# SLB_EXT_EAGLE.net
KiCad netlist of a schematic drawn in EAGLE
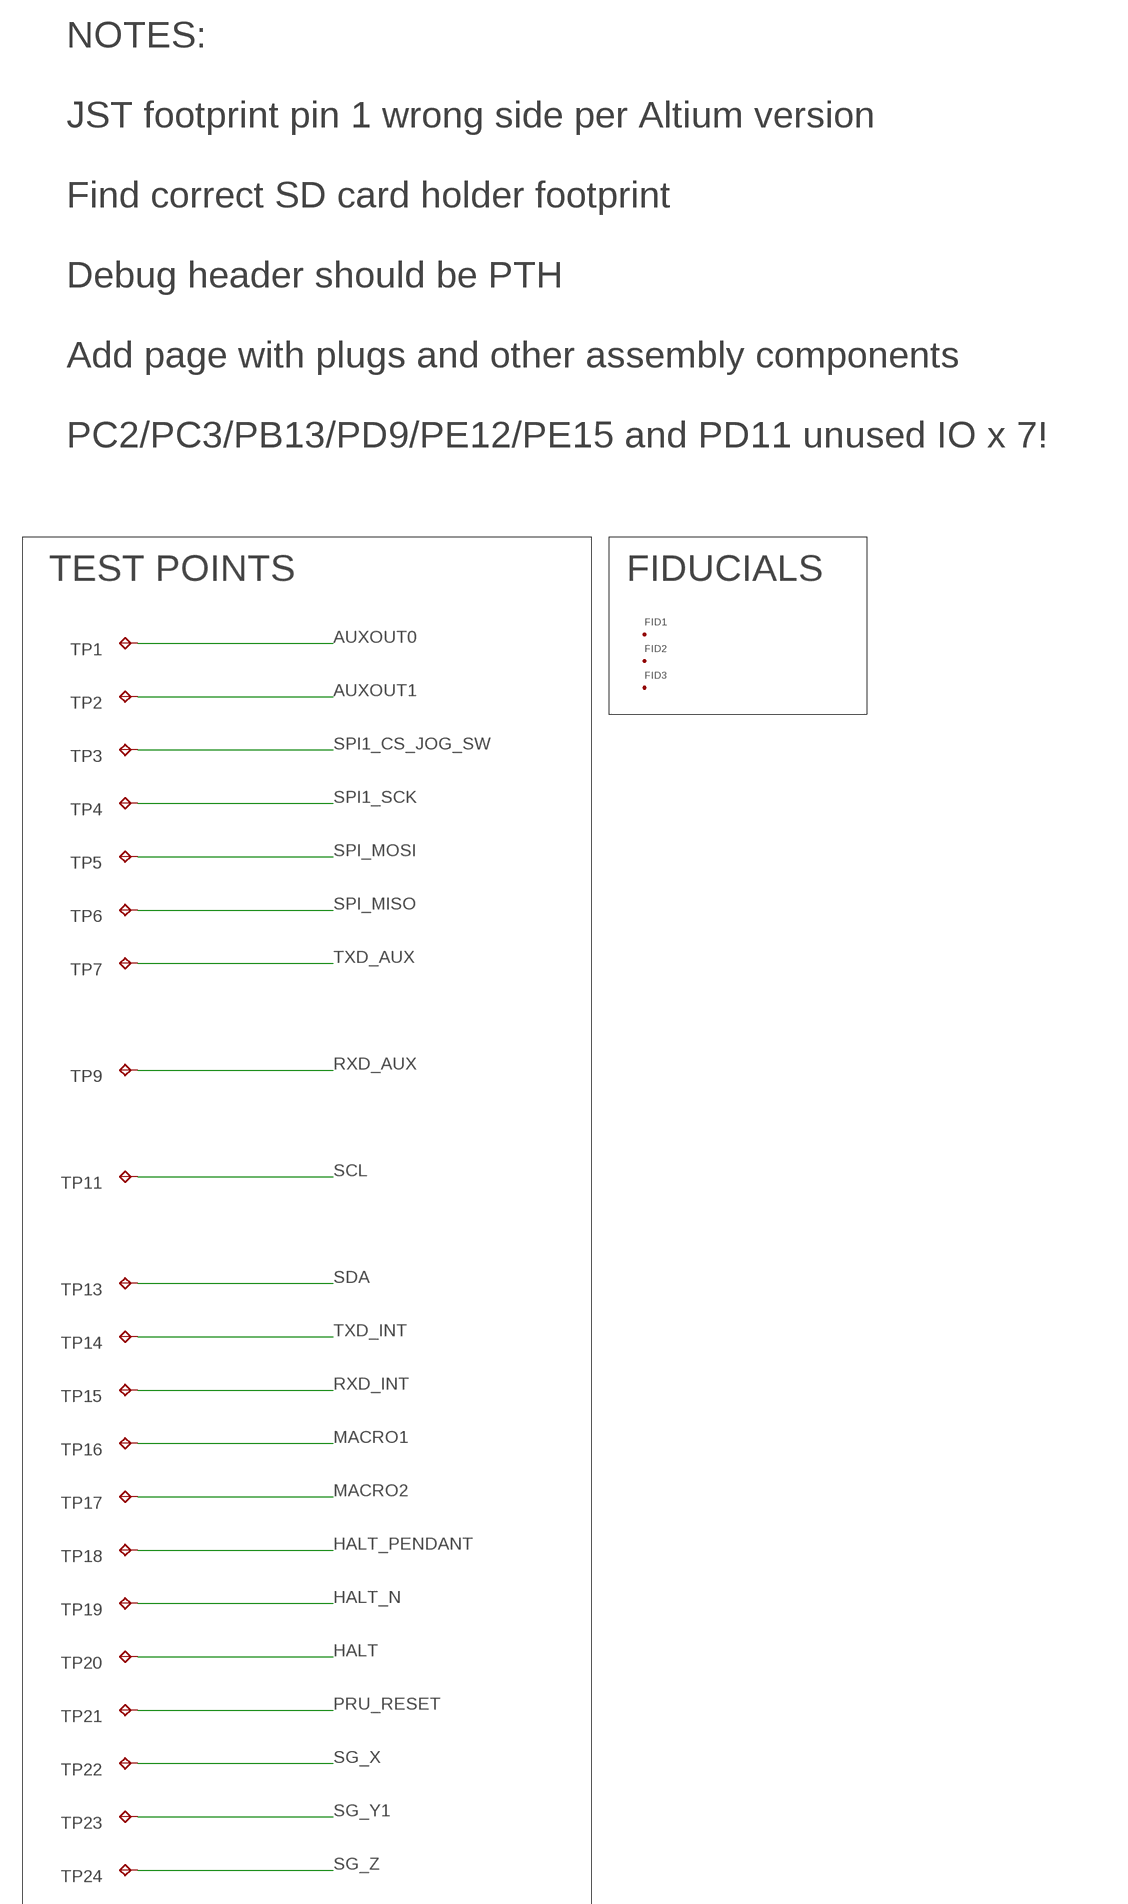
[diagram p0: schematic, sheet 1, part 1 of 2]
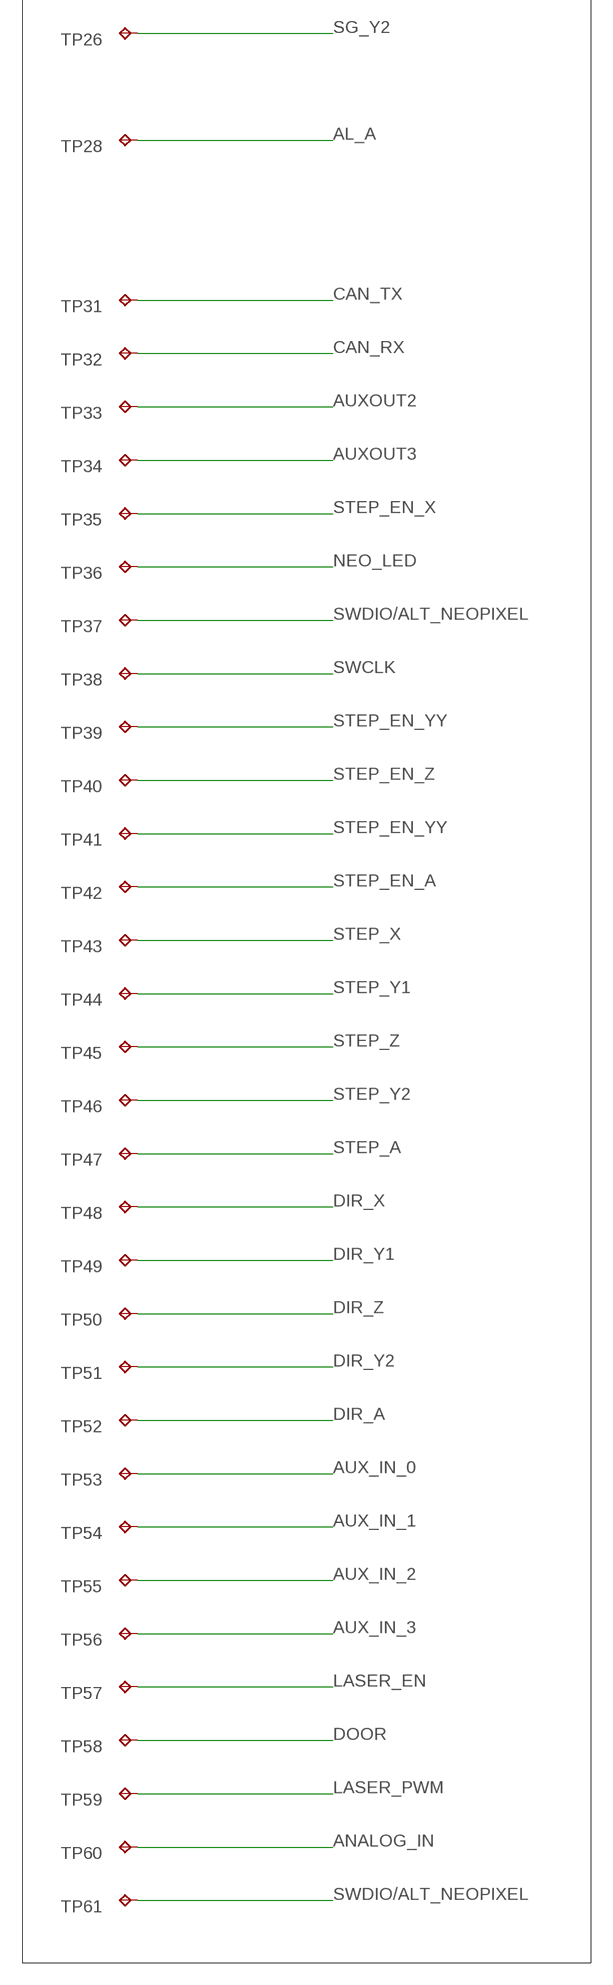
[diagram p1: schematic, sheet 1, part 2 of 2]
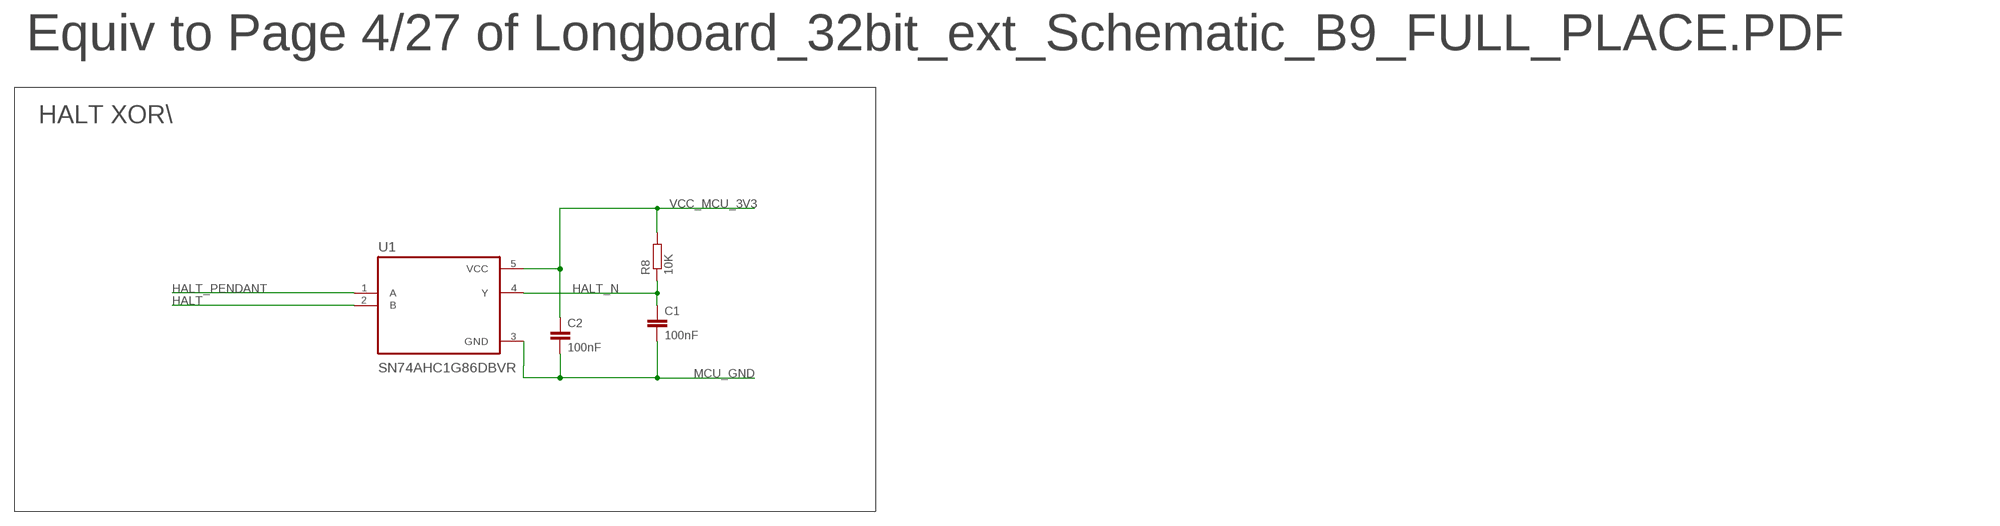
[diagram p2: schematic, sheet 2]
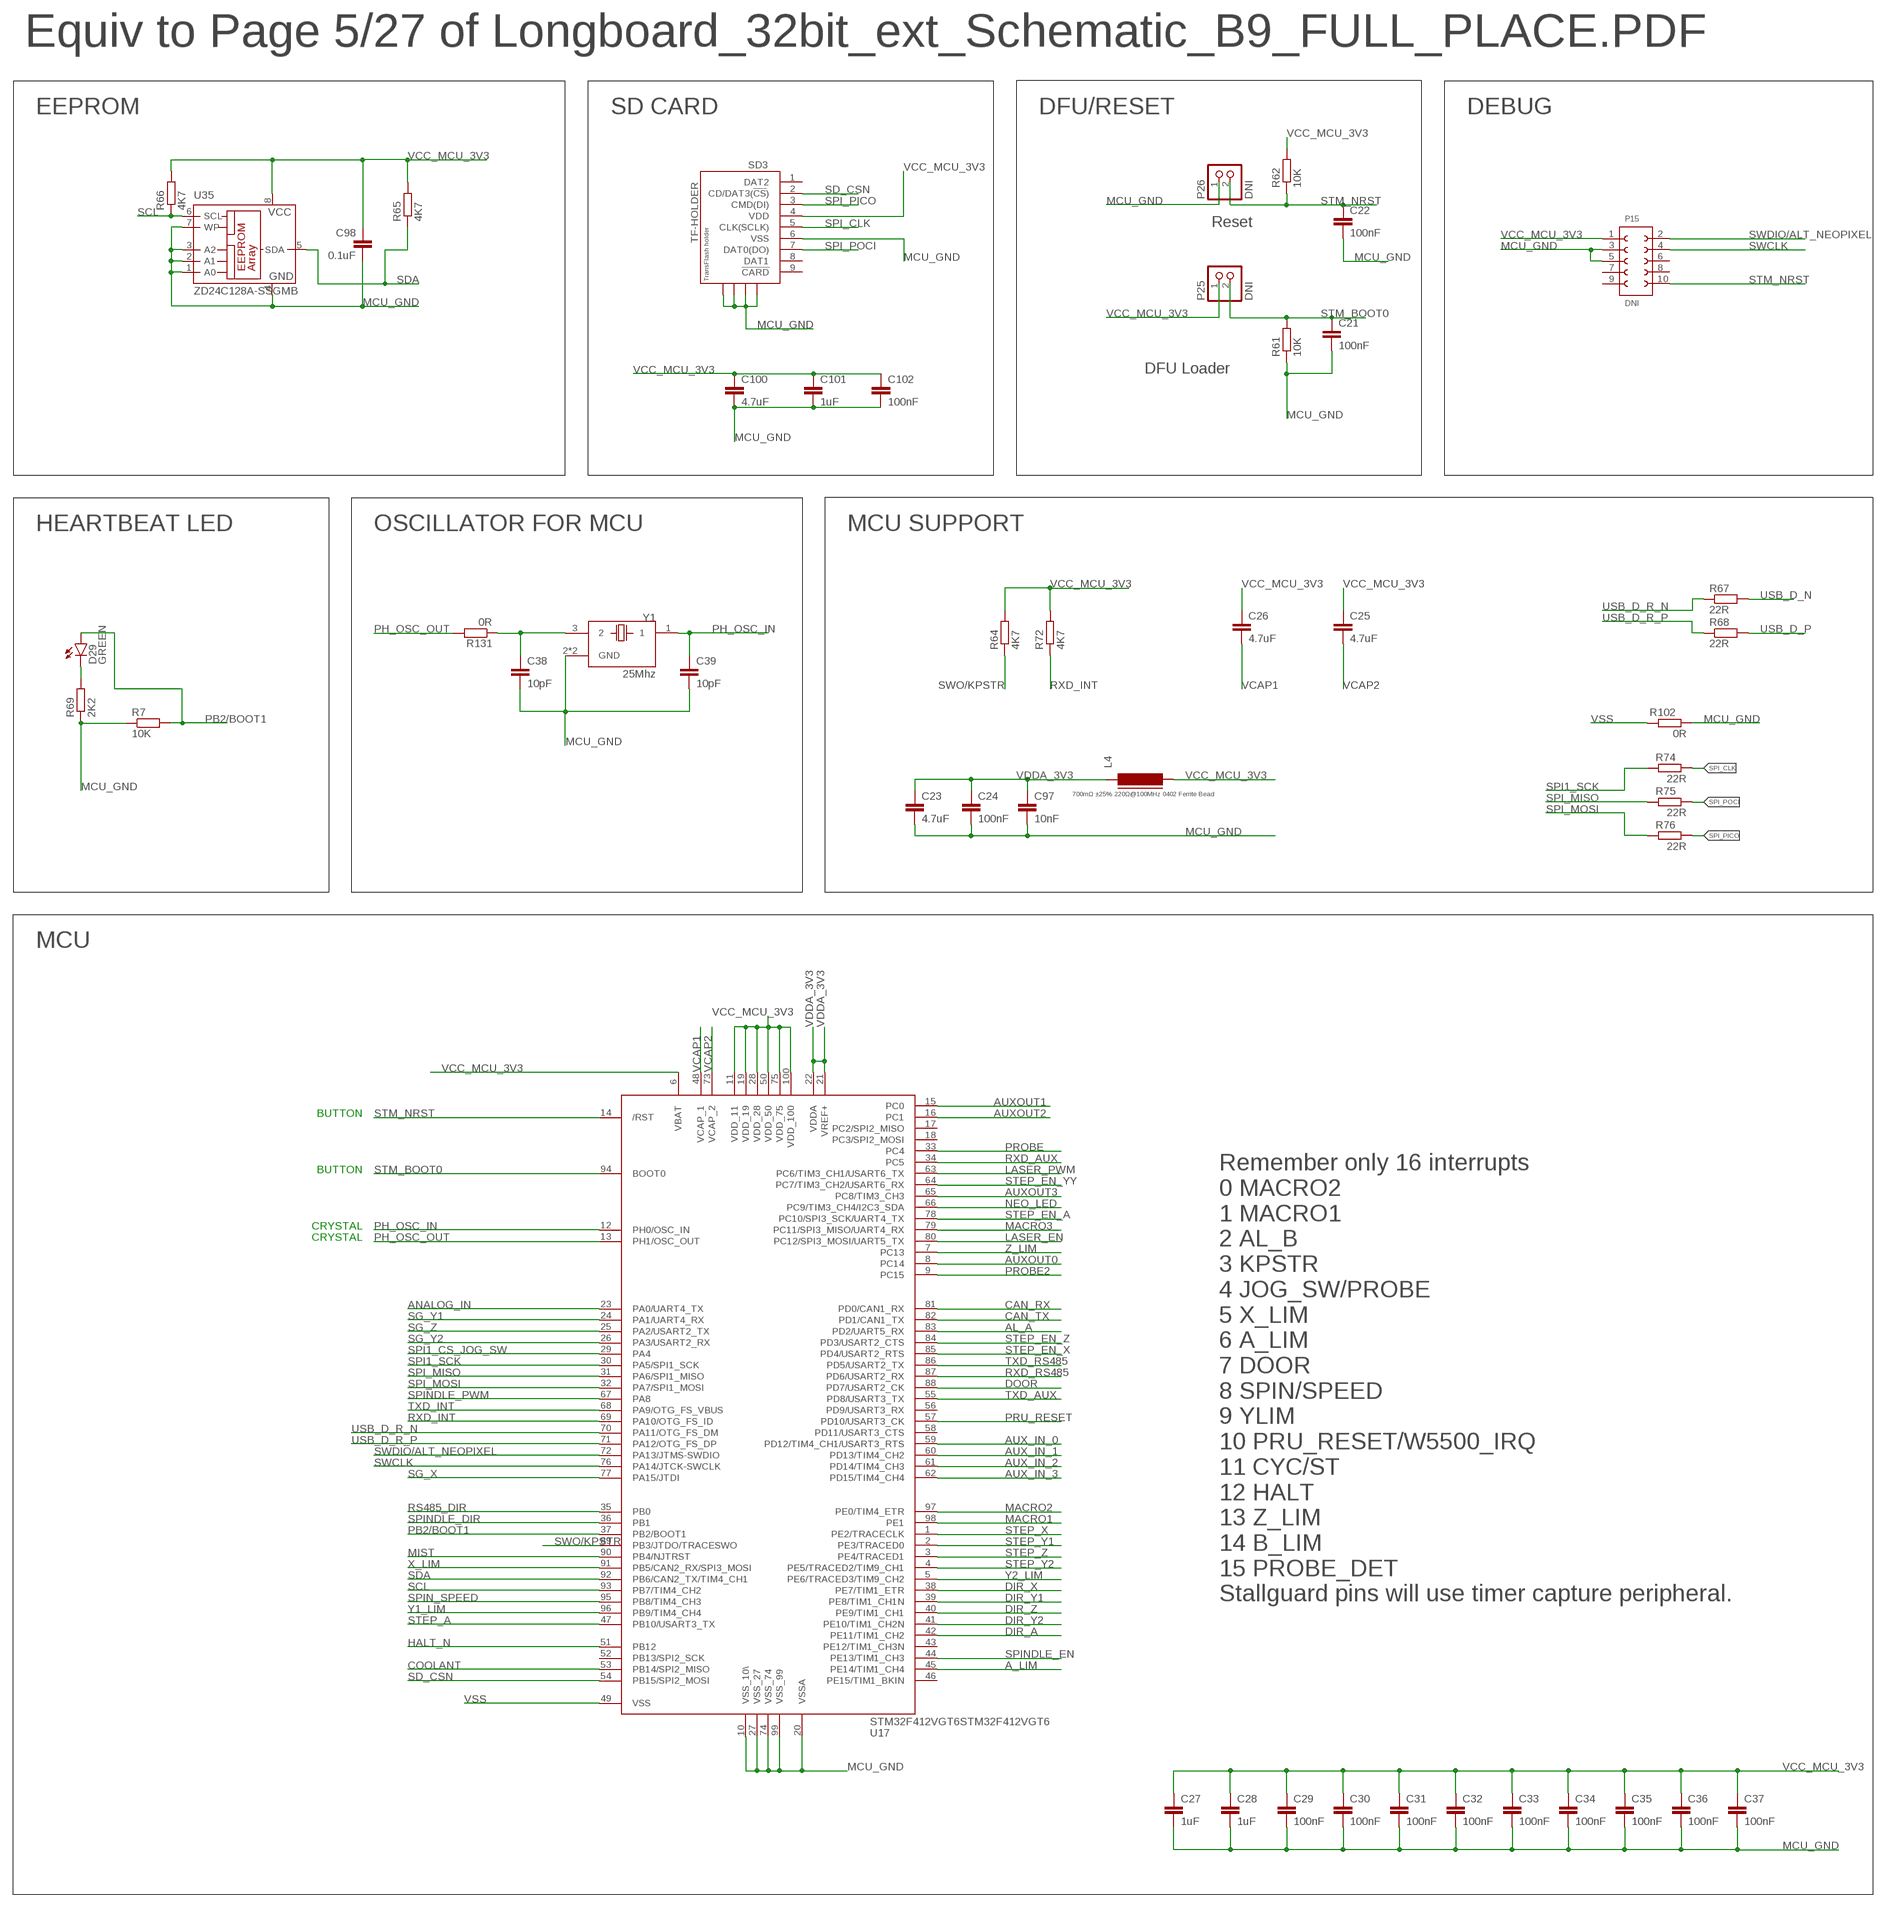
[diagram p3: schematic, sheet 3]
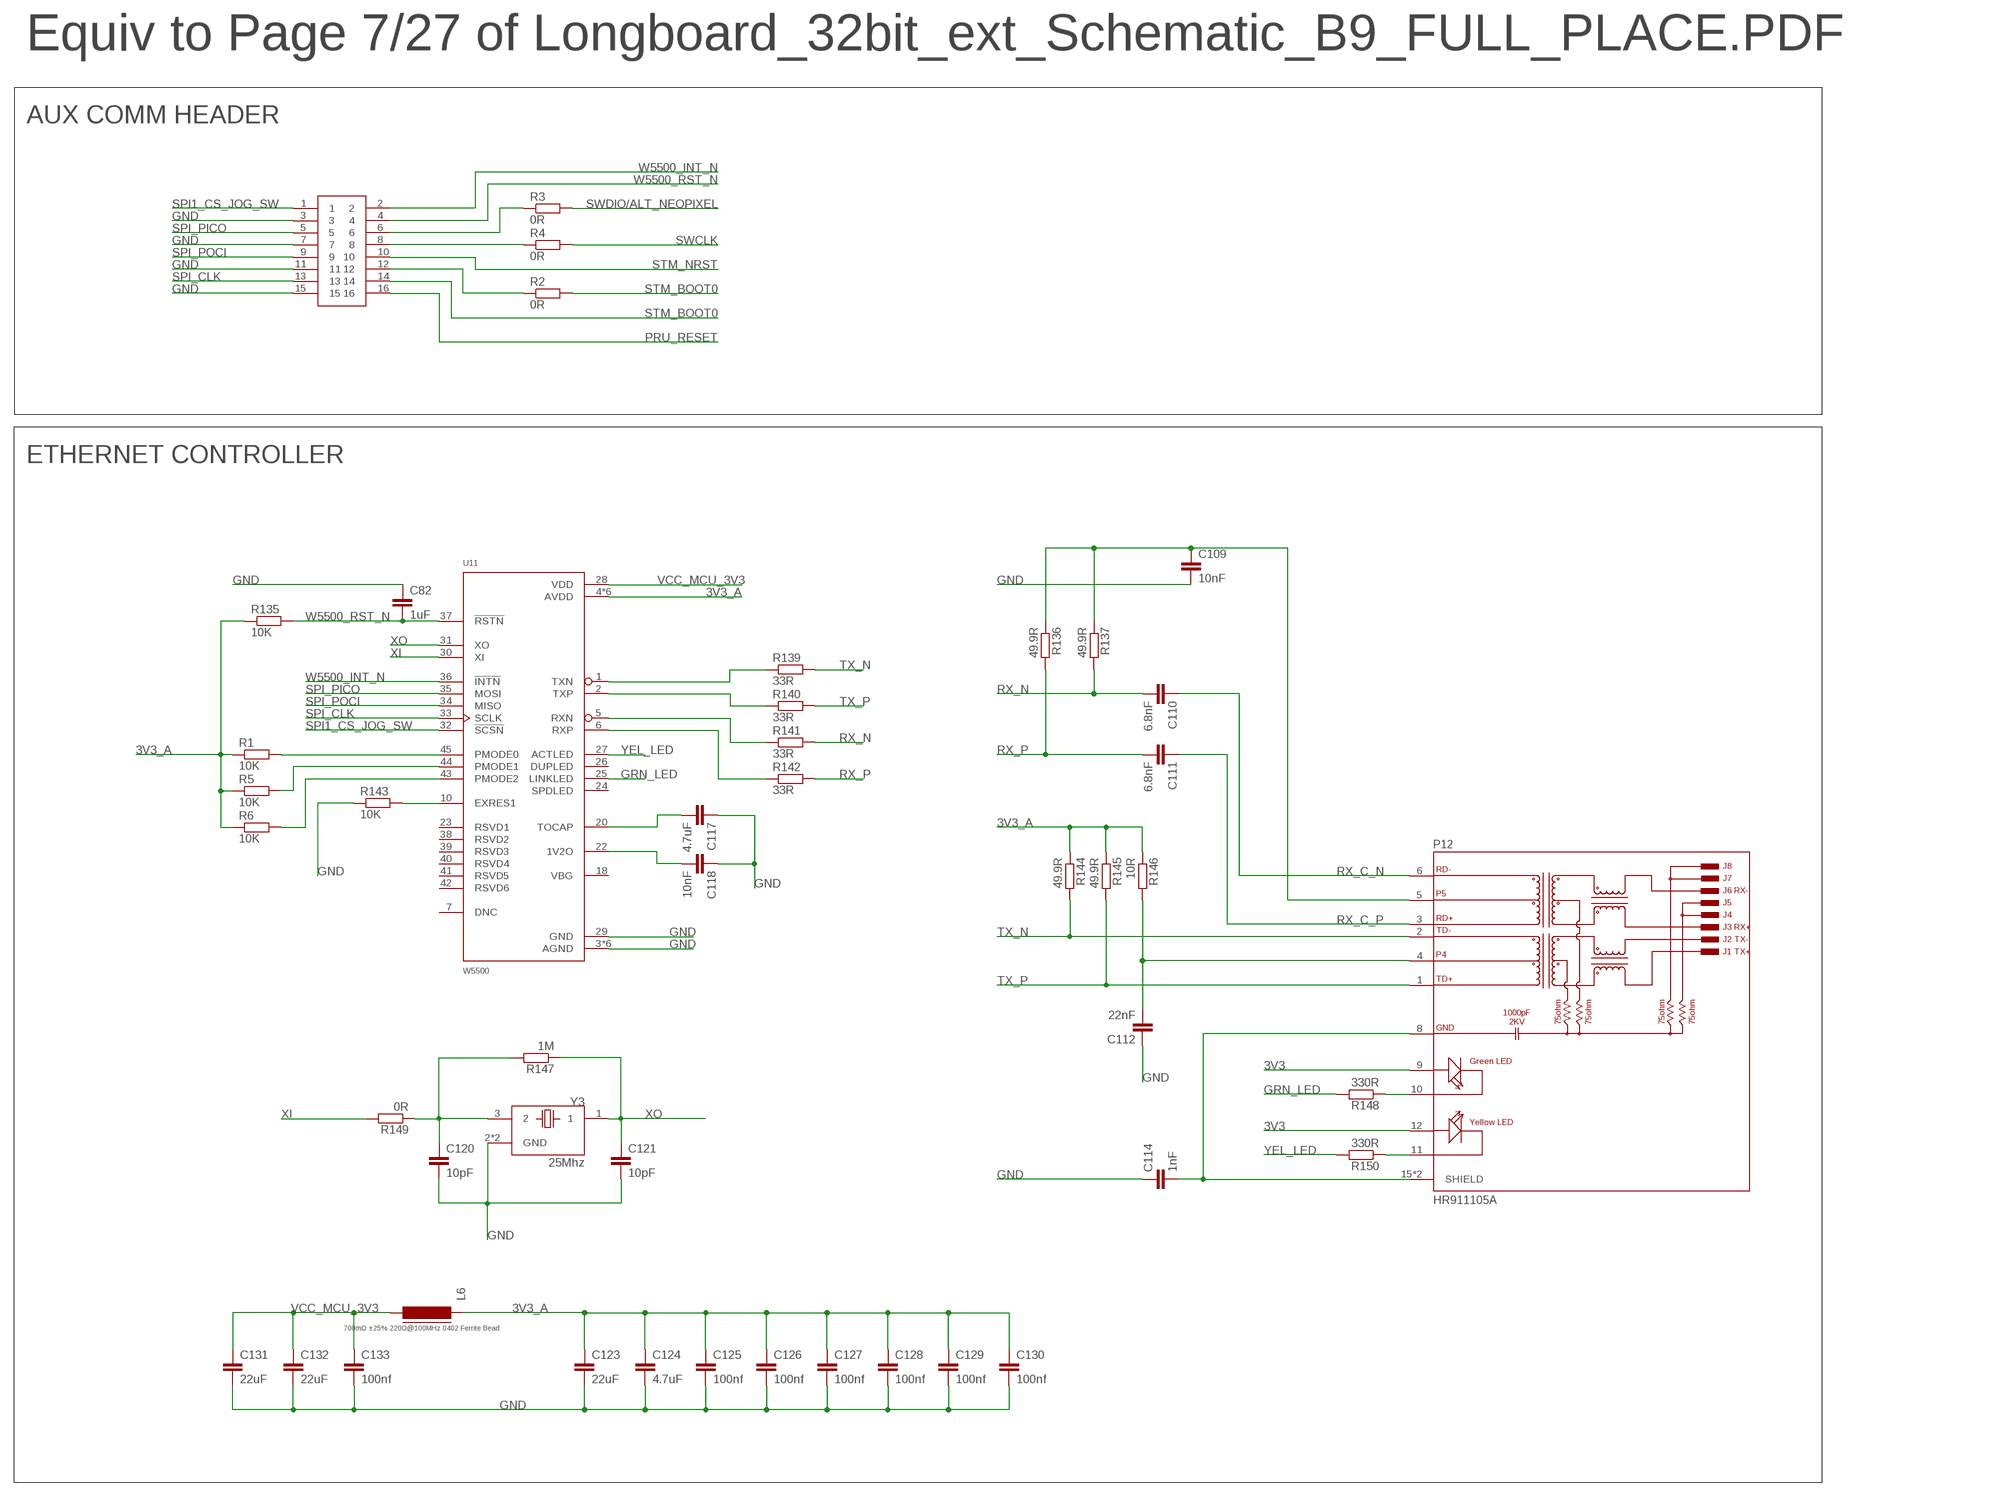
[diagram p4: schematic, sheet 4]
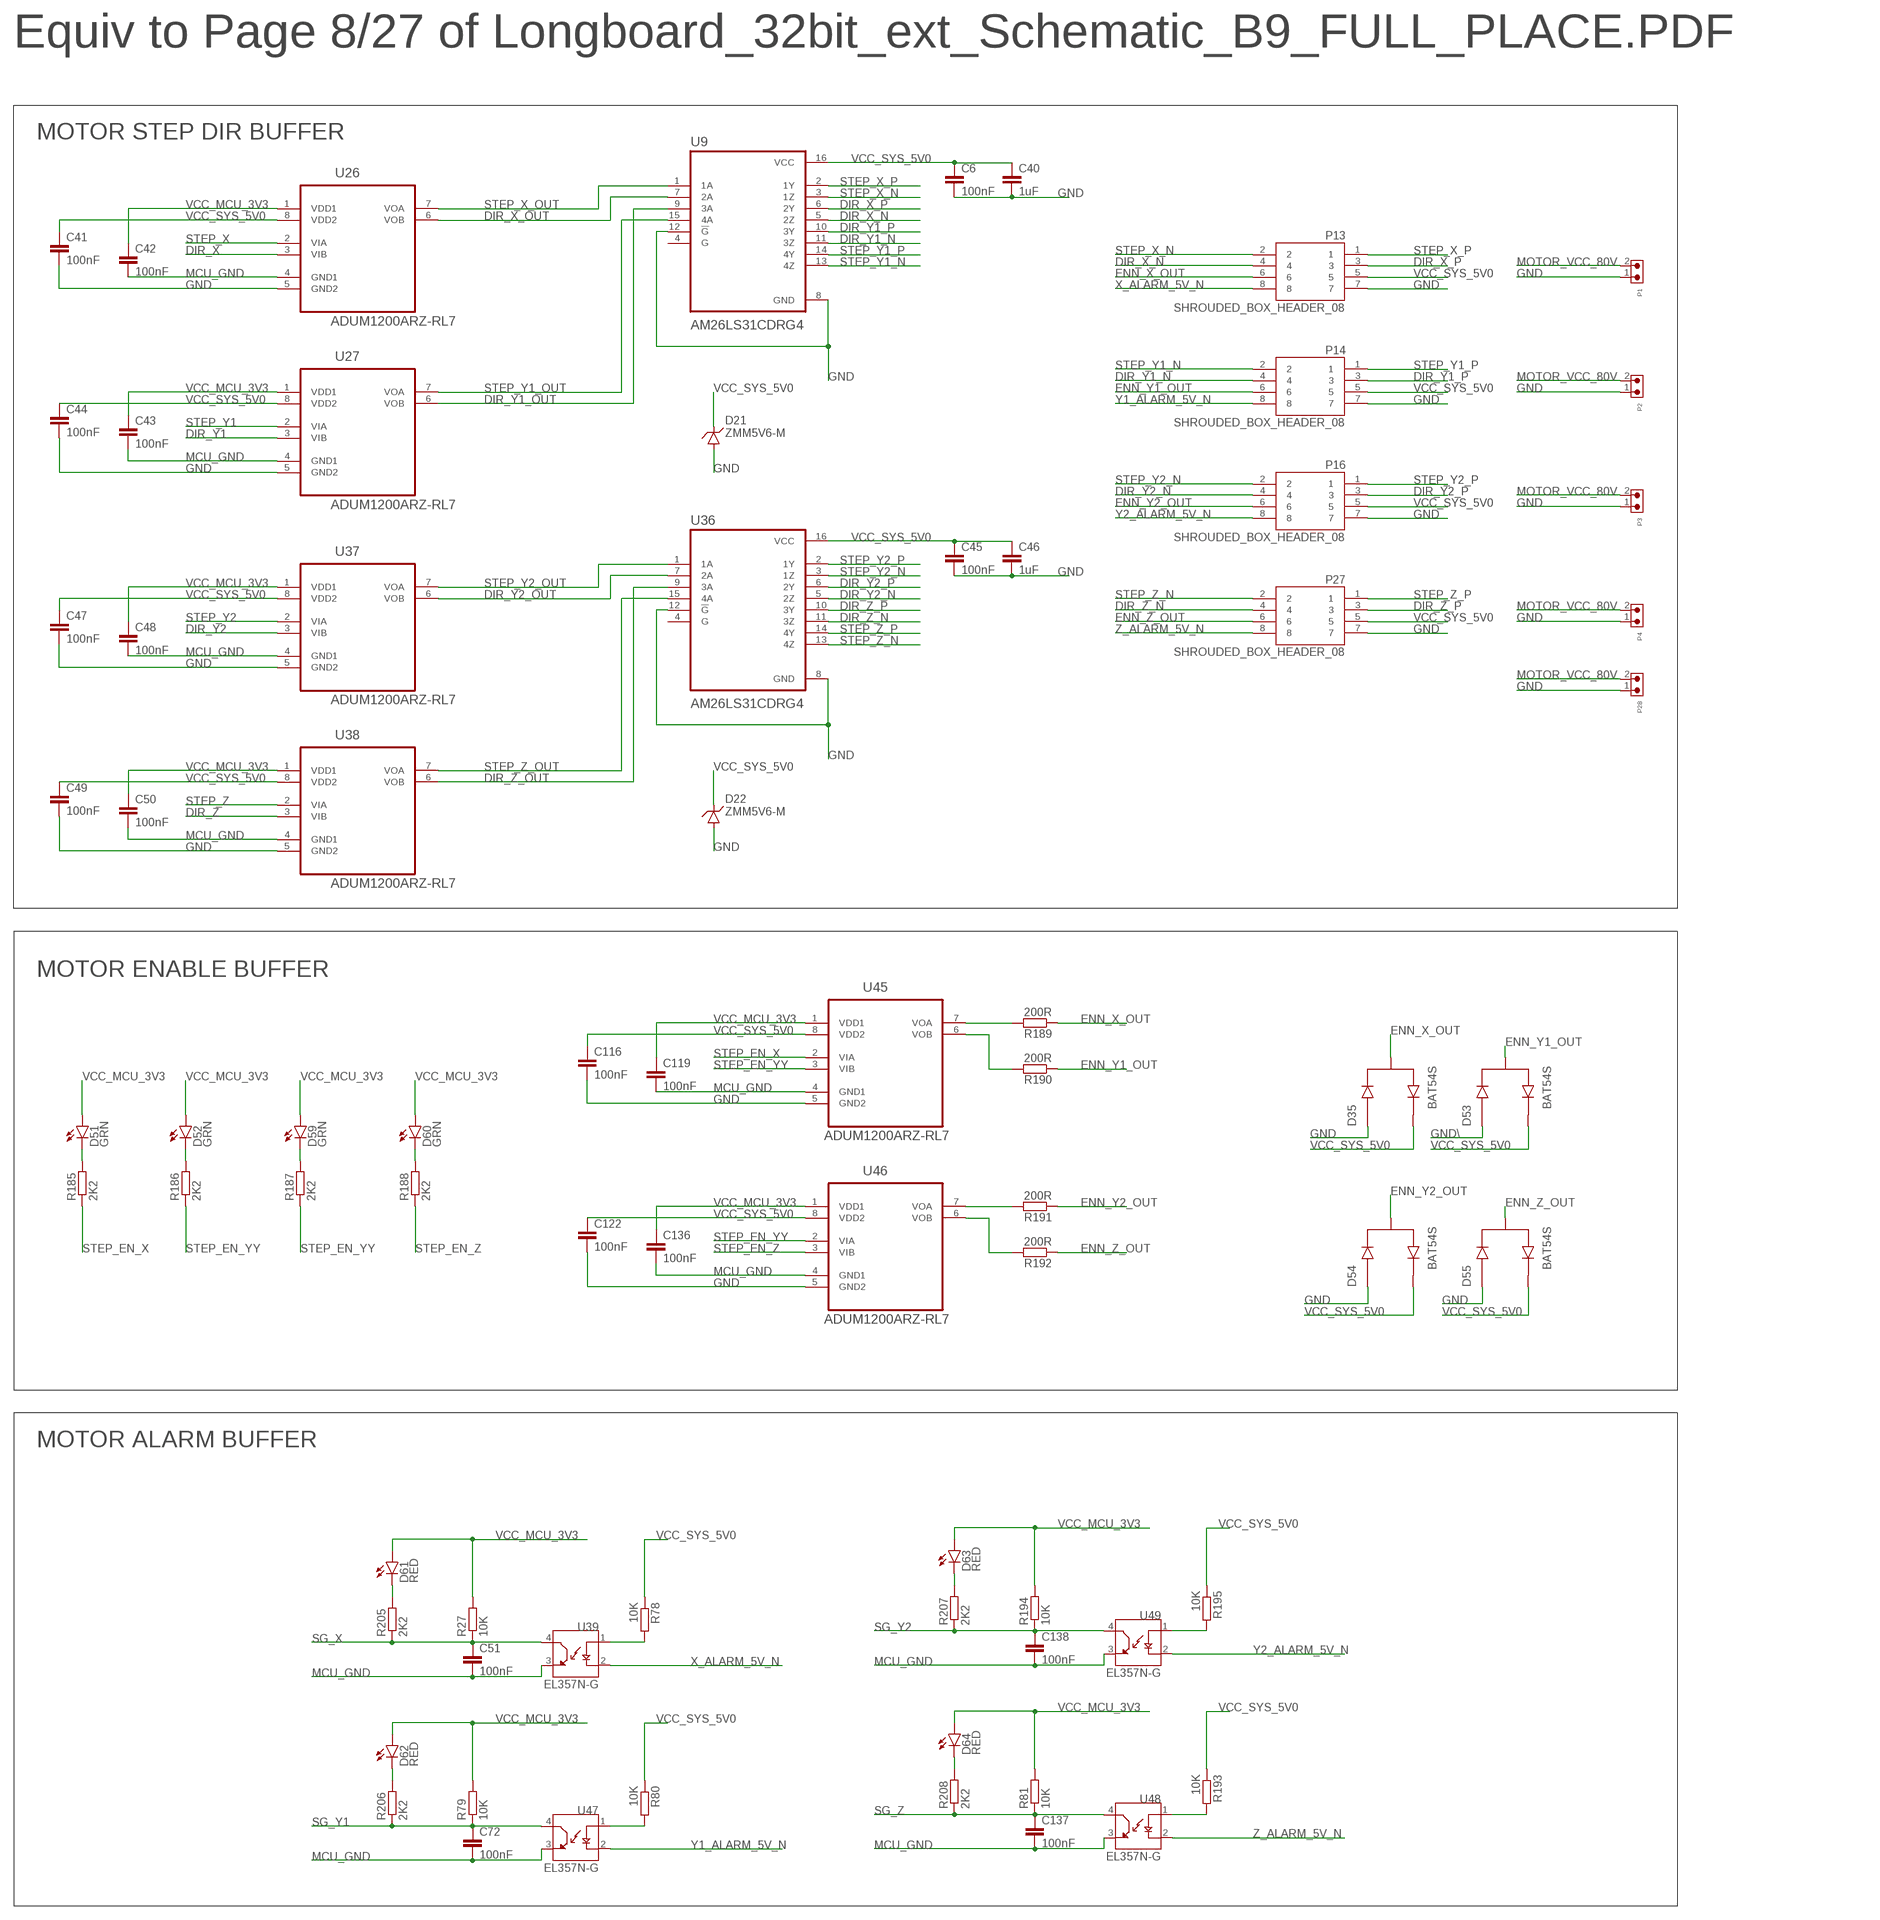
[diagram p5: schematic, sheet 5]
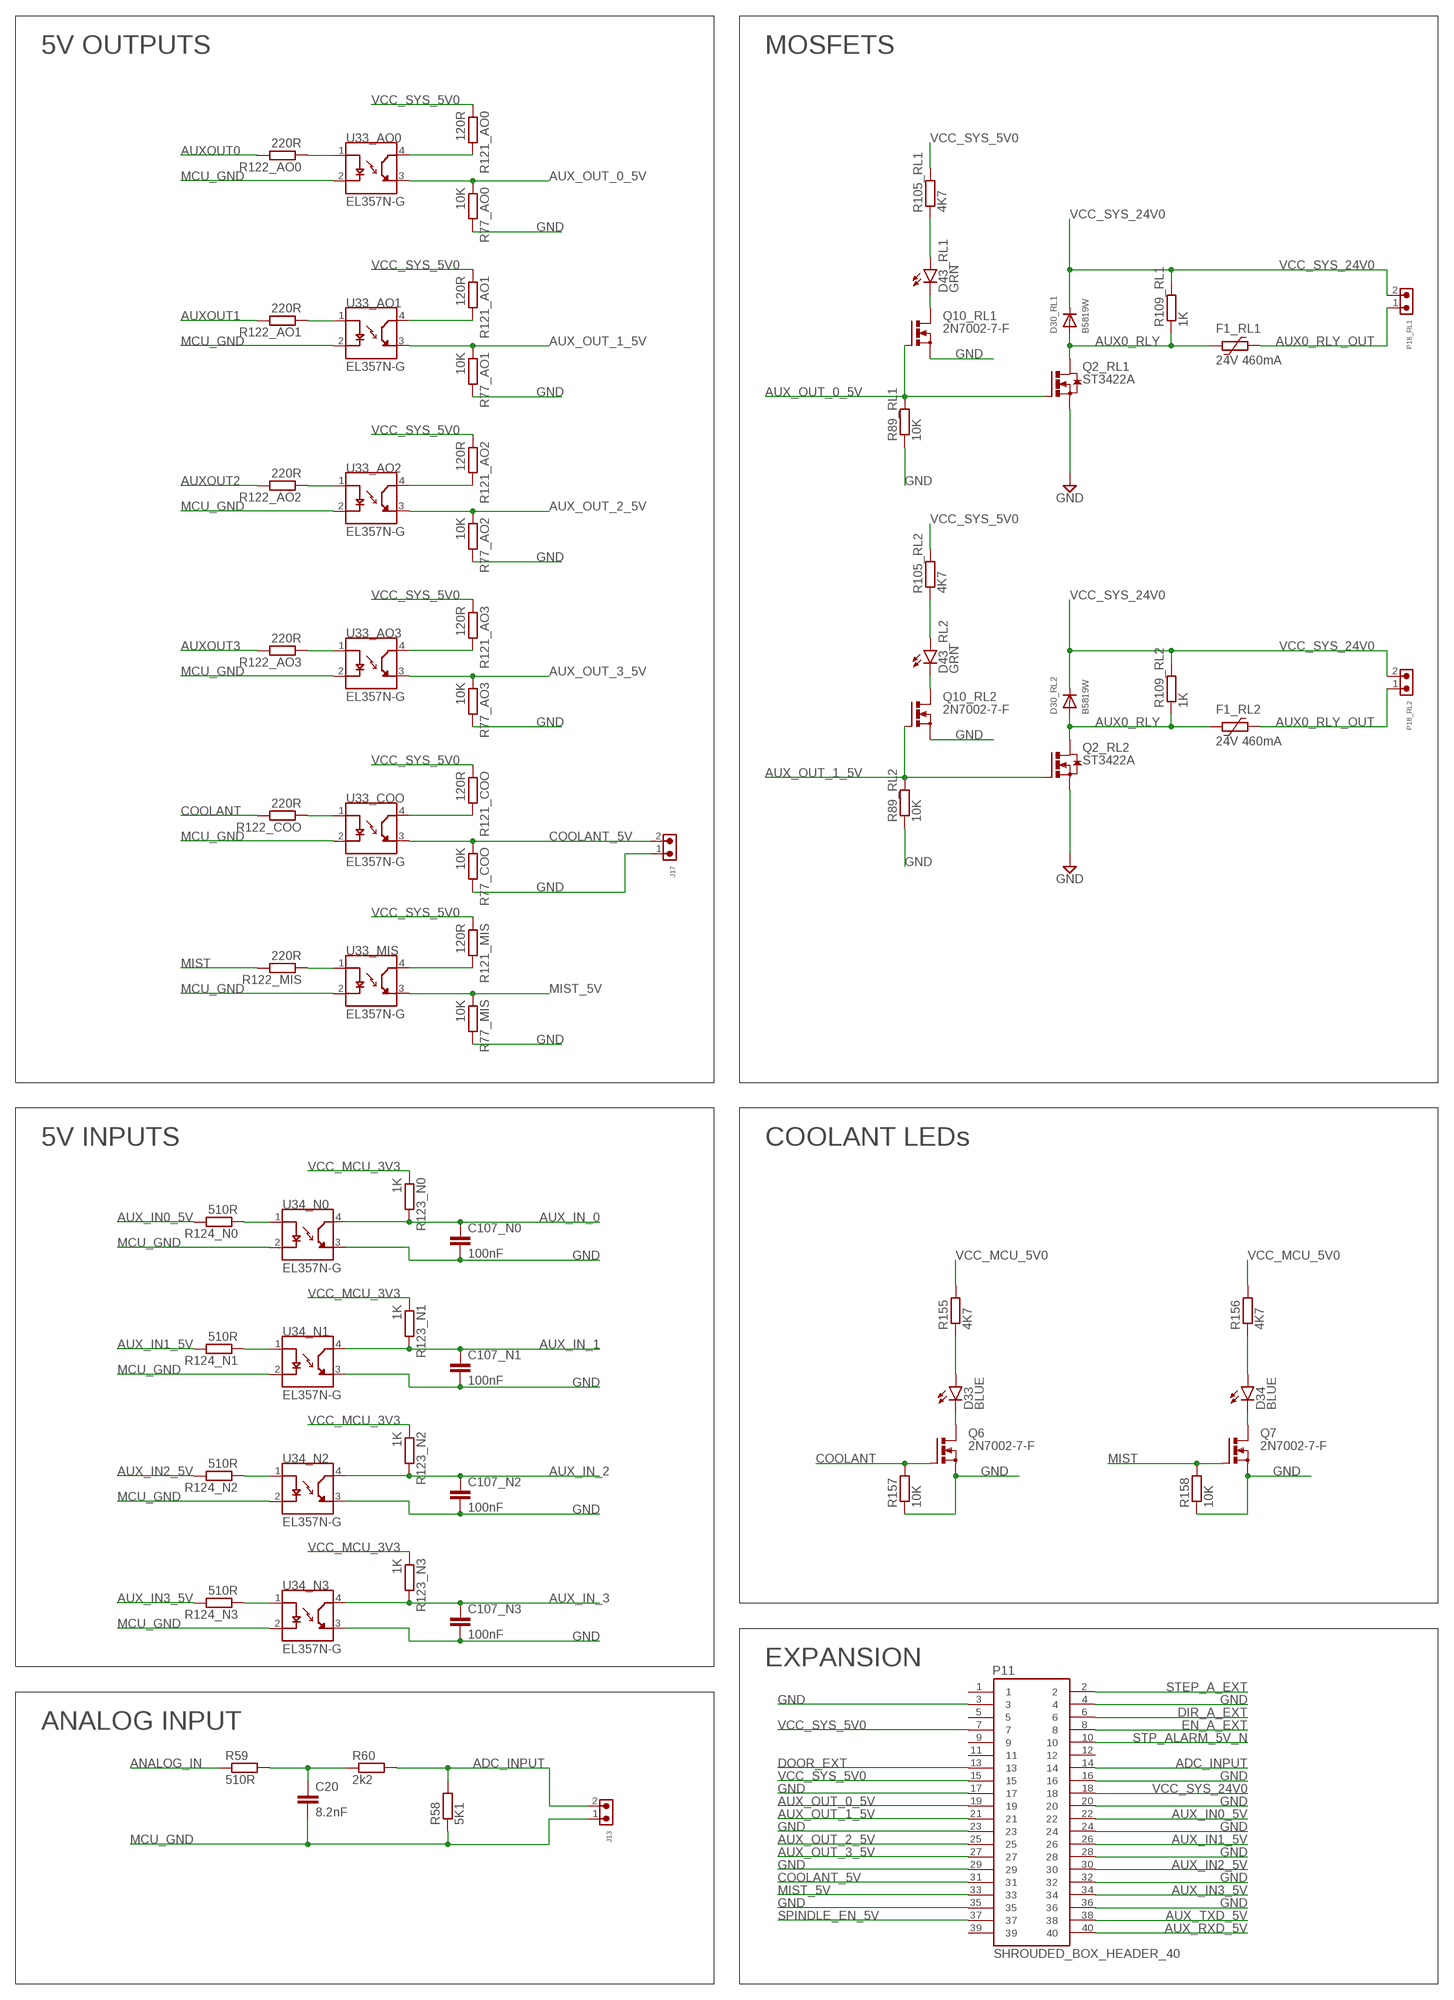
[diagram p6: schematic, sheet 6, part 1 of 2]
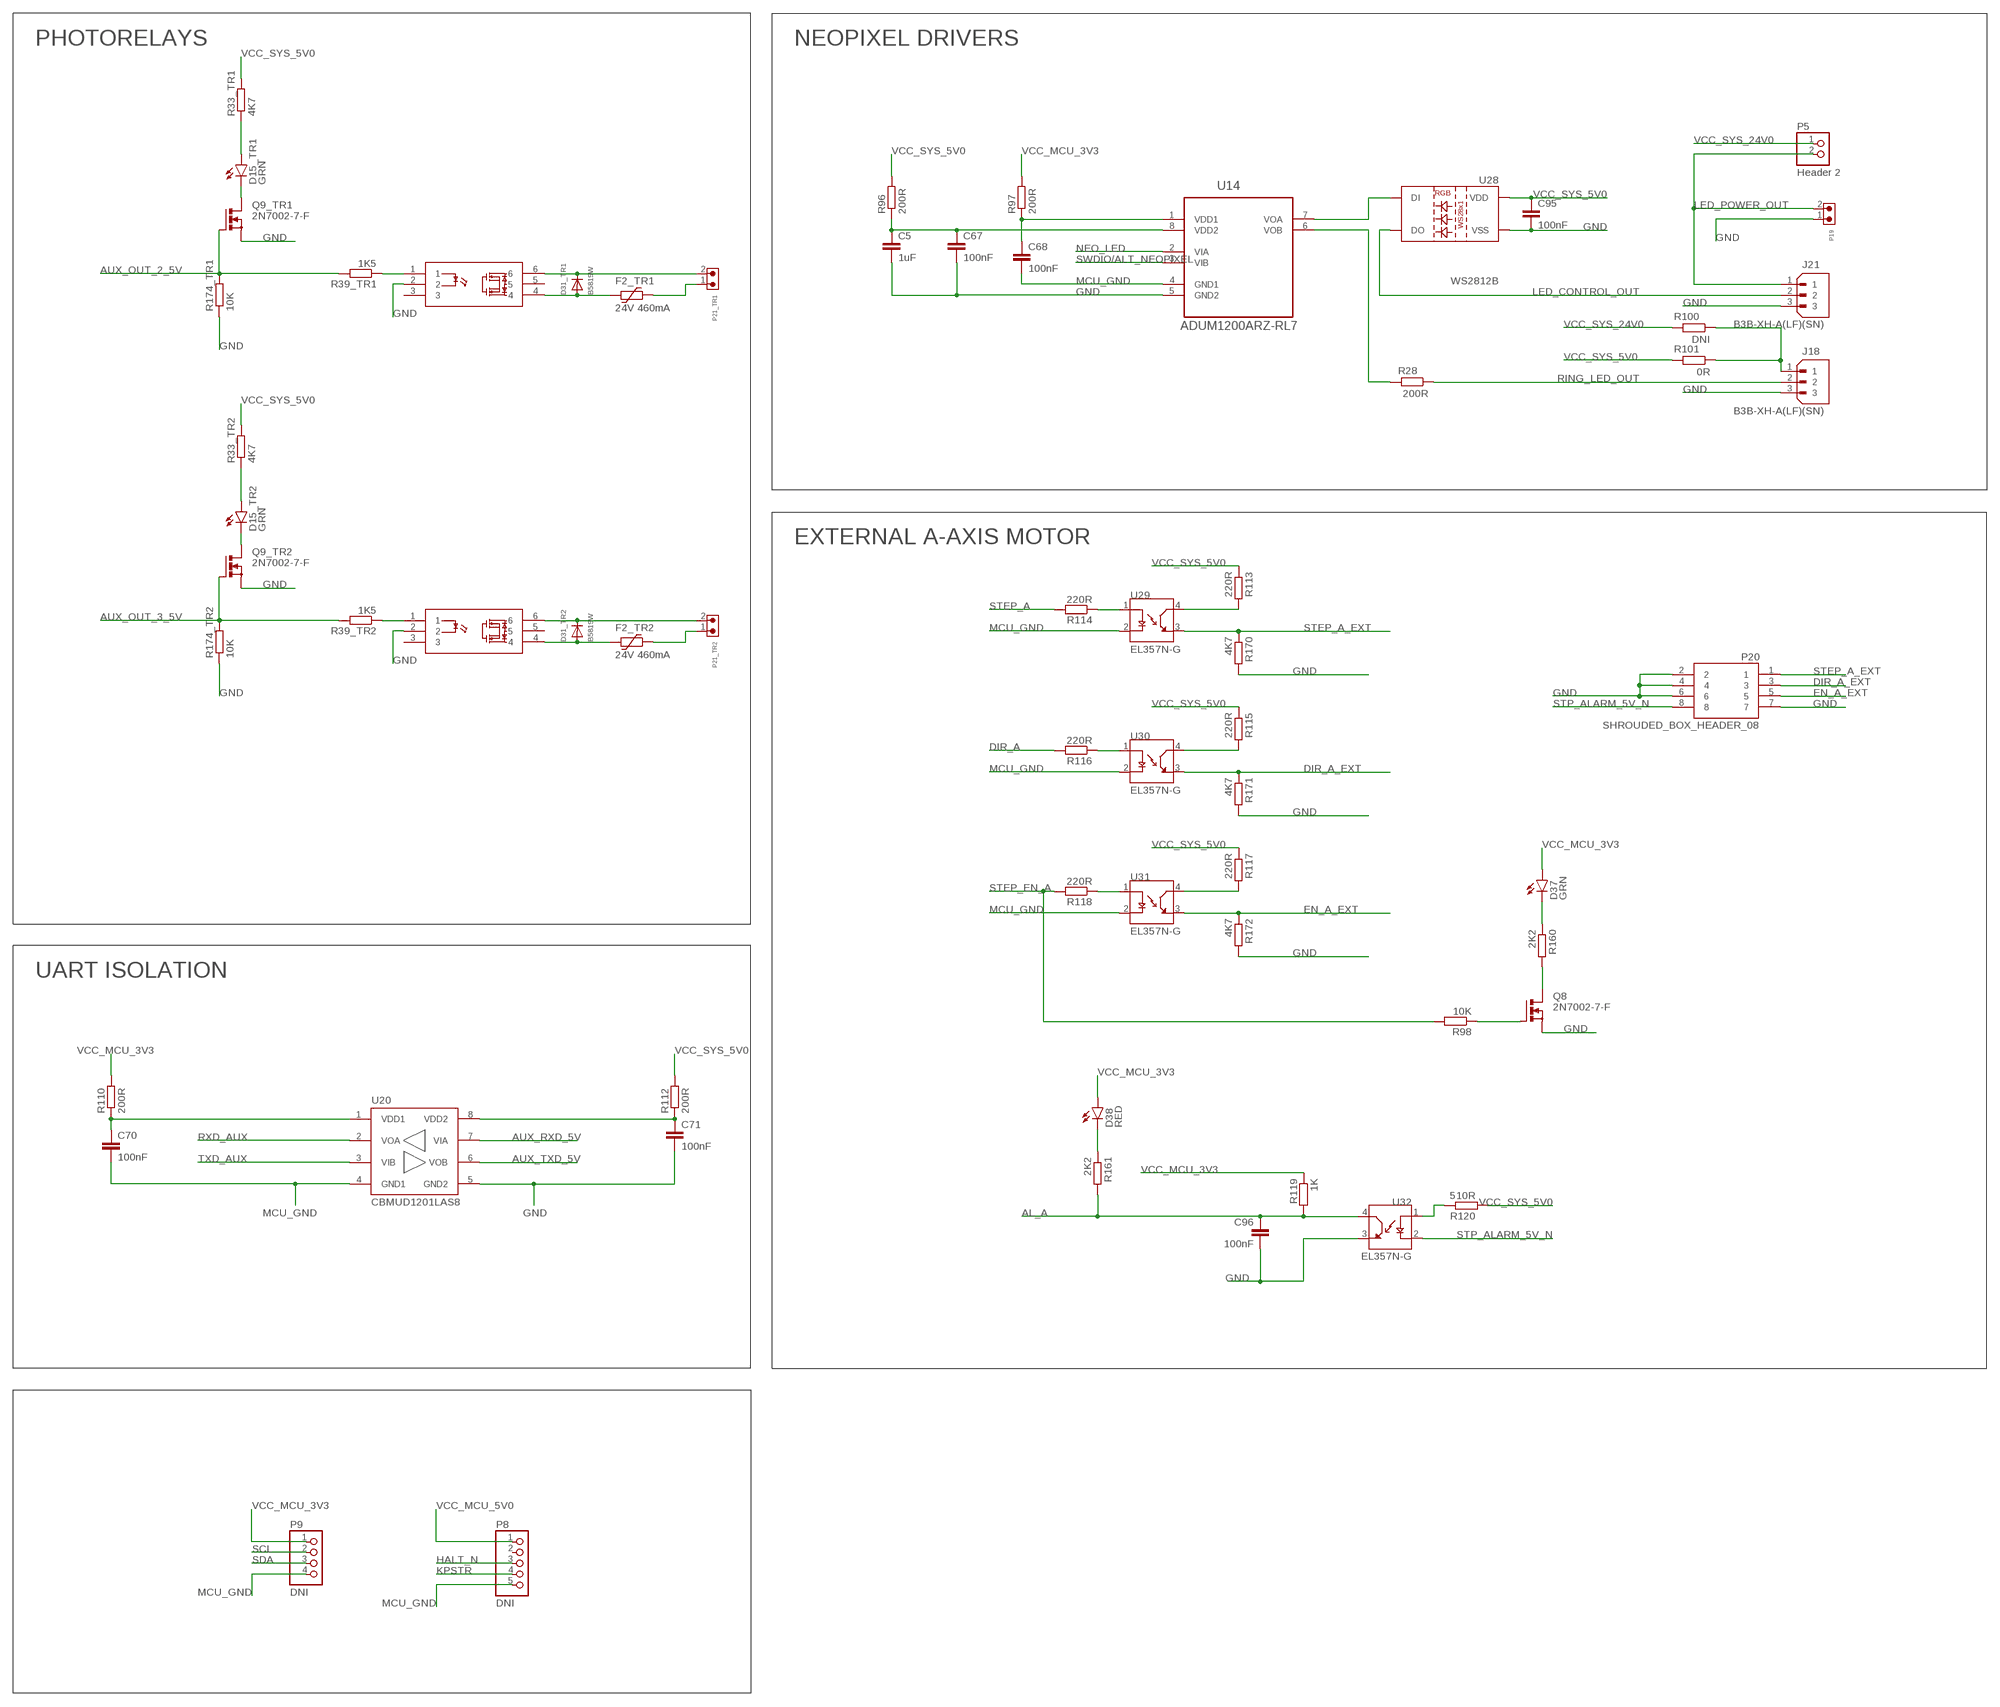
[diagram p7: schematic, sheet 6, part 2 of 2]
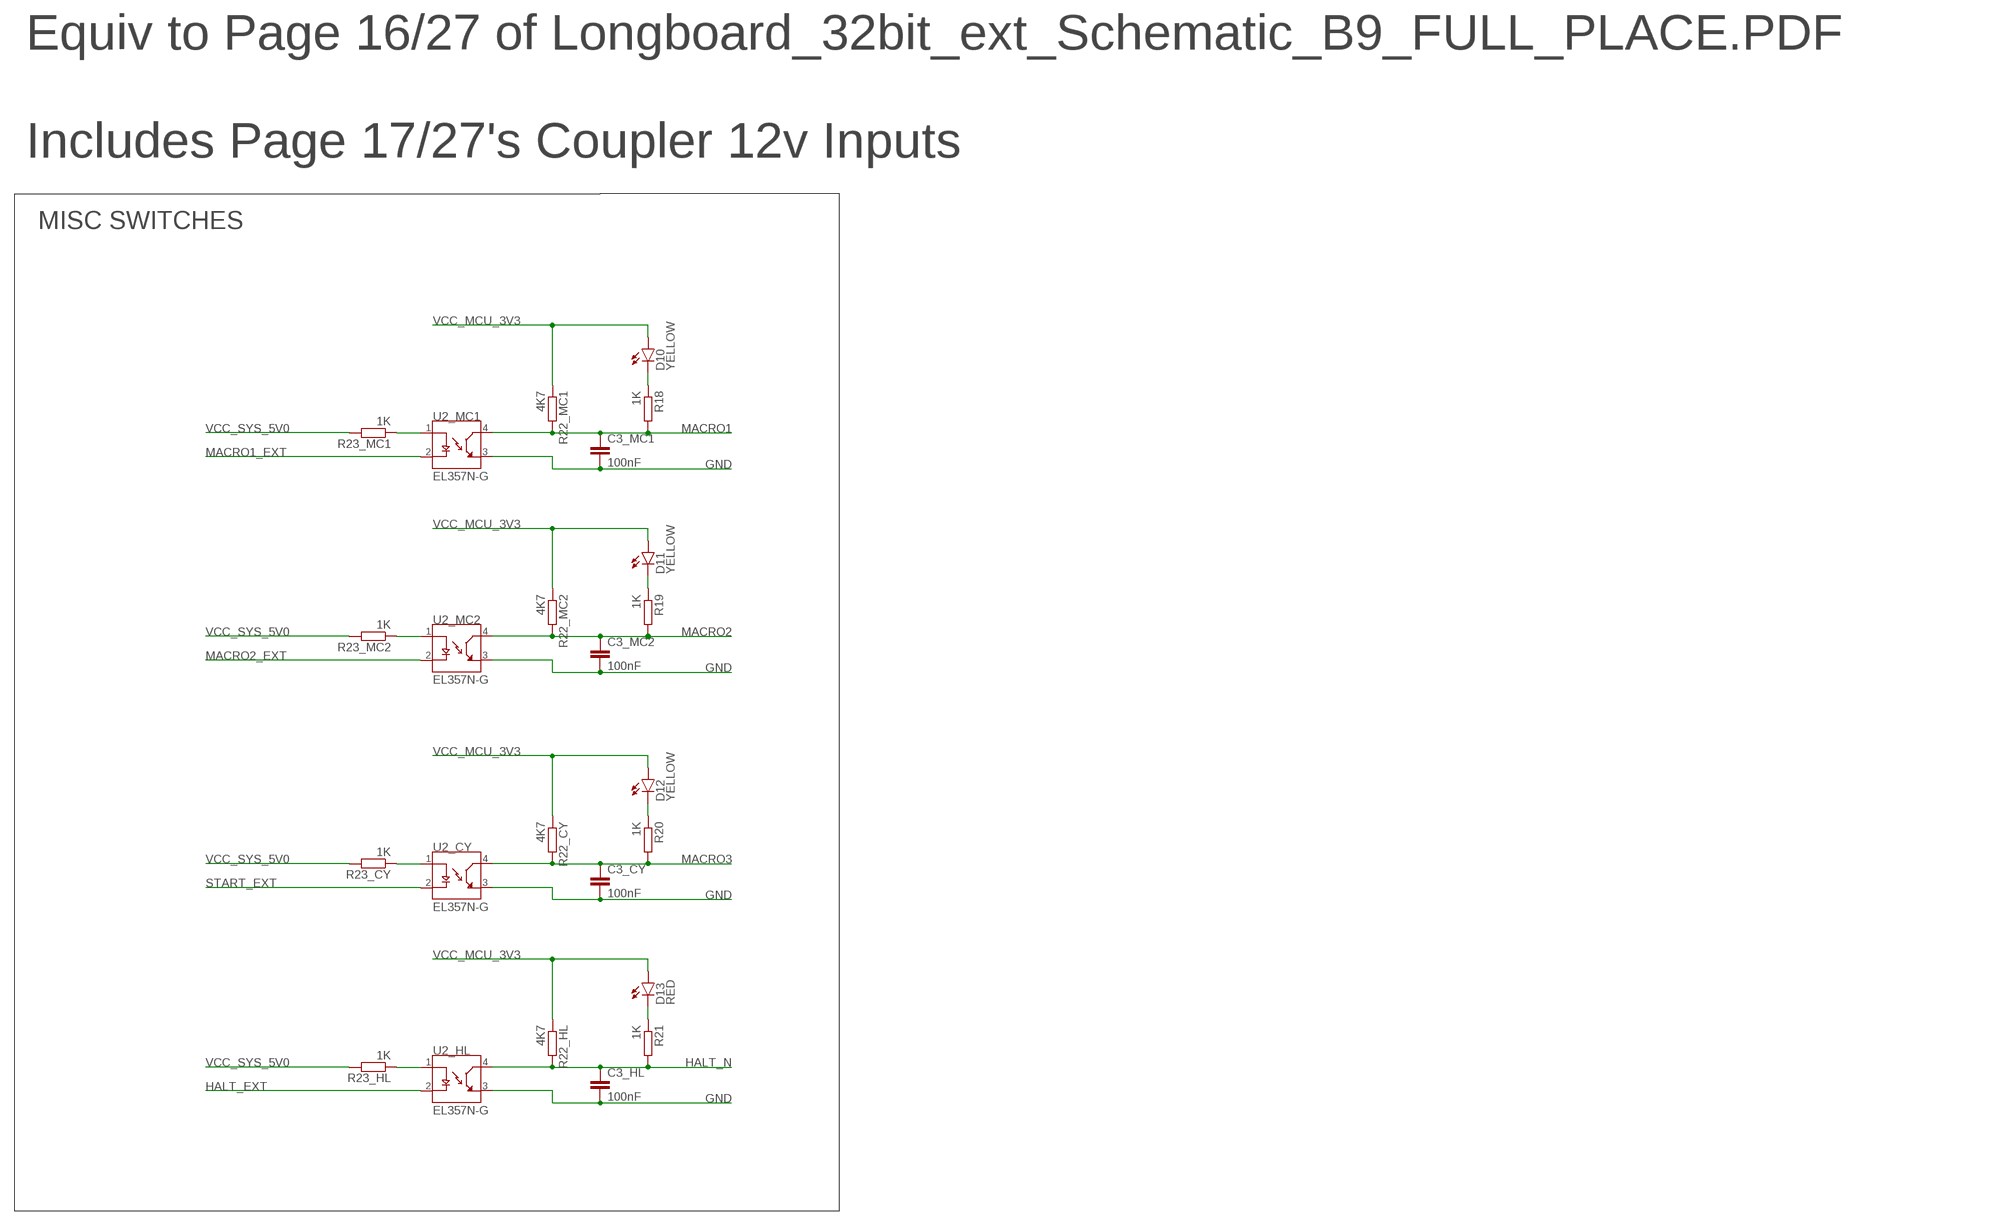
[diagram p8: schematic, sheet 7]
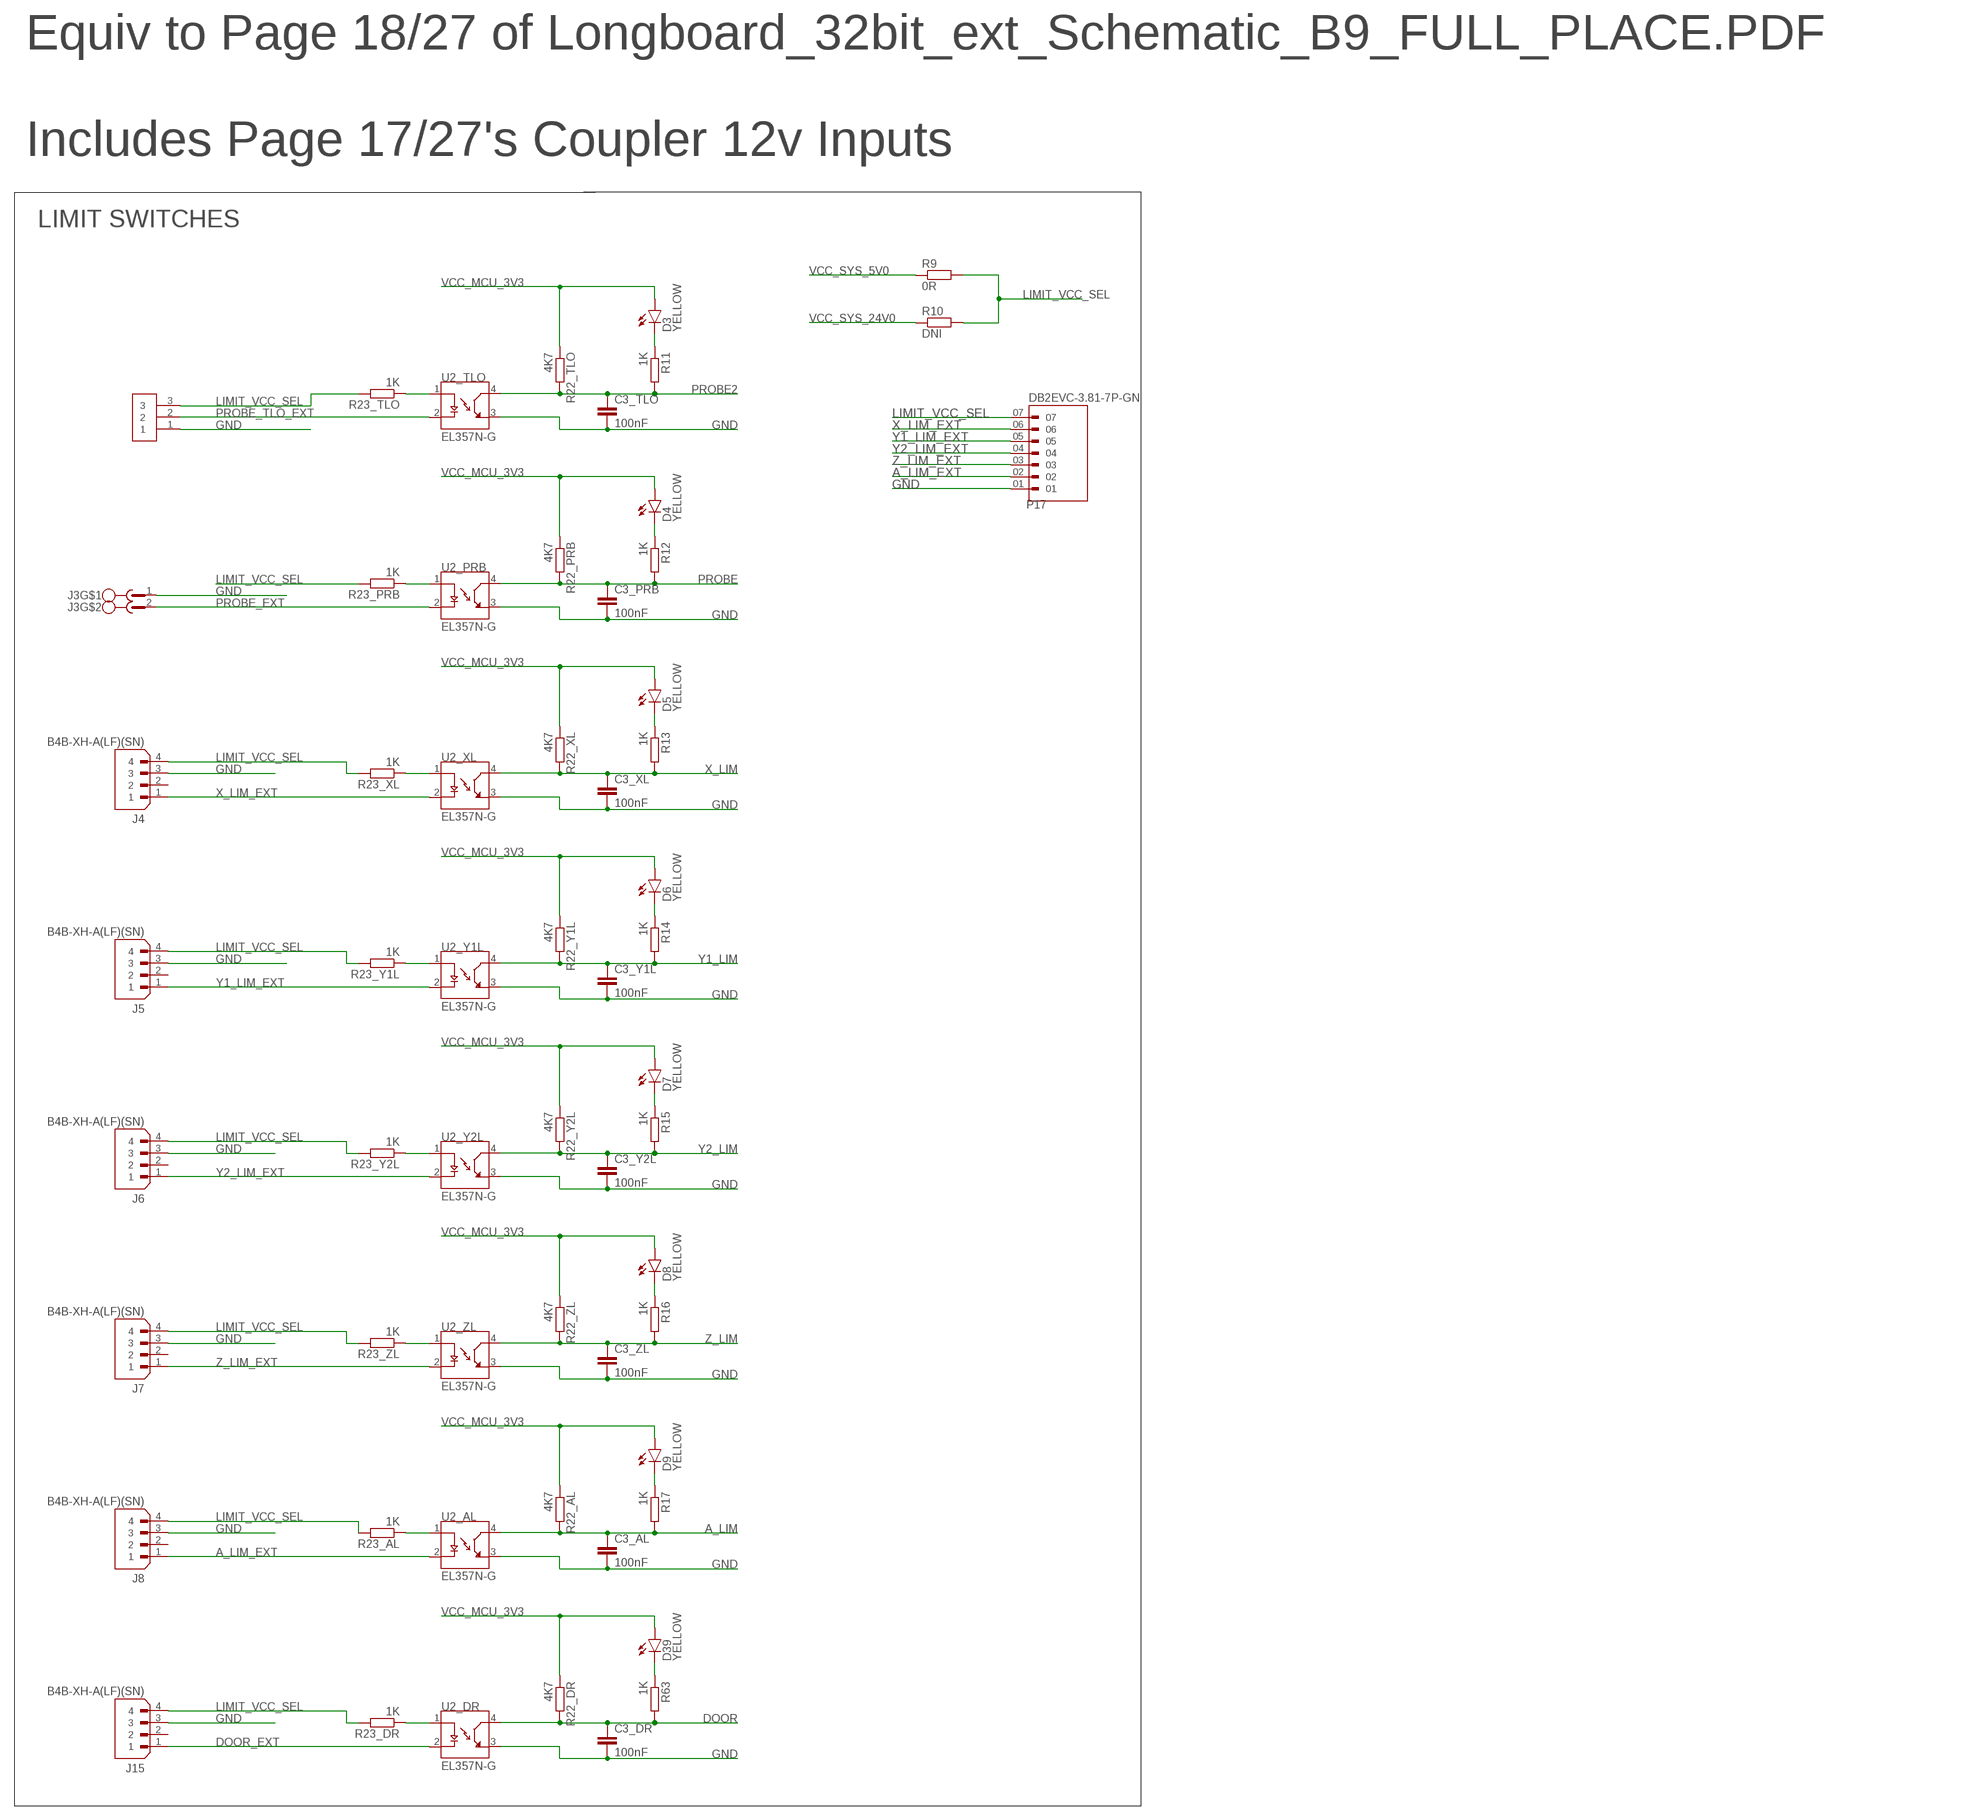
[diagram p9: schematic, sheet 8]
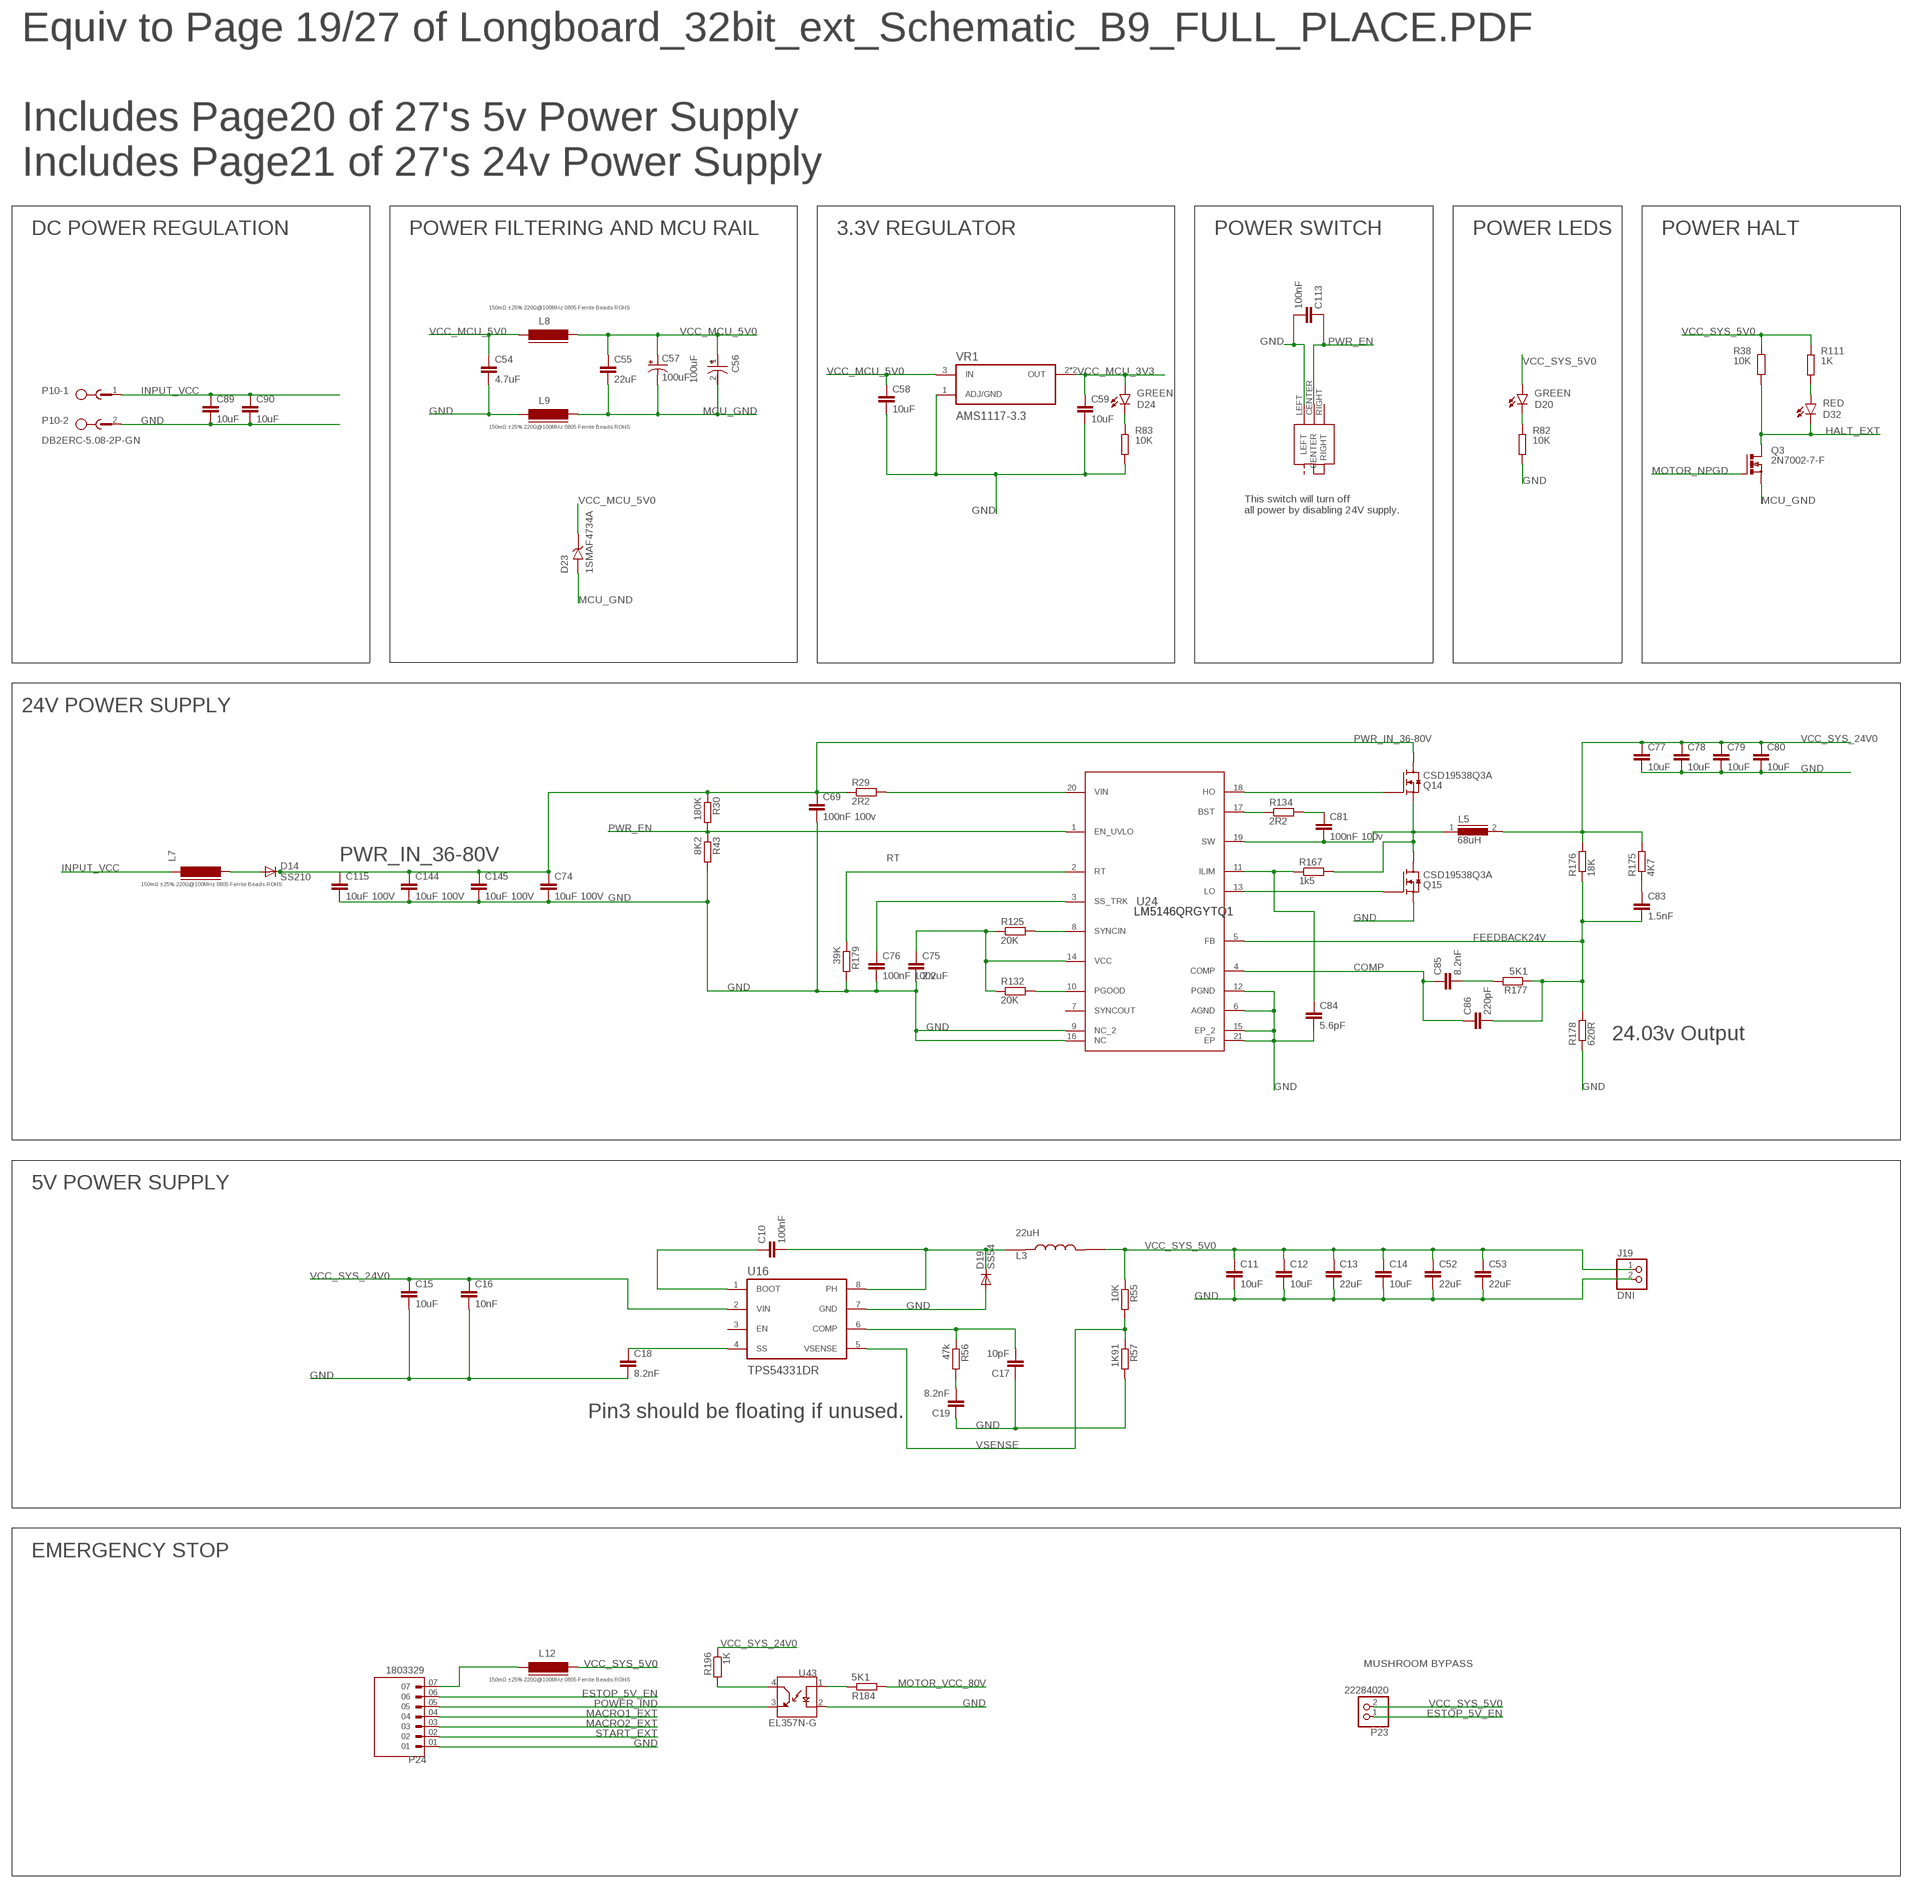
[diagram p10: schematic, sheet 9]
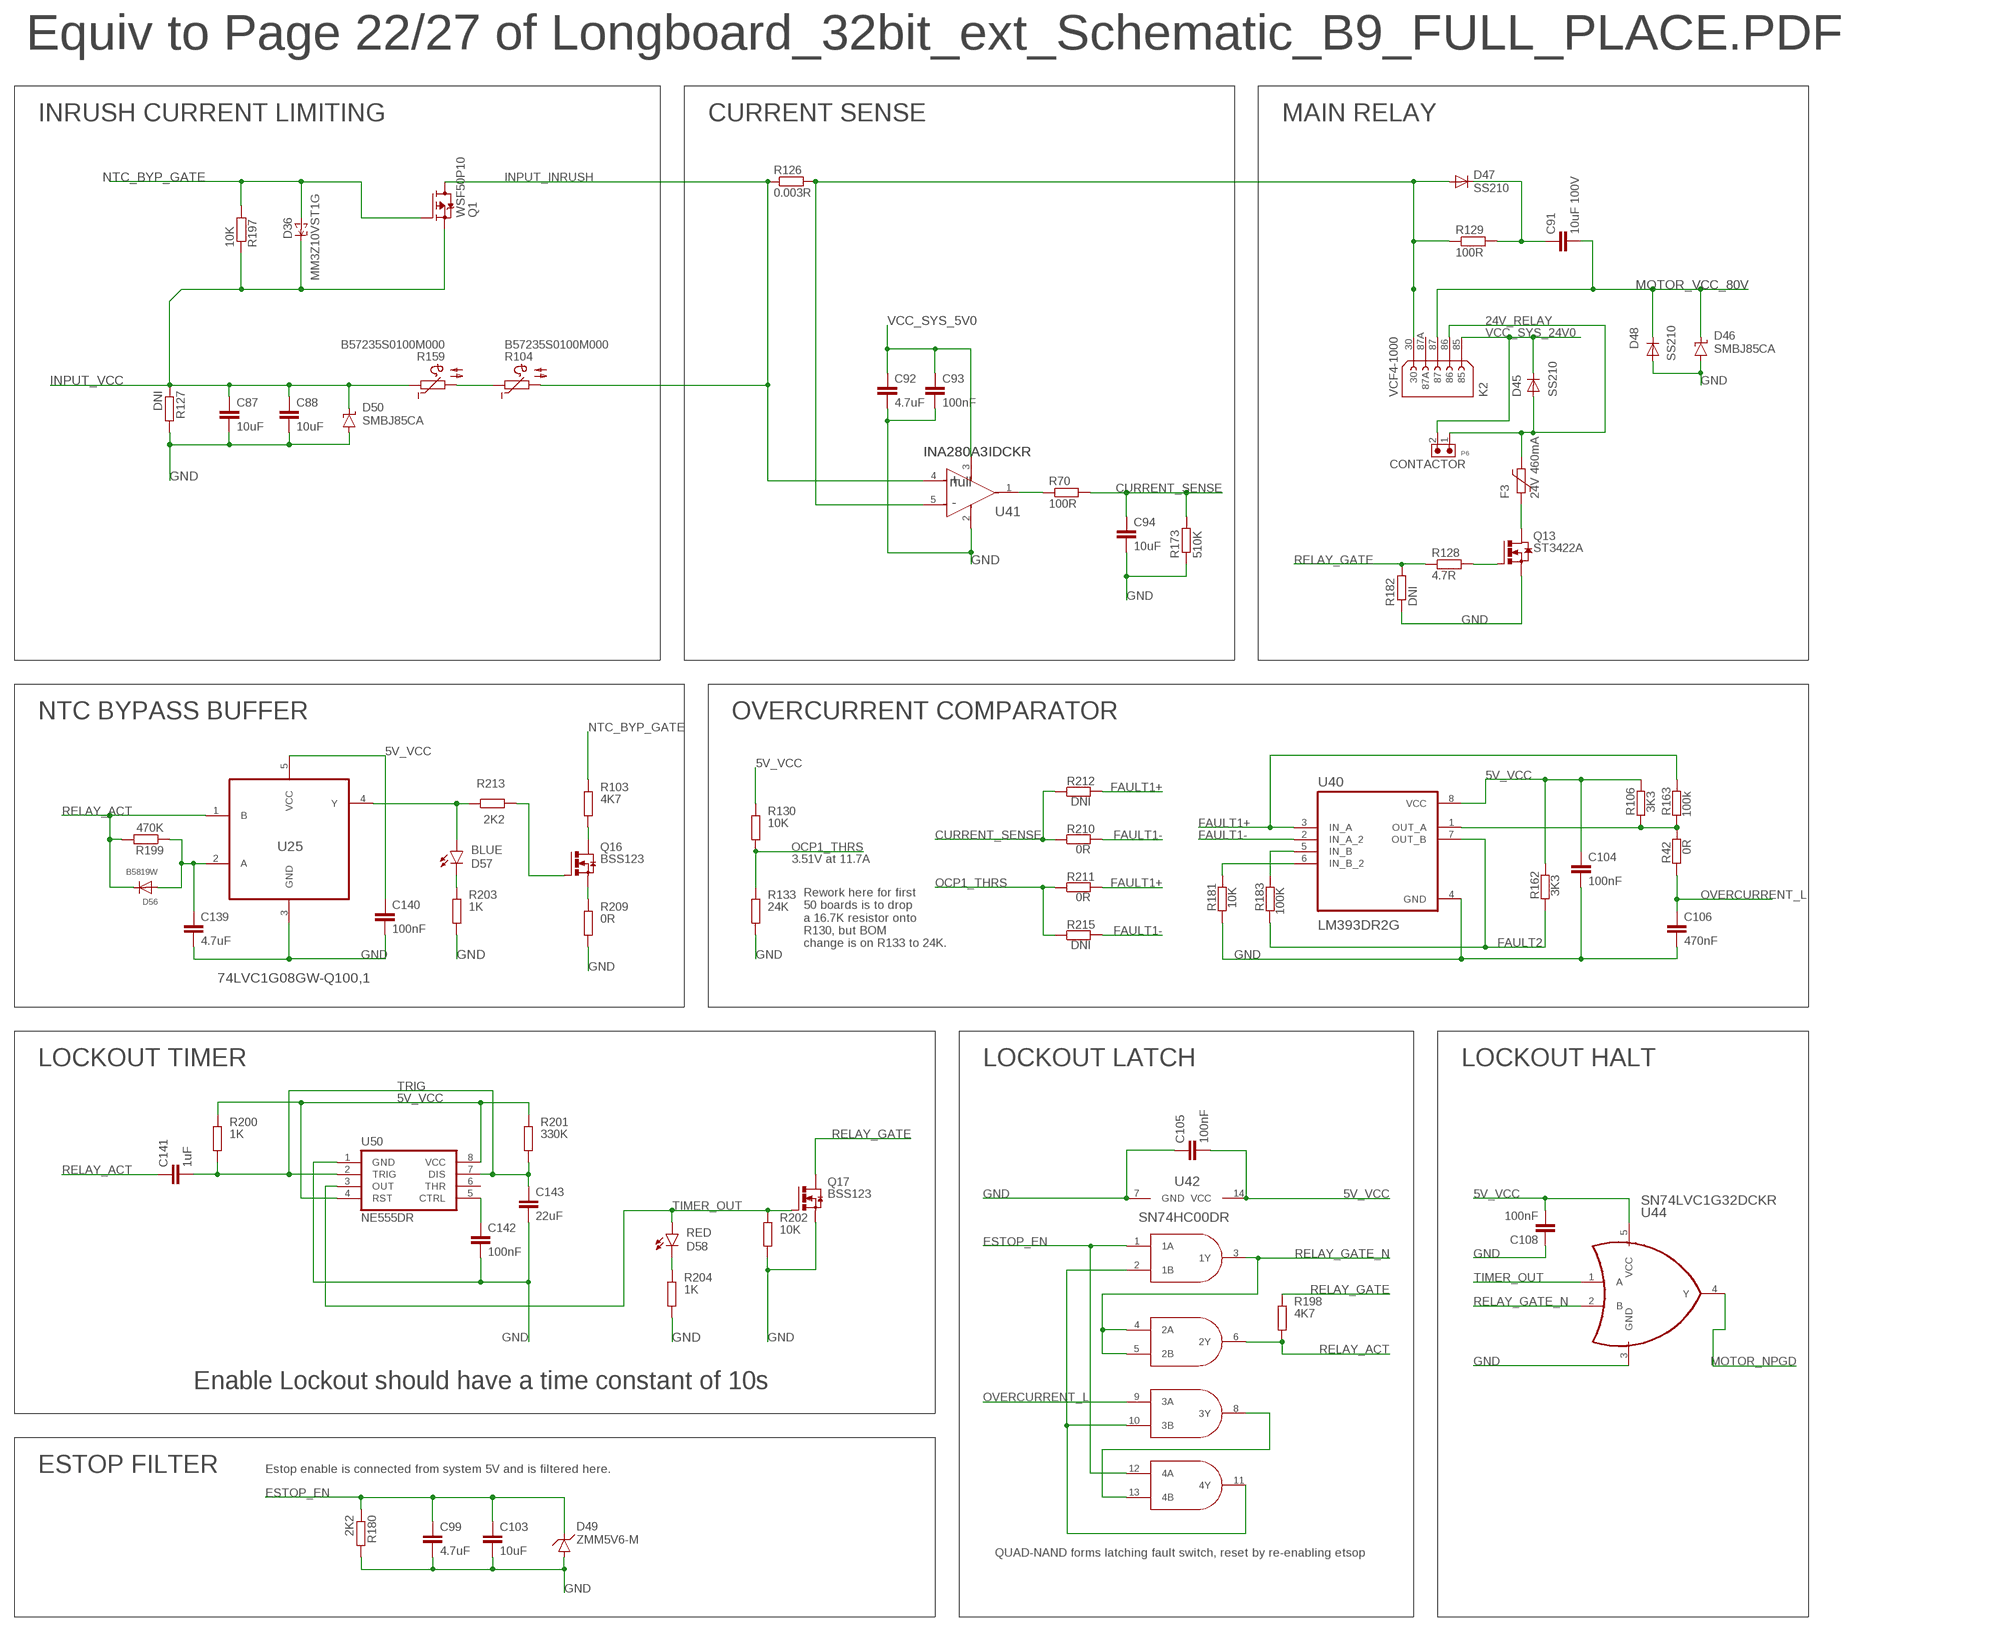
[diagram p11: schematic, sheet 10]
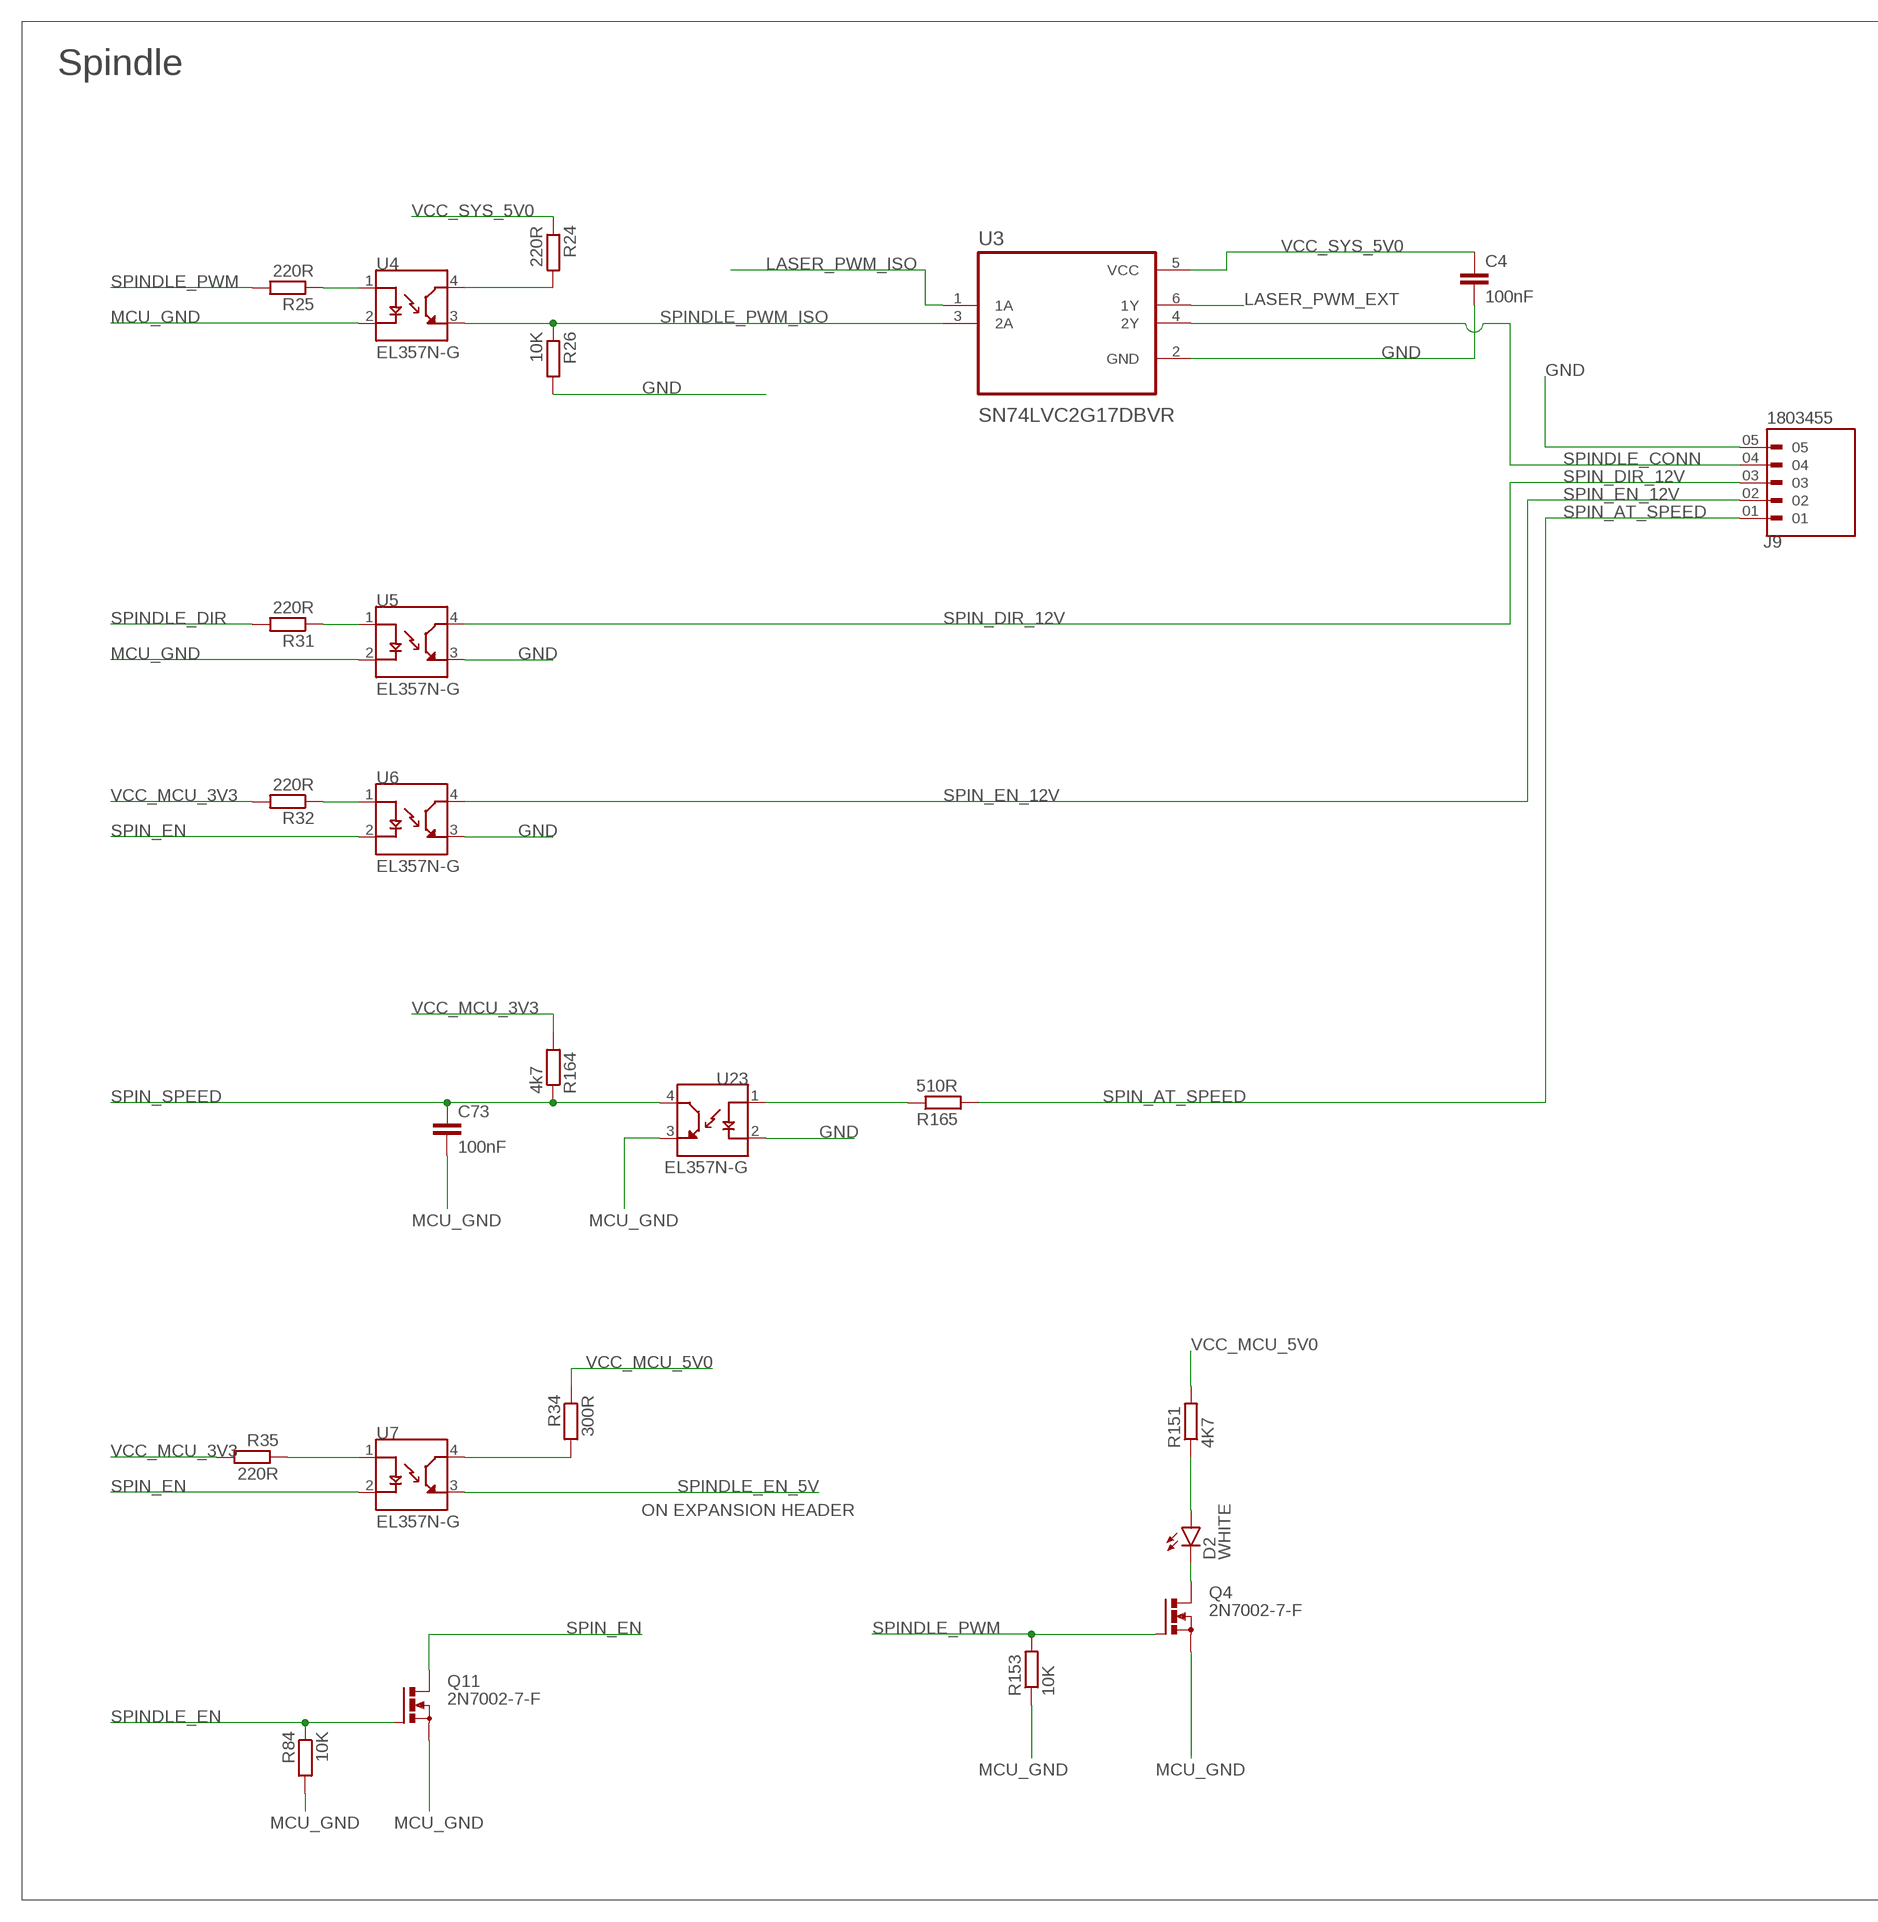
[diagram p12: schematic, sheet 11, part 1 of 2]
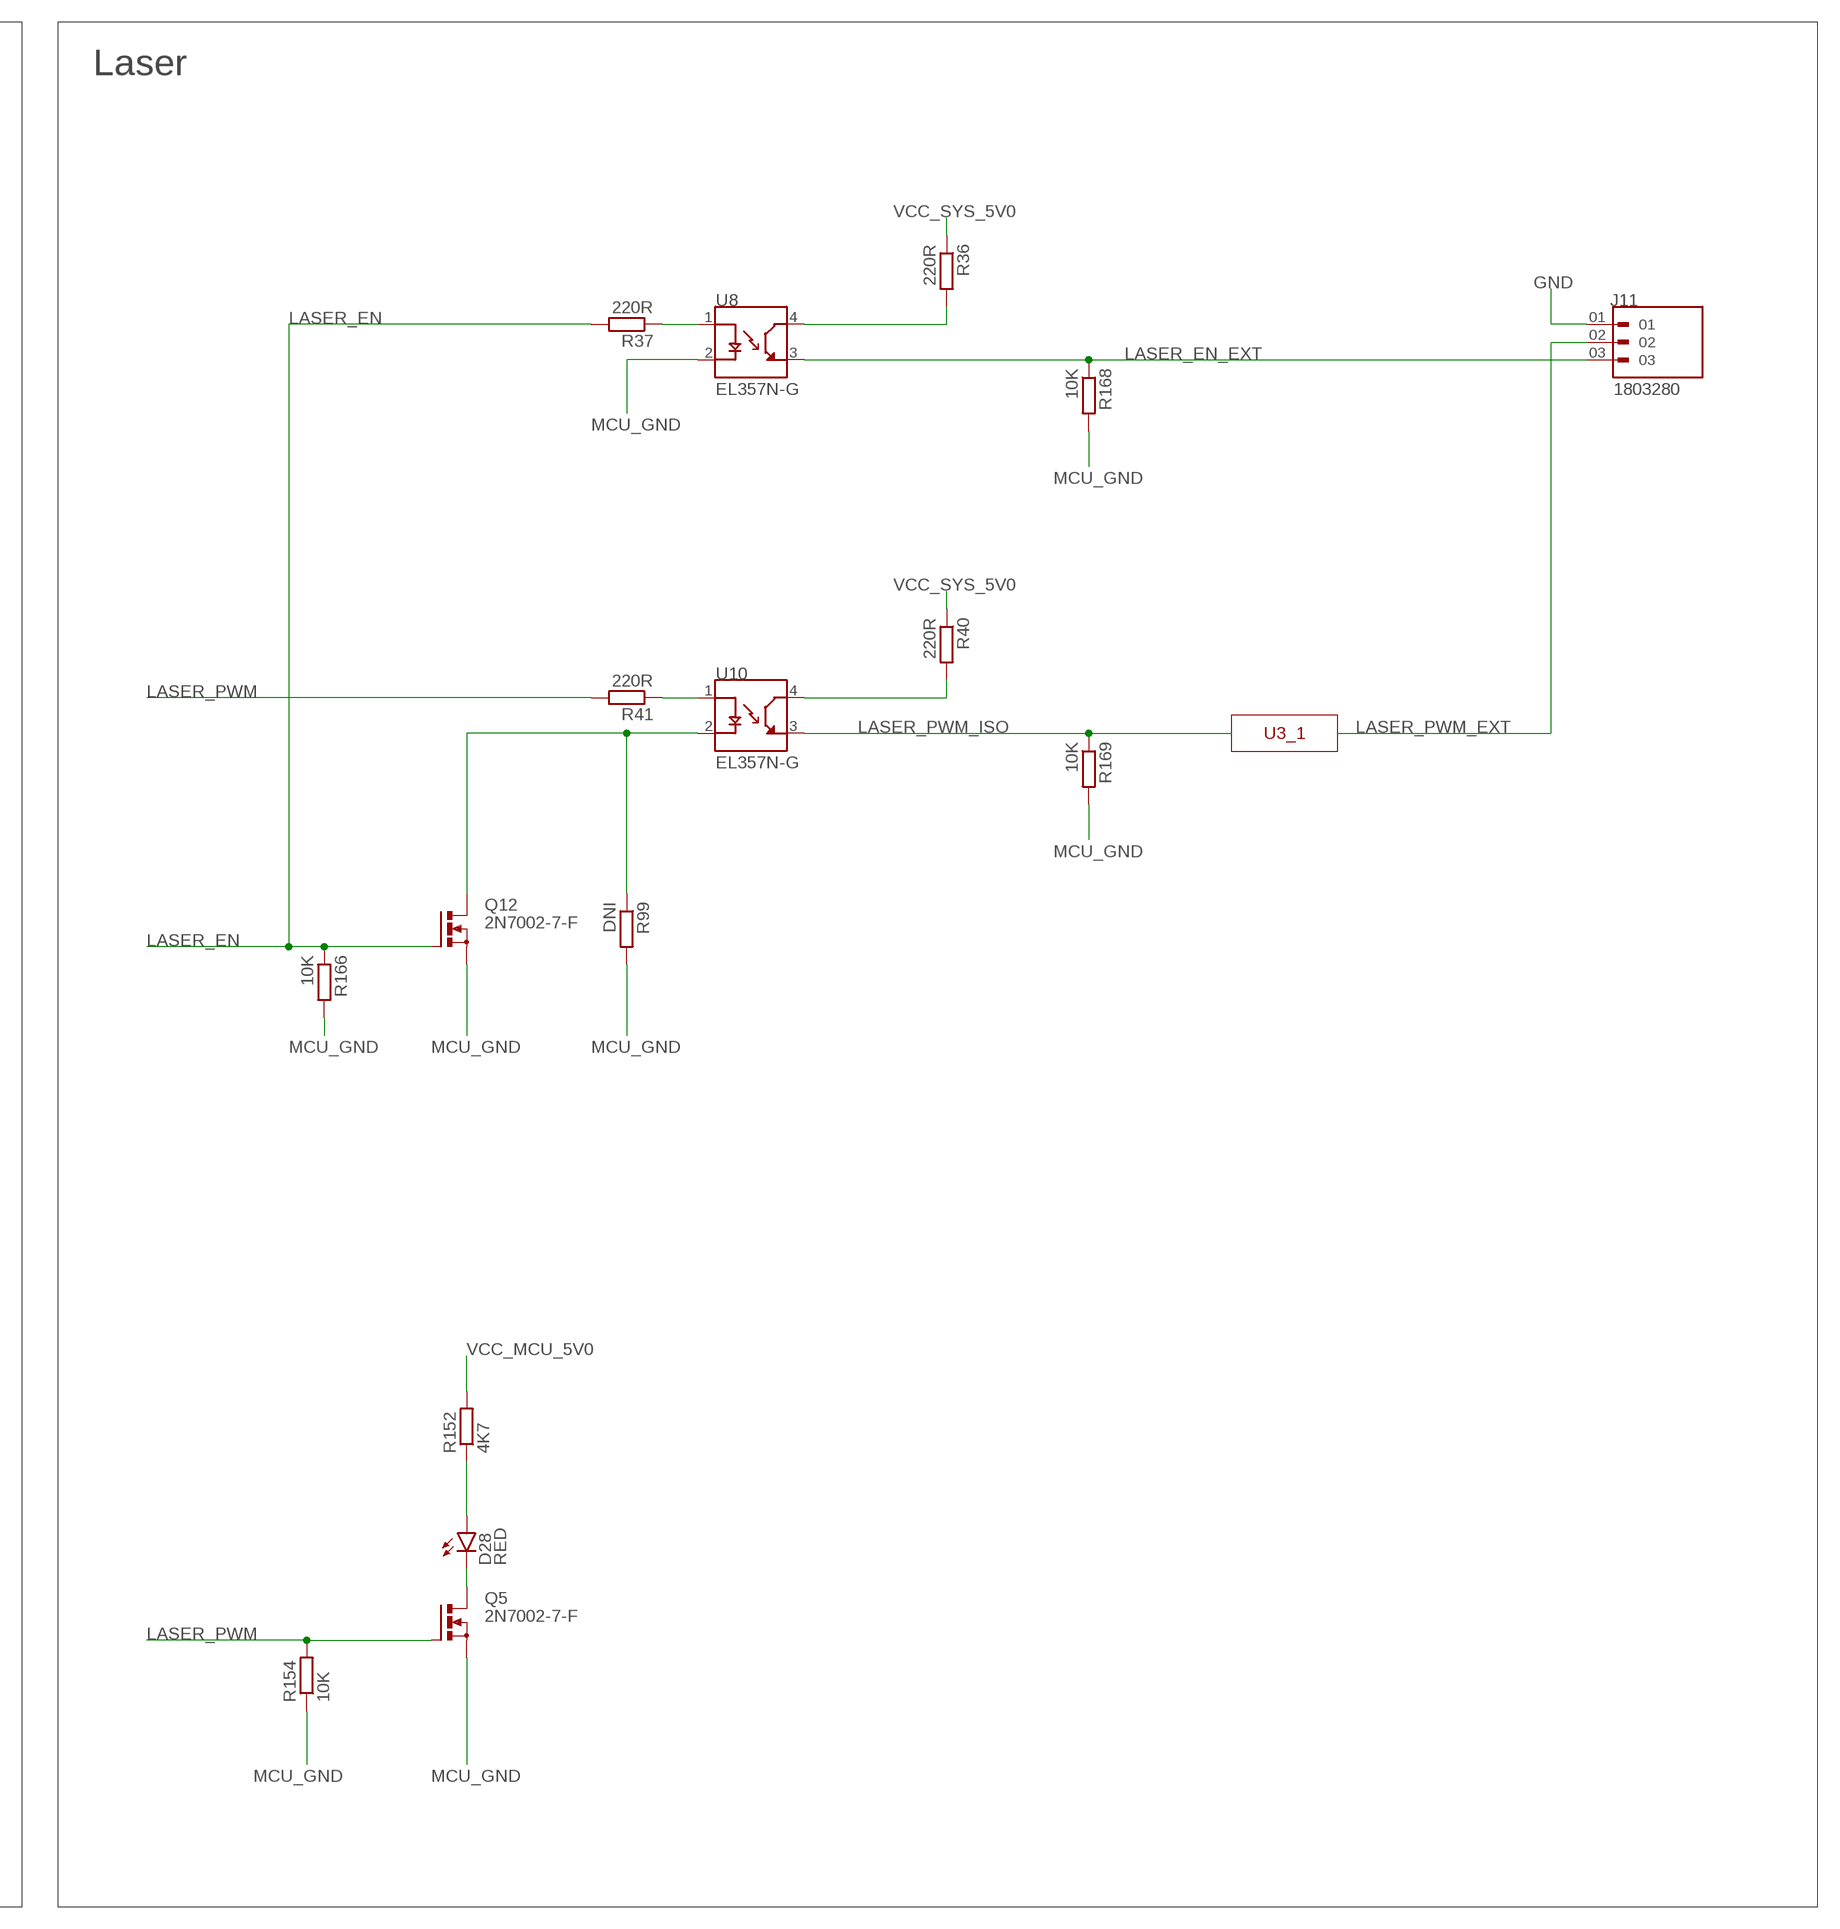
[diagram p13: schematic, sheet 11, part 2 of 2]
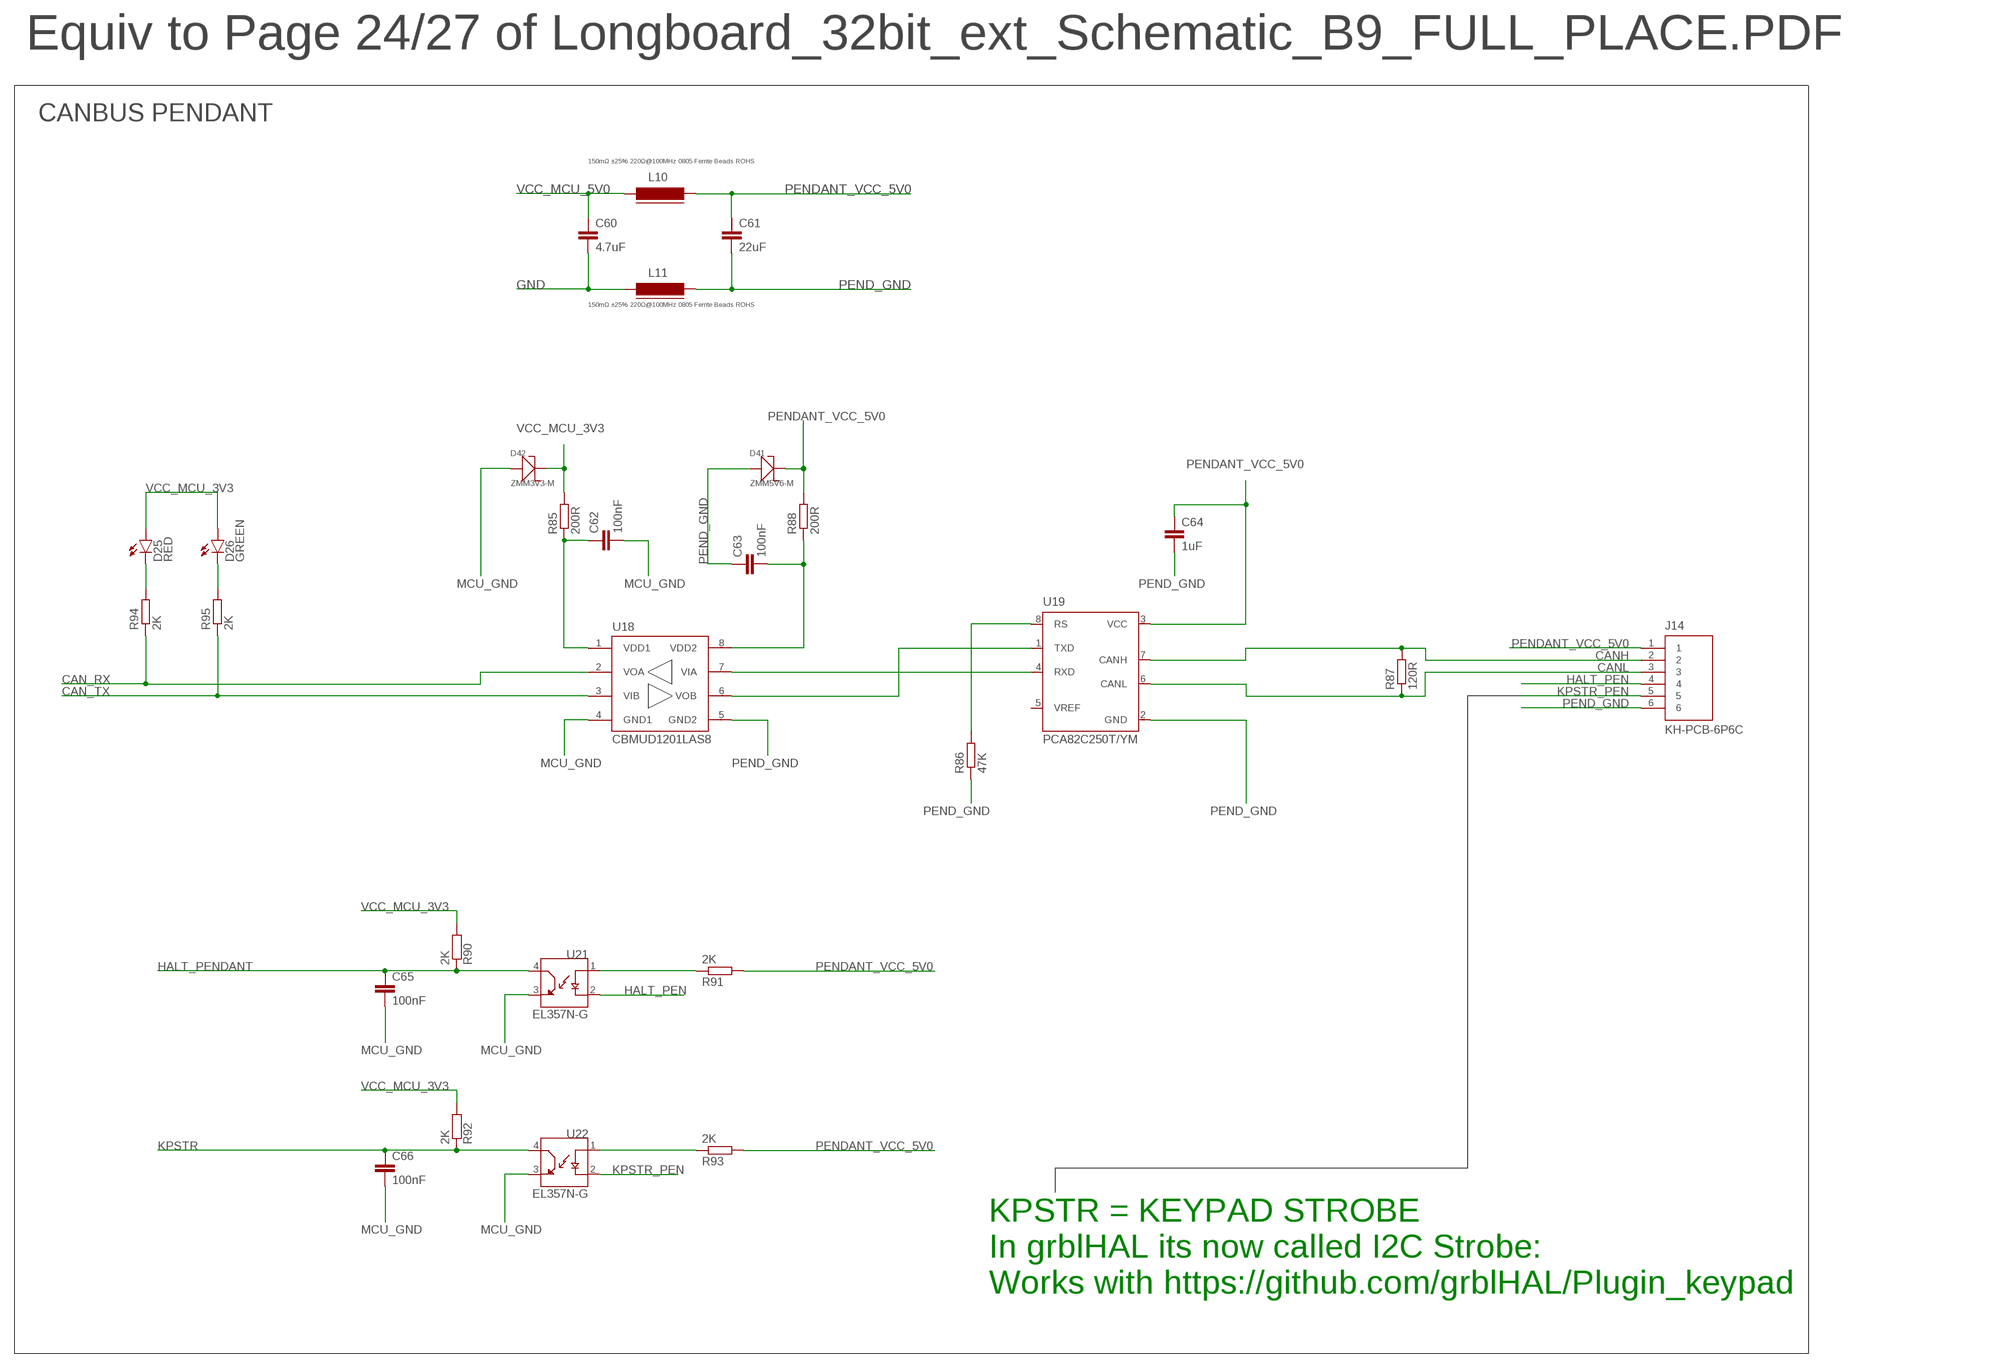
[diagram p14: schematic, sheet 12]
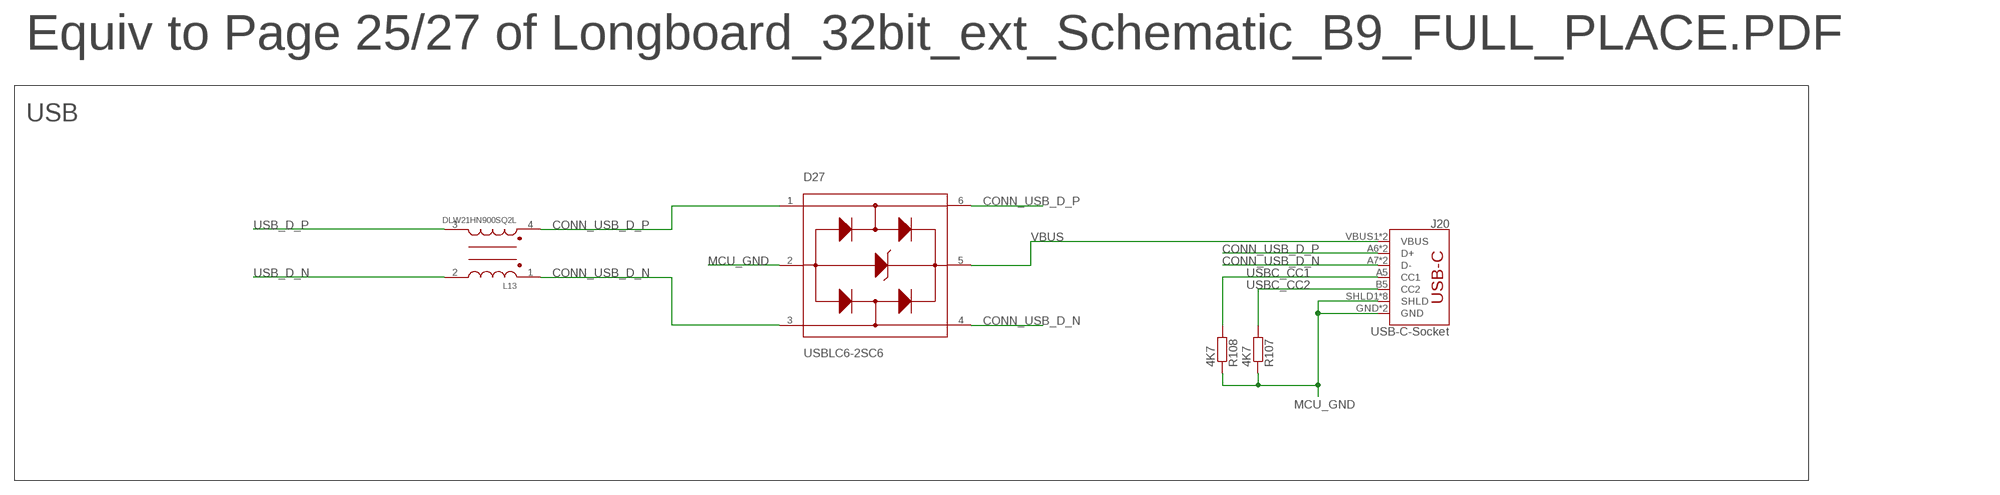
[diagram p15: schematic, sheet 13]
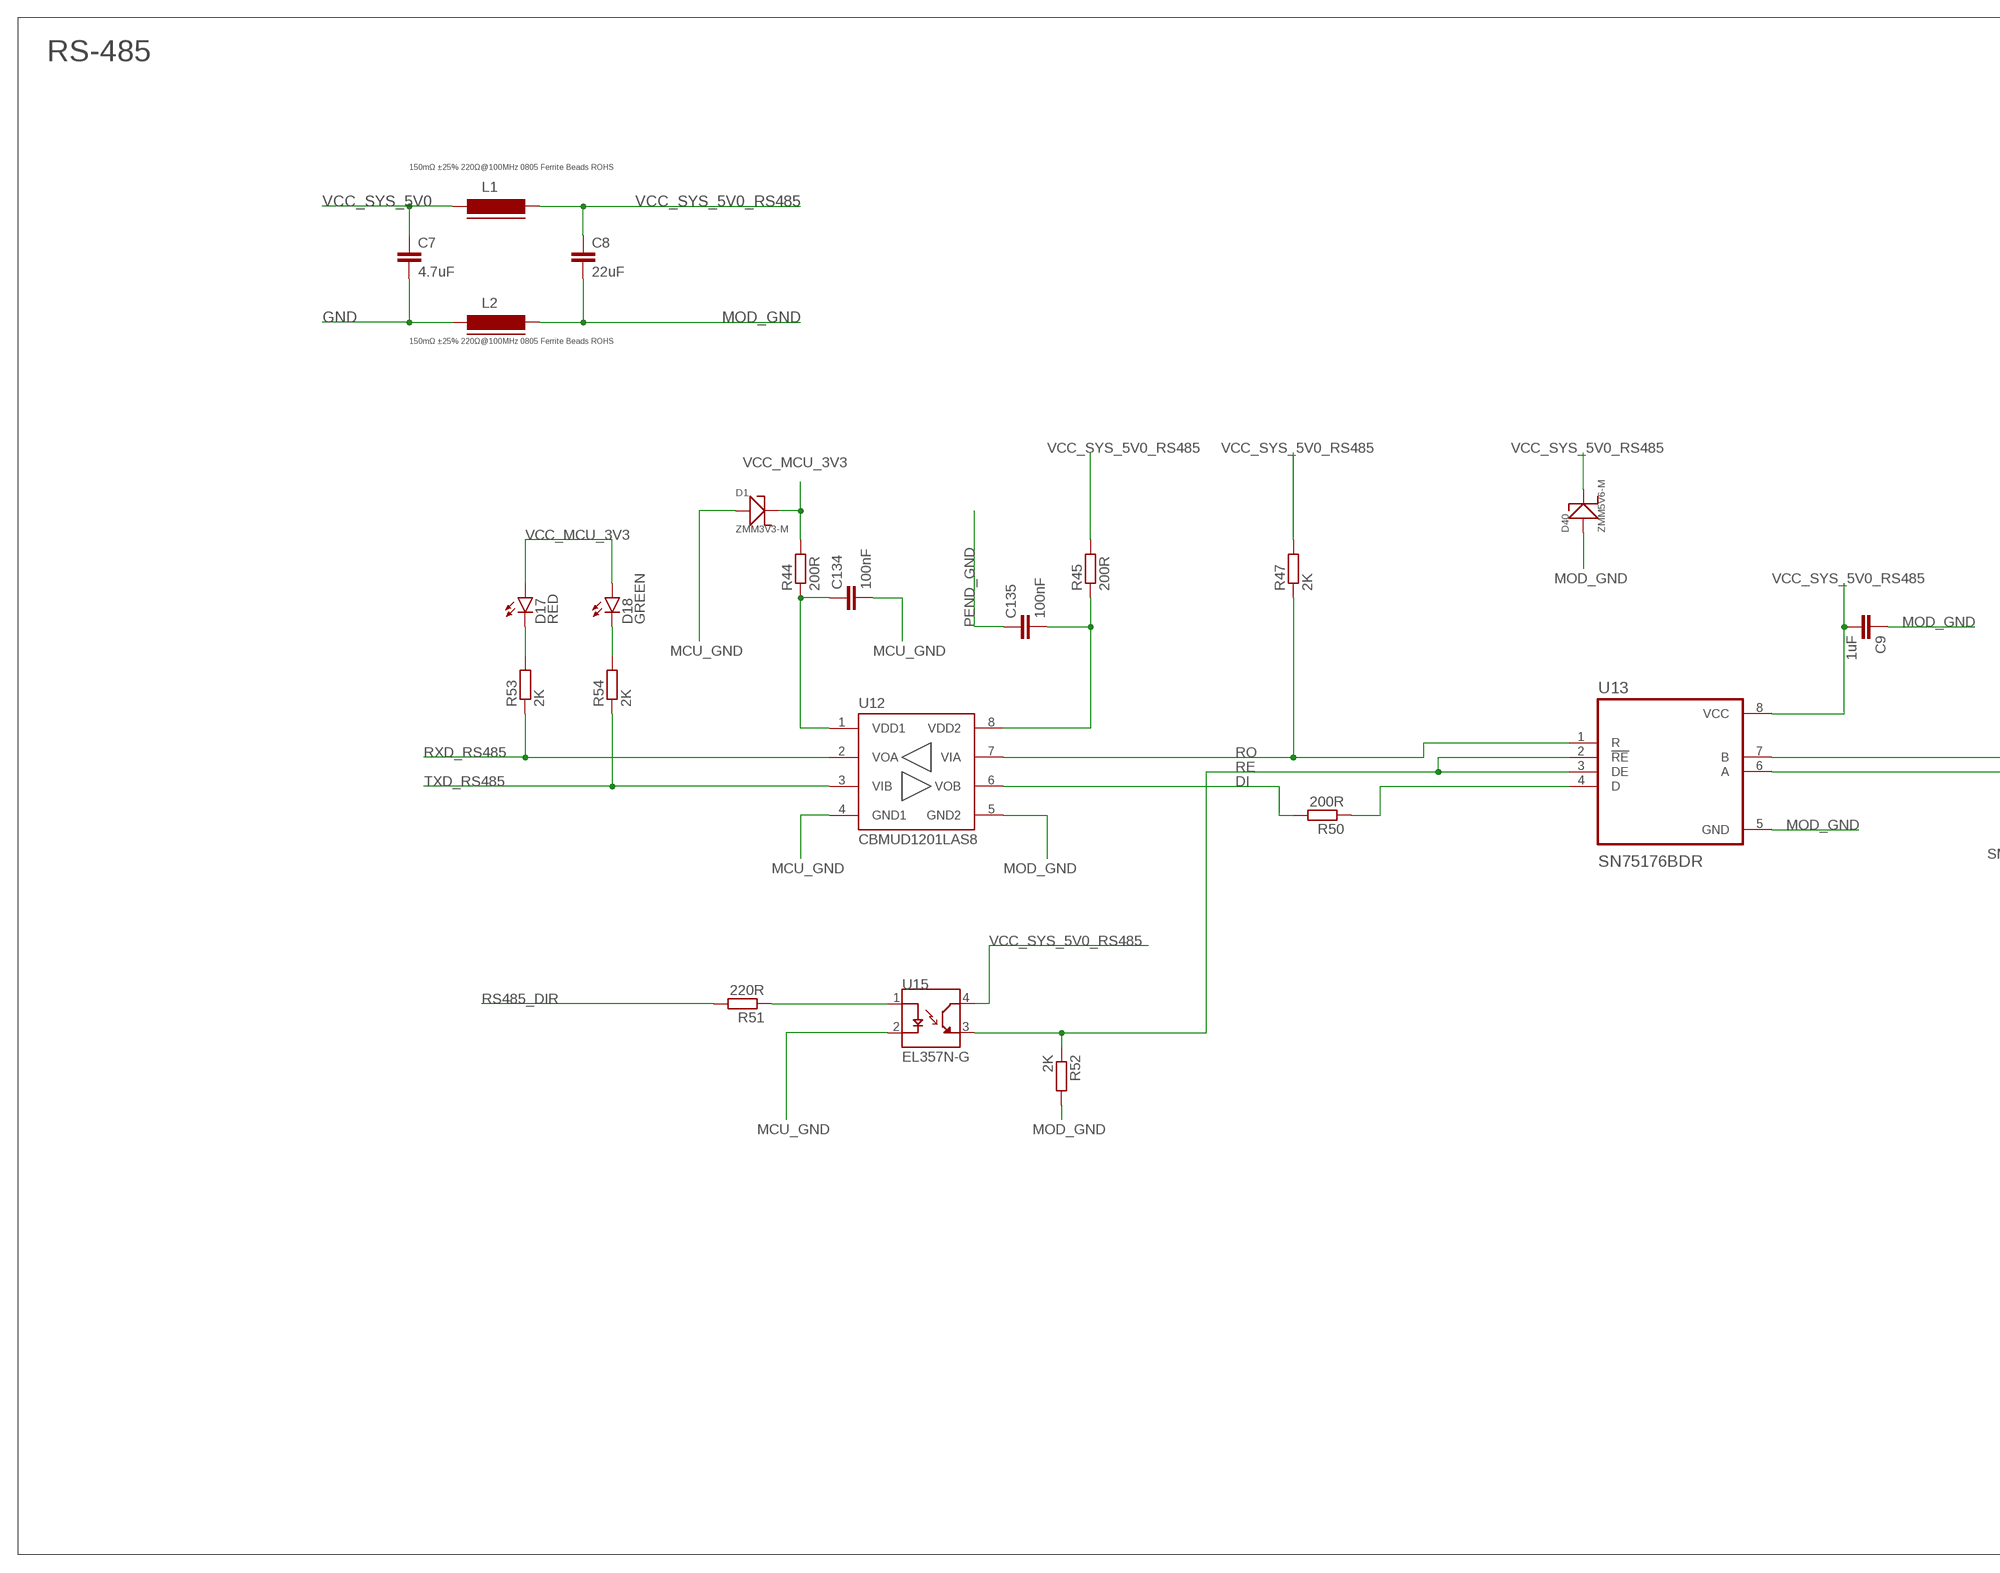
[diagram p16: schematic, sheet 14, part 1 of 2]
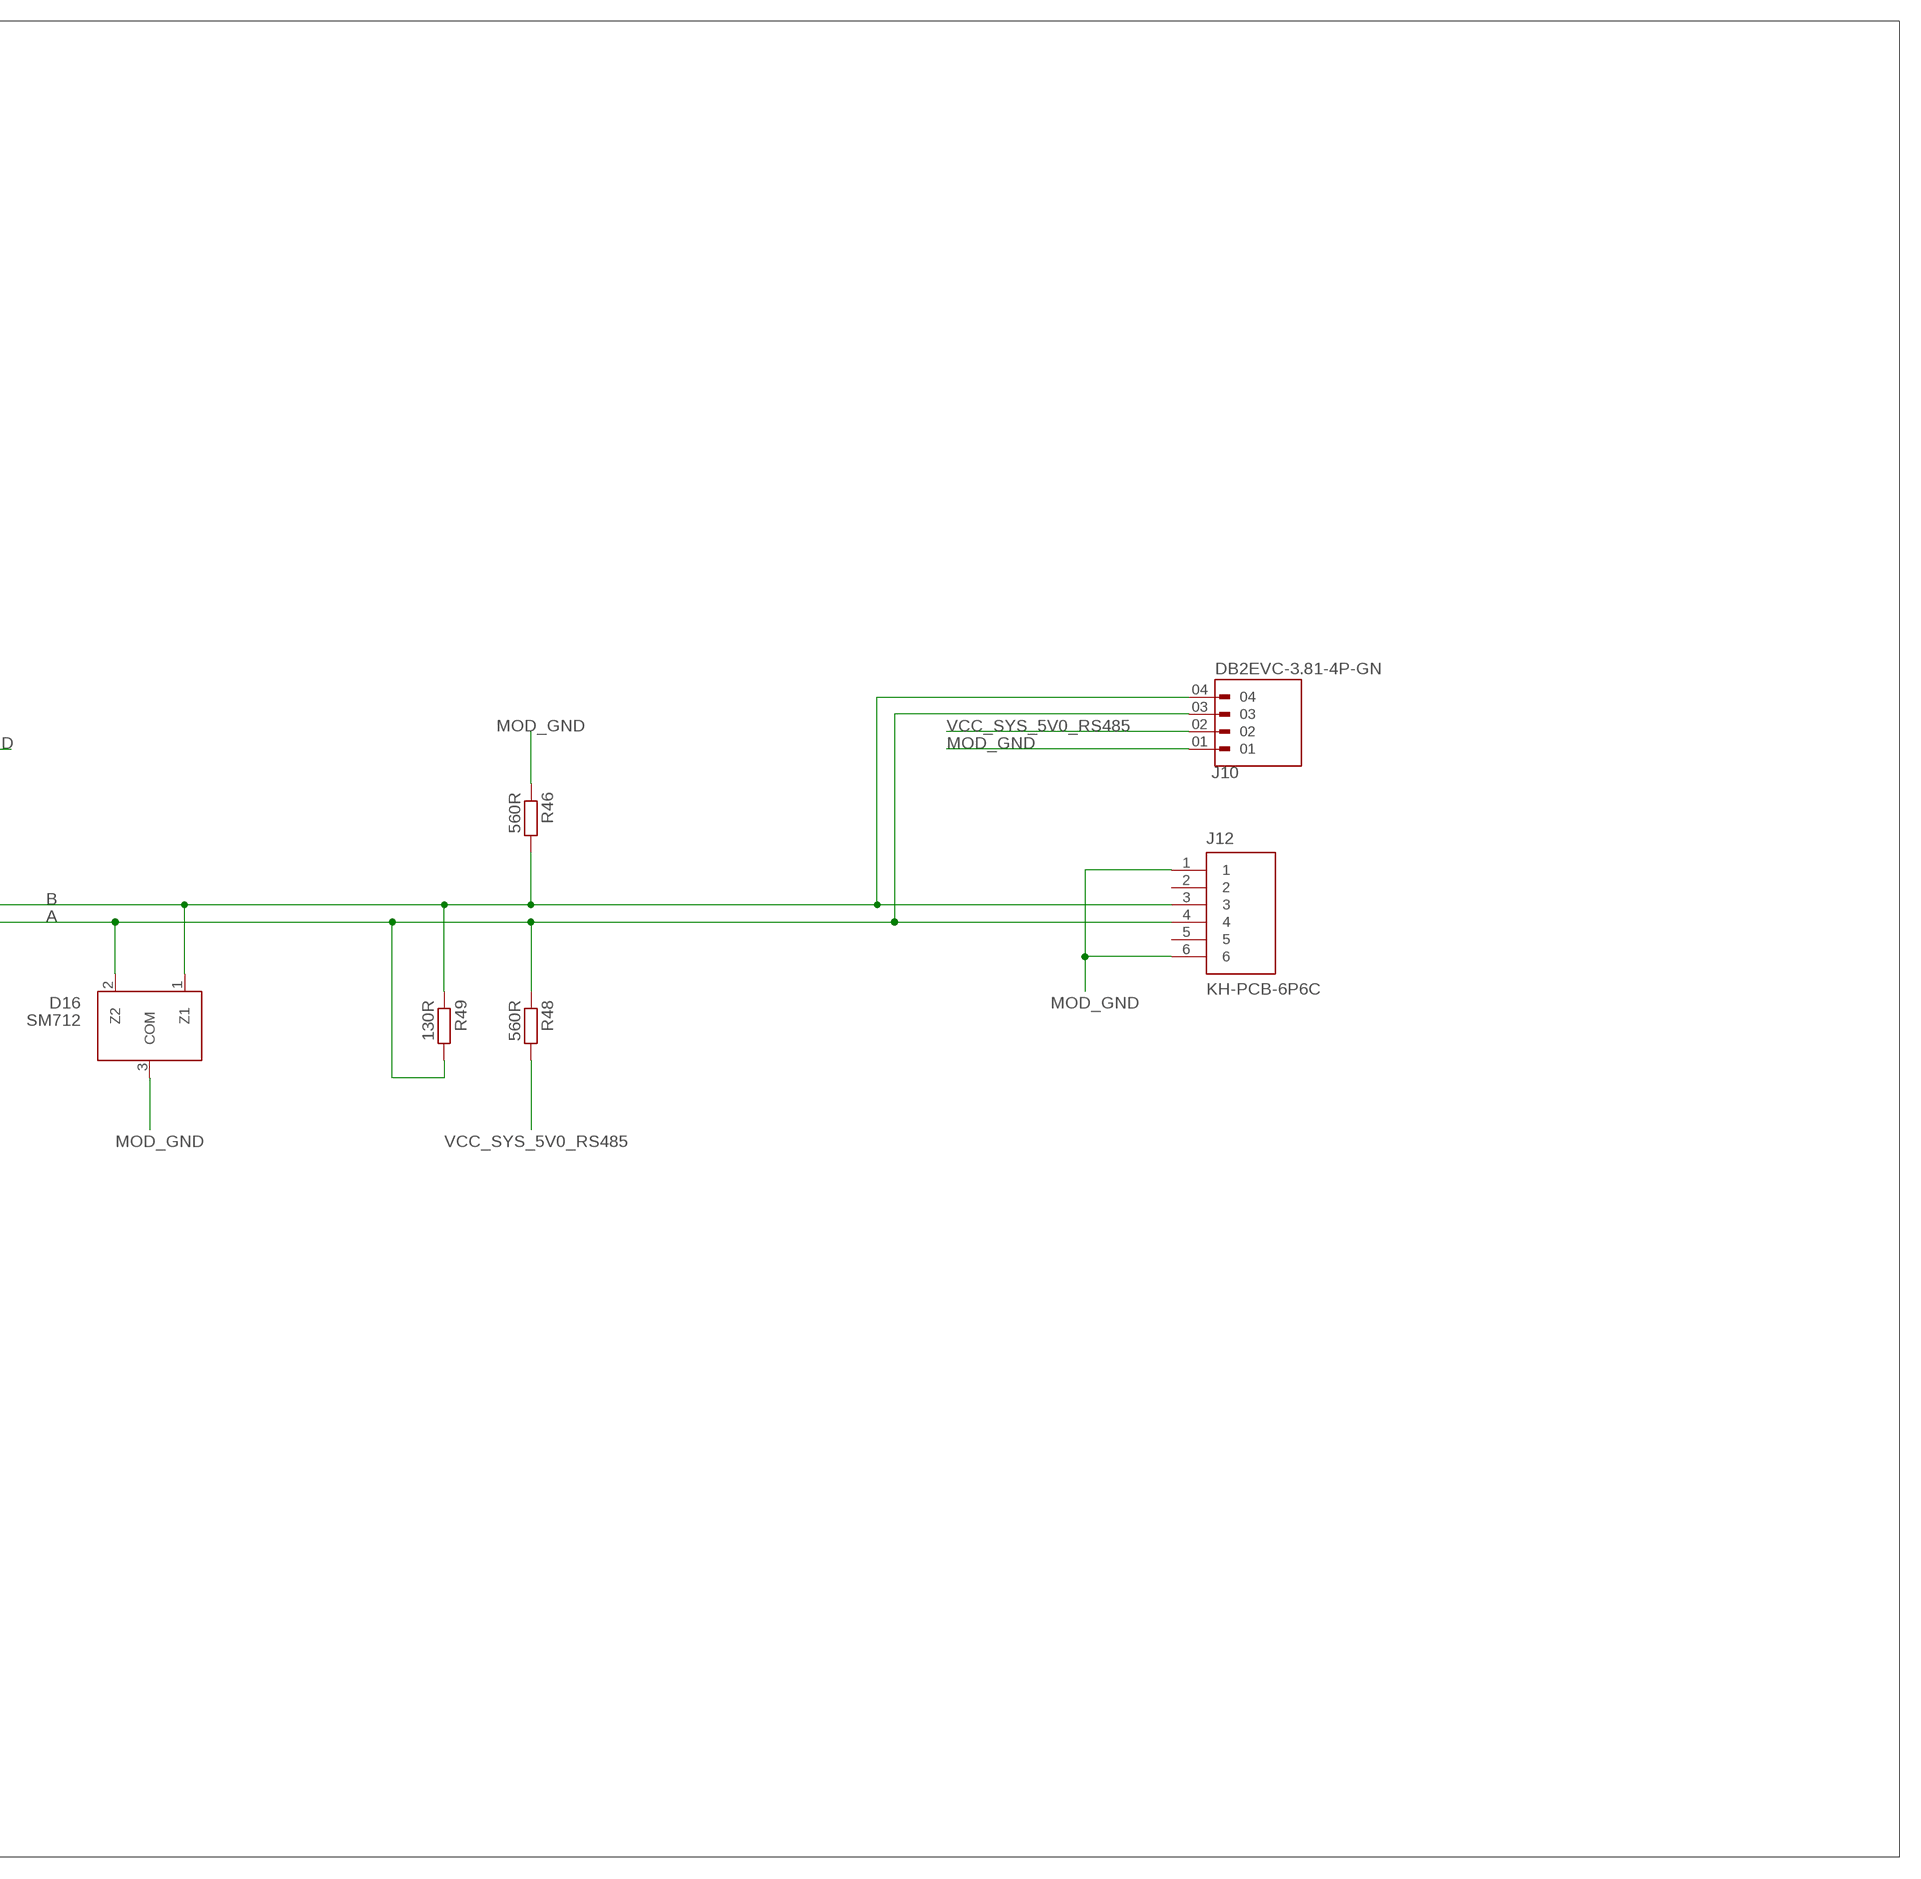
[diagram p17: schematic, sheet 14, part 2 of 2]

(export (version "E")
  (design (tool "Eeschema 10.0.6"))
  (components
    (comp (ref "C3_CY")
      (value "100nF")
      (footprint "eagle-import:C0603K")
      (libsource (lib "eagle-import") (part "C-EUC0603K"))
    )
    (comp (ref "C3_HL")
      (value "100nF")
      (footprint "eagle-import:C0402")
      (libsource (lib "eagle-import") (part "C-EUC0402"))
    )
    (comp (ref "C3_MC1")
      (value "100nF")
      (footprint "eagle-import:C0402")
      (libsource (lib "eagle-import") (part "C-EUC0402"))
    )
    (comp (ref "C3_MC2")
      (value "100nF")
      (footprint "eagle-import:C0402")
      (libsource (lib "eagle-import") (part "C-EUC0402"))
    )
    (comp (ref "D10")
      (value "YELLOW")
      (footprint "eagle-import:CHIP-LED0603")
      (libsource (lib "eagle-import") (part "LEDCHIP-LED0603"))
    )
    (comp (ref "D11")
      (value "YELLOW")
      (footprint "eagle-import:CHIP-LED0603")
      (libsource (lib "eagle-import") (part "LEDCHIP-LED0603"))
    )
    (comp (ref "D12")
      (value "YELLOW")
      (footprint "eagle-import:CHIP-LED0603")
      (libsource (lib "eagle-import") (part "LEDCHIP-LED0603"))
    )
    (comp (ref "D13")
      (value "RED")
      (footprint "eagle-import:CHIP-LED0603")
      (libsource (lib "eagle-import") (part "LEDCHIP-LED0603"))
    )
    (comp (ref "R18")
      (value "1K")
      (footprint "eagle-import:R0402")
      (libsource (lib "eagle-import") (part "R-EU_R0402"))
    )
    (comp (ref "R19")
      (value "1K")
      (footprint "eagle-import:R0402")
      (libsource (lib "eagle-import") (part "R-EU_R0402"))
    )
    (comp (ref "R20")
      (value "1K")
      (footprint "eagle-import:R0402")
      (libsource (lib "eagle-import") (part "R-EU_R0402"))
    )
    (comp (ref "R21")
      (value "1K")
      (footprint "eagle-import:R0402")
      (libsource (lib "eagle-import") (part "R-EU_R0402"))
    )
    (comp (ref "R22_CY")
      (value "4K7")
      (footprint "eagle-import:R0603")
      (libsource (lib "eagle-import") (part "R-EU_R0603"))
    )
    (comp (ref "R22_HL")
      (value "4K7")
      (footprint "eagle-import:R0402")
      (libsource (lib "eagle-import") (part "R-EU_R0402"))
    )
    (comp (ref "R22_MC1")
      (value "4K7")
      (footprint "eagle-import:R0402")
      (libsource (lib "eagle-import") (part "R-EU_R0402"))
    )
    (comp (ref "R22_MC2")
      (value "4K7")
      (footprint "eagle-import:R0402")
      (libsource (lib "eagle-import") (part "R-EU_R0402"))
    )
    (comp (ref "R23_CY")
      (value "1K")
      (footprint "eagle-import:R0603")
      (libsource (lib "eagle-import") (part "R-EU_R0603"))
    )
    (comp (ref "R23_HL")
      (value "1K")
      (footprint "eagle-import:R0603")
      (libsource (lib "eagle-import") (part "R-EU_R0603"))
    )
    (comp (ref "R23_MC1")
      (value "1K")
      (footprint "eagle-import:R0603")
      (libsource (lib "eagle-import") (part "R-EU_R0603"))
    )
    (comp (ref "R23_MC2")
      (value "1K")
      (footprint "eagle-import:R0603")
      (libsource (lib "eagle-import") (part "R-EU_R0603"))
    )
    (comp (ref "U2_CY")
      (value "EL357N-G")
      (footprint "eagle-import:OPTO_EL357N-G")
      (fields (field (name "MF") "Everlight Electronics"))
      (libsource (lib "eagle-import") (part "EL357N-G"))
    )
    (comp (ref "U2_HL")
      (value "EL357N-G")
      (footprint "eagle-import:OPTO_EL357N-G")
      (fields (field (name "MF") "Everlight Electronics"))
      (libsource (lib "eagle-import") (part "EL357N-G"))
    )
    (comp (ref "U2_MC1")
      (value "EL357N-G")
      (footprint "eagle-import:OPTO_EL357N-G")
      (fields (field (name "MF") "Everlight Electronics"))
      (libsource (lib "eagle-import") (part "EL357N-G"))
    )
    (comp (ref "U2_MC2")
      (value "EL357N-G")
      (footprint "eagle-import:OPTO_EL357N-G")
      (fields (field (name "MF") "Everlight Electronics"))
      (libsource (lib "eagle-import") (part "EL357N-G"))
    )
    (comp (ref "C87")
      (value "10uF")
      (footprint "eagle-import:C1206")
      (fields (field (name "LCSC_PART") "C576517"))
      (libsource (lib "eagle-import") (part "C-EUC1206"))
    )
    (comp (ref "C88")
      (value "10uF")
      (footprint "eagle-import:C1206")
      (fields (field (name "LCSC_PART") "C576517"))
      (libsource (lib "eagle-import") (part "C-EUC1206"))
    )
    (comp (ref "C91")
      (value "10uF 100V")
      (footprint "eagle-import:C1210")
      (fields (field (name "LCSC_PART") "C576517"))
      (libsource (lib "eagle-import") (part "C-EUC1210"))
    )
    (comp (ref "C92")
      (value "4.7uF")
      (footprint "eagle-import:C0603")
      (fields (field (name "LCSC_PART") "C576517"))
      (libsource (lib "eagle-import") (part "C-EUC0603"))
    )
    (comp (ref "C93")
      (value "100nF")
      (footprint "eagle-import:C0603")
      (fields (field (name "LCSC_PART") "C576517"))
      (libsource (lib "eagle-import") (part "C-EUC0603"))
    )
    (comp (ref "C94")
      (value "10uF")
      (footprint "eagle-import:C0603")
      (fields (field (name "LCSC_PART") "C576517"))
      (libsource (lib "eagle-import") (part "C-EUC0603"))
    )
    (comp (ref "C99")
      (value "4.7uF")
      (footprint "eagle-import:C0805")
      (fields (field (name "LCSC_PART") "C576517"))
      (libsource (lib "eagle-import") (part "C-EUC0805"))
    )
    (comp (ref "C103")
      (value "10uF")
      (footprint "eagle-import:C0805")
      (fields (field (name "LCSC_PART") "C576517"))
      (libsource (lib "eagle-import") (part "C-EUC0805"))
    )
    (comp (ref "C104")
      (value "100nF")
      (footprint "eagle-import:C0603")
      (fields (field (name "LCSC_PART") "C576517"))
      (libsource (lib "eagle-import") (part "C-EUC0603"))
    )
    (comp (ref "C105")
      (value "100nF")
      (footprint "eagle-import:C0603")
      (fields (field (name "LCSC_PART") "C576517"))
      (libsource (lib "eagle-import") (part "C-EUC0603"))
    )
    (comp (ref "C106")
      (value "470nF")
      (footprint "eagle-import:C0603")
      (fields (field (name "LCSC_PART") "C576517"))
      (libsource (lib "eagle-import") (part "C-EUC0603"))
    )
    (comp (ref "C108")
      (value "100nF")
      (footprint "eagle-import:C0603")
      (fields (field (name "LCSC_PART") "C576517"))
      (libsource (lib "eagle-import") (part "C-EUC0603"))
    )
    (comp (ref "C139")
      (value "4.7uF")
      (footprint "eagle-import:C1206")
      (fields (field (name "LCSC_PART") "C576517"))
      (libsource (lib "eagle-import") (part "C-EUC1206"))
    )
    (comp (ref "C140")
      (value "100nF")
      (footprint "eagle-import:C0603")
      (fields (field (name "LCSC_PART") "C576517"))
      (libsource (lib "eagle-import") (part "C-EUC0603"))
    )
    (comp (ref "C141")
      (value "1uF")
      (footprint "eagle-import:C0603")
      (fields (field (name "LCSC_PART") "C576517"))
      (libsource (lib "eagle-import") (part "C-EUC0603"))
    )
    (comp (ref "C142")
      (value "100nF")
      (footprint "eagle-import:C0603")
      (fields (field (name "LCSC_PART") "C576517"))
      (libsource (lib "eagle-import") (part "C-EUC0603"))
    )
    (comp (ref "C143")
      (value "22uF")
      (footprint "eagle-import:C1206")
      (fields (field (name "LCSC_PART") "C576517"))
      (libsource (lib "eagle-import") (part "C-EUC1206"))
    )
    (comp (ref "D36")
      (value "MM3Z10VST1G")
      (footprint "eagle-import:SOD-323F")
      (libsource (lib "eagle-import") (part "ZENERSOD-323F"))
    )
    (comp (ref "D45")
      (value "SS210")
      (footprint "eagle-import:DO-214AC")
      (fields (field (name "LCSC_PART") "C14996"))
      (libsource (lib "eagle-import") (part "dp_devices.v6_DIODE-DO-214AC"))
    )
    (comp (ref "D46")
      (value "SMBJ85CA")
      (footprint "eagle-import:SMBJ")
      (libsource (lib "eagle-import") (part "SUPPRESSOR-SMBJ"))
    )
    (comp (ref "D47")
      (value "SS210")
      (footprint "eagle-import:DO-214AC")
      (fields (field (name "LCSC_PART") "C14996"))
      (libsource (lib "eagle-import") (part "dp_devices.v6_DIODE-DO-214AC"))
    )
    (comp (ref "D48")
      (value "SS210")
      (footprint "eagle-import:DO-214AC")
      (fields (field (name "LCSC_PART") "C14996"))
      (libsource (lib "eagle-import") (part "dp_devices.v6_DIODE-DO-214AC"))
    )
    (comp (ref "D49")
      (value "ZMM5V6-M")
      (footprint "eagle-import:MINIMELF")
      (libsource (lib "eagle-import") (part "DIODE-MINIMELF"))
    )
    (comp (ref "D50")
      (value "SMBJ85CA")
      (footprint "eagle-import:SMBJ")
      (libsource (lib "eagle-import") (part "SUPPRESSOR-SMBJ"))
    )
    (comp (ref "D56")
      (value "B5819W")
      (footprint "eagle-import:SOD123FL")
      (fields (field (name "MF") "Microdiode Electronics"))
      (libsource (lib "eagle-import") (part "B5819W"))
    )
    (comp (ref "D57")
      (value "BLUE")
      (footprint "eagle-import:CHIP-LED0603")
      (libsource (lib "eagle-import") (part "LEDCHIP-LED0603"))
    )
    (comp (ref "D58")
      (value "RED")
      (footprint "eagle-import:CHIP-LED0603")
      (libsource (lib "eagle-import") (part "LEDCHIP-LED0603"))
    )
    (comp (ref "F3")
      (value "24V 460mA")
      (footprint "eagle-import:1206L")
      (fields (field (name "MF") "Littelfuse") (field (name "MPN") "1206L050"))
      (libsource (lib "eagle-import") (part "?1206L050"))
    )
    (comp (ref "K2")
      (value "VCF4-1000")
      (footprint "eagle-import:TE_VCF4-1000")
      (fields (field (name "COMMENT") "1393310-3") (field (name "MF") "TE Connectivity"))
      (libsource (lib "eagle-import") (part "VCF4-1000"))
    )
    (comp (ref "P6")
      (value "WJ15EDGK-3.81-2P")
      (footprint "eagle-import:DB2EVC-3.81-2P-GN")
      (fields (field (name "MF") "Würth Elektronik") (field (name "MP") "691321300002"))
      (libsource (lib "eagle-import") (part "DB2EVC-3.81-2P-GN"))
    )
    (comp (ref "Q1")
      (value "WSF50P10")
      (footprint "eagle-import:TO252")
      (libsource (lib "eagle-import") (part "FDD4141TO252"))
    )
    (comp (ref "Q13")
      (value "ST3422A")
      (footprint "eagle-import:SOT-23")
      (libsource (lib "eagle-import") (part "ST3422A"))
    )
    (comp (ref "Q16")
      (value "BSS123")
      (footprint "eagle-import:SOT95P240X110-3N")
      (fields (field (name "MF") "Diodes Inc.") (field (name "MP") "BSS123TA"))
      (libsource (lib "eagle-import") (part "BSS123TA"))
    )
    (comp (ref "Q17")
      (value "BSS123")
      (footprint "eagle-import:SOT95P240X110-3N")
      (fields (field (name "MF") "Diodes Inc.") (field (name "MP") "BSS123TA"))
      (libsource (lib "eagle-import") (part "BSS123TA"))
    )
    (comp (ref "R42")
      (value "0R")
      (footprint "eagle-import:R0603")
      (libsource (lib "eagle-import") (part "R-EU_R0603"))
    )
    (comp (ref "R70")
      (value "100R")
      (footprint "eagle-import:R0603")
      (libsource (lib "eagle-import") (part "R-EU_R0603"))
    )
    (comp (ref "R103")
      (value "4K7")
      (footprint "eagle-import:R0603")
      (libsource (lib "eagle-import") (part "R-EU_R0603"))
    )
    (comp (ref "R104")
      (value "B57235S0100M000")
      (footprint "eagle-import:B57164")
      (fields (field (name "MPN") "B57164K474K52"))
      (libsource (lib "eagle-import") (part "B57164"))
    )
    (comp (ref "R106")
      (value "3K3")
      (footprint "eagle-import:R0603")
      (libsource (lib "eagle-import") (part "R-EU_R0603"))
    )
    (comp (ref "R126")
      (value "0.003R")
      (footprint "eagle-import:R1206")
      (libsource (lib "eagle-import") (part "R-EU_R1206"))
    )
    (comp (ref "R127")
      (value "DNI")
      (footprint "eagle-import:R0603")
      (libsource (lib "eagle-import") (part "R-EU_R0603"))
    )
    (comp (ref "R128")
      (value "4.7R")
      (footprint "eagle-import:R0603")
      (libsource (lib "eagle-import") (part "R-EU_R0603"))
    )
    (comp (ref "R129")
      (value "100R")
      (footprint "eagle-import:R1206")
      (libsource (lib "eagle-import") (part "R-EU_R1206"))
    )
    (comp (ref "R130")
      (value "10K")
      (footprint "eagle-import:R0603")
      (libsource (lib "eagle-import") (part "R-EU_R0603"))
    )
    (comp (ref "R133")
      (value "24K")
      (footprint "eagle-import:R0603")
      (libsource (lib "eagle-import") (part "R-EU_R0603"))
    )
    (comp (ref "R159")
      (value "B57235S0100M000")
      (footprint "eagle-import:B57164")
      (fields (field (name "MPN") "B57164K474K52"))
      (libsource (lib "eagle-import") (part "B57164"))
    )
    (comp (ref "R162")
      (value "3K3")
      (footprint "eagle-import:R0603")
      (libsource (lib "eagle-import") (part "R-EU_R0603"))
    )
    (comp (ref "R163")
      (value "100k")
      (footprint "eagle-import:R0603")
      (libsource (lib "eagle-import") (part "R-EU_R0603"))
    )
    (comp (ref "R173")
      (value "510K")
      (footprint "eagle-import:R0603")
      (libsource (lib "eagle-import") (part "R-EU_R0603"))
    )
    (comp (ref "R180")
      (value "2K2")
      (footprint "eagle-import:R0603")
      (libsource (lib "eagle-import") (part "R-EU_R0603"))
    )
    (comp (ref "R181")
      (value "10K")
      (footprint "eagle-import:R0603")
      (libsource (lib "eagle-import") (part "R-EU_R0603"))
    )
    (comp (ref "R182")
      (value "DNI")
      (footprint "eagle-import:R1206")
      (libsource (lib "eagle-import") (part "R-EU_R1206"))
    )
    (comp (ref "R183")
      (value "100K")
      (footprint "eagle-import:R0603")
      (libsource (lib "eagle-import") (part "R-EU_R0603"))
    )
    (comp (ref "R197")
      (value "10K")
      (footprint "eagle-import:R0603")
      (libsource (lib "eagle-import") (part "R-EU_R0603"))
    )
    (comp (ref "R198")
      (value "4K7")
      (footprint "eagle-import:R0603")
      (libsource (lib "eagle-import") (part "R-EU_R0603"))
    )
    (comp (ref "R199")
      (value "470K")
      (footprint "eagle-import:R0603")
      (libsource (lib "eagle-import") (part "R-EU_R0603"))
    )
    (comp (ref "R200")
      (value "1K")
      (footprint "eagle-import:R0603")
      (libsource (lib "eagle-import") (part "R-EU_R0603"))
    )
    (comp (ref "R201")
      (value "330K")
      (footprint "eagle-import:R0603")
      (libsource (lib "eagle-import") (part "R-EU_R0603"))
    )
    (comp (ref "R202")
      (value "10K")
      (footprint "eagle-import:R0603")
      (libsource (lib "eagle-import") (part "R-EU_R0603"))
    )
    (comp (ref "R203")
      (value "1K")
      (footprint "eagle-import:R0603")
      (libsource (lib "eagle-import") (part "R-EU_R0603"))
    )
    (comp (ref "R204")
      (value "1K")
      (footprint "eagle-import:R0603")
      (libsource (lib "eagle-import") (part "R-EU_R0603"))
    )
    (comp (ref "R209")
      (value "0R")
      (footprint "eagle-import:R0603")
      (libsource (lib "eagle-import") (part "R-EU_R0603"))
    )
    (comp (ref "R210")
      (value "0R")
      (footprint "eagle-import:R0603")
      (libsource (lib "eagle-import") (part "R-EU_R0603"))
    )
    (comp (ref "R211")
      (value "0R")
      (footprint "eagle-import:R0603")
      (libsource (lib "eagle-import") (part "R-EU_R0603"))
    )
    (comp (ref "R212")
      (value "DNI")
      (footprint "eagle-import:R0603")
      (libsource (lib "eagle-import") (part "R-EU_R0603"))
    )
    (comp (ref "R213")
      (value "2K2")
      (footprint "eagle-import:R0603")
      (libsource (lib "eagle-import") (part "R-EU_R0603"))
    )
    (comp (ref "R215")
      (value "DNI")
      (footprint "eagle-import:R0603")
      (libsource (lib "eagle-import") (part "R-EU_R0603"))
    )
    (comp (ref "U25")
      (value "74LVC1G08GW-Q100,1")
      (footprint "eagle-import:SOT65P210X110-5N")
      (fields (field (name "MF") "Nexperia USA"))
      (libsource (lib "eagle-import") (part "74LVC1G08GW-Q100,1"))
    )
    (comp (ref "U40")
      (value "LM393DR2G")
      (footprint "eagle-import:SOIC127P600X265-8N")
      (fields (field (name "MF") "ON Semiconductor"))
      (libsource (lib "eagle-import") (part "LM393DR2G"))
    )
    (comp (ref "U41")
      (value "INA280A3IDCKR")
      (footprint "eagle-import:DCK0005A-IPC_A")
      (fields (field (name "COPYRIGHT") "Copyright (C) 2025 Ultra Librarian. All rights reserved."))
      (libsource (lib "eagle-import") (part "INA280A3IDCKR"))
    )
    (comp (ref "U42")
      (value "SN74HC00DR")
      (footprint "eagle-import:SOIC127P600X175-14N")
      (fields (field (name "MF") "Texas Instruments"))
      (libsource (lib "eagle-import") (part "SN74HC00DR"))
    )
    (comp (ref "U44")
      (value "SN74LVC1G32DCKR")
      (footprint "eagle-import:SOT65P210X110-5N")
      (fields (field (name "MF") "Texas Instruments") (field (name "MP") "SN74LVC1G32DCKRE4"))
      (libsource (lib "eagle-import") (part "SN74LVC1G32DCKRE4"))
    )
    (comp (ref "U50")
      (value "NE555DR")
      (footprint "eagle-import:SOIC-8")
      (libsource (lib "eagle-import") (part "IC_555-SOIC8"))
    )
    (comp (ref "C1")
      (value "100nF")
      (footprint "eagle-import:C0402")
      (libsource (lib "eagle-import") (part "C-EUC0402"))
    )
    (comp (ref "C2")
      (value "100nF")
      (footprint "eagle-import:C0402")
      (libsource (lib "eagle-import") (part "C-EUC0402"))
    )
    (comp (ref "R8")
      (value "10K")
      (footprint "eagle-import:R0402")
      (libsource (lib "eagle-import") (part "R-EU_R0402"))
    )
    (comp (ref "U1")
      (value "SN74AHC1G86DBVR")
      (footprint "eagle-import:SOT95P280X145-5N")
      (fields (field (name "MF") "Texas Instruments"))
      (libsource (lib "eagle-import") (part "SN74AHC1G86DBVR"))
    )
    (comp (ref "C60")
      (value "4.7uF")
      (footprint "eagle-import:C0603")
      (libsource (lib "eagle-import") (part "C-EUC0603"))
    )
    (comp (ref "C61")
      (value "22uF")
      (footprint "eagle-import:C0603")
      (fields (field (name "LCSC_PART") "C576517"))
      (libsource (lib "eagle-import") (part "C-EUC0603"))
    )
    (comp (ref "C62")
      (value "100nF")
      (footprint "eagle-import:C0603")
      (fields (field (name "LCSC_PART") "C576517"))
      (libsource (lib "eagle-import") (part "C-EUC0603"))
    )
    (comp (ref "C63")
      (value "100nF")
      (footprint "eagle-import:C0603")
      (fields (field (name "LCSC_PART") "C576517"))
      (libsource (lib "eagle-import") (part "C-EUC0603"))
    )
    (comp (ref "C64")
      (value "1uF")
      (footprint "eagle-import:C0603")
      (fields (field (name "LCSC_PART") "C576517"))
      (libsource (lib "eagle-import") (part "C-EUC0603"))
    )
    (comp (ref "C65")
      (value "100nF")
      (footprint "eagle-import:C0603")
      (fields (field (name "LCSC_PART") "C576517"))
      (libsource (lib "eagle-import") (part "C-EUC0603"))
    )
    (comp (ref "C66")
      (value "100nF")
      (footprint "eagle-import:C0603")
      (fields (field (name "LCSC_PART") "C576517"))
      (libsource (lib "eagle-import") (part "C-EUC0603"))
    )
    (comp (ref "D25")
      (value "RED")
      (footprint "eagle-import:CHIP-LED0603")
      (libsource (lib "eagle-import") (part "LEDCHIP-LED0603"))
    )
    (comp (ref "D26")
      (value "GREEN")
      (footprint "eagle-import:CHIP-LED0603")
      (libsource (lib "eagle-import") (part "LEDCHIP-LED0603"))
    )
    (comp (ref "D41")
      (value "ZMM5V6-M")
      (footprint "eagle-import:LL-34")
      (fields (field (name "MF") "STMicroelectronics") (field (name "MP") "LL4148ST"))
      (libsource (lib "eagle-import") (part "ZMM3V3-M"))
    )
    (comp (ref "D42")
      (value "ZMM3V3-M")
      (footprint "eagle-import:LL-34")
      (fields (field (name "MF") "STMicroelectronics") (field (name "MP") "LL4148ST"))
      (libsource (lib "eagle-import") (part "ZMM3V3-M"))
    )
    (comp (ref "J14")
      (value "KH-PCB-6P6C")
      (footprint "eagle-import:KH-PCB-6P6C")
      (fields (field (name "MF") "Same Sky") (field (name "MP") "CRJ030-G-TH"))
      (libsource (lib "eagle-import") (part "KH-PCB-6P6C"))
    )
    (comp (ref "L10")
      (value "150mΩ ±25% 220Ω@100MHz 0805 Ferrite Beads ROHS")
      (footprint "eagle-import:FB805")
      (fields (field (name "LCSC_PART") "C139188"))
      (libsource (lib "eagle-import") (part "FERRITE-0805"))
    )
    (comp (ref "L11")
      (value "150mΩ ±25% 220Ω@100MHz 0805 Ferrite Beads ROHS")
      (footprint "eagle-import:FB805")
      (fields (field (name "LCSC_PART") "C139188"))
      (libsource (lib "eagle-import") (part "FERRITE-0805"))
    )
    (comp (ref "R85")
      (value "200R")
      (footprint "eagle-import:R0402")
      (libsource (lib "eagle-import") (part "R-EU_R0402"))
    )
    (comp (ref "R86")
      (value "47K")
      (footprint "eagle-import:R0402")
      (libsource (lib "eagle-import") (part "R-EU_R0402"))
    )
    (comp (ref "R87")
      (value "120R")
      (footprint "eagle-import:R0402")
      (libsource (lib "eagle-import") (part "R-EU_R0402"))
    )
    (comp (ref "R88")
      (value "200R")
      (footprint "eagle-import:R0402")
      (libsource (lib "eagle-import") (part "R-EU_R0402"))
    )
    (comp (ref "R90")
      (value "2K")
      (footprint "eagle-import:R0402")
      (libsource (lib "eagle-import") (part "R-EU_R0402"))
    )
    (comp (ref "R91")
      (value "2K")
      (footprint "eagle-import:R0402")
      (libsource (lib "eagle-import") (part "R-EU_R0402"))
    )
    (comp (ref "R92")
      (value "2K")
      (footprint "eagle-import:R0402")
      (libsource (lib "eagle-import") (part "R-EU_R0402"))
    )
    (comp (ref "R93")
      (value "2K")
      (footprint "eagle-import:R0402")
      (libsource (lib "eagle-import") (part "R-EU_R0402"))
    )
    (comp (ref "R94")
      (value "2K")
      (footprint "eagle-import:R0402")
      (libsource (lib "eagle-import") (part "R-EU_R0402"))
    )
    (comp (ref "R95")
      (value "2K")
      (footprint "eagle-import:R0402")
      (libsource (lib "eagle-import") (part "R-EU_R0402"))
    )
    (comp (ref "U18")
      (value "CBMUD1201LAS8")
      (footprint "eagle-import:SOIC-8")
      (libsource (lib "eagle-import") (part "CBMUD1201LAS8"))
    )
    (comp (ref "U19")
      (value "PCA82C250T/YM")
      (footprint "eagle-import:SO8")
      (libsource (lib "eagle-import") (part "PCA82C250T"))
    )
    (comp (ref "U21")
      (value "EL357N-G")
      (footprint "eagle-import:OPTO_EL357N-G")
      (fields (field (name "MF") "Everlight Electronics"))
      (libsource (lib "eagle-import") (part "EL357N-G"))
    )
    (comp (ref "U22")
      (value "EL357N-G")
      (footprint "eagle-import:OPTO_EL357N-G")
      (fields (field (name "MF") "Everlight Electronics"))
      (libsource (lib "eagle-import") (part "EL357N-G"))
    )
    (comp (ref "C3_AL")
      (value "100nF")
      (footprint "eagle-import:C0402")
      (libsource (lib "eagle-import") (part "C-EUC0402"))
    )
    (comp (ref "C3_DR")
      (value "100nF")
      (footprint "eagle-import:C0402")
      (libsource (lib "eagle-import") (part "C-EUC0402"))
    )
    (comp (ref "C3_PRB")
      (value "100nF")
      (footprint "eagle-import:C0402")
      (libsource (lib "eagle-import") (part "C-EUC0402"))
    )
    (comp (ref "C3_TLO")
      (value "100nF")
      (footprint "eagle-import:C0402")
      (libsource (lib "eagle-import") (part "C-EUC0402"))
    )
    (comp (ref "C3_XL")
      (value "100nF")
      (footprint "eagle-import:C0402")
      (libsource (lib "eagle-import") (part "C-EUC0402"))
    )
    (comp (ref "C3_Y1L")
      (value "100nF")
      (footprint "eagle-import:C0402")
      (libsource (lib "eagle-import") (part "C-EUC0402"))
    )
    (comp (ref "C3_Y2L")
      (value "100nF")
      (footprint "eagle-import:C0402")
      (libsource (lib "eagle-import") (part "C-EUC0402"))
    )
    (comp (ref "C3_ZL")
      (value "100nF")
      (footprint "eagle-import:C0402")
      (libsource (lib "eagle-import") (part "C-EUC0402"))
    )
    (comp (ref "D3")
      (value "YELLOW")
      (footprint "eagle-import:CHIP-LED0603")
      (libsource (lib "eagle-import") (part "LEDCHIP-LED0603"))
    )
    (comp (ref "D4")
      (value "YELLOW")
      (footprint "eagle-import:CHIP-LED0603")
      (libsource (lib "eagle-import") (part "LEDCHIP-LED0603"))
    )
    (comp (ref "D5")
      (value "YELLOW")
      (footprint "eagle-import:CHIP-LED0603")
      (libsource (lib "eagle-import") (part "LEDCHIP-LED0603"))
    )
    (comp (ref "D6")
      (value "YELLOW")
      (footprint "eagle-import:CHIP-LED0603")
      (libsource (lib "eagle-import") (part "LEDCHIP-LED0603"))
    )
    (comp (ref "D7")
      (value "YELLOW")
      (footprint "eagle-import:CHIP-LED0603")
      (libsource (lib "eagle-import") (part "LEDCHIP-LED0603"))
    )
    (comp (ref "D8")
      (value "YELLOW")
      (footprint "eagle-import:CHIP-LED0603")
      (libsource (lib "eagle-import") (part "LEDCHIP-LED0603"))
    )
    (comp (ref "D9")
      (value "YELLOW")
      (footprint "eagle-import:CHIP-LED0603")
      (libsource (lib "eagle-import") (part "LEDCHIP-LED0603"))
    )
    (comp (ref "D39")
      (value "YELLOW")
      (footprint "eagle-import:CHIP-LED0603")
      (libsource (lib "eagle-import") (part "LEDCHIP-LED0603"))
    )
    (comp (ref "J2")
      (value "Phoenix Pluggable 3.81mm 3 way")
      (footprint "eagle-import:3.81MM-3WAY-PLUGGABLE-SCREW")
      (libsource (lib "eagle-import") (part "CONNECTOR-M3"))
    )
    (comp (ref "J3")
      (value "Phoenix Pluggable 3.81mm 2 way")
      (footprint "eagle-import:MC1.5_2-G-3.81")
      (libsource (lib "eagle-import") (part "MC1.5/2"))
    )
    (comp (ref "J4")
      (value "B4B-XH-A(LF)(SN)")
      (footprint "eagle-import:JST_B4B-XH-A(LF)(SN)")
      (fields (field (name "MF") "JST Sales") (field (name "MP") "B4B-XH-A (LF)(SN)"))
      (libsource (lib "eagle-import") (part "B4B-XH-A(LF)(SN)"))
    )
    (comp (ref "J5")
      (value "B4B-XH-A(LF)(SN)")
      (footprint "eagle-import:JST_B4B-XH-A(LF)(SN)")
      (fields (field (name "MF") "JST Sales") (field (name "MP") "B4B-XH-A (LF)(SN)"))
      (libsource (lib "eagle-import") (part "B4B-XH-A(LF)(SN)"))
    )
    (comp (ref "J6")
      (value "B4B-XH-A(LF)(SN)")
      (footprint "eagle-import:JST_B4B-XH-A(LF)(SN)")
      (fields (field (name "MF") "JST Sales") (field (name "MP") "B4B-XH-A (LF)(SN)"))
      (libsource (lib "eagle-import") (part "B4B-XH-A(LF)(SN)"))
    )
    (comp (ref "J7")
      (value "B4B-XH-A(LF)(SN)")
      (footprint "eagle-import:JST_B4B-XH-A(LF)(SN)")
      (fields (field (name "MF") "JST Sales") (field (name "MP") "B4B-XH-A (LF)(SN)"))
      (libsource (lib "eagle-import") (part "B4B-XH-A(LF)(SN)"))
    )
    (comp (ref "J8")
      (value "B4B-XH-A(LF)(SN)")
      (footprint "eagle-import:JST_B4B-XH-A(LF)(SN)")
      (fields (field (name "MF") "JST Sales") (field (name "MP") "B4B-XH-A (LF)(SN)"))
      (libsource (lib "eagle-import") (part "B4B-XH-A(LF)(SN)"))
    )
    (comp (ref "J15")
      (value "B4B-XH-A(LF)(SN)")
      (footprint "eagle-import:JST_B4B-XH-A(LF)(SN)")
      (fields (field (name "MF") "JST Sales") (field (name "MP") "B4B-XH-A (LF)(SN)"))
      (libsource (lib "eagle-import") (part "B4B-XH-A(LF)(SN)"))
    )
    (comp (ref "P17")
      (value "DB2EVC-3.81-7P-GN")
      (footprint "eagle-import:PHOENIX_1803471")
      (fields (field (name "MF") "Phoenix Contact") (field (name "MP") "1803471"))
      (libsource (lib "eagle-import") (part "1803471"))
    )
    (comp (ref "R9")
      (value "0R")
      (footprint "eagle-import:R0603")
      (libsource (lib "eagle-import") (part "R-EU_R0603"))
    )
    (comp (ref "R10")
      (value "DNI")
      (footprint "eagle-import:R0603")
      (libsource (lib "eagle-import") (part "R-EU_R0603"))
    )
    (comp (ref "R11")
      (value "1K")
      (footprint "eagle-import:R0402")
      (libsource (lib "eagle-import") (part "R-EU_R0402"))
    )
    (comp (ref "R12")
      (value "1K")
      (footprint "eagle-import:R0402")
      (libsource (lib "eagle-import") (part "R-EU_R0402"))
    )
    (comp (ref "R13")
      (value "1K")
      (footprint "eagle-import:R0402")
      (libsource (lib "eagle-import") (part "R-EU_R0402"))
    )
    (comp (ref "R14")
      (value "1K")
      (footprint "eagle-import:R0402")
      (libsource (lib "eagle-import") (part "R-EU_R0402"))
    )
    (comp (ref "R15")
      (value "1K")
      (footprint "eagle-import:R0402")
      (libsource (lib "eagle-import") (part "R-EU_R0402"))
    )
    (comp (ref "R16")
      (value "1K")
      (footprint "eagle-import:R0402")
      (libsource (lib "eagle-import") (part "R-EU_R0402"))
    )
    (comp (ref "R17")
      (value "1K")
      (footprint "eagle-import:R0402")
      (libsource (lib "eagle-import") (part "R-EU_R0402"))
    )
    (comp (ref "R22_AL")
      (value "4K7")
      (footprint "eagle-import:R0402")
      (libsource (lib "eagle-import") (part "R-EU_R0402"))
    )
    (comp (ref "R22_DR")
      (value "4K7")
      (footprint "eagle-import:R0402")
      (libsource (lib "eagle-import") (part "R-EU_R0402"))
    )
    (comp (ref "R22_PRB")
      (value "4K7")
      (footprint "eagle-import:R0402")
      (libsource (lib "eagle-import") (part "R-EU_R0402"))
    )
    (comp (ref "R22_TLO")
      (value "4K7")
      (footprint "eagle-import:R0402")
      (libsource (lib "eagle-import") (part "R-EU_R0402"))
    )
    (comp (ref "R22_XL")
      (value "4K7")
      (footprint "eagle-import:R0402")
      (libsource (lib "eagle-import") (part "R-EU_R0402"))
    )
    (comp (ref "R22_Y1L")
      (value "4K7")
      (footprint "eagle-import:R0402")
      (libsource (lib "eagle-import") (part "R-EU_R0402"))
    )
    (comp (ref "R22_Y2L")
      (value "4K7")
      (footprint "eagle-import:R0402")
      (libsource (lib "eagle-import") (part "R-EU_R0402"))
    )
    (comp (ref "R22_ZL")
      (value "4K7")
      (footprint "eagle-import:R0402")
      (libsource (lib "eagle-import") (part "R-EU_R0402"))
    )
    (comp (ref "R23_AL")
      (value "1K")
      (footprint "eagle-import:R0603")
      (libsource (lib "eagle-import") (part "R-EU_R0603"))
    )
    (comp (ref "R23_DR")
      (value "1K")
      (footprint "eagle-import:R0603")
      (libsource (lib "eagle-import") (part "R-EU_R0603"))
    )
    (comp (ref "R23_PRB")
      (value "1K")
      (footprint "eagle-import:R0603")
      (libsource (lib "eagle-import") (part "R-EU_R0603"))
    )
    (comp (ref "R23_TLO")
      (value "1K")
      (footprint "eagle-import:R0603")
      (libsource (lib "eagle-import") (part "R-EU_R0603"))
    )
    (comp (ref "R23_XL")
      (value "1K")
      (footprint "eagle-import:R0603")
      (libsource (lib "eagle-import") (part "R-EU_R0603"))
    )
    (comp (ref "R23_Y1L")
      (value "1K")
      (footprint "eagle-import:R0603")
      (libsource (lib "eagle-import") (part "R-EU_R0603"))
    )
    (comp (ref "R23_Y2L")
      (value "1K")
      (footprint "eagle-import:R0603")
      (libsource (lib "eagle-import") (part "R-EU_R0603"))
    )
    (comp (ref "R23_ZL")
      (value "1K")
      (footprint "eagle-import:R0603")
      (libsource (lib "eagle-import") (part "R-EU_R0603"))
    )
    (comp (ref "R63")
      (value "1K")
      (footprint "eagle-import:R0402")
      (libsource (lib "eagle-import") (part "R-EU_R0402"))
    )
    (comp (ref "U2_AL")
      (value "EL357N-G")
      (footprint "eagle-import:OPTO_EL357N-G")
      (fields (field (name "MF") "Everlight Electronics"))
      (libsource (lib "eagle-import") (part "EL357N-G"))
    )
    (comp (ref "U2_DR")
      (value "EL357N-G")
      (footprint "eagle-import:OPTO_EL357N-G")
      (fields (field (name "MF") "Everlight Electronics"))
      (libsource (lib "eagle-import") (part "EL357N-G"))
    )
    (comp (ref "U2_PRB")
      (value "EL357N-G")
      (footprint "eagle-import:OPTO_EL357N-G")
      (fields (field (name "MF") "Everlight Electronics"))
      (libsource (lib "eagle-import") (part "EL357N-G"))
    )
    (comp (ref "U2_TLO")
      (value "EL357N-G")
      (footprint "eagle-import:OPTO_EL357N-G")
      (fields (field (name "MF") "Everlight Electronics"))
      (libsource (lib "eagle-import") (part "EL357N-G"))
    )
    (comp (ref "U2_XL")
      (value "EL357N-G")
      (footprint "eagle-import:OPTO_EL357N-G")
      (fields (field (name "MF") "Everlight Electronics"))
      (libsource (lib "eagle-import") (part "EL357N-G"))
    )
    (comp (ref "U2_Y1L")
      (value "EL357N-G")
      (footprint "eagle-import:OPTO_EL357N-G")
      (fields (field (name "MF") "Everlight Electronics"))
      (libsource (lib "eagle-import") (part "EL357N-G"))
    )
    (comp (ref "U2_Y2L")
      (value "EL357N-G")
      (footprint "eagle-import:OPTO_EL357N-G")
      (fields (field (name "MF") "Everlight Electronics"))
      (libsource (lib "eagle-import") (part "EL357N-G"))
    )
    (comp (ref "U2_ZL")
      (value "EL357N-G")
      (footprint "eagle-import:OPTO_EL357N-G")
      (fields (field (name "MF") "Everlight Electronics"))
      (libsource (lib "eagle-import") (part "EL357N-G"))
    )
    (comp (ref "FID1")
      (value "FID_40MIL_P")
      (footprint "eagle-import:FID_040_P")
      (libsource (lib "eagle-import") (part "FID_40MIL_P"))
    )
    (comp (ref "FID2")
      (value "FID_40MIL_P")
      (footprint "eagle-import:FID_040_P")
      (libsource (lib "eagle-import") (part "FID_40MIL_P"))
    )
    (comp (ref "FID3")
      (value "FID_40MIL_P")
      (footprint "eagle-import:FID_040_P")
      (libsource (lib "eagle-import") (part "FID_40MIL_P"))
    )
    (comp (ref "TP1")
      (value "TPB2,54")
      (footprint "eagle-import:B2,54")
      (libsource (lib "eagle-import") (part "TPB2,54"))
    )
    (comp (ref "TP2")
      (value "TPB2,54")
      (footprint "eagle-import:B2,54")
      (libsource (lib "eagle-import") (part "TPB2,54"))
    )
    (comp (ref "TP3")
      (value "TPB2,54")
      (footprint "eagle-import:B2,54")
      (libsource (lib "eagle-import") (part "TPB2,54"))
    )
    (comp (ref "TP4")
      (value "TPB2,54")
      (footprint "eagle-import:B2,54")
      (libsource (lib "eagle-import") (part "TPB2,54"))
    )
    (comp (ref "TP5")
      (value "TPB2,54")
      (footprint "eagle-import:B2,54")
      (libsource (lib "eagle-import") (part "TPB2,54"))
    )
    (comp (ref "TP6")
      (value "TPB2,54")
      (footprint "eagle-import:B2,54")
      (libsource (lib "eagle-import") (part "TPB2,54"))
    )
    (comp (ref "TP7")
      (value "TPB2,54")
      (footprint "eagle-import:B2,54")
      (libsource (lib "eagle-import") (part "TPB2,54"))
    )
    (comp (ref "TP9")
      (value "TPB2,54")
      (footprint "eagle-import:B2,54")
      (libsource (lib "eagle-import") (part "TPB2,54"))
    )
    (comp (ref "TP11")
      (value "TPB2,54")
      (footprint "eagle-import:B2,54")
      (libsource (lib "eagle-import") (part "TPB2,54"))
    )
    (comp (ref "TP13")
      (value "TPB2,54")
      (footprint "eagle-import:B2,54")
      (libsource (lib "eagle-import") (part "TPB2,54"))
    )
    (comp (ref "TP14")
      (value "TPB2,54")
      (footprint "eagle-import:B2,54")
      (libsource (lib "eagle-import") (part "TPB2,54"))
    )
    (comp (ref "TP15")
      (value "TPB2,54")
      (footprint "eagle-import:B2,54")
      (libsource (lib "eagle-import") (part "TPB2,54"))
    )
    (comp (ref "TP16")
      (value "TPB2,54")
      (footprint "eagle-import:B2,54")
      (libsource (lib "eagle-import") (part "TPB2,54"))
    )
    (comp (ref "TP17")
      (value "TPB2,54")
      (footprint "eagle-import:B2,54")
      (libsource (lib "eagle-import") (part "TPB2,54"))
    )
    (comp (ref "TP18")
      (value "TPB2,54")
      (footprint "eagle-import:B2,54")
      (libsource (lib "eagle-import") (part "TPB2,54"))
    )
    (comp (ref "TP19")
      (value "TPB2,54")
      (footprint "eagle-import:B2,54")
      (libsource (lib "eagle-import") (part "TPB2,54"))
    )
    (comp (ref "TP20")
      (value "TPB2,54")
      (footprint "eagle-import:B2,54")
      (libsource (lib "eagle-import") (part "TPB2,54"))
    )
    (comp (ref "TP21")
      (value "TPB2,54")
      (footprint "eagle-import:B2,54")
      (libsource (lib "eagle-import") (part "TPB2,54"))
    )
    (comp (ref "TP22")
      (value "TPB2,54")
      (footprint "eagle-import:B2,54")
      (libsource (lib "eagle-import") (part "TPB2,54"))
    )
    (comp (ref "TP23")
      (value "TPB2,54")
      (footprint "eagle-import:B2,54")
      (libsource (lib "eagle-import") (part "TPB2,54"))
    )
    (comp (ref "TP24")
      (value "TPB2,54")
      (footprint "eagle-import:B2,54")
      (libsource (lib "eagle-import") (part "TPB2,54"))
    )
    (comp (ref "TP26")
      (value "TPB2,54")
      (footprint "eagle-import:B2,54")
      (libsource (lib "eagle-import") (part "TPB2,54"))
    )
    (comp (ref "TP28")
      (value "TPB2,54")
      (footprint "eagle-import:B2,54")
      (libsource (lib "eagle-import") (part "TPB2,54"))
    )
    (comp (ref "TP31")
      (value "TPB2,54")
      (footprint "eagle-import:B2,54")
      (libsource (lib "eagle-import") (part "TPB2,54"))
    )
    (comp (ref "TP32")
      (value "TPB2,54")
      (footprint "eagle-import:B2,54")
      (libsource (lib "eagle-import") (part "TPB2,54"))
    )
    (comp (ref "TP33")
      (value "TPB2,54")
      (footprint "eagle-import:B2,54")
      (libsource (lib "eagle-import") (part "TPB2,54"))
    )
    (comp (ref "TP34")
      (value "TPB2,54")
      (footprint "eagle-import:B2,54")
      (libsource (lib "eagle-import") (part "TPB2,54"))
    )
    (comp (ref "TP35")
      (value "TPB2,54")
      (footprint "eagle-import:B2,54")
      (libsource (lib "eagle-import") (part "TPB2,54"))
    )
    (comp (ref "TP36")
      (value "TPB2,54")
      (footprint "eagle-import:B2,54")
      (libsource (lib "eagle-import") (part "TPB2,54"))
    )
    (comp (ref "TP37")
      (value "TPB2,54")
      (footprint "eagle-import:B2,54")
      (libsource (lib "eagle-import") (part "TPB2,54"))
    )
    (comp (ref "TP38")
      (value "TPB2,54")
      (footprint "eagle-import:B2,54")
      (libsource (lib "eagle-import") (part "TPB2,54"))
    )
    (comp (ref "TP39")
      (value "TPB2,54")
      (footprint "eagle-import:B2,54")
      (libsource (lib "eagle-import") (part "TPB2,54"))
    )
    (comp (ref "TP40")
      (value "TPB2,54")
      (footprint "eagle-import:B2,54")
      (libsource (lib "eagle-import") (part "TPB2,54"))
    )
    (comp (ref "TP41")
      (value "TPB2,54")
      (footprint "eagle-import:B2,54")
      (libsource (lib "eagle-import") (part "TPB2,54"))
    )
    (comp (ref "TP42")
      (value "TPB2,54")
      (footprint "eagle-import:B2,54")
      (libsource (lib "eagle-import") (part "TPB2,54"))
    )
    (comp (ref "TP43")
      (value "TPB2,54")
      (footprint "eagle-import:B2,54")
      (libsource (lib "eagle-import") (part "TPB2,54"))
    )
    (comp (ref "TP44")
      (value "TPB2,54")
      (footprint "eagle-import:B2,54")
      (libsource (lib "eagle-import") (part "TPB2,54"))
    )
    (comp (ref "TP45")
      (value "TPB2,54")
      (footprint "eagle-import:B2,54")
      (libsource (lib "eagle-import") (part "TPB2,54"))
    )
    (comp (ref "TP46")
      (value "TPB2,54")
      (footprint "eagle-import:B2,54")
      (libsource (lib "eagle-import") (part "TPB2,54"))
    )
    (comp (ref "TP47")
      (value "TPB2,54")
      (footprint "eagle-import:B2,54")
      (libsource (lib "eagle-import") (part "TPB2,54"))
    )
    (comp (ref "TP48")
      (value "TPB2,54")
      (footprint "eagle-import:B2,54")
      (libsource (lib "eagle-import") (part "TPB2,54"))
    )
    (comp (ref "TP49")
      (value "TPB2,54")
      (footprint "eagle-import:B2,54")
      (libsource (lib "eagle-import") (part "TPB2,54"))
    )
    (comp (ref "TP50")
      (value "TPB2,54")
      (footprint "eagle-import:B2,54")
      (libsource (lib "eagle-import") (part "TPB2,54"))
    )
    (comp (ref "TP51")
      (value "TPB2,54")
      (footprint "eagle-import:B2,54")
      (libsource (lib "eagle-import") (part "TPB2,54"))
    )
    (comp (ref "TP52")
      (value "TPB2,54")
      (footprint "eagle-import:B2,54")
      (libsource (lib "eagle-import") (part "TPB2,54"))
    )
    (comp (ref "TP53")
      (value "TPB2,54")
      (footprint "eagle-import:B2,54")
      (libsource (lib "eagle-import") (part "TPB2,54"))
    )
    (comp (ref "TP54")
      (value "TPB2,54")
      (footprint "eagle-import:B2,54")
      (libsource (lib "eagle-import") (part "TPB2,54"))
    )
    (comp (ref "TP55")
      (value "TPB2,54")
      (footprint "eagle-import:B2,54")
      (libsource (lib "eagle-import") (part "TPB2,54"))
    )
    (comp (ref "TP56")
      (value "TPB2,54")
      (footprint "eagle-import:B2,54")
      (libsource (lib "eagle-import") (part "TPB2,54"))
    )
    (comp (ref "TP57")
      (value "TPB2,54")
      (footprint "eagle-import:B2,54")
      (libsource (lib "eagle-import") (part "TPB2,54"))
    )
    (comp (ref "TP58")
      (value "TPB2,54")
      (footprint "eagle-import:B2,54")
      (libsource (lib "eagle-import") (part "TPB2,54"))
    )
    (comp (ref "TP59")
      (value "TPB2,54")
      (footprint "eagle-import:B2,54")
      (libsource (lib "eagle-import") (part "TPB2,54"))
    )
    (comp (ref "TP60")
      (value "TPB2,54")
      (footprint "eagle-import:B2,54")
      (libsource (lib "eagle-import") (part "TPB2,54"))
    )
    (comp (ref "TP61")
      (value "TPB2,54")
      (footprint "eagle-import:B2,54")
      (libsource (lib "eagle-import") (part "TPB2,54"))
    )
    (comp (ref "C21")
      (value "100nF")
      (footprint "eagle-import:C0402")
      (libsource (lib "eagle-import") (part "C-EUC0402"))
    )
    (comp (ref "C22")
      (value "100nF")
      (footprint "eagle-import:C0402")
      (libsource (lib "eagle-import") (part "C-EUC0402"))
    )
    (comp (ref "C23")
      (value "4.7uF")
      (footprint "eagle-import:C0603K")
      (libsource (lib "eagle-import") (part "C-EUC0603K"))
    )
    (comp (ref "C24")
      (value "100nF")
      (footprint "eagle-import:C0402")
      (libsource (lib "eagle-import") (part "C-EUC0402"))
    )
    (comp (ref "C25")
      (value "4.7uF")
      (footprint "eagle-import:C0603K")
      (libsource (lib "eagle-import") (part "C-EUC0603K"))
    )
    (comp (ref "C26")
      (value "4.7uF")
      (footprint "eagle-import:C0603K")
      (libsource (lib "eagle-import") (part "C-EUC0603K"))
    )
    (comp (ref "C27")
      (value "1uF")
      (footprint "eagle-import:C0603")
      (libsource (lib "eagle-import") (part "C-EUC0603"))
    )
    (comp (ref "C28")
      (value "1uF")
      (footprint "eagle-import:C0603K")
      (libsource (lib "eagle-import") (part "C-EUC0603K"))
    )
    (comp (ref "C29")
      (value "100nF")
      (footprint "eagle-import:C0402")
      (libsource (lib "eagle-import") (part "C-EUC0402"))
    )
    (comp (ref "C30")
      (value "100nF")
      (footprint "eagle-import:C0402")
      (libsource (lib "eagle-import") (part "C-EUC0402"))
    )
    (comp (ref "C31")
      (value "100nF")
      (footprint "eagle-import:C0402")
      (libsource (lib "eagle-import") (part "C-EUC0402"))
    )
    (comp (ref "C32")
      (value "100nF")
      (footprint "eagle-import:C0402")
      (libsource (lib "eagle-import") (part "C-EUC0402"))
    )
    (comp (ref "C33")
      (value "100nF")
      (footprint "eagle-import:C0402")
      (libsource (lib "eagle-import") (part "C-EUC0402"))
    )
    (comp (ref "C34")
      (value "100nF")
      (footprint "eagle-import:C0402")
      (libsource (lib "eagle-import") (part "C-EUC0402"))
    )
    (comp (ref "C35")
      (value "100nF")
      (footprint "eagle-import:C0402")
      (libsource (lib "eagle-import") (part "C-EUC0402"))
    )
    (comp (ref "C36")
      (value "100nF")
      (footprint "eagle-import:C0402")
      (libsource (lib "eagle-import") (part "C-EUC0402"))
    )
    (comp (ref "C37")
      (value "100nF")
      (footprint "eagle-import:C0402")
      (libsource (lib "eagle-import") (part "C-EUC0402"))
    )
    (comp (ref "C38")
      (value "10pF")
      (footprint "eagle-import:C0603K")
      (libsource (lib "eagle-import") (part "C-EUC0603K"))
    )
    (comp (ref "C39")
      (value "10pF")
      (footprint "eagle-import:C0603K")
      (libsource (lib "eagle-import") (part "C-EUC0603K"))
    )
    (comp (ref "C97")
      (value "10nF")
      (footprint "eagle-import:C0402")
      (libsource (lib "eagle-import") (part "C-EUC0402"))
    )
    (comp (ref "C98")
      (value "0.1uF")
      (footprint "eagle-import:0805")
      (libsource (lib "eagle-import") (part "CAP0805"))
    )
    (comp (ref "C100")
      (value "4.7uF")
      (footprint "eagle-import:C0603K")
      (libsource (lib "eagle-import") (part "C-EUC0603K"))
    )
    (comp (ref "C101")
      (value "1uF")
      (footprint "eagle-import:C0402")
      (libsource (lib "eagle-import") (part "C-EUC0402"))
    )
    (comp (ref "C102")
      (value "100nF")
      (footprint "eagle-import:C0402")
      (libsource (lib "eagle-import") (part "C-EUC0402"))
    )
    (comp (ref "D29")
      (value "GREEN")
      (footprint "eagle-import:CHIP-LED0603")
      (libsource (lib "eagle-import") (part "LEDCHIP-LED0603"))
    )
    (comp (ref "L4")
      (value "700mΩ ±25% 220Ω@100MHz 0402 Ferrite Bead")
      (footprint "eagle-import:FB402")
      (libsource (lib "eagle-import") (part "FERRITE-0402"))
    )
    (comp (ref "P15")
      (value "DNI")
      (footprint "eagle-import:621X1021021")
      (libsource (lib "eagle-import") (part "621X1021021"))
    )
    (comp (ref "P25")
      (value "DNI")
      (footprint "eagle-import:1X02")
      (libsource (lib "eagle-import") (part "PINHD-1X2"))
    )
    (comp (ref "P26")
      (value "DNI")
      (footprint "eagle-import:1X02")
      (libsource (lib "eagle-import") (part "PINHD-1X2"))
    )
    (comp (ref "R7")
      (value "10K")
      (footprint "eagle-import:R0402")
      (libsource (lib "eagle-import") (part "R-EU_R0402"))
    )
    (comp (ref "R61")
      (value "10K")
      (footprint "eagle-import:R0402")
      (libsource (lib "eagle-import") (part "R-EU_R0402"))
    )
    (comp (ref "R62")
      (value "10K")
      (footprint "eagle-import:R0402")
      (libsource (lib "eagle-import") (part "R-EU_R0402"))
    )
    (comp (ref "R64")
      (value "4K7")
      (footprint "eagle-import:R0402")
      (libsource (lib "eagle-import") (part "R-EU_R0402"))
    )
    (comp (ref "R65")
      (value "4K7")
      (footprint "eagle-import:R0402")
      (libsource (lib "eagle-import") (part "R-EU_R0402"))
    )
    (comp (ref "R66")
      (value "4K7")
      (footprint "eagle-import:R0402")
      (libsource (lib "eagle-import") (part "R-EU_R0402"))
    )
    (comp (ref "R67")
      (value "22R")
      (footprint "eagle-import:R0603")
      (libsource (lib "eagle-import") (part "R-EU_R0603"))
    )
    (comp (ref "R68")
      (value "22R")
      (footprint "eagle-import:R0603")
      (libsource (lib "eagle-import") (part "R-EU_R0603"))
    )
    (comp (ref "R69")
      (value "2K2")
      (footprint "eagle-import:R0402")
      (libsource (lib "eagle-import") (part "R-EU_R0402"))
    )
    (comp (ref "R72")
      (value "4K7")
      (footprint "eagle-import:R0402")
      (libsource (lib "eagle-import") (part "R-EU_R0402"))
    )
    (comp (ref "R74")
      (value "22R")
      (footprint "eagle-import:R0603")
      (libsource (lib "eagle-import") (part "R-EU_R0603"))
    )
    (comp (ref "R75")
      (value "22R")
      (footprint "eagle-import:R0603")
      (libsource (lib "eagle-import") (part "R-EU_R0603"))
    )
    (comp (ref "R76")
      (value "22R")
      (footprint "eagle-import:R0603")
      (libsource (lib "eagle-import") (part "R-EU_R0603"))
    )
    (comp (ref "R102")
      (value "0R")
      (footprint "eagle-import:R0603")
      (libsource (lib "eagle-import") (part "R-EU_R0603"))
    )
    (comp (ref "R131")
      (value "0R")
      (footprint "eagle-import:R0603")
      (libsource (lib "eagle-import") (part "R-EU_R0603"))
    )
    (comp (ref "SD3")
      (value "TF-HOLDER")
      (footprint "eagle-import:TF-PULL")
      (libsource (lib "eagle-import") (part "TF-HOLDER"))
    )
    (comp (ref "U17")
      (value "STM32F412VGT6STM32F412VGT6")
      (footprint "eagle-import:LQFP100")
      (fields (field (name "LCSC_PART") "C727951"))
      (libsource (lib "eagle-import") (part "STM32F412VGT6STM32F412VGT6"))
    )
    (comp (ref "U35")
      (value "ZD24C128A-SSGMB")
      (footprint "eagle-import:SO-08M")
      (fields (field (name "MF") "RAMTRON INTERNATIONAL CORP") (field (name "MPN") "FM24C64-S"))
      (libsource (lib "eagle-import") (part "24SMC64"))
    )
    (comp (ref "Y1")
      (value "25Mhz")
      (footprint "eagle-import:XTAL_TSX-3225_16.0000MF18X-AC3")
      (fields
        (field (name "LCSC_PART") "C2682775")
        (field (name "MF") "EPSON")
        (field (name "MP") "TSX-3225 16.0000MF18X-AC3")
      )
      (libsource (lib "eagle-import") (part "TSX-3225_16.0000MF18X-AC3"))
    )
    (comp (ref "C6")
      (value "100nF")
      (footprint "eagle-import:C0603K")
      (libsource (lib "eagle-import") (part "C-EUC0603K"))
    )
    (comp (ref "C40")
      (value "1uF")
      (footprint "eagle-import:C0603K")
      (libsource (lib "eagle-import") (part "C-EUC0603K"))
    )
    (comp (ref "C41")
      (value "100nF")
      (footprint "eagle-import:C0603K")
      (libsource (lib "eagle-import") (part "C-EUC0603K"))
    )
    (comp (ref "C42")
      (value "100nF")
      (footprint "eagle-import:C0603K")
      (libsource (lib "eagle-import") (part "C-EUC0603K"))
    )
    (comp (ref "C43")
      (value "100nF")
      (footprint "eagle-import:C0603K")
      (libsource (lib "eagle-import") (part "C-EUC0603K"))
    )
    (comp (ref "C44")
      (value "100nF")
      (footprint "eagle-import:C0603K")
      (libsource (lib "eagle-import") (part "C-EUC0603K"))
    )
    (comp (ref "C45")
      (value "100nF")
      (footprint "eagle-import:C0603K")
      (libsource (lib "eagle-import") (part "C-EUC0603K"))
    )
    (comp (ref "C46")
      (value "1uF")
      (footprint "eagle-import:C0603K")
      (libsource (lib "eagle-import") (part "C-EUC0603K"))
    )
    (comp (ref "C47")
      (value "100nF")
      (footprint "eagle-import:C0603K")
      (libsource (lib "eagle-import") (part "C-EUC0603K"))
    )
    (comp (ref "C48")
      (value "100nF")
      (footprint "eagle-import:C0603K")
      (libsource (lib "eagle-import") (part "C-EUC0603K"))
    )
    (comp (ref "C49")
      (value "100nF")
      (footprint "eagle-import:C0603K")
      (libsource (lib "eagle-import") (part "C-EUC0603K"))
    )
    (comp (ref "C50")
      (value "100nF")
      (footprint "eagle-import:C0603K")
      (libsource (lib "eagle-import") (part "C-EUC0603K"))
    )
    (comp (ref "C51")
      (value "100nF")
      (footprint "eagle-import:C0603K")
      (libsource (lib "eagle-import") (part "C-EUC0603K"))
    )
    (comp (ref "C72")
      (value "100nF")
      (footprint "eagle-import:C0402")
      (libsource (lib "eagle-import") (part "C-EUC0402"))
    )
    (comp (ref "C116")
      (value "100nF")
      (footprint "eagle-import:C0603K")
      (libsource (lib "eagle-import") (part "C-EUC0603K"))
    )
    (comp (ref "C119")
      (value "100nF")
      (footprint "eagle-import:C0603K")
      (libsource (lib "eagle-import") (part "C-EUC0603K"))
    )
    (comp (ref "C122")
      (value "100nF")
      (footprint "eagle-import:C0603K")
      (libsource (lib "eagle-import") (part "C-EUC0603K"))
    )
    (comp (ref "C136")
      (value "100nF")
      (footprint "eagle-import:C0603K")
      (libsource (lib "eagle-import") (part "C-EUC0603K"))
    )
    (comp (ref "C137")
      (value "100nF")
      (footprint "eagle-import:C0603K")
      (libsource (lib "eagle-import") (part "C-EUC0603K"))
    )
    (comp (ref "C138")
      (value "100nF")
      (footprint "eagle-import:C0603K")
      (libsource (lib "eagle-import") (part "C-EUC0603K"))
    )
    (comp (ref "D21")
      (value "ZMM5V6-M")
      (footprint "eagle-import:MINIMELF")
      (libsource (lib "eagle-import") (part "DIODE-MINIMELF"))
    )
    (comp (ref "D22")
      (value "ZMM5V6-M")
      (footprint "eagle-import:MINIMELF")
      (libsource (lib "eagle-import") (part "DIODE-MINIMELF"))
    )
    (comp (ref "D35")
      (value "BAT54S")
      (footprint "eagle-import:SOT95P240X120-3N")
      (fields (field (name "MF") "ON Semiconductor"))
      (libsource (lib "eagle-import") (part "BAT54S"))
    )
    (comp (ref "D51")
      (value "GRN")
      (footprint "eagle-import:CHIP-LED0603")
      (libsource (lib "eagle-import") (part "LEDCHIP-LED0603"))
    )
    (comp (ref "D52")
      (value "GRN")
      (footprint "eagle-import:CHIP-LED0603")
      (libsource (lib "eagle-import") (part "LEDCHIP-LED0603"))
    )
    (comp (ref "D53")
      (value "BAT54S")
      (footprint "eagle-import:SOT95P240X120-3N")
      (fields (field (name "MF") "ON Semiconductor"))
      (libsource (lib "eagle-import") (part "BAT54S"))
    )
    (comp (ref "D54")
      (value "BAT54S")
      (footprint "eagle-import:SOT95P240X120-3N")
      (fields (field (name "MF") "ON Semiconductor"))
      (libsource (lib "eagle-import") (part "BAT54S"))
    )
    (comp (ref "D55")
      (value "BAT54S")
      (footprint "eagle-import:SOT95P240X120-3N")
      (fields (field (name "MF") "ON Semiconductor"))
      (libsource (lib "eagle-import") (part "BAT54S"))
    )
    (comp (ref "D59")
      (value "GRN")
      (footprint "eagle-import:CHIP-LED0603")
      (libsource (lib "eagle-import") (part "LEDCHIP-LED0603"))
    )
    (comp (ref "D60")
      (value "GRN")
      (footprint "eagle-import:CHIP-LED0603")
      (libsource (lib "eagle-import") (part "LEDCHIP-LED0603"))
    )
    (comp (ref "D61")
      (value "RED")
      (footprint "eagle-import:CHIP-LED0603")
      (libsource (lib "eagle-import") (part "LEDCHIP-LED0603"))
    )
    (comp (ref "D62")
      (value "RED")
      (footprint "eagle-import:CHIP-LED0603")
      (libsource (lib "eagle-import") (part "LEDCHIP-LED0603"))
    )
    (comp (ref "D63")
      (value "RED")
      (footprint "eagle-import:CHIP-LED0603")
      (libsource (lib "eagle-import") (part "LEDCHIP-LED0603"))
    )
    (comp (ref "D64")
      (value "RED")
      (footprint "eagle-import:CHIP-LED0603")
      (libsource (lib "eagle-import") (part "LEDCHIP-LED0603"))
    )
    (comp (ref "P1")
      (value "DB2EVC-3.81-2P-GN")
      (footprint "eagle-import:DB2EVC-3.81-2P-GN")
      (fields (field (name "MF") "Würth Elektronik") (field (name "MP") "691321300002"))
      (libsource (lib "eagle-import") (part "DB2EVC-3.81-2P-GN"))
    )
    (comp (ref "P2")
      (value "DB2EVC-3.81-2P-GN")
      (footprint "eagle-import:DB2EVC-3.81-2P-GN")
      (fields (field (name "MF") "Würth Elektronik") (field (name "MP") "691321300002"))
      (libsource (lib "eagle-import") (part "DB2EVC-3.81-2P-GN"))
    )
    (comp (ref "P3")
      (value "DB2EVC-3.81-2P-GN")
      (footprint "eagle-import:DB2EVC-3.81-2P-GN")
      (fields (field (name "MF") "Würth Elektronik") (field (name "MP") "691321300002"))
      (libsource (lib "eagle-import") (part "DB2EVC-3.81-2P-GN"))
    )
    (comp (ref "P4")
      (value "DB2EVC-3.81-2P-GN")
      (footprint "eagle-import:DB2EVC-3.81-2P-GN")
      (fields (field (name "MF") "Würth Elektronik") (field (name "MP") "691321300002"))
      (libsource (lib "eagle-import") (part "DB2EVC-3.81-2P-GN"))
    )
    (comp (ref "P13")
      (value "SHROUDED_BOX_HEADER_08")
      (footprint "eagle-import:SHROUDED_BOX_HEADER_08")
      (libsource (lib "eagle-import") (part "SHROUDED_BOX_HEADER_08"))
    )
    (comp (ref "P14")
      (value "SHROUDED_BOX_HEADER_08")
      (footprint "eagle-import:SHROUDED_BOX_HEADER_08")
      (libsource (lib "eagle-import") (part "SHROUDED_BOX_HEADER_08"))
    )
    (comp (ref "P16")
      (value "SHROUDED_BOX_HEADER_08")
      (footprint "eagle-import:SHROUDED_BOX_HEADER_08")
      (libsource (lib "eagle-import") (part "SHROUDED_BOX_HEADER_08"))
    )
    (comp (ref "P27")
      (value "SHROUDED_BOX_HEADER_08")
      (footprint "eagle-import:SHROUDED_BOX_HEADER_08")
      (libsource (lib "eagle-import") (part "SHROUDED_BOX_HEADER_08"))
    )
    (comp (ref "P28")
      (value "DB2EVC-3.81-2P-GN")
      (footprint "eagle-import:DB2EVC-3.81-2P-GN")
      (fields (field (name "MF") "Würth Elektronik") (field (name "MP") "691321300002"))
      (libsource (lib "eagle-import") (part "DB2EVC-3.81-2P-GN"))
    )
    (comp (ref "R27")
      (value "10K")
      (footprint "eagle-import:R0402")
      (libsource (lib "eagle-import") (part "R-EU_R0402"))
    )
    (comp (ref "R78")
      (value "10K")
      (footprint "eagle-import:R0603")
      (libsource (lib "eagle-import") (part "R-EU_R0603"))
    )
    (comp (ref "R79")
      (value "10K")
      (footprint "eagle-import:R0402")
      (libsource (lib "eagle-import") (part "R-EU_R0402"))
    )
    (comp (ref "R80")
      (value "10K")
      (footprint "eagle-import:R0603")
      (libsource (lib "eagle-import") (part "R-EU_R0603"))
    )
    (comp (ref "R81")
      (value "10K")
      (footprint "eagle-import:R0402")
      (libsource (lib "eagle-import") (part "R-EU_R0402"))
    )
    (comp (ref "R185")
      (value "2K2")
      (footprint "eagle-import:R0402")
      (libsource (lib "eagle-import") (part "R-EU_R0402"))
    )
    (comp (ref "R186")
      (value "2K2")
      (footprint "eagle-import:R0402")
      (libsource (lib "eagle-import") (part "R-EU_R0402"))
    )
    (comp (ref "R187")
      (value "2K2")
      (footprint "eagle-import:R0402")
      (libsource (lib "eagle-import") (part "R-EU_R0402"))
    )
    (comp (ref "R188")
      (value "2K2")
      (footprint "eagle-import:R0402")
      (libsource (lib "eagle-import") (part "R-EU_R0402"))
    )
    (comp (ref "R189")
      (value "200R")
      (footprint "eagle-import:R0603")
      (libsource (lib "eagle-import") (part "R-EU_R0603"))
    )
    (comp (ref "R190")
      (value "200R")
      (footprint "eagle-import:R0603")
      (libsource (lib "eagle-import") (part "R-EU_R0603"))
    )
    (comp (ref "R191")
      (value "200R")
      (footprint "eagle-import:R0603")
      (libsource (lib "eagle-import") (part "R-EU_R0603"))
    )
    (comp (ref "R192")
      (value "200R")
      (footprint "eagle-import:R0603")
      (libsource (lib "eagle-import") (part "R-EU_R0603"))
    )
    (comp (ref "R193")
      (value "10K")
      (footprint "eagle-import:R0603")
      (libsource (lib "eagle-import") (part "R-EU_R0603"))
    )
    (comp (ref "R194")
      (value "10K")
      (footprint "eagle-import:R0402")
      (libsource (lib "eagle-import") (part "R-EU_R0402"))
    )
    (comp (ref "R195")
      (value "10K")
      (footprint "eagle-import:R0603")
      (libsource (lib "eagle-import") (part "R-EU_R0603"))
    )
    (comp (ref "R205")
      (value "2K2")
      (footprint "eagle-import:R0402")
      (libsource (lib "eagle-import") (part "R-EU_R0402"))
    )
    (comp (ref "R206")
      (value "2K2")
      (footprint "eagle-import:R0402")
      (libsource (lib "eagle-import") (part "R-EU_R0402"))
    )
    (comp (ref "R207")
      (value "2K2")
      (footprint "eagle-import:R0402")
      (libsource (lib "eagle-import") (part "R-EU_R0402"))
    )
    (comp (ref "R208")
      (value "2K2")
      (footprint "eagle-import:R0402")
      (libsource (lib "eagle-import") (part "R-EU_R0402"))
    )
    (comp (ref "U9")
      (value "AM26LS31CDRG4")
      (footprint "eagle-import:SOIC127P600X175-16N")
      (fields (field (name "MF") "Texas Instruments") (field (name "MP") "AM26LS31CDR"))
      (libsource (lib "eagle-import") (part "AM26LS31CDR"))
    )
    (comp (ref "U26")
      (value "ADUM1200ARZ-RL7")
      (footprint "eagle-import:SOIC127P600X175-8N")
      (fields (field (name "MF") "Analog Devices") (field (name "MP") "ADUM1200ARZRL7"))
      (libsource (lib "eagle-import") (part "ADUM1200ARZ-RL7"))
    )
    (comp (ref "U27")
      (value "ADUM1200ARZ-RL7")
      (footprint "eagle-import:SOIC127P600X175-8N")
      (fields (field (name "MF") "Analog Devices") (field (name "MP") "ADUM1200ARZRL7"))
      (libsource (lib "eagle-import") (part "ADUM1200ARZ-RL7"))
    )
    (comp (ref "U36")
      (value "AM26LS31CDRG4")
      (footprint "eagle-import:SOIC127P600X175-16N")
      (fields (field (name "MF") "Texas Instruments") (field (name "MP") "AM26LS31CDR"))
      (libsource (lib "eagle-import") (part "AM26LS31CDR"))
    )
    (comp (ref "U37")
      (value "ADUM1200ARZ-RL7")
      (footprint "eagle-import:SOIC127P600X175-8N")
      (fields (field (name "MF") "Analog Devices") (field (name "MP") "ADUM1200ARZRL7"))
      (libsource (lib "eagle-import") (part "ADUM1200ARZ-RL7"))
    )
    (comp (ref "U38")
      (value "ADUM1200ARZ-RL7")
      (footprint "eagle-import:SOIC127P600X175-8N")
      (fields (field (name "MF") "Analog Devices") (field (name "MP") "ADUM1200ARZRL7"))
      (libsource (lib "eagle-import") (part "ADUM1200ARZ-RL7"))
    )
    (comp (ref "U39")
      (value "EL357N-G")
      (footprint "eagle-import:OPTO_EL357N-G")
      (fields (field (name "MF") "Everlight Electronics"))
      (libsource (lib "eagle-import") (part "EL357N-G"))
    )
    (comp (ref "U45")
      (value "ADUM1200ARZ-RL7")
      (footprint "eagle-import:SOIC127P600X175-8N")
      (fields (field (name "MF") "Analog Devices") (field (name "MP") "ADUM1200ARZRL7"))
      (libsource (lib "eagle-import") (part "ADUM1200ARZ-RL7"))
    )
    (comp (ref "U46")
      (value "ADUM1200ARZ-RL7")
      (footprint "eagle-import:SOIC127P600X175-8N")
      (fields (field (name "MF") "Analog Devices") (field (name "MP") "ADUM1200ARZRL7"))
      (libsource (lib "eagle-import") (part "ADUM1200ARZ-RL7"))
    )
    (comp (ref "U47")
      (value "EL357N-G")
      (footprint "eagle-import:OPTO_EL357N-G")
      (fields (field (name "MF") "Everlight Electronics"))
      (libsource (lib "eagle-import") (part "EL357N-G"))
    )
    (comp (ref "U48")
      (value "EL357N-G")
      (footprint "eagle-import:OPTO_EL357N-G")
      (fields (field (name "MF") "Everlight Electronics"))
      (libsource (lib "eagle-import") (part "EL357N-G"))
    )
    (comp (ref "U49")
      (value "EL357N-G")
      (footprint "eagle-import:OPTO_EL357N-G")
      (fields (field (name "MF") "Everlight Electronics"))
      (libsource (lib "eagle-import") (part "EL357N-G"))
    )
    (comp (ref "C82")
      (value "1uF")
      (footprint "eagle-import:C0402")
      (libsource (lib "eagle-import") (part "C-EUC0402"))
    )
    (comp (ref "C109")
      (value "10nF")
      (footprint "eagle-import:C0402")
      (libsource (lib "eagle-import") (part "C-EUC0402"))
    )
    (comp (ref "C110")
      (value "6.8nF")
      (footprint "eagle-import:C0402")
      (libsource (lib "eagle-import") (part "C-EUC0402"))
    )
    (comp (ref "C111")
      (value "6.8nF")
      (footprint "eagle-import:C0402")
      (libsource (lib "eagle-import") (part "C-EUC0402"))
    )
    (comp (ref "C112")
      (value "22nF")
      (footprint "eagle-import:C0402")
      (libsource (lib "eagle-import") (part "C-EUC0402"))
    )
    (comp (ref "C114")
      (value "1nF")
      (footprint "eagle-import:C1206")
      (libsource (lib "eagle-import") (part "C-EUC1206"))
    )
    (comp (ref "C117")
      (value "4.7uF")
      (footprint "eagle-import:C0402")
      (libsource (lib "eagle-import") (part "C-EUC0402"))
    )
    (comp (ref "C118")
      (value "10nF")
      (footprint "eagle-import:C0402")
      (libsource (lib "eagle-import") (part "C-EUC0402"))
    )
    (comp (ref "C120")
      (value "10pF")
      (footprint "eagle-import:C0402")
      (libsource (lib "eagle-import") (part "C-EUC0402"))
    )
    (comp (ref "C121")
      (value "10pF")
      (footprint "eagle-import:C0402")
      (libsource (lib "eagle-import") (part "C-EUC0402"))
    )
    (comp (ref "C123")
      (value "22uF")
      (footprint "eagle-import:C0603K")
      (libsource (lib "eagle-import") (part "C-EUC0603K"))
    )
    (comp (ref "C124")
      (value "4.7uF")
      (footprint "eagle-import:C0603K")
      (libsource (lib "eagle-import") (part "C-EUC0603K"))
    )
    (comp (ref "C125")
      (value "100nf")
      (footprint "eagle-import:C0402")
      (libsource (lib "eagle-import") (part "C-EUC0402"))
    )
    (comp (ref "C126")
      (value "100nf")
      (footprint "eagle-import:C0402")
      (libsource (lib "eagle-import") (part "C-EUC0402"))
    )
    (comp (ref "C127")
      (value "100nf")
      (footprint "eagle-import:C0402")
      (libsource (lib "eagle-import") (part "C-EUC0402"))
    )
    (comp (ref "C128")
      (value "100nf")
      (footprint "eagle-import:C0603K")
      (libsource (lib "eagle-import") (part "C-EUC0603K"))
    )
    (comp (ref "C129")
      (value "100nf")
      (footprint "eagle-import:C0402")
      (libsource (lib "eagle-import") (part "C-EUC0402"))
    )
    (comp (ref "C130")
      (value "100nf")
      (footprint "eagle-import:C0402")
      (libsource (lib "eagle-import") (part "C-EUC0402"))
    )
    (comp (ref "C131")
      (value "22uF")
      (footprint "eagle-import:C0603K")
      (libsource (lib "eagle-import") (part "C-EUC0603K"))
    )
    (comp (ref "C132")
      (value "22uF")
      (footprint "eagle-import:C0603K")
      (libsource (lib "eagle-import") (part "C-EUC0603K"))
    )
    (comp (ref "C133")
      (value "100nf")
      (footprint "eagle-import:C0402")
      (libsource (lib "eagle-import") (part "C-EUC0402"))
    )
    (comp (ref "J1")
      (value "16P_HEADER_SMD")
      (footprint "eagle-import:16_PIN_SMD_PIN_HEADER")
      (libsource (lib "eagle-import") (part "16P_HEADER_SMD"))
    )
    (comp (ref "L6")
      (value "700mΩ ±25% 220Ω@100MHz 0402 Ferrite Bead")
      (footprint "eagle-import:FB402")
      (libsource (lib "eagle-import") (part "FERRITE-0402"))
    )
    (comp (ref "P12")
      (value "HR911105A")
      (footprint "eagle-import:HANRUN_HR911105A")
      (fields (field (name "MF") "hanrun"))
      (libsource (lib "eagle-import") (part "HR911105A"))
    )
    (comp (ref "R1")
      (value "10K")
      (footprint "eagle-import:R0402")
      (libsource (lib "eagle-import") (part "R-EU_R0402"))
    )
    (comp (ref "R2")
      (value "0R")
      (footprint "eagle-import:R0603")
      (libsource (lib "eagle-import") (part "R-EU_R0603"))
    )
    (comp (ref "R3")
      (value "0R")
      (footprint "eagle-import:R0603")
      (libsource (lib "eagle-import") (part "R-EU_R0603"))
    )
    (comp (ref "R4")
      (value "0R")
      (footprint "eagle-import:R0603")
      (libsource (lib "eagle-import") (part "R-EU_R0603"))
    )
    (comp (ref "R5")
      (value "10K")
      (footprint "eagle-import:R0402")
      (libsource (lib "eagle-import") (part "R-EU_R0402"))
    )
    (comp (ref "R6")
      (value "10K")
      (footprint "eagle-import:R0402")
      (libsource (lib "eagle-import") (part "R-EU_R0402"))
    )
    (comp (ref "R135")
      (value "10K")
      (footprint "eagle-import:R0402")
      (libsource (lib "eagle-import") (part "R-EU_R0402"))
    )
    (comp (ref "R136")
      (value "49.9R")
      (footprint "eagle-import:R0402")
      (libsource (lib "eagle-import") (part "R-EU_R0402"))
    )
    (comp (ref "R137")
      (value "49.9R")
      (footprint "eagle-import:R0402")
      (libsource (lib "eagle-import") (part "R-EU_R0402"))
    )
    (comp (ref "R139")
      (value "33R")
      (footprint "eagle-import:R0402")
      (libsource (lib "eagle-import") (part "R-EU_R0402"))
    )
    (comp (ref "R140")
      (value "33R")
      (footprint "eagle-import:R0402")
      (libsource (lib "eagle-import") (part "R-EU_R0402"))
    )
    (comp (ref "R141")
      (value "33R")
      (footprint "eagle-import:R0402")
      (libsource (lib "eagle-import") (part "R-EU_R0402"))
    )
    (comp (ref "R142")
      (value "33R")
      (footprint "eagle-import:R0402")
      (libsource (lib "eagle-import") (part "R-EU_R0402"))
    )
    (comp (ref "R143")
      (value "10K")
      (footprint "eagle-import:R0603")
      (libsource (lib "eagle-import") (part "R-EU_R0603"))
    )
    (comp (ref "R144")
      (value "49.9R")
      (footprint "eagle-import:R0402")
      (libsource (lib "eagle-import") (part "R-EU_R0402"))
    )
    (comp (ref "R145")
      (value "49.9R")
      (footprint "eagle-import:R0402")
      (libsource (lib "eagle-import") (part "R-EU_R0402"))
    )
    (comp (ref "R146")
      (value "10R")
      (footprint "eagle-import:R0402")
      (libsource (lib "eagle-import") (part "R-EU_R0402"))
    )
    (comp (ref "R147")
      (value "1M")
      (footprint "eagle-import:R0402")
      (libsource (lib "eagle-import") (part "R-EU_R0402"))
    )
    (comp (ref "R148")
      (value "330R")
      (footprint "eagle-import:R0402")
      (libsource (lib "eagle-import") (part "R-EU_R0402"))
    )
    (comp (ref "R149")
      (value "0R")
      (footprint "eagle-import:R0402")
      (libsource (lib "eagle-import") (part "R-EU_R0402"))
    )
    (comp (ref "R150")
      (value "330R")
      (footprint "eagle-import:R0402")
      (libsource (lib "eagle-import") (part "R-EU_R0402"))
    )
    (comp (ref "U11")
      (value "W5500")
      (footprint "eagle-import:QFP50P900X900X160-48N")
      (fields (field (name "MF") "WIZnet"))
      (libsource (lib "eagle-import") (part "W5500"))
    )
    (comp (ref "Y3")
      (value "25Mhz")
      (footprint "eagle-import:XTAL_TSX-3225_16.0000MF18X-AC3")
      (fields
        (field (name "LCSC_PART") "C2682775")
        (field (name "MF") "EPSON")
        (field (name "MP") "TSX-3225 16.0000MF18X-AC3")
      )
      (libsource (lib "eagle-import") (part "TSX-3225_16.0000MF18X-AC3"))
    )
    (comp (ref "C5")
      (value "1uF")
      (footprint "eagle-import:C0603K")
      (libsource (lib "eagle-import") (part "C-EUC0603K"))
    )
    (comp (ref "C20")
      (value "8.2nF")
      (footprint "eagle-import:C0603K")
      (libsource (lib "eagle-import") (part "C-EUC0603K"))
    )
    (comp (ref "C67")
      (value "100nF")
      (footprint "eagle-import:C0603K")
      (libsource (lib "eagle-import") (part "C-EUC0603K"))
    )
    (comp (ref "C68")
      (value "100nF")
      (footprint "eagle-import:C0603K")
      (libsource (lib "eagle-import") (part "C-EUC0603K"))
    )
    (comp (ref "C70")
      (value "100nF")
      (footprint "eagle-import:C0402")
      (libsource (lib "eagle-import") (part "C-EUC0402"))
    )
    (comp (ref "C71")
      (value "100nF")
      (footprint "eagle-import:C0402")
      (libsource (lib "eagle-import") (part "C-EUC0402"))
    )
    (comp (ref "C95")
      (value "100nF")
      (footprint "eagle-import:C0603K")
      (libsource (lib "eagle-import") (part "C-EUC0603K"))
    )
    (comp (ref "C96")
      (value "100nF")
      (footprint "eagle-import:C0402")
      (libsource (lib "eagle-import") (part "C-EUC0402"))
    )
    (comp (ref "C107_N0")
      (value "100nF")
      (footprint "eagle-import:C0402")
      (libsource (lib "eagle-import") (part "C-EUC0402"))
    )
    (comp (ref "C107_N1")
      (value "100nF")
      (footprint "eagle-import:C0402")
      (libsource (lib "eagle-import") (part "C-EUC0402"))
    )
    (comp (ref "C107_N2")
      (value "100nF")
      (footprint "eagle-import:C0402")
      (libsource (lib "eagle-import") (part "C-EUC0402"))
    )
    (comp (ref "C107_N3")
      (value "100nF")
      (footprint "eagle-import:C0402")
      (libsource (lib "eagle-import") (part "C-EUC0402"))
    )
    (comp (ref "D15_TR1")
      (value "GRN")
      (footprint "eagle-import:CHIP-LED0603")
      (libsource (lib "eagle-import") (part "LEDCHIP-LED0603"))
    )
    (comp (ref "D15_TR2")
      (value "GRN")
      (footprint "eagle-import:CHIP-LED0603")
      (libsource (lib "eagle-import") (part "LEDCHIP-LED0603"))
    )
    (comp (ref "D30_RL1")
      (value "B5819W")
      (footprint "eagle-import:SOD123FL")
      (fields (field (name "MF") "Microdiode Electronics"))
      (libsource (lib "eagle-import") (part "B5819W"))
    )
    (comp (ref "D30_RL2")
      (value "B5819W")
      (footprint "eagle-import:SOD123FL")
      (fields (field (name "MF") "Microdiode Electronics"))
      (libsource (lib "eagle-import") (part "B5819W"))
    )
    (comp (ref "D31_TR1")
      (value "B5819W")
      (footprint "eagle-import:SOD123FL")
      (fields (field (name "MF") "Microdiode Electronics"))
      (libsource (lib "eagle-import") (part "B5819W"))
    )
    (comp (ref "D31_TR2")
      (value "B5819W")
      (footprint "eagle-import:SOD123FL")
      (fields (field (name "MF") "Microdiode Electronics"))
      (libsource (lib "eagle-import") (part "B5819W"))
    )
    (comp (ref "D33")
      (value "BLUE")
      (footprint "eagle-import:CHIP-LED0603")
      (libsource (lib "eagle-import") (part "LEDCHIP-LED0603"))
    )
    (comp (ref "D34")
      (value "BLUE")
      (footprint "eagle-import:CHIP-LED0603")
      (libsource (lib "eagle-import") (part "LEDCHIP-LED0603"))
    )
    (comp (ref "D37")
      (value "GRN")
      (footprint "eagle-import:CHIP-LED0603")
      (libsource (lib "eagle-import") (part "LEDCHIP-LED0603"))
    )
    (comp (ref "D38")
      (value "RED")
      (footprint "eagle-import:CHIP-LED0603")
      (libsource (lib "eagle-import") (part "LEDCHIP-LED0603"))
    )
    (comp (ref "D43_RL1")
      (value "GRN")
      (footprint "eagle-import:CHIP-LED0603")
      (libsource (lib "eagle-import") (part "LEDCHIP-LED0603"))
    )
    (comp (ref "D43_RL2")
      (value "GRN")
      (footprint "eagle-import:CHIP-LED0603")
      (libsource (lib "eagle-import") (part "LEDCHIP-LED0603"))
    )
    (comp (ref "F1_RL1")
      (value "24V 460mA")
      (footprint "eagle-import:1206L")
      (fields (field (name "MF") "Littelfuse") (field (name "MPN") "1206L050"))
      (libsource (lib "eagle-import") (part "?1206L050"))
    )
    (comp (ref "F1_RL2")
      (value "24V 460mA")
      (footprint "eagle-import:1206L")
      (fields (field (name "MF") "Littelfuse") (field (name "MPN") "1206L050"))
      (libsource (lib "eagle-import") (part "?1206L050"))
    )
    (comp (ref "F2_TR1")
      (value "24V 460mA")
      (footprint "eagle-import:1206L")
      (fields (field (name "MF") "Littelfuse") (field (name "MPN") "1206L050"))
      (libsource (lib "eagle-import") (part "?1206L050"))
    )
    (comp (ref "F2_TR2")
      (value "24V 460mA")
      (footprint "eagle-import:1206L")
      (fields (field (name "MF") "Littelfuse") (field (name "MPN") "1206L050"))
      (libsource (lib "eagle-import") (part "?1206L050"))
    )
    (comp (ref "J13")
      (value "WJ15EDGK-3.81-2P")
      (footprint "eagle-import:DB2EVC-3.81-2P-GN")
      (fields (field (name "MF") "Würth Elektronik") (field (name "MP") "691321300002"))
      (libsource (lib "eagle-import") (part "DB2EVC-3.81-2P-GN"))
    )
    (comp (ref "J17")
      (value "WJ15EDGK-3.81-2P")
      (footprint "eagle-import:DB2EVC-3.81-2P-GN")
      (fields (field (name "MF") "Würth Elektronik") (field (name "MP") "691321300002"))
      (libsource (lib "eagle-import") (part "DB2EVC-3.81-2P-GN"))
    )
    (comp (ref "J18")
      (value "B3B-XH-A(LF)(SN)")
      (footprint "eagle-import:JST_B3B-XH-A(LF)(SN)")
      (fields (field (name "MF") "JST Sales"))
      (libsource (lib "eagle-import") (part "B3B-XH-A(LF)(SN)"))
    )
    (comp (ref "J21")
      (value "B3B-XH-A(LF)(SN)")
      (footprint "eagle-import:JST_B3B-XH-A(LF)(SN)")
      (fields (field (name "MF") "JST Sales"))
      (libsource (lib "eagle-import") (part "B3B-XH-A(LF)(SN)"))
    )
    (comp (ref "K1_TR1")
      (value "TLP3109A")
      (footprint "eagle-import:TLP3109A")
      (fields (field (name "MANUFACTURER") "Toshiba Semiconductor"))
      (libsource (lib "eagle-import") (part "TLP3109A"))
    )
    (comp (ref "K1_TR2")
      (value "TLP3109A")
      (footprint "eagle-import:TLP3109A")
      (fields (field (name "MANUFACTURER") "Toshiba Semiconductor"))
      (libsource (lib "eagle-import") (part "TLP3109A"))
    )
    (comp (ref "P5")
      (value "Header 2")
      (footprint "eagle-import:1X02")
      (libsource (lib "eagle-import") (part "PINHD-1X2"))
    )
    (comp (ref "P8")
      (value "DNI")
      (footprint "eagle-import:1X05")
      (libsource (lib "eagle-import") (part "PINHD-1X5"))
    )
    (comp (ref "P9")
      (value "DNI")
      (footprint "eagle-import:1X04")
      (libsource (lib "eagle-import") (part "PINHD-1X4"))
    )
    (comp (ref "P11")
      (value "SHROUDED_BOX_HEADER_40")
      (footprint "eagle-import:SHROUDED_BOX_HEADER_40")
      (libsource (lib "eagle-import") (part "SHROUDED_BOX_HEADER_40"))
    )
    (comp (ref "P18_RL1")
      (value "WJ15EDGK-3.81-2P")
      (footprint "eagle-import:DB2EVC-3.81-2P-GN")
      (fields (field (name "MF") "Würth Elektronik") (field (name "MP") "691321300002"))
      (libsource (lib "eagle-import") (part "DB2EVC-3.81-2P-GN"))
    )
    (comp (ref "P18_RL2")
      (value "WJ15EDGK-3.81-2P")
      (footprint "eagle-import:DB2EVC-3.81-2P-GN")
      (fields (field (name "MF") "Würth Elektronik") (field (name "MP") "691321300002"))
      (libsource (lib "eagle-import") (part "DB2EVC-3.81-2P-GN"))
    )
    (comp (ref "P19")
      (value "WJ15EDGK-3.81-2P")
      (footprint "eagle-import:DB2EVC-3.81-2P-GN")
      (fields (field (name "MF") "Würth Elektronik") (field (name "MP") "691321300002"))
      (libsource (lib "eagle-import") (part "DB2EVC-3.81-2P-GN"))
    )
    (comp (ref "P20")
      (value "SHROUDED_BOX_HEADER_08")
      (footprint "eagle-import:SHROUDED_BOX_HEADER_08")
      (libsource (lib "eagle-import") (part "SHROUDED_BOX_HEADER_08"))
    )
    (comp (ref "P21_TR1")
      (value "WJ15EDGK-3.81-2P")
      (footprint "eagle-import:DB2EVC-3.81-2P-GN")
      (fields (field (name "MF") "Würth Elektronik") (field (name "MP") "691321300002"))
      (libsource (lib "eagle-import") (part "DB2EVC-3.81-2P-GN"))
    )
    (comp (ref "P21_TR2")
      (value "WJ15EDGK-3.81-2P")
      (footprint "eagle-import:DB2EVC-3.81-2P-GN")
      (fields (field (name "MF") "Würth Elektronik") (field (name "MP") "691321300002"))
      (libsource (lib "eagle-import") (part "DB2EVC-3.81-2P-GN"))
    )
    (comp (ref "Q2_RL1")
      (value "ST3422A")
      (footprint "eagle-import:SOT-23")
      (libsource (lib "eagle-import") (part "ST3422A"))
    )
    (comp (ref "Q2_RL2")
      (value "ST3422A")
      (footprint "eagle-import:SOT-23")
      (libsource (lib "eagle-import") (part "ST3422A"))
    )
    (comp (ref "Q6")
      (value "2N7002-7-F")
      (footprint "eagle-import:SOT-23")
      (libsource (lib "eagle-import") (part "2N7002-7-F"))
    )
    (comp (ref "Q7")
      (value "2N7002-7-F")
      (footprint "eagle-import:SOT-23")
      (libsource (lib "eagle-import") (part "2N7002-7-F"))
    )
    (comp (ref "Q8")
      (value "2N7002-7-F")
      (footprint "eagle-import:SOT-23")
      (libsource (lib "eagle-import") (part "2N7002-7-F"))
    )
    (comp (ref "Q9_TR1")
      (value "2N7002-7-F")
      (footprint "eagle-import:SOT-23")
      (libsource (lib "eagle-import") (part "2N7002-7-F"))
    )
    (comp (ref "Q9_TR2")
      (value "2N7002-7-F")
      (footprint "eagle-import:SOT-23")
      (libsource (lib "eagle-import") (part "2N7002-7-F"))
    )
    (comp (ref "Q10_RL1")
      (value "2N7002-7-F")
      (footprint "eagle-import:SOT-23")
      (libsource (lib "eagle-import") (part "2N7002-7-F"))
    )
    (comp (ref "Q10_RL2")
      (value "2N7002-7-F")
      (footprint "eagle-import:SOT-23")
      (libsource (lib "eagle-import") (part "2N7002-7-F"))
    )
    (comp (ref "R28")
      (value "200R")
      (footprint "eagle-import:R0402")
      (libsource (lib "eagle-import") (part "R-EU_R0402"))
    )
    (comp (ref "R33_TR1")
      (value "4K7")
      (footprint "eagle-import:R0402")
      (libsource (lib "eagle-import") (part "R-EU_R0402"))
    )
    (comp (ref "R33_TR2")
      (value "4K7")
      (footprint "eagle-import:R0402")
      (libsource (lib "eagle-import") (part "R-EU_R0402"))
    )
    (comp (ref "R39_TR1")
      (value "1K5")
      (footprint "eagle-import:R0402")
      (libsource (lib "eagle-import") (part "R-EU_R0402"))
    )
    (comp (ref "R39_TR2")
      (value "1K5")
      (footprint "eagle-import:R0402")
      (libsource (lib "eagle-import") (part "R-EU_R0402"))
    )
    (comp (ref "R58")
      (value "5K1")
      (footprint "eagle-import:R0402")
      (libsource (lib "eagle-import") (part "R-EU_R0402"))
    )
    (comp (ref "R59")
      (value "510R")
      (footprint "eagle-import:R0402")
      (libsource (lib "eagle-import") (part "R-EU_R0402"))
    )
    (comp (ref "R60")
      (value "2k2")
      (footprint "eagle-import:R0402")
      (libsource (lib "eagle-import") (part "R-EU_R0402"))
    )
    (comp (ref "R77_AO0")
      (value "10K")
      (footprint "eagle-import:R0402")
      (libsource (lib "eagle-import") (part "R-EU_R0402"))
    )
    (comp (ref "R77_AO1")
      (value "10K")
      (footprint "eagle-import:R0402")
      (libsource (lib "eagle-import") (part "R-EU_R0402"))
    )
    (comp (ref "R77_AO2")
      (value "10K")
      (footprint "eagle-import:R0402")
      (libsource (lib "eagle-import") (part "R-EU_R0402"))
    )
    (comp (ref "R77_AO3")
      (value "10K")
      (footprint "eagle-import:R0402")
      (libsource (lib "eagle-import") (part "R-EU_R0402"))
    )
    (comp (ref "R77_COO")
      (value "10K")
      (footprint "eagle-import:R0402")
      (libsource (lib "eagle-import") (part "R-EU_R0402"))
    )
    (comp (ref "R77_MIS")
      (value "10K")
      (footprint "eagle-import:R0402")
      (libsource (lib "eagle-import") (part "R-EU_R0402"))
    )
    (comp (ref "R89_RL1")
      (value "10K")
      (footprint "eagle-import:R0402")
      (libsource (lib "eagle-import") (part "R-EU_R0402"))
    )
    (comp (ref "R89_RL2")
      (value "10K")
      (footprint "eagle-import:R0402")
      (libsource (lib "eagle-import") (part "R-EU_R0402"))
    )
    (comp (ref "R96")
      (value "200R")
      (footprint "eagle-import:R0402")
      (libsource (lib "eagle-import") (part "R-EU_R0402"))
    )
    (comp (ref "R97")
      (value "200R")
      (footprint "eagle-import:R0603")
      (libsource (lib "eagle-import") (part "R-EU_R0603"))
    )
    (comp (ref "R98")
      (value "10K")
      (footprint "eagle-import:R0603")
      (libsource (lib "eagle-import") (part "R-EU_R0603"))
    )
    (comp (ref "R100")
      (value "DNI")
      (footprint "eagle-import:R0402")
      (libsource (lib "eagle-import") (part "R-EU_R0402"))
    )
    (comp (ref "R101")
      (value "0R")
      (footprint "eagle-import:R0402")
      (libsource (lib "eagle-import") (part "R-EU_R0402"))
    )
    (comp (ref "R105_RL1")
      (value "4K7")
      (footprint "eagle-import:R0402")
      (libsource (lib "eagle-import") (part "R-EU_R0402"))
    )
    (comp (ref "R105_RL2")
      (value "4K7")
      (footprint "eagle-import:R0402")
      (libsource (lib "eagle-import") (part "R-EU_R0402"))
    )
    (comp (ref "R109_RL1")
      (value "1K")
      (footprint "eagle-import:R0603")
      (libsource (lib "eagle-import") (part "R-EU_R0603"))
    )
    (comp (ref "R109_RL2")
      (value "1K")
      (footprint "eagle-import:R0603")
      (libsource (lib "eagle-import") (part "R-EU_R0603"))
    )
    (comp (ref "R110")
      (value "200R")
      (footprint "eagle-import:R0402")
      (libsource (lib "eagle-import") (part "R-EU_R0402"))
    )
    (comp (ref "R112")
      (value "200R")
      (footprint "eagle-import:R0402")
      (libsource (lib "eagle-import") (part "R-EU_R0402"))
    )
    (comp (ref "R113")
      (value "220R")
      (footprint "eagle-import:R0402")
      (libsource (lib "eagle-import") (part "R-EU_R0402"))
    )
    (comp (ref "R114")
      (value "220R")
      (footprint "eagle-import:R0402")
      (libsource (lib "eagle-import") (part "R-EU_R0402"))
    )
    (comp (ref "R115")
      (value "220R")
      (footprint "eagle-import:R0402")
      (libsource (lib "eagle-import") (part "R-EU_R0402"))
    )
    (comp (ref "R116")
      (value "220R")
      (footprint "eagle-import:R0603")
      (libsource (lib "eagle-import") (part "R-EU_R0603"))
    )
    (comp (ref "R117")
      (value "220R")
      (footprint "eagle-import:R0402")
      (libsource (lib "eagle-import") (part "R-EU_R0402"))
    )
    (comp (ref "R118")
      (value "220R")
      (footprint "eagle-import:R0402")
      (libsource (lib "eagle-import") (part "R-EU_R0402"))
    )
    (comp (ref "R119")
      (value "1K")
      (footprint "eagle-import:R0402")
      (libsource (lib "eagle-import") (part "R-EU_R0402"))
    )
    (comp (ref "R120")
      (value "510R")
      (footprint "eagle-import:R0402")
      (libsource (lib "eagle-import") (part "R-EU_R0402"))
    )
    (comp (ref "R121_AO0")
      (value "120R")
      (footprint "eagle-import:R0402")
      (libsource (lib "eagle-import") (part "R-EU_R0402"))
    )
    (comp (ref "R121_AO1")
      (value "120R")
      (footprint "eagle-import:R0402")
      (libsource (lib "eagle-import") (part "R-EU_R0402"))
    )
    (comp (ref "R121_AO2")
      (value "120R")
      (footprint "eagle-import:R0402")
      (libsource (lib "eagle-import") (part "R-EU_R0402"))
    )
    (comp (ref "R121_AO3")
      (value "120R")
      (footprint "eagle-import:R0402")
      (libsource (lib "eagle-import") (part "R-EU_R0402"))
    )
    (comp (ref "R121_COO")
      (value "120R")
      (footprint "eagle-import:R0402")
      (libsource (lib "eagle-import") (part "R-EU_R0402"))
    )
    (comp (ref "R121_MIS")
      (value "120R")
      (footprint "eagle-import:R0402")
      (libsource (lib "eagle-import") (part "R-EU_R0402"))
    )
    (comp (ref "R122_AO0")
      (value "220R")
      (footprint "eagle-import:R0402")
      (libsource (lib "eagle-import") (part "R-EU_R0402"))
    )
    (comp (ref "R122_AO1")
      (value "220R")
      (footprint "eagle-import:R0402")
      (libsource (lib "eagle-import") (part "R-EU_R0402"))
    )
    (comp (ref "R122_AO2")
      (value "220R")
      (footprint "eagle-import:R0402")
      (libsource (lib "eagle-import") (part "R-EU_R0402"))
    )
    (comp (ref "R122_AO3")
      (value "220R")
      (footprint "eagle-import:R0402")
      (libsource (lib "eagle-import") (part "R-EU_R0402"))
    )
    (comp (ref "R122_COO")
      (value "220R")
      (footprint "eagle-import:R0402")
      (libsource (lib "eagle-import") (part "R-EU_R0402"))
    )
    (comp (ref "R122_MIS")
      (value "220R")
      (footprint "eagle-import:R0402")
      (libsource (lib "eagle-import") (part "R-EU_R0402"))
    )
    (comp (ref "R123_N0")
      (value "1K")
      (footprint "eagle-import:R0402")
      (libsource (lib "eagle-import") (part "R-EU_R0402"))
    )
    (comp (ref "R123_N1")
      (value "1K")
      (footprint "eagle-import:R0402")
      (libsource (lib "eagle-import") (part "R-EU_R0402"))
    )
    (comp (ref "R123_N2")
      (value "1K")
      (footprint "eagle-import:R0402")
      (libsource (lib "eagle-import") (part "R-EU_R0402"))
    )
    (comp (ref "R123_N3")
      (value "1K")
      (footprint "eagle-import:R0402")
      (libsource (lib "eagle-import") (part "R-EU_R0402"))
    )
    (comp (ref "R124_N0")
      (value "510R")
      (footprint "eagle-import:R0402")
      (libsource (lib "eagle-import") (part "R-EU_R0402"))
    )
    (comp (ref "R124_N1")
      (value "510R")
      (footprint "eagle-import:R0402")
      (libsource (lib "eagle-import") (part "R-EU_R0402"))
    )
    (comp (ref "R124_N2")
      (value "510R")
      (footprint "eagle-import:R0402")
      (libsource (lib "eagle-import") (part "R-EU_R0402"))
    )
    (comp (ref "R124_N3")
      (value "510R")
      (footprint "eagle-import:R0402")
      (libsource (lib "eagle-import") (part "R-EU_R0402"))
    )
    (comp (ref "R155")
      (value "4K7")
      (footprint "eagle-import:R0402")
      (libsource (lib "eagle-import") (part "R-EU_R0402"))
    )
    (comp (ref "R156")
      (value "4K7")
      (footprint "eagle-import:R0402")
      (libsource (lib "eagle-import") (part "R-EU_R0402"))
    )
    (comp (ref "R157")
      (value "10K")
      (footprint "eagle-import:R0603")
      (libsource (lib "eagle-import") (part "R-EU_R0603"))
    )
    (comp (ref "R158")
      (value "10K")
      (footprint "eagle-import:R0603")
      (libsource (lib "eagle-import") (part "R-EU_R0603"))
    )
    (comp (ref "R160")
      (value "2K2")
      (footprint "eagle-import:R0402")
      (libsource (lib "eagle-import") (part "R-EU_R0402"))
    )
    (comp (ref "R161")
      (value "2K2")
      (footprint "eagle-import:R0402")
      (libsource (lib "eagle-import") (part "R-EU_R0402"))
    )
    (comp (ref "R170")
      (value "4K7")
      (footprint "eagle-import:R0402")
      (libsource (lib "eagle-import") (part "R-EU_R0402"))
    )
    (comp (ref "R171")
      (value "4K7")
      (footprint "eagle-import:R0402")
      (libsource (lib "eagle-import") (part "R-EU_R0402"))
    )
    (comp (ref "R172")
      (value "4K7")
      (footprint "eagle-import:R0402")
      (libsource (lib "eagle-import") (part "R-EU_R0402"))
    )
    (comp (ref "R174_TR1")
      (value "10K")
      (footprint "eagle-import:R0402")
      (libsource (lib "eagle-import") (part "R-EU_R0402"))
    )
    (comp (ref "R174_TR2")
      (value "10K")
      (footprint "eagle-import:R0402")
      (libsource (lib "eagle-import") (part "R-EU_R0402"))
    )
    (comp (ref "U14")
      (value "ADUM1200ARZ-RL7")
      (footprint "eagle-import:SOIC127P600X175-8N")
      (fields (field (name "MF") "Analog Devices") (field (name "MP") "ADUM1200ARZRL7"))
      (libsource (lib "eagle-import") (part "ADUM1200ARZ-RL7"))
    )
    (comp (ref "U20")
      (value "CBMUD1201LAS8")
      (footprint "eagle-import:SOIC-8")
      (libsource (lib "eagle-import") (part "CBMUD1201LAS8"))
    )
    (comp (ref "U28")
      (value "WS2812B")
      (footprint "eagle-import:WS2812B")
      (libsource (lib "eagle-import") (part "WS2812B"))
    )
    (comp (ref "U29")
      (value "EL357N-G")
      (footprint "eagle-import:OPTO_EL357N-G")
      (fields (field (name "MF") "Everlight Electronics"))
      (libsource (lib "eagle-import") (part "EL357N-G"))
    )
    (comp (ref "U30")
      (value "EL357N-G")
      (footprint "eagle-import:OPTO_EL357N-G")
      (fields (field (name "MF") "Everlight Electronics"))
      (libsource (lib "eagle-import") (part "EL357N-G"))
    )
    (comp (ref "U31")
      (value "EL357N-G")
      (footprint "eagle-import:OPTO_EL357N-G")
      (fields (field (name "MF") "Everlight Electronics"))
      (libsource (lib "eagle-import") (part "EL357N-G"))
    )
    (comp (ref "U32")
      (value "EL357N-G")
      (footprint "eagle-import:OPTO_EL357N-G")
      (fields (field (name "MF") "Everlight Electronics"))
      (libsource (lib "eagle-import") (part "EL357N-G"))
    )
    (comp (ref "U33_AO0")
      (value "EL357N-G")
      (footprint "eagle-import:OPTO_EL357N-G")
      (fields (field (name "MF") "Everlight Electronics"))
      (libsource (lib "eagle-import") (part "EL357N-G"))
    )
    (comp (ref "U33_AO1")
      (value "EL357N-G")
      (footprint "eagle-import:OPTO_EL357N-G")
      (fields (field (name "MF") "Everlight Electronics"))
      (libsource (lib "eagle-import") (part "EL357N-G"))
    )
    (comp (ref "U33_AO2")
      (value "EL357N-G")
      (footprint "eagle-import:OPTO_EL357N-G")
      (fields (field (name "MF") "Everlight Electronics"))
      (libsource (lib "eagle-import") (part "EL357N-G"))
    )
    (comp (ref "U33_AO3")
      (value "EL357N-G")
      (footprint "eagle-import:OPTO_EL357N-G")
      (fields (field (name "MF") "Everlight Electronics"))
      (libsource (lib "eagle-import") (part "EL357N-G"))
    )
    (comp (ref "U33_COO")
      (value "EL357N-G")
      (footprint "eagle-import:OPTO_EL357N-G")
      (fields (field (name "MF") "Everlight Electronics"))
      (libsource (lib "eagle-import") (part "EL357N-G"))
    )
    (comp (ref "U33_MIS")
      (value "EL357N-G")
      (footprint "eagle-import:OPTO_EL357N-G")
      (fields (field (name "MF") "Everlight Electronics"))
      (libsource (lib "eagle-import") (part "EL357N-G"))
    )
    (comp (ref "U34_N0")
      (value "EL357N-G")
      (footprint "eagle-import:OPTO_EL357N-G")
      (fields (field (name "MF") "Everlight Electronics"))
      (libsource (lib "eagle-import") (part "EL357N-G"))
    )
    (comp (ref "U34_N1")
      (value "EL357N-G")
      (footprint "eagle-import:OPTO_EL357N-G")
      (fields (field (name "MF") "Everlight Electronics"))
      (libsource (lib "eagle-import") (part "EL357N-G"))
    )
    (comp (ref "U34_N2")
      (value "EL357N-G")
      (footprint "eagle-import:OPTO_EL357N-G")
      (fields (field (name "MF") "Everlight Electronics"))
      (libsource (lib "eagle-import") (part "EL357N-G"))
    )
    (comp (ref "U34_N3")
      (value "EL357N-G")
      (footprint "eagle-import:OPTO_EL357N-G")
      (fields (field (name "MF") "Everlight Electronics"))
      (libsource (lib "eagle-import") (part "EL357N-G"))
    )
    (comp (ref "D27")
      (value "USBLC6-2SC6")
      (footprint "eagle-import:SOT95P280X145-6N")
      (fields (field (name "MF") "STMicroelectronics"))
      (libsource (lib "eagle-import") (part "USBLC6-2SC6"))
    )
    (comp (ref "J20")
      (value "USB-C-Socket")
      (footprint "eagle-import:USB-C-16P")
      (libsource (lib "eagle-import") (part "USB_C16PIN"))
    )
    (comp (ref "L13")
      (value "DLW21HN900SQ2L")
      (footprint "eagle-import:FIL_DLW21HN900SQ2L")
      (fields (field (name "MF") "Murata"))
      (libsource (lib "eagle-import") (part "DLW21HN900SQ2L"))
    )
    (comp (ref "R107")
      (value "4K7")
      (footprint "eagle-import:R0402")
      (libsource (lib "eagle-import") (part "R-EU_R0402"))
    )
    (comp (ref "R108")
      (value "4K7")
      (footprint "eagle-import:R0402")
      (libsource (lib "eagle-import") (part "R-EU_R0402"))
    )
    (comp (ref "C7")
      (value "4.7uF")
      (footprint "eagle-import:C0603")
      (libsource (lib "eagle-import") (part "C-EUC0603"))
    )
    (comp (ref "C8")
      (value "22uF")
      (footprint "eagle-import:C0603")
      (fields (field (name "LCSC_PART") "C576517"))
      (libsource (lib "eagle-import") (part "C-EUC0603"))
    )
    (comp (ref "C9")
      (value "1uF")
      (footprint "eagle-import:C0603")
      (fields (field (name "LCSC_PART") "C576517"))
      (libsource (lib "eagle-import") (part "C-EUC0603"))
    )
    (comp (ref "C134")
      (value "100nF")
      (footprint "eagle-import:C0603")
      (fields (field (name "LCSC_PART") "C576517"))
      (libsource (lib "eagle-import") (part "C-EUC0603"))
    )
    (comp (ref "C135")
      (value "100nF")
      (footprint "eagle-import:C0603")
      (fields (field (name "LCSC_PART") "C576517"))
      (libsource (lib "eagle-import") (part "C-EUC0603"))
    )
    (comp (ref "D1")
      (value "ZMM3V3-M")
      (footprint "eagle-import:LL-34")
      (fields (field (name "MF") "STMicroelectronics") (field (name "MP") "LL4148ST"))
      (libsource (lib "eagle-import") (part "ZMM3V3-M"))
    )
    (comp (ref "D16")
      (value "SM712")
      (footprint "eagle-import:SOT23")
      (fields (field (name "MF") "Semtech"))
      (libsource (lib "eagle-import") (part "SM712"))
    )
    (comp (ref "D17")
      (value "RED")
      (footprint "eagle-import:CHIP-LED0603")
      (libsource (lib "eagle-import") (part "LEDCHIP-LED0603"))
    )
    (comp (ref "D18")
      (value "GREEN")
      (footprint "eagle-import:CHIP-LED0603")
      (libsource (lib "eagle-import") (part "LEDCHIP-LED0603"))
    )
    (comp (ref "D40")
      (value "ZMM5V6-M")
      (footprint "eagle-import:LL-34")
      (fields (field (name "MF") "STMicroelectronics") (field (name "MP") "LL4148ST"))
      (libsource (lib "eagle-import") (part "ZMM3V3-M"))
    )
    (comp (ref "J10")
      (value "DB2EVC-3.81-4P-GN")
      (footprint "eagle-import:DB2EVC-3.81-4P-GN")
      (fields (field (name "MF") "Phoenix Contact") (field (name "MP") "1803439"))
      (libsource (lib "eagle-import") (part "DB2EVC-3.81-4P-GN"))
    )
    (comp (ref "J12")
      (value "KH-PCB-6P6C")
      (footprint "eagle-import:KH-PCB-6P6C")
      (fields (field (name "MF") "Same Sky") (field (name "MP") "CRJ030-G-TH"))
      (libsource (lib "eagle-import") (part "KH-PCB-6P6C"))
    )
    (comp (ref "L1")
      (value "150mΩ ±25% 220Ω@100MHz 0805 Ferrite Beads ROHS")
      (footprint "eagle-import:FB805")
      (fields (field (name "LCSC_PART") "C139188"))
      (libsource (lib "eagle-import") (part "FERRITE-0805"))
    )
    (comp (ref "L2")
      (value "150mΩ ±25% 220Ω@100MHz 0805 Ferrite Beads ROHS")
      (footprint "eagle-import:FB805")
      (fields (field (name "LCSC_PART") "C139188"))
      (libsource (lib "eagle-import") (part "FERRITE-0805"))
    )
    (comp (ref "R44")
      (value "200R")
      (footprint "eagle-import:R0402")
      (libsource (lib "eagle-import") (part "R-EU_R0402"))
    )
    (comp (ref "R45")
      (value "200R")
      (footprint "eagle-import:R0402")
      (libsource (lib "eagle-import") (part "R-EU_R0402"))
    )
    (comp (ref "R46")
      (value "560R")
      (footprint "eagle-import:R0402")
      (libsource (lib "eagle-import") (part "R-EU_R0402"))
    )
    (comp (ref "R47")
      (value "2K")
      (footprint "eagle-import:R0402")
      (libsource (lib "eagle-import") (part "R-EU_R0402"))
    )
    (comp (ref "R48")
      (value "560R")
      (footprint "eagle-import:R0402")
      (libsource (lib "eagle-import") (part "R-EU_R0402"))
    )
    (comp (ref "R49")
      (value "130R")
      (footprint "eagle-import:R0402")
      (libsource (lib "eagle-import") (part "R-EU_R0402"))
    )
    (comp (ref "R50")
      (value "200R")
      (footprint "eagle-import:R0402")
      (libsource (lib "eagle-import") (part "R-EU_R0402"))
    )
    (comp (ref "R51")
      (value "220R")
      (footprint "eagle-import:R0402")
      (libsource (lib "eagle-import") (part "R-EU_R0402"))
    )
    (comp (ref "R52")
      (value "2K")
      (footprint "eagle-import:R0402")
      (libsource (lib "eagle-import") (part "R-EU_R0402"))
    )
    (comp (ref "R53")
      (value "2K")
      (footprint "eagle-import:R0402")
      (libsource (lib "eagle-import") (part "R-EU_R0402"))
    )
    (comp (ref "R54")
      (value "2K")
      (footprint "eagle-import:R0402")
      (libsource (lib "eagle-import") (part "R-EU_R0402"))
    )
    (comp (ref "U12")
      (value "CBMUD1201LAS8")
      (footprint "eagle-import:SOIC-8")
      (libsource (lib "eagle-import") (part "CBMUD1201LAS8"))
    )
    (comp (ref "U13")
      (value "SN75176BDR")
      (footprint "eagle-import:SOIC127P599X175-8N")
      (fields (field (name "MF") "Texas Instruments"))
      (libsource (lib "eagle-import") (part "SN75176BDR"))
    )
    (comp (ref "U15")
      (value "EL357N-G")
      (footprint "eagle-import:OPTO_EL357N-G")
      (fields (field (name "MF") "Everlight Electronics"))
      (libsource (lib "eagle-import") (part "EL357N-G"))
    )
    (comp (ref "C10")
      (value "100nF")
      (footprint "eagle-import:C0402")
      (fields (field (name "LCSC_PART") "C576517"))
      (libsource (lib "eagle-import") (part "C-EUC0402"))
    )
    (comp (ref "C11")
      (value "10uF")
      (footprint "eagle-import:C1206")
      (fields (field (name "LCSC_PART") "C576517"))
      (libsource (lib "eagle-import") (part "C-EUC1206"))
    )
    (comp (ref "C12")
      (value "10uF")
      (footprint "eagle-import:C1206")
      (fields (field (name "LCSC_PART") "C576517"))
      (libsource (lib "eagle-import") (part "C-EUC1206"))
    )
    (comp (ref "C13")
      (value "22uF")
      (footprint "eagle-import:C0805")
      (fields (field (name "LCSC_PART") "C576517"))
      (libsource (lib "eagle-import") (part "C-EUC0805"))
    )
    (comp (ref "C14")
      (value "10uF")
      (footprint "eagle-import:C1206")
      (fields (field (name "LCSC_PART") "C576517"))
      (libsource (lib "eagle-import") (part "C-EUC1206"))
    )
    (comp (ref "C15")
      (value "10uF")
      (footprint "eagle-import:C1206")
      (fields (field (name "LCSC_PART") "C576517"))
      (libsource (lib "eagle-import") (part "C-EUC1206"))
    )
    (comp (ref "C16")
      (value "10nF")
      (footprint "eagle-import:C0402")
      (fields (field (name "LCSC_PART") "C576517"))
      (libsource (lib "eagle-import") (part "C-EUC0402"))
    )
    (comp (ref "C17")
      (value "10pF")
      (footprint "eagle-import:C0603")
      (fields (field (name "LCSC_PART") "C576517"))
      (libsource (lib "eagle-import") (part "C-EUC0603"))
    )
    (comp (ref "C18")
      (value "8.2nF")
      (footprint "eagle-import:C0603")
      (fields (field (name "LCSC_PART") "C576517"))
      (libsource (lib "eagle-import") (part "C-EUC0603"))
    )
    (comp (ref "C19")
      (value "8.2nF")
      (footprint "eagle-import:C0603")
      (fields (field (name "LCSC_PART") "C576517"))
      (libsource (lib "eagle-import") (part "C-EUC0603"))
    )
    (comp (ref "C52")
      (value "22uF")
      (footprint "eagle-import:C0805")
      (fields (field (name "LCSC_PART") "C576517"))
      (libsource (lib "eagle-import") (part "C-EUC0805"))
    )
    (comp (ref "C53")
      (value "22uF")
      (footprint "eagle-import:C0805")
      (fields (field (name "LCSC_PART") "C576517"))
      (libsource (lib "eagle-import") (part "C-EUC0805"))
    )
    (comp (ref "C54")
      (value "4.7uF")
      (footprint "eagle-import:C0603")
      (libsource (lib "eagle-import") (part "C-EUC0603"))
    )
    (comp (ref "C55")
      (value "22uF")
      (footprint "eagle-import:C0603")
      (fields (field (name "LCSC_PART") "C576517"))
      (libsource (lib "eagle-import") (part "C-EUC0603"))
    )
    (comp (ref "C56")
      (value "100uF")
      (footprint "eagle-import:CAPMP3528X210N")
      (fields (field (name "MF") "KEMET") (field (name "MP") "T543B337K2R5AHW035"))
      (libsource (lib "eagle-import") (part "C-3528"))
    )
    (comp (ref "C57")
      (value "100uF")
      (footprint "eagle-import:SANYO-OSCON_SMD_C6")
      (libsource (lib "eagle-import") (part "CPOL-USSANYO_SMD_C6"))
    )
    (comp (ref "C58")
      (value "10uF")
      (footprint "eagle-import:C1206")
      (fields (field (name "LCSC_PART") "C576517"))
      (libsource (lib "eagle-import") (part "C-EUC1206"))
    )
    (comp (ref "C59")
      (value "10uF")
      (footprint "eagle-import:C1206")
      (fields (field (name "LCSC_PART") "C576517"))
      (libsource (lib "eagle-import") (part "C-EUC1206"))
    )
    (comp (ref "C69")
      (value "100nF 100v")
      (footprint "eagle-import:C0805")
      (fields (field (name "LCSC_PART") "C576517"))
      (libsource (lib "eagle-import") (part "C-EUC0805"))
    )
    (comp (ref "C74")
      (value "10uF 100V")
      (footprint "eagle-import:C0603")
      (fields (field (name "LCSC_PART") "C576517"))
      (libsource (lib "eagle-import") (part "C-EUC0603"))
    )
    (comp (ref "C75")
      (value "2.2uF")
      (footprint "eagle-import:C1206")
      (fields (field (name "LCSC_PART") "C576517"))
      (libsource (lib "eagle-import") (part "C-EUC1206"))
    )
    (comp (ref "C76")
      (value "100nF 100v")
      (footprint "eagle-import:C0805")
      (fields (field (name "LCSC_PART") "C576517"))
      (libsource (lib "eagle-import") (part "C-EUC0805"))
    )
    (comp (ref "C77")
      (value "10uF")
      (footprint "eagle-import:C1206")
      (libsource (lib "eagle-import") (part "C-EUC1206"))
    )
    (comp (ref "C78")
      (value "10uF")
      (footprint "eagle-import:C1206")
      (libsource (lib "eagle-import") (part "C-EUC1206"))
    )
    (comp (ref "C79")
      (value "10uF")
      (footprint "eagle-import:C1206")
      (libsource (lib "eagle-import") (part "C-EUC1206"))
    )
    (comp (ref "C80")
      (value "10uF")
      (footprint "eagle-import:C1206")
      (libsource (lib "eagle-import") (part "C-EUC1206"))
    )
    (comp (ref "C81")
      (value "100nF 100v")
      (footprint "eagle-import:C0603")
      (fields (field (name "LCSC_PART") "C576517"))
      (libsource (lib "eagle-import") (part "C-EUC0603"))
    )
    (comp (ref "C83")
      (value "1.5nF")
      (footprint "eagle-import:C0603")
      (fields (field (name "LCSC_PART") "C576517"))
      (libsource (lib "eagle-import") (part "C-EUC0603"))
    )
    (comp (ref "C84")
      (value "5.6pF")
      (footprint "eagle-import:C0402")
      (fields (field (name "LCSC_PART") "C576517"))
      (libsource (lib "eagle-import") (part "C-EUC0402"))
    )
    (comp (ref "C85")
      (value "8.2nF")
      (footprint "eagle-import:C0603")
      (fields (field (name "LCSC_PART") "C576517"))
      (libsource (lib "eagle-import") (part "C-EUC0603"))
    )
    (comp (ref "C86")
      (value "220pF")
      (footprint "eagle-import:C0603")
      (fields (field (name "LCSC_PART") "C576517"))
      (libsource (lib "eagle-import") (part "C-EUC0603"))
    )
    (comp (ref "C89")
      (value "10uF")
      (footprint "eagle-import:C1206")
      (libsource (lib "eagle-import") (part "C-EUC1206"))
    )
    (comp (ref "C90")
      (value "10uF")
      (footprint "eagle-import:C1206")
      (libsource (lib "eagle-import") (part "C-EUC1206"))
    )
    (comp (ref "C113")
      (value "100nF")
      (footprint "eagle-import:C0603")
      (fields (field (name "LCSC_PART") "C576517"))
      (libsource (lib "eagle-import") (part "C-EUC0603"))
    )
    (comp (ref "C115")
      (value "10uF 100V")
      (footprint "eagle-import:C1210")
      (fields (field (name "LCSC_PART") "C576517"))
      (libsource (lib "eagle-import") (part "C-EUC1210"))
    )
    (comp (ref "C144")
      (value "10uF 100V")
      (footprint "eagle-import:C0805")
      (fields (field (name "LCSC_PART") "C576517"))
      (libsource (lib "eagle-import") (part "C-EUC0805"))
    )
    (comp (ref "C145")
      (value "10uF 100V")
      (footprint "eagle-import:C0805")
      (fields (field (name "LCSC_PART") "C576517"))
      (libsource (lib "eagle-import") (part "C-EUC0805"))
    )
    (comp (ref "D14")
      (value "SS210")
      (footprint "eagle-import:DO-214AC")
      (fields (field (name "LCSC_PART") "C14996"))
      (libsource (lib "eagle-import") (part "dp_devices.v6_DIODE-DO-214AC"))
    )
    (comp (ref "D19")
      (value "SS54")
      (footprint "eagle-import:DO-214AC")
      (fields (field (name "LCSC_PART") "C14996"))
      (libsource (lib "eagle-import") (part "dp_devices.v6_DIODE-DO-214AC"))
    )
    (comp (ref "D20")
      (value "GREEN")
      (footprint "eagle-import:CHIP-LED0603")
      (libsource (lib "eagle-import") (part "LEDCHIP-LED0603"))
    )
    (comp (ref "D23")
      (value "1SMAF4734A")
      (footprint "eagle-import:SMAF-ZDIODE")
      (fields (field (name "MF") "ON Semiconductor") (field (name "MP") "1SMA5927BT3G"))
      (libsource (lib "eagle-import") (part "SMAF-ZDIODE"))
    )
    (comp (ref "D24")
      (value "GREEN")
      (footprint "eagle-import:CHIP-LED0603")
      (libsource (lib "eagle-import") (part "LEDCHIP-LED0603"))
    )
    (comp (ref "D32")
      (value "RED")
      (footprint "eagle-import:CHIP-LED0805")
      (libsource (lib "eagle-import") (part "LEDCHIP-LED0805"))
    )
    (comp (ref "J19")
      (value "DNI")
      (footprint "eagle-import:1X02")
      (libsource (lib "eagle-import") (part "PINHD-1X2"))
    )
    (comp (ref "L3")
      (value "22uH")
      (footprint "eagle-import:YSPI0630A-220M")
      (fields (field (name "MF") "Abracon") (field (name "MP") "AMPLA7030S220MT"))
      (libsource (lib "eagle-import") (part "YSPI0630A-220M"))
    )
    (comp (ref "L5")
      (value "68uH")
      (footprint "eagle-import:DR125")
      (libsource (lib "eagle-import") (part "DR125"))
    )
    (comp (ref "L7")
      (value "150mΩ ±25% 220Ω@100MHz 0805 Ferrite Beads ROHS")
      (footprint "eagle-import:FB402")
      (fields (field (name "LCSC_PART") "C139188"))
      (libsource (lib "eagle-import") (part "FERRITE-0402"))
    )
    (comp (ref "L8")
      (value "150mΩ ±25% 220Ω@100MHz 0805 Ferrite Beads ROHS")
      (footprint "eagle-import:FB805")
      (fields (field (name "LCSC_PART") "C139188"))
      (libsource (lib "eagle-import") (part "FERRITE-0805"))
    )
    (comp (ref "L9")
      (value "150mΩ ±25% 220Ω@100MHz 0805 Ferrite Beads ROHS")
      (footprint "eagle-import:FB805")
      (fields (field (name "LCSC_PART") "C139188"))
      (libsource (lib "eagle-import") (part "FERRITE-0805"))
    )
    (comp (ref "L12")
      (value "150mΩ ±25% 220Ω@100MHz 0805 Ferrite Beads ROHS")
      (footprint "eagle-import:FB805")
      (fields (field (name "LCSC_PART") "C139188"))
      (libsource (lib "eagle-import") (part "FERRITE-0805"))
    )
    (comp (ref "P10")
      (value "DB2ERC-5.08-2P-GN")
      (footprint "eagle-import:MSTBA2")
      (fields (field (name "MF") "FARNELL") (field (name "MPN") "1757242"))
      (libsource (lib "eagle-import") (part "MSTBA2"))
    )
    (comp (ref "P23")
      (value "22284020")
      (footprint "eagle-import:1X02")
      (libsource (lib "eagle-import") (part "PINHD-1X2"))
    )
    (comp (ref "P24")
      (value "1803329")
      (footprint "eagle-import:PHOENIX_1803329")
      (fields (field (name "MF") "Phoenix Contact"))
      (libsource (lib "eagle-import") (part "1803329"))
    )
    (comp (ref "Q3")
      (value "2N7002-7-F")
      (footprint "eagle-import:SOT-23")
      (libsource (lib "eagle-import") (part "2N7002-7-F"))
    )
    (comp (ref "Q14")
      (value "CSD19538Q3A")
      (footprint "eagle-import:CSD19538Q3A")
      (libsource (lib "eagle-import") (part "CSD19538Q3A"))
    )
    (comp (ref "Q15")
      (value "CSD19538Q3A")
      (footprint "eagle-import:CSD19538Q3A")
      (libsource (lib "eagle-import") (part "CSD19538Q3A"))
    )
    (comp (ref "R29")
      (value "2R2")
      (footprint "eagle-import:R0603")
      (libsource (lib "eagle-import") (part "R-EU_R0603"))
    )
    (comp (ref "R30")
      (value "180K")
      (footprint "eagle-import:R0603")
      (libsource (lib "eagle-import") (part "R-EU_R0603"))
    )
    (comp (ref "R38")
      (value "10K")
      (footprint "eagle-import:R0603")
      (libsource (lib "eagle-import") (part "R-EU_R0603"))
    )
    (comp (ref "R43")
      (value "8K2")
      (footprint "eagle-import:R0603")
      (libsource (lib "eagle-import") (part "R-EU_R0603"))
    )
    (comp (ref "R55")
      (value "10K")
      (footprint "eagle-import:R0603")
      (libsource (lib "eagle-import") (part "R-EU_R0603"))
    )
    (comp (ref "R56")
      (value "47k")
      (footprint "eagle-import:R0603")
      (libsource (lib "eagle-import") (part "R-EU_R0603"))
    )
    (comp (ref "R57")
      (value "1K91")
      (footprint "eagle-import:R0603")
      (libsource (lib "eagle-import") (part "R-EU_R0603"))
    )
    (comp (ref "R82")
      (value "10K")
      (footprint "eagle-import:R0603")
      (libsource (lib "eagle-import") (part "R-EU_R0603"))
    )
    (comp (ref "R83")
      (value "10K")
      (footprint "eagle-import:R0603")
      (libsource (lib "eagle-import") (part "R-EU_R0603"))
    )
    (comp (ref "R111")
      (value "1K")
      (footprint "eagle-import:R0603")
      (libsource (lib "eagle-import") (part "R-EU_R0603"))
    )
    (comp (ref "R125")
      (value "20K")
      (footprint "eagle-import:R0603")
      (libsource (lib "eagle-import") (part "R-EU_R0603"))
    )
    (comp (ref "R132")
      (value "20K")
      (footprint "eagle-import:R0603")
      (libsource (lib "eagle-import") (part "R-EU_R0603"))
    )
    (comp (ref "R134")
      (value "2R2")
      (footprint "eagle-import:R0603")
      (libsource (lib "eagle-import") (part "R-EU_R0603"))
    )
    (comp (ref "R167")
      (value "1k5")
      (footprint "eagle-import:R0603")
      (libsource (lib "eagle-import") (part "R-EU_R0603"))
    )
    (comp (ref "R175")
      (value "4K7")
      (footprint "eagle-import:R0603")
      (libsource (lib "eagle-import") (part "R-EU_R0603"))
    )
    (comp (ref "R176")
      (value "18K")
      (footprint "eagle-import:R0603")
      (libsource (lib "eagle-import") (part "R-EU_R0603"))
    )
    (comp (ref "R177")
      (value "5K1")
      (footprint "eagle-import:R0603")
      (libsource (lib "eagle-import") (part "R-EU_R0603"))
    )
    (comp (ref "R178")
      (value "620R")
      (footprint "eagle-import:R0603")
      (libsource (lib "eagle-import") (part "R-EU_R0603"))
    )
    (comp (ref "R179")
      (value "39K")
      (footprint "eagle-import:R0603")
      (libsource (lib "eagle-import") (part "R-EU_R0603"))
    )
    (comp (ref "R184")
      (value "5K1")
      (footprint "eagle-import:R0603")
      (libsource (lib "eagle-import") (part "R-EU_R0603"))
    )
    (comp (ref "R196")
      (value "1K")
      (footprint "eagle-import:R0603")
      (libsource (lib "eagle-import") (part "R-EU_R0603"))
    )
    (comp (ref "S1")
      (value "SS-12D11G5R")
      (footprint "eagle-import:XKBENTERPRISESS-12D11G5R")
      (libsource (lib "eagle-import") (part "XKBENTERPRISESS-12D11G5R"))
    )
    (comp (ref "U16")
      (value "TPS54331DR")
      (footprint "eagle-import:SOIC127P599X175-8N")
      (fields (field (name "MF") "Texas Instruments"))
      (libsource (lib "eagle-import") (part "TPS54331DR"))
    )
    (comp (ref "U24")
      (value "LM5146QRGYTQ1")
      (footprint "eagle-import:RGY0020B")
      (fields (field (name "COPYRIGHT") "Copyright (C) 2025 Ultra Librarian. All rights reserved."))
      (libsource (lib "eagle-import") (part "LM5146QRGYTQ1"))
    )
    (comp (ref "U43")
      (value "EL357N-G")
      (footprint "eagle-import:OPTO_EL357N-G")
      (fields (field (name "MF") "Everlight Electronics"))
      (libsource (lib "eagle-import") (part "EL357N-G"))
    )
    (comp (ref "VR1")
      (value "AMS1117-3.3")
      (footprint "eagle-import:AMS1117-3.3")
      (fields (field (name "MF") "Texas Instruments") (field (name "MP") "TLV111733CDCY"))
      (libsource (lib "eagle-import") (part "AMS1117-3.3"))
    )
    (comp (ref "C4")
      (value "100nF")
      (footprint "eagle-import:C0603")
      (fields (field (name "LCSC_PART") "C576517"))
      (libsource (lib "eagle-import") (part "C-EUC0603"))
    )
    (comp (ref "C73")
      (value "100nF")
      (footprint "eagle-import:C0603")
      (fields (field (name "LCSC_PART") "C576517"))
      (libsource (lib "eagle-import") (part "C-EUC0603"))
    )
    (comp (ref "D2")
      (value "WHITE")
      (footprint "eagle-import:CHIP-LED0603")
      (libsource (lib "eagle-import") (part "LEDCHIP-LED0603"))
    )
    (comp (ref "D28")
      (value "RED")
      (footprint "eagle-import:CHIP-LED0603")
      (libsource (lib "eagle-import") (part "LEDCHIP-LED0603"))
    )
    (comp (ref "J9")
      (value "1803455")
      (footprint "eagle-import:PHOENIX_1803455")
      (fields (field (name "MF") "Phoenix Contact"))
      (libsource (lib "eagle-import") (part "1803455"))
    )
    (comp (ref "J11")
      (value "1803280")
      (footprint "eagle-import:PHOENIX_1803280")
      (fields (field (name "MF") "Phoenix Contact"))
      (libsource (lib "eagle-import") (part "1803280"))
    )
    (comp (ref "Q4")
      (value "2N7002-7-F")
      (footprint "eagle-import:SOT-23")
      (libsource (lib "eagle-import") (part "2N7002-7-F"))
    )
    (comp (ref "Q5")
      (value "2N7002-7-F")
      (footprint "eagle-import:SOT-23")
      (libsource (lib "eagle-import") (part "2N7002-7-F"))
    )
    (comp (ref "Q11")
      (value "2N7002-7-F")
      (footprint "eagle-import:SOT-23")
      (libsource (lib "eagle-import") (part "2N7002-7-F"))
    )
    (comp (ref "Q12")
      (value "2N7002-7-F")
      (footprint "eagle-import:SOT-23")
      (libsource (lib "eagle-import") (part "2N7002-7-F"))
    )
    (comp (ref "R24")
      (value "220R")
      (footprint "eagle-import:R0402")
      (libsource (lib "eagle-import") (part "R-EU_R0402"))
    )
    (comp (ref "R25")
      (value "220R")
      (footprint "eagle-import:R0402")
      (libsource (lib "eagle-import") (part "R-EU_R0402"))
    )
    (comp (ref "R26")
      (value "10K")
      (footprint "eagle-import:R0402")
      (libsource (lib "eagle-import") (part "R-EU_R0402"))
    )
    (comp (ref "R31")
      (value "220R")
      (footprint "eagle-import:R0402")
      (libsource (lib "eagle-import") (part "R-EU_R0402"))
    )
    (comp (ref "R32")
      (value "220R")
      (footprint "eagle-import:R0402")
      (libsource (lib "eagle-import") (part "R-EU_R0402"))
    )
    (comp (ref "R34")
      (value "300R")
      (footprint "eagle-import:R0402")
      (libsource (lib "eagle-import") (part "R-EU_R0402"))
    )
    (comp (ref "R35")
      (value "220R")
      (footprint "eagle-import:R0402")
      (libsource (lib "eagle-import") (part "R-EU_R0402"))
    )
    (comp (ref "R36")
      (value "220R")
      (footprint "eagle-import:R0402")
      (libsource (lib "eagle-import") (part "R-EU_R0402"))
    )
    (comp (ref "R37")
      (value "220R")
      (footprint "eagle-import:R0402")
      (libsource (lib "eagle-import") (part "R-EU_R0402"))
    )
    (comp (ref "R40")
      (value "220R")
      (footprint "eagle-import:R0402")
      (libsource (lib "eagle-import") (part "R-EU_R0402"))
    )
    (comp (ref "R41")
      (value "220R")
      (footprint "eagle-import:R0402")
      (libsource (lib "eagle-import") (part "R-EU_R0402"))
    )
    (comp (ref "R84")
      (value "10K")
      (footprint "eagle-import:R0402")
      (libsource (lib "eagle-import") (part "R-EU_R0402"))
    )
    (comp (ref "R99")
      (value "DNI")
      (footprint "eagle-import:R0402")
      (libsource (lib "eagle-import") (part "R-EU_R0402"))
    )
    (comp (ref "R151")
      (value "4K7")
      (footprint "eagle-import:R0402")
      (libsource (lib "eagle-import") (part "R-EU_R0402"))
    )
    (comp (ref "R152")
      (value "4K7")
      (footprint "eagle-import:R0402")
      (libsource (lib "eagle-import") (part "R-EU_R0402"))
    )
    (comp (ref "R153")
      (value "10K")
      (footprint "eagle-import:R0402")
      (libsource (lib "eagle-import") (part "R-EU_R0402"))
    )
    (comp (ref "R154")
      (value "10K")
      (footprint "eagle-import:R0402")
      (libsource (lib "eagle-import") (part "R-EU_R0402"))
    )
    (comp (ref "R164")
      (value "4k7")
      (footprint "eagle-import:R0402")
      (libsource (lib "eagle-import") (part "R-EU_R0402"))
    )
    (comp (ref "R165")
      (value "510R")
      (footprint "eagle-import:R0402")
      (libsource (lib "eagle-import") (part "R-EU_R0402"))
    )
    (comp (ref "R166")
      (value "10K")
      (footprint "eagle-import:R0402")
      (libsource (lib "eagle-import") (part "R-EU_R0402"))
    )
    (comp (ref "R168")
      (value "10K")
      (footprint "eagle-import:R0402")
      (libsource (lib "eagle-import") (part "R-EU_R0402"))
    )
    (comp (ref "R169")
      (value "10K")
      (footprint "eagle-import:R0402")
      (libsource (lib "eagle-import") (part "R-EU_R0402"))
    )
    (comp (ref "U3")
      (value "SN74LVC2G17DBVR")
      (footprint "eagle-import:SOT95P280X145-6N")
      (fields (field (name "MF") "Texas Instruments"))
      (libsource (lib "eagle-import") (part "SN74LVC2G17DBVR"))
    )
    (comp (ref "U4")
      (value "EL357N-G")
      (footprint "eagle-import:OPTO_EL357N-G")
      (fields (field (name "MF") "Everlight Electronics"))
      (libsource (lib "eagle-import") (part "EL357N-G"))
    )
    (comp (ref "U5")
      (value "EL357N-G")
      (footprint "eagle-import:OPTO_EL357N-G")
      (fields (field (name "MF") "Everlight Electronics"))
      (libsource (lib "eagle-import") (part "EL357N-G"))
    )
    (comp (ref "U6")
      (value "EL357N-G")
      (footprint "eagle-import:OPTO_EL357N-G")
      (fields (field (name "MF") "Everlight Electronics"))
      (libsource (lib "eagle-import") (part "EL357N-G"))
    )
    (comp (ref "U7")
      (value "EL357N-G")
      (footprint "eagle-import:OPTO_EL357N-G")
      (fields (field (name "MF") "Everlight Electronics"))
      (libsource (lib "eagle-import") (part "EL357N-G"))
    )
    (comp (ref "U8")
      (value "EL357N-G")
      (footprint "eagle-import:OPTO_EL357N-G")
      (fields (field (name "MF") "Everlight Electronics"))
      (libsource (lib "eagle-import") (part "EL357N-G"))
    )
    (comp (ref "U10")
      (value "EL357N-G")
      (footprint "eagle-import:OPTO_EL357N-G")
      (fields (field (name "MF") "Everlight Electronics"))
      (libsource (lib "eagle-import") (part "EL357N-G"))
    )
    (comp (ref "U23")
      (value "EL357N-G")
      (footprint "eagle-import:OPTO_EL357N-G")
      (fields (field (name "MF") "Everlight Electronics"))
      (libsource (lib "eagle-import") (part "EL357N-G"))
    )
  )
  (nets
    (net (code "1") (name "3V3") (class "Default")
      (node (ref "P12") (pin "12") (pinfunction "YA_12") (pintype "passive"))
      (node (ref "P12") (pin "9") (pinfunction "GA_9") (pintype "passive"))
    )
    (net (code "2") (name "3V3_A") (class "Default")
      (node (ref "C123") (pin "1") (pinfunction "1_1") (pintype "passive"))
      (node (ref "C124") (pin "1") (pinfunction "1_1") (pintype "passive"))
      (node (ref "C125") (pin "1") (pinfunction "1_1") (pintype "passive"))
      (node (ref "C126") (pin "1") (pinfunction "1_1") (pintype "passive"))
      (node (ref "C127") (pin "1") (pinfunction "1_1") (pintype "passive"))
      (node (ref "C128") (pin "1") (pinfunction "1_1") (pintype "passive"))
      (node (ref "C129") (pin "1") (pinfunction "1_1") (pintype "passive"))
      (node (ref "C130") (pin "1") (pinfunction "1_1") (pintype "passive"))
      (node (ref "L6") (pin "1") (pinfunction "1_1") (pintype "passive"))
      (node (ref "R1") (pin "1") (pinfunction "1_1") (pintype "passive"))
      (node (ref "R135") (pin "1") (pinfunction "1_1") (pintype "passive"))
      (node (ref "R144") (pin "1") (pinfunction "1_1") (pintype "passive"))
      (node (ref "R145") (pin "1") (pinfunction "1_1") (pintype "passive"))
      (node (ref "R146") (pin "1") (pinfunction "1_1") (pintype "passive"))
      (node (ref "R5") (pin "1") (pinfunction "1_1") (pintype "passive"))
      (node (ref "R6") (pin "1") (pinfunction "1_1") (pintype "passive"))
      (node (ref "U11") (pin "11") (pinfunction "AVDD_11") (pintype "power_in"))
      (node (ref "U11") (pin "15") (pinfunction "AVDD_15") (pintype "power_in"))
      (node (ref "U11") (pin "17") (pinfunction "AVDD_17") (pintype "power_in"))
      (node (ref "U11") (pin "21") (pinfunction "AVDD_21") (pintype "power_in"))
      (node (ref "U11") (pin "4") (pinfunction "AVDD_4") (pintype "power_in"))
      (node (ref "U11") (pin "8") (pinfunction "AVDD_8") (pintype "power_in"))
    )
    (net (code "3") (name "5V_VCC") (class "Default")
      (node (ref "C104") (pin "1") (pinfunction "1_1") (pintype "passive"))
      (node (ref "C105") (pin "2") (pinfunction "2_2") (pintype "passive"))
      (node (ref "C108") (pin "2") (pinfunction "2_2") (pintype "passive"))
      (node (ref "C140") (pin "1") (pinfunction "1_1") (pintype "passive"))
      (node (ref "R106") (pin "2") (pinfunction "2_2") (pintype "passive"))
      (node (ref "R130") (pin "1") (pinfunction "1_1") (pintype "passive"))
      (node (ref "R162") (pin "2") (pinfunction "2_2") (pintype "passive"))
      (node (ref "R200") (pin "1") (pinfunction "1_1") (pintype "passive"))
      (node (ref "R201") (pin "1") (pinfunction "1_1") (pintype "passive"))
      (node (ref "U25") (pin "5") (pinfunction "VCC_5") (pintype "power_in"))
      (node (ref "U40") (pin "8") (pinfunction "VCC_8") (pintype "power_in"))
      (node (ref "U42") (pin "14") (pinfunction "VCC_14") (pintype "power_in"))
      (node (ref "U44") (pin "5") (pinfunction "VCC_5") (pintype "power_in"))
      (node (ref "U50") (pin "4") (pinfunction "RST_4") (pintype "input"))
      (node (ref "U50") (pin "8") (pinfunction "VCC_8") (pintype "power_in"))
    )
    (net (code "4") (name "24V_RELAY") (class "Default")
      (node (ref "D45") (pin "2") (pinfunction "A_2") (pintype "passive"))
      (node (ref "F3") (pin "1") (pinfunction "1_1") (pintype "passive"))
      (node (ref "K2") (pin "86") (pinfunction "86_86") (pintype "passive"))
      (node (ref "P6") (pin "1") (pinfunction "1_1") (pintype "passive"))
    )
    (net (code "5") (name "A") (class "Default")
      (node (ref "D16") (pin "2") (pinfunction "Z2_2") (pintype "bidirectional"))
      (node (ref "J10") (pin "03") (pinfunction "03_03") (pintype "passive"))
      (node (ref "J12") (pin "4") (pinfunction "4_4") (pintype "passive"))
      (node (ref "R48") (pin "1") (pinfunction "1_1") (pintype "passive"))
      (node (ref "R49") (pin "2") (pinfunction "2_2") (pintype "passive"))
      (node (ref "U13") (pin "6") (pinfunction "A_6") (pintype "output"))
    )
    (net (code "6") (name "ADC_INPUT") (class "Default")
      (node (ref "J13") (pin "2") (pinfunction "2_2") (pintype "passive"))
      (node (ref "P11") (pin "14") (pinfunction "14_14") (pintype "passive"))
      (node (ref "R58") (pin "2") (pinfunction "2_2") (pintype "passive"))
      (node (ref "R60") (pin "2") (pinfunction "2_2") (pintype "passive"))
    )
    (net (code "7") (name "AL_A") (class "Default")
      (node (ref "C96") (pin "1") (pinfunction "1_1") (pintype "passive"))
      (node (ref "R119") (pin "2") (pinfunction "2_2") (pintype "passive"))
      (node (ref "R161") (pin "2") (pinfunction "2_2") (pintype "passive"))
      (node (ref "TP28") (pin "TP") (pinfunction "TP_TP") (pintype "input"))
      (node (ref "U17") (pin "83") (pinfunction "PD2/UART5_RX_83") (pintype "bidirectional"))
      (node (ref "U32") (pin "4") (pinfunction "CT_4") (pintype "passive"))
    )
    (net (code "8") (name "ANALOG_IN") (class "Default")
      (node (ref "R59") (pin "1") (pinfunction "1_1") (pintype "passive"))
      (node (ref "TP60") (pin "TP") (pinfunction "TP_TP") (pintype "input"))
      (node (ref "U17") (pin "23") (pinfunction "PA0/UART4_TX_23") (pintype "bidirectional"))
    )
    (net (code "9") (name "AUX0_RLY") (class "Default")
      (node (ref "D30_RL1") (pin "A") (pinfunction "A_A") (pintype "passive"))
      (node (ref "D30_RL2") (pin "A") (pinfunction "A_A") (pintype "passive"))
      (node (ref "F1_RL1") (pin "2") (pinfunction "2_2") (pintype "passive"))
      (node (ref "F1_RL2") (pin "2") (pinfunction "2_2") (pintype "passive"))
      (node (ref "Q2_RL1") (pin "P3") (pinfunction "D_P3") (pintype "passive"))
      (node (ref "Q2_RL2") (pin "P3") (pinfunction "D_P3") (pintype "passive"))
      (node (ref "R109_RL1") (pin "1") (pinfunction "1_1") (pintype "passive"))
      (node (ref "R109_RL2") (pin "1") (pinfunction "1_1") (pintype "passive"))
    )
    (net (code "10") (name "AUX0_RLY_OUT") (class "Default")
      (node (ref "F1_RL1") (pin "1") (pinfunction "1_1") (pintype "passive"))
      (node (ref "F1_RL2") (pin "1") (pinfunction "1_1") (pintype "passive"))
      (node (ref "P18_RL1") (pin "1") (pinfunction "1_1") (pintype "passive"))
      (node (ref "P18_RL2") (pin "1") (pinfunction "1_1") (pintype "passive"))
    )
    (net (code "11") (name "AUXOUT0") (class "Default")
      (node (ref "R122_AO0") (pin "2") (pinfunction "2_2") (pintype "passive"))
      (node (ref "TP1") (pin "TP") (pinfunction "TP_TP") (pintype "input"))
      (node (ref "U17") (pin "8") (pinfunction "PC14_8") (pintype "bidirectional"))
    )
    (net (code "12") (name "AUXOUT1") (class "Default")
      (node (ref "R122_AO1") (pin "2") (pinfunction "2_2") (pintype "passive"))
      (node (ref "TP2") (pin "TP") (pinfunction "TP_TP") (pintype "input"))
      (node (ref "U17") (pin "15") (pinfunction "PC0_15") (pintype "bidirectional"))
    )
    (net (code "13") (name "AUXOUT2") (class "Default")
      (node (ref "R122_AO2") (pin "2") (pinfunction "2_2") (pintype "passive"))
      (node (ref "TP33") (pin "TP") (pinfunction "TP_TP") (pintype "input"))
      (node (ref "U17") (pin "16") (pinfunction "PC1_16") (pintype "bidirectional"))
    )
    (net (code "14") (name "AUXOUT3") (class "Default")
      (node (ref "R122_AO3") (pin "2") (pinfunction "2_2") (pintype "passive"))
      (node (ref "TP34") (pin "TP") (pinfunction "TP_TP") (pintype "input"))
      (node (ref "U17") (pin "65") (pinfunction "PC8/TIM3_CH3_65") (pintype "bidirectional"))
    )
    (net (code "15") (name "AUX_IN0_5V") (class "Default")
      (node (ref "P11") (pin "22") (pinfunction "22_22") (pintype "passive"))
      (node (ref "R124_N0") (pin "2") (pinfunction "2_2") (pintype "passive"))
    )
    (net (code "16") (name "AUX_IN1_5V") (class "Default")
      (node (ref "P11") (pin "26") (pinfunction "26_26") (pintype "passive"))
      (node (ref "R124_N1") (pin "2") (pinfunction "2_2") (pintype "passive"))
    )
    (net (code "17") (name "AUX_IN2_5V") (class "Default")
      (node (ref "P11") (pin "30") (pinfunction "30_30") (pintype "passive"))
      (node (ref "R124_N2") (pin "2") (pinfunction "2_2") (pintype "passive"))
    )
    (net (code "18") (name "AUX_IN3_5V") (class "Default")
      (node (ref "P11") (pin "34") (pinfunction "34_34") (pintype "passive"))
      (node (ref "R124_N3") (pin "2") (pinfunction "2_2") (pintype "passive"))
    )
    (net (code "19") (name "AUX_IN_0") (class "Default")
      (node (ref "C107_N0") (pin "1") (pinfunction "1_1") (pintype "passive"))
      (node (ref "R123_N0") (pin "2") (pinfunction "2_2") (pintype "passive"))
      (node (ref "TP53") (pin "TP") (pinfunction "TP_TP") (pintype "input"))
      (node (ref "U17") (pin "59") (pinfunction "PD12/TIM4_CH1/USART3_RTS_59") (pintype "bidirectional"))
      (node (ref "U34_N0") (pin "4") (pinfunction "CT_4") (pintype "passive"))
    )
    (net (code "20") (name "AUX_IN_1") (class "Default")
      (node (ref "C107_N1") (pin "1") (pinfunction "1_1") (pintype "passive"))
      (node (ref "R123_N1") (pin "2") (pinfunction "2_2") (pintype "passive"))
      (node (ref "TP54") (pin "TP") (pinfunction "TP_TP") (pintype "input"))
      (node (ref "U17") (pin "60") (pinfunction "PD13/TIM4_CH2_60") (pintype "bidirectional"))
      (node (ref "U34_N1") (pin "4") (pinfunction "CT_4") (pintype "passive"))
    )
    (net (code "21") (name "AUX_IN_2") (class "Default")
      (node (ref "C107_N2") (pin "1") (pinfunction "1_1") (pintype "passive"))
      (node (ref "R123_N2") (pin "2") (pinfunction "2_2") (pintype "passive"))
      (node (ref "TP55") (pin "TP") (pinfunction "TP_TP") (pintype "input"))
      (node (ref "U17") (pin "61") (pinfunction "PD14/TIM4_CH3_61") (pintype "bidirectional"))
      (node (ref "U34_N2") (pin "4") (pinfunction "CT_4") (pintype "passive"))
    )
    (net (code "22") (name "AUX_IN_3") (class "Default")
      (node (ref "C107_N3") (pin "1") (pinfunction "1_1") (pintype "passive"))
      (node (ref "R123_N3") (pin "2") (pinfunction "2_2") (pintype "passive"))
      (node (ref "TP56") (pin "TP") (pinfunction "TP_TP") (pintype "input"))
      (node (ref "U17") (pin "62") (pinfunction "PD15/TIM4_CH4_62") (pintype "bidirectional"))
      (node (ref "U34_N3") (pin "4") (pinfunction "CT_4") (pintype "passive"))
    )
    (net (code "23") (name "AUX_OUT_0_5V") (class "Default")
      (node (ref "P11") (pin "19") (pinfunction "19_19") (pintype "passive"))
      (node (ref "Q10_RL1") (pin "P1") (pinfunction "G_P1") (pintype "passive"))
      (node (ref "Q2_RL1") (pin "P1") (pinfunction "G_P1") (pintype "passive"))
      (node (ref "R77_AO0") (pin "1") (pinfunction "1_1") (pintype "passive"))
      (node (ref "R89_RL1") (pin "2") (pinfunction "2_2") (pintype "passive"))
      (node (ref "U33_AO0") (pin "3") (pinfunction "ET_3") (pintype "passive"))
    )
    (net (code "24") (name "AUX_OUT_1_5V") (class "Default")
      (node (ref "P11") (pin "21") (pinfunction "21_21") (pintype "passive"))
      (node (ref "Q10_RL2") (pin "P1") (pinfunction "G_P1") (pintype "passive"))
      (node (ref "Q2_RL2") (pin "P1") (pinfunction "G_P1") (pintype "passive"))
      (node (ref "R77_AO1") (pin "1") (pinfunction "1_1") (pintype "passive"))
      (node (ref "R89_RL2") (pin "2") (pinfunction "2_2") (pintype "passive"))
      (node (ref "U33_AO1") (pin "3") (pinfunction "ET_3") (pintype "passive"))
    )
    (net (code "25") (name "AUX_OUT_2_5V") (class "Default")
      (node (ref "P11") (pin "25") (pinfunction "25_25") (pintype "passive"))
      (node (ref "Q9_TR1") (pin "P1") (pinfunction "G_P1") (pintype "passive"))
      (node (ref "R174_TR1") (pin "2") (pinfunction "2_2") (pintype "passive"))
      (node (ref "R39_TR1") (pin "2") (pinfunction "2_2") (pintype "passive"))
      (node (ref "R77_AO2") (pin "1") (pinfunction "1_1") (pintype "passive"))
      (node (ref "U33_AO2") (pin "3") (pinfunction "ET_3") (pintype "passive"))
    )
    (net (code "26") (name "AUX_OUT_3_5V") (class "Default")
      (node (ref "P11") (pin "27") (pinfunction "27_27") (pintype "passive"))
      (node (ref "Q9_TR2") (pin "P1") (pinfunction "G_P1") (pintype "passive"))
      (node (ref "R174_TR2") (pin "2") (pinfunction "2_2") (pintype "passive"))
      (node (ref "R39_TR2") (pin "2") (pinfunction "2_2") (pintype "passive"))
      (node (ref "R77_AO3") (pin "1") (pinfunction "1_1") (pintype "passive"))
      (node (ref "U33_AO3") (pin "3") (pinfunction "ET_3") (pintype "passive"))
    )
    (net (code "27") (name "AUX_RXD_5V") (class "Default")
      (node (ref "P11") (pin "40") (pinfunction "40_40") (pintype "passive"))
      (node (ref "U20") (pin "7") (pinfunction "VIA_7") (pintype "bidirectional"))
    )
    (net (code "28") (name "AUX_TXD_5V") (class "Default")
      (node (ref "P11") (pin "38") (pinfunction "38_38") (pintype "passive"))
      (node (ref "U20") (pin "6") (pinfunction "VOB_6") (pintype "bidirectional"))
    )
    (net (code "29") (name "A_LIM") (class "Default")
      (node (ref "C3_AL") (pin "1") (pinfunction "1_1") (pintype "passive"))
      (node (ref "R17") (pin "2") (pinfunction "2_2") (pintype "passive"))
      (node (ref "R22_AL") (pin "2") (pinfunction "2_2") (pintype "passive"))
      (node (ref "U17") (pin "45") (pinfunction "PE14/TIM1_CH4_45") (pintype "bidirectional"))
      (node (ref "U2_AL") (pin "4") (pinfunction "CT_4") (pintype "passive"))
    )
    (net (code "30") (name "A_LIM_EXT") (class "Default")
      (node (ref "J8") (pin "1") (pinfunction "1_1") (pintype "passive"))
      (node (ref "P17") (pin "02") (pinfunction "02_02") (pintype "passive"))
      (node (ref "U2_AL") (pin "2") (pinfunction "C_2") (pintype "passive"))
    )
    (net (code "31") (name "B") (class "Default")
      (node (ref "D16") (pin "1") (pinfunction "Z1_1") (pintype "bidirectional"))
      (node (ref "J10") (pin "04") (pinfunction "04_04") (pintype "passive"))
      (node (ref "J12") (pin "3") (pinfunction "3_3") (pintype "passive"))
      (node (ref "R46") (pin "2") (pinfunction "2_2") (pintype "passive"))
      (node (ref "R49") (pin "1") (pinfunction "1_1") (pintype "passive"))
      (node (ref "U13") (pin "7") (pinfunction "B_7") (pintype "output"))
    )
    (net (code "32") (name "CANH") (class "Default")
      (node (ref "J14") (pin "2") (pinfunction "2_2") (pintype "passive"))
      (node (ref "R87") (pin "2") (pinfunction "2_2") (pintype "passive"))
      (node (ref "U19") (pin "7") (pinfunction "CANH_7") (pintype "bidirectional"))
    )
    (net (code "33") (name "CANL") (class "Default")
      (node (ref "J14") (pin "3") (pinfunction "3_3") (pintype "passive"))
      (node (ref "R87") (pin "1") (pinfunction "1_1") (pintype "passive"))
      (node (ref "U19") (pin "6") (pinfunction "CANL_6") (pintype "bidirectional"))
    )
    (net (code "34") (name "CAN_RX") (class "Default")
      (node (ref "R94") (pin "1") (pinfunction "1_1") (pintype "passive"))
      (node (ref "TP32") (pin "TP") (pinfunction "TP_TP") (pintype "input"))
      (node (ref "U17") (pin "81") (pinfunction "PD0/CAN1_RX_81") (pintype "bidirectional"))
      (node (ref "U18") (pin "2") (pinfunction "VOA_2") (pintype "bidirectional"))
    )
    (net (code "35") (name "CAN_TX") (class "Default")
      (node (ref "R95") (pin "1") (pinfunction "1_1") (pintype "passive"))
      (node (ref "TP31") (pin "TP") (pinfunction "TP_TP") (pintype "input"))
      (node (ref "U17") (pin "82") (pinfunction "PD1/CAN1_TX_82") (pintype "bidirectional"))
      (node (ref "U18") (pin "3") (pinfunction "VIB_3") (pintype "bidirectional"))
    )
    (net (code "36") (name "COMP") (class "Default")
      (node (ref "C85") (pin "1") (pinfunction "1_1") (pintype "passive"))
      (node (ref "C86") (pin "1") (pinfunction "1_1") (pintype "passive"))
      (node (ref "U24") (pin "4") (pinfunction "COMP_4") (pintype "passive"))
    )
    (net (code "37") (name "CONN_USB_D_N") (class "Default")
      (node (ref "D27") (pin "3") (pinfunction "I/O2_IN_3") (pintype "bidirectional"))
      (node (ref "D27") (pin "4") (pinfunction "I/O2_OUT_4") (pintype "bidirectional"))
      (node (ref "J20") (pin "A7") (pinfunction "D-_A7") (pintype "bidirectional"))
      (node (ref "J20") (pin "B7") (pinfunction "D-_B7") (pintype "bidirectional"))
      (node (ref "L13") (pin "1") (pinfunction "1_1") (pintype "passive"))
    )
    (net (code "38") (name "CONN_USB_D_P") (class "Default")
      (node (ref "D27") (pin "1") (pinfunction "I/O1_IN_1") (pintype "bidirectional"))
      (node (ref "D27") (pin "6") (pinfunction "I/O1_OUT_6") (pintype "bidirectional"))
      (node (ref "J20") (pin "A6") (pinfunction "D+_A6") (pintype "bidirectional"))
      (node (ref "J20") (pin "B6") (pinfunction "D+_B6") (pintype "bidirectional"))
      (node (ref "L13") (pin "4") (pinfunction "4_4") (pintype "passive"))
    )
    (net (code "39") (name "COOLANT") (class "Default")
      (node (ref "Q6") (pin "P1") (pinfunction "G_P1") (pintype "passive"))
      (node (ref "R122_COO") (pin "2") (pinfunction "2_2") (pintype "passive"))
      (node (ref "R157") (pin "2") (pinfunction "2_2") (pintype "passive"))
      (node (ref "U17") (pin "53") (pinfunction "PB14/SPI2_MISO_53") (pintype "bidirectional"))
    )
    (net (code "40") (name "COOLANT_5V") (class "Default")
      (node (ref "J17") (pin "2") (pinfunction "2_2") (pintype "passive"))
      (node (ref "P11") (pin "31") (pinfunction "31_31") (pintype "passive"))
      (node (ref "R77_COO") (pin "1") (pinfunction "1_1") (pintype "passive"))
      (node (ref "U33_COO") (pin "3") (pinfunction "ET_3") (pintype "passive"))
    )
    (net (code "41") (name "CURRENT_SENSE") (class "Default")
      (node (ref "C94") (pin "1") (pinfunction "1_1") (pintype "passive"))
      (node (ref "R173") (pin "2") (pinfunction "2_2") (pintype "passive"))
      (node (ref "R210") (pin "1") (pinfunction "1_1") (pintype "passive"))
      (node (ref "R212") (pin "1") (pinfunction "1_1") (pintype "passive"))
      (node (ref "R70") (pin "2") (pinfunction "2_2") (pintype "passive"))
    )
    (net (code "42") (name "DI") (class "Default")
      (node (ref "R50") (pin "2") (pinfunction "2_2") (pintype "passive"))
      (node (ref "U12") (pin "6") (pinfunction "VOB_6") (pintype "bidirectional"))
    )
    (net (code "43") (name "DIR_A") (class "Default")
      (node (ref "R116") (pin "2") (pinfunction "2_2") (pintype "passive"))
      (node (ref "TP52") (pin "TP") (pinfunction "TP_TP") (pintype "input"))
      (node (ref "U17") (pin "42") (pinfunction "PE11/TIM1_CH2_42") (pintype "bidirectional"))
    )
    (net (code "44") (name "DIR_A_EXT") (class "Default")
      (node (ref "P11") (pin "6") (pinfunction "6_6") (pintype "passive"))
      (node (ref "P20") (pin "3") (pinfunction "3_3") (pintype "passive"))
      (node (ref "R171") (pin "1") (pinfunction "1_1") (pintype "passive"))
      (node (ref "U30") (pin "3") (pinfunction "ET_3") (pintype "passive"))
    )
    (net (code "45") (name "DIR_X") (class "Default")
      (node (ref "TP48") (pin "TP") (pinfunction "TP_TP") (pintype "input"))
      (node (ref "U17") (pin "38") (pinfunction "PE7/TIM1_ETR_38") (pintype "bidirectional"))
      (node (ref "U26") (pin "3") (pinfunction "VIB_3") (pintype "input"))
    )
    (net (code "46") (name "DIR_X_N") (class "Default")
      (node (ref "P13") (pin "4") (pinfunction "4_4") (pintype "passive"))
      (node (ref "U9") (pin "5") (pinfunction "2Z_5") (pintype "output"))
    )
    (net (code "47") (name "DIR_X_OUT") (class "Default")
      (node (ref "U26") (pin "6") (pinfunction "VOB_6") (pintype "output"))
      (node (ref "U9") (pin "7") (pinfunction "2A_7") (pintype "input"))
    )
    (net (code "48") (name "DIR_X_P") (class "Default")
      (node (ref "P13") (pin "3") (pinfunction "3_3") (pintype "passive"))
      (node (ref "U9") (pin "6") (pinfunction "2Y_6") (pintype "output"))
    )
    (net (code "49") (name "DIR_Y1") (class "Default")
      (node (ref "TP49") (pin "TP") (pinfunction "TP_TP") (pintype "input"))
      (node (ref "U17") (pin "39") (pinfunction "PE8/TIM1_CH1N_39") (pintype "bidirectional"))
      (node (ref "U27") (pin "3") (pinfunction "VIB_3") (pintype "input"))
    )
    (net (code "50") (name "DIR_Y1_N") (class "Default")
      (node (ref "P14") (pin "4") (pinfunction "4_4") (pintype "passive"))
      (node (ref "U9") (pin "11") (pinfunction "3Z_11") (pintype "output"))
    )
    (net (code "51") (name "DIR_Y1_OUT") (class "Default")
      (node (ref "U27") (pin "6") (pinfunction "VOB_6") (pintype "output"))
      (node (ref "U9") (pin "9") (pinfunction "3A_9") (pintype "input"))
    )
    (net (code "52") (name "DIR_Y1_P") (class "Default")
      (node (ref "P14") (pin "3") (pinfunction "3_3") (pintype "passive"))
      (node (ref "U9") (pin "10") (pinfunction "3Y_10") (pintype "output"))
    )
    (net (code "53") (name "DIR_Y2") (class "Default")
      (node (ref "TP51") (pin "TP") (pinfunction "TP_TP") (pintype "input"))
      (node (ref "U17") (pin "41") (pinfunction "PE10/TIM1_CH2N_41") (pintype "bidirectional"))
      (node (ref "U37") (pin "3") (pinfunction "VIB_3") (pintype "input"))
    )
    (net (code "54") (name "DIR_Y2_N") (class "Default")
      (node (ref "P16") (pin "4") (pinfunction "4_4") (pintype "passive"))
      (node (ref "U36") (pin "5") (pinfunction "2Z_5") (pintype "output"))
    )
    (net (code "55") (name "DIR_Y2_OUT") (class "Default")
      (node (ref "U36") (pin "7") (pinfunction "2A_7") (pintype "input"))
      (node (ref "U37") (pin "6") (pinfunction "VOB_6") (pintype "output"))
    )
    (net (code "56") (name "DIR_Y2_P") (class "Default")
      (node (ref "P16") (pin "3") (pinfunction "3_3") (pintype "passive"))
      (node (ref "U36") (pin "6") (pinfunction "2Y_6") (pintype "output"))
    )
    (net (code "57") (name "DIR_Z") (class "Default")
      (node (ref "TP50") (pin "TP") (pinfunction "TP_TP") (pintype "input"))
      (node (ref "U17") (pin "40") (pinfunction "PE9/TIM1_CH1_40") (pintype "bidirectional"))
      (node (ref "U38") (pin "3") (pinfunction "VIB_3") (pintype "input"))
    )
    (net (code "58") (name "DIR_Z_N") (class "Default")
      (node (ref "P27") (pin "4") (pinfunction "4_4") (pintype "passive"))
      (node (ref "U36") (pin "11") (pinfunction "3Z_11") (pintype "output"))
    )
    (net (code "59") (name "DIR_Z_OUT") (class "Default")
      (node (ref "U36") (pin "9") (pinfunction "3A_9") (pintype "input"))
      (node (ref "U38") (pin "6") (pinfunction "VOB_6") (pintype "output"))
    )
    (net (code "60") (name "DIR_Z_P") (class "Default")
      (node (ref "P27") (pin "3") (pinfunction "3_3") (pintype "passive"))
      (node (ref "U36") (pin "10") (pinfunction "3Y_10") (pintype "output"))
    )
    (net (code "61") (name "DOOR") (class "Default")
      (node (ref "C3_DR") (pin "1") (pinfunction "1_1") (pintype "passive"))
      (node (ref "R22_DR") (pin "2") (pinfunction "2_2") (pintype "passive"))
      (node (ref "R63") (pin "2") (pinfunction "2_2") (pintype "passive"))
      (node (ref "TP58") (pin "TP") (pinfunction "TP_TP") (pintype "input"))
      (node (ref "U17") (pin "88") (pinfunction "PD7/USART2_CK_88") (pintype "bidirectional"))
      (node (ref "U2_DR") (pin "4") (pinfunction "CT_4") (pintype "passive"))
    )
    (net (code "62") (name "DOOR_EXT") (class "Default")
      (node (ref "J15") (pin "1") (pinfunction "1_1") (pintype "passive"))
      (node (ref "P11") (pin "13") (pinfunction "13_13") (pintype "passive"))
      (node (ref "U2_DR") (pin "2") (pinfunction "C_2") (pintype "passive"))
    )
    (net (code "63") (name "ENN_X_OUT") (class "Default")
      (node (ref "D35") (pin "3") (pinfunction "3_3") (pintype "passive"))
      (node (ref "P13") (pin "6") (pinfunction "6_6") (pintype "passive"))
      (node (ref "R189") (pin "1") (pinfunction "1_1") (pintype "passive"))
    )
    (net (code "64") (name "ENN_Y1_OUT") (class "Default")
      (node (ref "D53") (pin "3") (pinfunction "3_3") (pintype "passive"))
      (node (ref "P14") (pin "6") (pinfunction "6_6") (pintype "passive"))
      (node (ref "R190") (pin "1") (pinfunction "1_1") (pintype "passive"))
    )
    (net (code "65") (name "ENN_Y2_OUT") (class "Default")
      (node (ref "D54") (pin "3") (pinfunction "3_3") (pintype "passive"))
      (node (ref "P16") (pin "6") (pinfunction "6_6") (pintype "passive"))
      (node (ref "R191") (pin "1") (pinfunction "1_1") (pintype "passive"))
    )
    (net (code "66") (name "ENN_Z_OUT") (class "Default")
      (node (ref "D55") (pin "3") (pinfunction "3_3") (pintype "passive"))
      (node (ref "P27") (pin "6") (pinfunction "6_6") (pintype "passive"))
      (node (ref "R192") (pin "1") (pinfunction "1_1") (pintype "passive"))
    )
    (net (code "67") (name "EN_A_EXT") (class "Default")
      (node (ref "P11") (pin "8") (pinfunction "8_8") (pintype "passive"))
      (node (ref "P20") (pin "5") (pinfunction "5_5") (pintype "passive"))
      (node (ref "R172") (pin "1") (pinfunction "1_1") (pintype "passive"))
      (node (ref "U31") (pin "3") (pinfunction "ET_3") (pintype "passive"))
    )
    (net (code "68") (name "ESTOP_5V_EN") (class "Default")
      (node (ref "P23") (pin "1") (pinfunction "1_1") (pintype "passive"))
      (node (ref "P24") (pin "06") (pinfunction "06_06") (pintype "passive"))
    )
    (net (code "69") (name "ESTOP_EN") (class "Default")
      (node (ref "C103") (pin "1") (pinfunction "1_1") (pintype "passive"))
      (node (ref "C99") (pin "1") (pinfunction "1_1") (pintype "passive"))
      (node (ref "D49") (pin "C") (pinfunction "C_C") (pintype "passive"))
      (node (ref "R180") (pin "1") (pinfunction "1_1") (pintype "passive"))
      (node (ref "U42") (pin "1") (pinfunction "1A_1") (pintype "input"))
      (node (ref "U42") (pin "12") (pinfunction "4A_12") (pintype "input"))
    )
    (net (code "70") (name "FAULT1+") (class "Default")
      (node (ref "R163") (pin "2") (pinfunction "2_2") (pintype "passive"))
      (node (ref "R211") (pin "2") (pinfunction "2_2") (pintype "passive"))
      (node (ref "R212") (pin "2") (pinfunction "2_2") (pintype "passive"))
      (node (ref "U40") (pin "3") (pinfunction "IN_A_3") (pintype "input"))
    )
    (net (code "71") (name "FAULT1-") (class "Default")
      (node (ref "R210") (pin "2") (pinfunction "2_2") (pintype "passive"))
      (node (ref "R215") (pin "2") (pinfunction "2_2") (pintype "passive"))
      (node (ref "U40") (pin "2") (pinfunction "IN_A_2_2") (pintype "input"))
    )
    (net (code "72") (name "FAULT2") (class "Default")
      (node (ref "R162") (pin "1") (pinfunction "1_1") (pintype "passive"))
      (node (ref "R183") (pin "1") (pinfunction "1_1") (pintype "passive"))
      (node (ref "U40") (pin "7") (pinfunction "OUT_B_7") (pintype "output"))
    )
    (net (code "73") (name "FEEDBACK24V") (class "Default")
      (node (ref "C83") (pin "2") (pinfunction "2_2") (pintype "passive"))
      (node (ref "C86") (pin "2") (pinfunction "2_2") (pintype "passive"))
      (node (ref "R176") (pin "1") (pinfunction "1_1") (pintype "passive"))
      (node (ref "R177") (pin "1") (pinfunction "1_1") (pintype "passive"))
      (node (ref "R178") (pin "2") (pinfunction "2_2") (pintype "passive"))
      (node (ref "U24") (pin "5") (pinfunction "FB_5") (pintype "input"))
    )
    (net (code "74") (name "GND") (class "Default")
      (node (ref "C103") (pin "2") (pinfunction "2_2") (pintype "passive"))
      (node (ref "C104") (pin "2") (pinfunction "2_2") (pintype "passive"))
      (node (ref "C105") (pin "1") (pinfunction "1_1") (pintype "passive"))
      (node (ref "C106") (pin "2") (pinfunction "2_2") (pintype "passive"))
      (node (ref "C107_N0") (pin "2") (pinfunction "2_2") (pintype "passive"))
      (node (ref "C107_N1") (pin "2") (pinfunction "2_2") (pintype "passive"))
      (node (ref "C107_N2") (pin "2") (pinfunction "2_2") (pintype "passive"))
      (node (ref "C107_N3") (pin "2") (pinfunction "2_2") (pintype "passive"))
      (node (ref "C108") (pin "1") (pinfunction "1_1") (pintype "passive"))
      (node (ref "C109") (pin "2") (pinfunction "2_2") (pintype "passive"))
      (node (ref "C11") (pin "2") (pinfunction "2_2") (pintype "passive"))
      (node (ref "C112") (pin "1") (pinfunction "1_1") (pintype "passive"))
      (node (ref "C113") (pin "2") (pinfunction "2_2") (pintype "passive"))
      (node (ref "C114") (pin "1") (pinfunction "1_1") (pintype "passive"))
      (node (ref "C115") (pin "2") (pinfunction "2_2") (pintype "passive"))
      (node (ref "C116") (pin "2") (pinfunction "2_2") (pintype "passive"))
      (node (ref "C117") (pin "1") (pinfunction "1_1") (pintype "passive"))
      (node (ref "C118") (pin "1") (pinfunction "1_1") (pintype "passive"))
      (node (ref "C12") (pin "2") (pinfunction "2_2") (pintype "passive"))
      (node (ref "C120") (pin "2") (pinfunction "2_2") (pintype "passive"))
      (node (ref "C121") (pin "2") (pinfunction "2_2") (pintype "passive"))
      (node (ref "C122") (pin "2") (pinfunction "2_2") (pintype "passive"))
      (node (ref "C123") (pin "2") (pinfunction "2_2") (pintype "passive"))
      (node (ref "C124") (pin "2") (pinfunction "2_2") (pintype "passive"))
      (node (ref "C125") (pin "2") (pinfunction "2_2") (pintype "passive"))
      (node (ref "C126") (pin "2") (pinfunction "2_2") (pintype "passive"))
      (node (ref "C127") (pin "2") (pinfunction "2_2") (pintype "passive"))
      (node (ref "C128") (pin "2") (pinfunction "2_2") (pintype "passive"))
      (node (ref "C129") (pin "2") (pinfunction "2_2") (pintype "passive"))
      (node (ref "C13") (pin "2") (pinfunction "2_2") (pintype "passive"))
      (node (ref "C130") (pin "2") (pinfunction "2_2") (pintype "passive"))
      (node (ref "C131") (pin "2") (pinfunction "2_2") (pintype "passive"))
      (node (ref "C132") (pin "2") (pinfunction "2_2") (pintype "passive"))
      (node (ref "C133") (pin "2") (pinfunction "2_2") (pintype "passive"))
      (node (ref "C139") (pin "2") (pinfunction "2_2") (pintype "passive"))
      (node (ref "C14") (pin "2") (pinfunction "2_2") (pintype "passive"))
      (node (ref "C140") (pin "2") (pinfunction "2_2") (pintype "passive"))
      (node (ref "C142") (pin "2") (pinfunction "2_2") (pintype "passive"))
      (node (ref "C143") (pin "2") (pinfunction "2_2") (pintype "passive"))
      (node (ref "C144") (pin "2") (pinfunction "2_2") (pintype "passive"))
      (node (ref "C145") (pin "2") (pinfunction "2_2") (pintype "passive"))
      (node (ref "C15") (pin "2") (pinfunction "2_2") (pintype "passive"))
      (node (ref "C16") (pin "2") (pinfunction "2_2") (pintype "passive"))
      (node (ref "C17") (pin "1") (pinfunction "1_1") (pintype "passive"))
      (node (ref "C18") (pin "2") (pinfunction "2_2") (pintype "passive"))
      (node (ref "C19") (pin "1") (pinfunction "1_1") (pintype "passive"))
      (node (ref "C3_AL") (pin "2") (pinfunction "2_2") (pintype "passive"))
      (node (ref "C3_CY") (pin "2") (pinfunction "2_2") (pintype "passive"))
      (node (ref "C3_DR") (pin "2") (pinfunction "2_2") (pintype "passive"))
      (node (ref "C3_HL") (pin "2") (pinfunction "2_2") (pintype "passive"))
      (node (ref "C3_MC1") (pin "2") (pinfunction "2_2") (pintype "passive"))
      (node (ref "C3_MC2") (pin "2") (pinfunction "2_2") (pintype "passive"))
      (node (ref "C3_PRB") (pin "2") (pinfunction "2_2") (pintype "passive"))
      (node (ref "C3_TLO") (pin "2") (pinfunction "2_2") (pintype "passive"))
      (node (ref "C3_XL") (pin "2") (pinfunction "2_2") (pintype "passive"))
      (node (ref "C3_Y1L") (pin "2") (pinfunction "2_2") (pintype "passive"))
      (node (ref "C3_Y2L") (pin "2") (pinfunction "2_2") (pintype "passive"))
      (node (ref "C3_ZL") (pin "2") (pinfunction "2_2") (pintype "passive"))
      (node (ref "C4") (pin "2") (pinfunction "2_2") (pintype "passive"))
      (node (ref "C40") (pin "2") (pinfunction "2_2") (pintype "passive"))
      (node (ref "C41") (pin "2") (pinfunction "2_2") (pintype "passive"))
      (node (ref "C44") (pin "2") (pinfunction "2_2") (pintype "passive"))
      (node (ref "C45") (pin "2") (pinfunction "2_2") (pintype "passive"))
      (node (ref "C46") (pin "2") (pinfunction "2_2") (pintype "passive"))
      (node (ref "C47") (pin "2") (pinfunction "2_2") (pintype "passive"))
      (node (ref "C49") (pin "2") (pinfunction "2_2") (pintype "passive"))
      (node (ref "C5") (pin "2") (pinfunction "2_2") (pintype "passive"))
      (node (ref "C52") (pin "2") (pinfunction "2_2") (pintype "passive"))
      (node (ref "C53") (pin "2") (pinfunction "2_2") (pintype "passive"))
      (node (ref "C54") (pin "2") (pinfunction "2_2") (pintype "passive"))
      (node (ref "C58") (pin "2") (pinfunction "2_2") (pintype "passive"))
      (node (ref "C59") (pin "2") (pinfunction "2_2") (pintype "passive"))
      (node (ref "C6") (pin "2") (pinfunction "2_2") (pintype "passive"))
      (node (ref "C60") (pin "2") (pinfunction "2_2") (pintype "passive"))
      (node (ref "C67") (pin "2") (pinfunction "2_2") (pintype "passive"))
      (node (ref "C69") (pin "2") (pinfunction "2_2") (pintype "passive"))
      (node (ref "C7") (pin "2") (pinfunction "2_2") (pintype "passive"))
      (node (ref "C71") (pin "2") (pinfunction "2_2") (pintype "passive"))
      (node (ref "C74") (pin "2") (pinfunction "2_2") (pintype "passive"))
      (node (ref "C75") (pin "2") (pinfunction "2_2") (pintype "passive"))
      (node (ref "C76") (pin "2") (pinfunction "2_2") (pintype "passive"))
      (node (ref "C77") (pin "2") (pinfunction "2_2") (pintype "passive"))
      (node (ref "C78") (pin "2") (pinfunction "2_2") (pintype "passive"))
      (node (ref "C79") (pin "2") (pinfunction "2_2") (pintype "passive"))
      (node (ref "C80") (pin "2") (pinfunction "2_2") (pintype "passive"))
      (node (ref "C82") (pin "1") (pinfunction "1_1") (pintype "passive"))
      (node (ref "C84") (pin "2") (pinfunction "2_2") (pintype "passive"))
      (node (ref "C87") (pin "2") (pinfunction "2_2") (pintype "passive"))
      (node (ref "C88") (pin "2") (pinfunction "2_2") (pintype "passive"))
      (node (ref "C89") (pin "2") (pinfunction "2_2") (pintype "passive"))
      (node (ref "C90") (pin "2") (pinfunction "2_2") (pintype "passive"))
      (node (ref "C92") (pin "2") (pinfunction "2_2") (pintype "passive"))
      (node (ref "C93") (pin "2") (pinfunction "2_2") (pintype "passive"))
      (node (ref "C94") (pin "2") (pinfunction "2_2") (pintype "passive"))
      (node (ref "C95") (pin "2") (pinfunction "2_2") (pintype "passive"))
      (node (ref "C96") (pin "2") (pinfunction "2_2") (pintype "passive"))
      (node (ref "C99") (pin "2") (pinfunction "2_2") (pintype "passive"))
      (node (ref "D19") (pin "2") (pinfunction "A_2") (pintype "passive"))
      (node (ref "D21") (pin "A") (pinfunction "A_A") (pintype "passive"))
      (node (ref "D22") (pin "A") (pinfunction "A_A") (pintype "passive"))
      (node (ref "D35") (pin "1") (pinfunction "1_1") (pintype "passive"))
      (node (ref "D46") (pin "A") (pinfunction "A_A") (pintype "passive"))
      (node (ref "D48") (pin "2") (pinfunction "A_2") (pintype "passive"))
      (node (ref "D49") (pin "A") (pinfunction "A_A") (pintype "passive"))
      (node (ref "D50") (pin "A") (pinfunction "A_A") (pintype "passive"))
      (node (ref "D54") (pin "1") (pinfunction "1_1") (pintype "passive"))
      (node (ref "D55") (pin "1") (pinfunction "1_1") (pintype "passive"))
      (node (ref "J1") (pin "11") (pinfunction "11_11") (pintype "bidirectional"))
      (node (ref "J1") (pin "15") (pinfunction "15_15") (pintype "bidirectional"))
      (node (ref "J1") (pin "3") (pinfunction "3_3") (pintype "bidirectional"))
      (node (ref "J1") (pin "7") (pinfunction "7_7") (pintype "bidirectional"))
      (node (ref "J11") (pin "01") (pinfunction "01_01") (pintype "passive"))
      (node (ref "J15") (pin "3") (pinfunction "3_3") (pintype "passive"))
      (node (ref "J17") (pin "1") (pinfunction "1_1") (pintype "passive"))
      (node (ref "J18") (pin "3") (pinfunction "3_3") (pintype "passive"))
      (node (ref "J19") (pin "2") (pinfunction "2_2") (pintype "passive"))
      (node (ref "J2") (pin "1") (pinfunction "1_1") (pintype "bidirectional"))
      (node (ref "J21") (pin "3") (pinfunction "3_3") (pintype "passive"))
      (node (ref "J3") (pin "1") (pinfunction "1_1") (pintype "passive"))
      (node (ref "J4") (pin "3") (pinfunction "3_3") (pintype "passive"))
      (node (ref "J5") (pin "3") (pinfunction "3_3") (pintype "passive"))
      (node (ref "J6") (pin "3") (pinfunction "3_3") (pintype "passive"))
      (node (ref "J7") (pin "3") (pinfunction "3_3") (pintype "passive"))
      (node (ref "J8") (pin "3") (pinfunction "3_3") (pintype "passive"))
      (node (ref "J9") (pin "05") (pinfunction "05_05") (pintype "passive"))
      (node (ref "K1_TR1") (pin "2") (pinfunction "2_2") (pintype "bidirectional"))
      (node (ref "K1_TR2") (pin "2") (pinfunction "2_2") (pintype "bidirectional"))
      (node (ref "L11") (pin "1") (pinfunction "1_1") (pintype "passive"))
      (node (ref "L2") (pin "1") (pinfunction "1_1") (pintype "passive"))
      (node (ref "L9") (pin "1") (pinfunction "1_1") (pintype "passive"))
      (node (ref "P1") (pin "1") (pinfunction "1_1") (pintype "passive"))
      (node (ref "P10") (pin "2") (pinfunction "1_2") (pintype "passive"))
      (node (ref "P11") (pin "16") (pinfunction "16_16") (pintype "passive"))
      (node (ref "P11") (pin "17") (pinfunction "17_17") (pintype "passive"))
      (node (ref "P11") (pin "20") (pinfunction "20_20") (pintype "passive"))
      (node (ref "P11") (pin "23") (pinfunction "23_23") (pintype "passive"))
      (node (ref "P11") (pin "24") (pinfunction "24_24") (pintype "passive"))
      (node (ref "P11") (pin "28") (pinfunction "28_28") (pintype "passive"))
      (node (ref "P11") (pin "29") (pinfunction "29_29") (pintype "passive"))
      (node (ref "P11") (pin "3") (pinfunction "3_3") (pintype "passive"))
      (node (ref "P11") (pin "32") (pinfunction "32_32") (pintype "passive"))
      (node (ref "P11") (pin "35") (pinfunction "35_35") (pintype "passive"))
      (node (ref "P11") (pin "36") (pinfunction "36_36") (pintype "passive"))
      (node (ref "P11") (pin "4") (pinfunction "4_4") (pintype "passive"))
      (node (ref "P13") (pin "7") (pinfunction "7_7") (pintype "passive"))
      (node (ref "P14") (pin "7") (pinfunction "7_7") (pintype "passive"))
      (node (ref "P16") (pin "7") (pinfunction "7_7") (pintype "passive"))
      (node (ref "P17") (pin "01") (pinfunction "01_01") (pintype "passive"))
      (node (ref "P19") (pin "1") (pinfunction "1_1") (pintype "passive"))
      (node (ref "P2") (pin "1") (pinfunction "1_1") (pintype "passive"))
      (node (ref "P20") (pin "2") (pinfunction "2_2") (pintype "passive"))
      (node (ref "P20") (pin "4") (pinfunction "4_4") (pintype "passive"))
      (node (ref "P20") (pin "6") (pinfunction "6_6") (pintype "passive"))
      (node (ref "P20") (pin "7") (pinfunction "7_7") (pintype "passive"))
      (node (ref "P24") (pin "01") (pinfunction "01_01") (pintype "passive"))
      (node (ref "P27") (pin "7") (pinfunction "7_7") (pintype "passive"))
      (node (ref "P28") (pin "1") (pinfunction "1_1") (pintype "passive"))
      (node (ref "P3") (pin "1") (pinfunction "1_1") (pintype "passive"))
      (node (ref "P4") (pin "1") (pinfunction "1_1") (pintype "passive"))
      (node (ref "Q10_RL1") (pin "P2") (pinfunction "S_P2") (pintype "passive"))
      (node (ref "Q10_RL2") (pin "P2") (pinfunction "S_P2") (pintype "passive"))
      (node (ref "Q13") (pin "P2") (pinfunction "S_P2") (pintype "passive"))
      (node (ref "Q15") (pin "1") (pinfunction "SOURCE_1") (pintype "passive"))
      (node (ref "Q15") (pin "2") (pinfunction "SOURCE_2") (pintype "passive"))
      (node (ref "Q15") (pin "3") (pinfunction "SOURCE_3") (pintype "passive"))
      (node (ref "Q17") (pin "S") (pinfunction "S_S") (pintype "passive"))
      (node (ref "Q2_RL1") (pin "P2") (pinfunction "S_P2") (pintype "passive"))
      (node (ref "Q2_RL2") (pin "P2") (pinfunction "S_P2") (pintype "passive"))
      (node (ref "Q6") (pin "P2") (pinfunction "S_P2") (pintype "passive"))
      (node (ref "Q7") (pin "P2") (pinfunction "S_P2") (pintype "passive"))
      (node (ref "Q8") (pin "P2") (pinfunction "S_P2") (pintype "passive"))
      (node (ref "Q9_TR1") (pin "P2") (pinfunction "S_P2") (pintype "passive"))
      (node (ref "Q9_TR2") (pin "P2") (pinfunction "S_P2") (pintype "passive"))
      (node (ref "R127") (pin "2") (pinfunction "2_2") (pintype "passive"))
      (node (ref "R133") (pin "2") (pinfunction "2_2") (pintype "passive"))
      (node (ref "R143") (pin "1") (pinfunction "1_1") (pintype "passive"))
      (node (ref "R157") (pin "1") (pinfunction "1_1") (pintype "passive"))
      (node (ref "R158") (pin "1") (pinfunction "1_1") (pintype "passive"))
      (node (ref "R170") (pin "2") (pinfunction "2_2") (pintype "passive"))
      (node (ref "R171") (pin "2") (pinfunction "2_2") (pintype "passive"))
      (node (ref "R172") (pin "2") (pinfunction "2_2") (pintype "passive"))
      (node (ref "R173") (pin "1") (pinfunction "1_1") (pintype "passive"))
      (node (ref "R174_TR1") (pin "1") (pinfunction "1_1") (pintype "passive"))
      (node (ref "R174_TR2") (pin "1") (pinfunction "1_1") (pintype "passive"))
      (node (ref "R178") (pin "1") (pinfunction "1_1") (pintype "passive"))
      (node (ref "R179") (pin "2") (pinfunction "2_2") (pintype "passive"))
      (node (ref "R180") (pin "2") (pinfunction "2_2") (pintype "passive"))
      (node (ref "R181") (pin "1") (pinfunction "1_1") (pintype "passive"))
      (node (ref "R182") (pin "1") (pinfunction "1_1") (pintype "passive"))
      (node (ref "R202") (pin "2") (pinfunction "2_2") (pintype "passive"))
      (node (ref "R203") (pin "2") (pinfunction "2_2") (pintype "passive"))
      (node (ref "R204") (pin "2") (pinfunction "2_2") (pintype "passive"))
      (node (ref "R209") (pin "2") (pinfunction "2_2") (pintype "passive"))
      (node (ref "R26") (pin "2") (pinfunction "2_2") (pintype "passive"))
      (node (ref "R43") (pin "2") (pinfunction "2_2") (pintype "passive"))
      (node (ref "R57") (pin "2") (pinfunction "2_2") (pintype "passive"))
      (node (ref "R77_AO0") (pin "2") (pinfunction "2_2") (pintype "passive"))
      (node (ref "R77_AO1") (pin "2") (pinfunction "2_2") (pintype "passive"))
      (node (ref "R77_AO2") (pin "2") (pinfunction "2_2") (pintype "passive"))
      (node (ref "R77_AO3") (pin "2") (pinfunction "2_2") (pintype "passive"))
      (node (ref "R77_COO") (pin "2") (pinfunction "2_2") (pintype "passive"))
      (node (ref "R77_MIS") (pin "2") (pinfunction "2_2") (pintype "passive"))
      (node (ref "R82") (pin "2") (pinfunction "2_2") (pintype "passive"))
      (node (ref "R83") (pin "2") (pinfunction "2_2") (pintype "passive"))
      (node (ref "R89_RL1") (pin "1") (pinfunction "1_1") (pintype "passive"))
      (node (ref "R89_RL2") (pin "1") (pinfunction "1_1") (pintype "passive"))
      (node (ref "S1") (pin "LEFT") (pinfunction "LEFT_LEFT") (pintype "bidirectional"))
      (node (ref "U11") (pin "14") (pinfunction "AGND_14") (pintype "power_in"))
      (node (ref "U11") (pin "16") (pinfunction "AGND_16") (pintype "power_in"))
      (node (ref "U11") (pin "19") (pinfunction "AGND_19") (pintype "power_in"))
      (node (ref "U11") (pin "29") (pinfunction "GND_29") (pintype "passive"))
      (node (ref "U11") (pin "3") (pinfunction "AGND_3") (pintype "power_in"))
      (node (ref "U11") (pin "48") (pinfunction "AGND_48") (pintype "power_in"))
      (node (ref "U11") (pin "9") (pinfunction "AGND_9") (pintype "power_in"))
      (node (ref "U14") (pin "5") (pinfunction "GND2_5") (pintype "passive"))
      (node (ref "U16") (pin "7") (pinfunction "GND_7") (pintype "power_in"))
      (node (ref "U20") (pin "5") (pinfunction "GND2_5") (pintype "bidirectional"))
      (node (ref "U23") (pin "2") (pinfunction "C_2") (pintype "passive"))
      (node (ref "U24") (pin "12") (pinfunction "PGND_12") (pintype "power_in"))
      (node (ref "U24") (pin "15") (pinfunction "EP_2_15") (pintype "power_in"))
      (node (ref "U24") (pin "16") (pinfunction "NC_16") (pintype "passive"))
      (node (ref "U24") (pin "21") (pinfunction "EP_21") (pintype "power_in"))
      (node (ref "U24") (pin "6") (pinfunction "AGND_6") (pintype "power_in"))
      (node (ref "U24") (pin "9") (pinfunction "NC_2_9") (pintype "passive"))
      (node (ref "U25") (pin "3") (pinfunction "GND_3") (pintype "passive"))
      (node (ref "U26") (pin "5") (pinfunction "GND2_5") (pintype "passive"))
      (node (ref "U27") (pin "5") (pinfunction "GND2_5") (pintype "passive"))
      (node (ref "U28") (pin "3") (pinfunction "VSS_3") (pintype "bidirectional"))
      (node (ref "U2_AL") (pin "3") (pinfunction "ET_3") (pintype "passive"))
      (node (ref "U2_CY") (pin "3") (pinfunction "ET_3") (pintype "passive"))
      (node (ref "U2_DR") (pin "3") (pinfunction "ET_3") (pintype "passive"))
      (node (ref "U2_HL") (pin "3") (pinfunction "ET_3") (pintype "passive"))
      (node (ref "U2_MC1") (pin "3") (pinfunction "ET_3") (pintype "passive"))
      (node (ref "U2_MC2") (pin "3") (pinfunction "ET_3") (pintype "passive"))
      (node (ref "U2_PRB") (pin "3") (pinfunction "ET_3") (pintype "passive"))
      (node (ref "U2_TLO") (pin "3") (pinfunction "ET_3") (pintype "passive"))
      (node (ref "U2_XL") (pin "3") (pinfunction "ET_3") (pintype "passive"))
      (node (ref "U2_Y1L") (pin "3") (pinfunction "ET_3") (pintype "passive"))
      (node (ref "U2_Y2L") (pin "3") (pinfunction "ET_3") (pintype "passive"))
      (node (ref "U2_ZL") (pin "3") (pinfunction "ET_3") (pintype "passive"))
      (node (ref "U3") (pin "2") (pinfunction "GND_2") (pintype "power_in"))
      (node (ref "U32") (pin "3") (pinfunction "ET_3") (pintype "passive"))
      (node (ref "U34_N0") (pin "3") (pinfunction "ET_3") (pintype "passive"))
      (node (ref "U34_N1") (pin "3") (pinfunction "ET_3") (pintype "passive"))
      (node (ref "U34_N2") (pin "3") (pinfunction "ET_3") (pintype "passive"))
      (node (ref "U34_N3") (pin "3") (pinfunction "ET_3") (pintype "passive"))
      (node (ref "U36") (pin "12") (pinfunction "~{G}_12") (pintype "input"))
      (node (ref "U36") (pin "8") (pinfunction "GND_8") (pintype "power_in"))
      (node (ref "U37") (pin "5") (pinfunction "GND2_5") (pintype "passive"))
      (node (ref "U38") (pin "5") (pinfunction "GND2_5") (pintype "passive"))
      (node (ref "U40") (pin "4") (pinfunction "GND_4") (pintype "power_in"))
      (node (ref "U41") (pin "2") (pinfunction "GND_2") (pintype "power_in"))
      (node (ref "U42") (pin "7") (pinfunction "GND_7") (pintype "power_in"))
      (node (ref "U43") (pin "2") (pinfunction "C_2") (pintype "passive"))
      (node (ref "U44") (pin "3") (pinfunction "GND_3") (pintype "power_in"))
      (node (ref "U45") (pin "5") (pinfunction "GND2_5") (pintype "passive"))
      (node (ref "U46") (pin "5") (pinfunction "GND2_5") (pintype "passive"))
      (node (ref "U5") (pin "3") (pinfunction "ET_3") (pintype "passive"))
      (node (ref "U50") (pin "1") (pinfunction "GND_1") (pintype "power_in"))
      (node (ref "U6") (pin "3") (pinfunction "ET_3") (pintype "passive"))
      (node (ref "U9") (pin "12") (pinfunction "~{G}_12") (pintype "input"))
      (node (ref "U9") (pin "8") (pinfunction "GND_8") (pintype "power_in"))
      (node (ref "VR1") (pin "1") (pinfunction "ADJ/GND_1") (pintype "bidirectional"))
      (node (ref "Y3") (pin "2") (pinfunction "GND_2") (pintype "power_in"))
      (node (ref "Y3") (pin "4") (pinfunction "GND_4") (pintype "power_in"))
    )
    (net (code "75") (name "GND\\") (class "Default")
      (node (ref "D53") (pin "1") (pinfunction "1_1") (pintype "passive"))
    )
    (net (code "76") (name "GRN_LED") (class "Default")
      (node (ref "R148") (pin "2") (pinfunction "2_2") (pintype "passive"))
      (node (ref "U11") (pin "25") (pinfunction "LINKLED_25") (pintype "output"))
    )
    (net (code "77") (name "HALT") (class "Default")
      (node (ref "TP20") (pin "TP") (pinfunction "TP_TP") (pintype "input"))
      (node (ref "U1") (pin "2") (pinfunction "B_2") (pintype "input"))
    )
    (net (code "78") (name "HALT_EXT") (class "Default")
      (node (ref "D32") (pin "C") (pinfunction "C_C") (pintype "passive"))
      (node (ref "Q3") (pin "P3") (pinfunction "D_P3") (pintype "passive"))
      (node (ref "R38") (pin "2") (pinfunction "2_2") (pintype "passive"))
      (node (ref "U2_HL") (pin "2") (pinfunction "C_2") (pintype "passive"))
    )
    (net (code "79") (name "HALT_N") (class "Default")
      (node (ref "C1") (pin "1") (pinfunction "1_1") (pintype "passive"))
      (node (ref "C3_HL") (pin "1") (pinfunction "1_1") (pintype "passive"))
      (node (ref "P8") (pin "3") (pinfunction "3_3") (pintype "passive"))
      (node (ref "R21") (pin "2") (pinfunction "2_2") (pintype "passive"))
      (node (ref "R22_HL") (pin "2") (pinfunction "2_2") (pintype "passive"))
      (node (ref "R8") (pin "1") (pinfunction "1_1") (pintype "passive"))
      (node (ref "TP19") (pin "TP") (pinfunction "TP_TP") (pintype "input"))
      (node (ref "U1") (pin "4") (pinfunction "Y_4") (pintype "output"))
      (node (ref "U17") (pin "51") (pinfunction "PB12_51") (pintype "bidirectional"))
      (node (ref "U2_HL") (pin "4") (pinfunction "CT_4") (pintype "passive"))
    )
    (net (code "80") (name "HALT_PEN") (class "Default")
      (node (ref "J14") (pin "4") (pinfunction "4_4") (pintype "passive"))
      (node (ref "U21") (pin "2") (pinfunction "C_2") (pintype "passive"))
    )
    (net (code "81") (name "HALT_PENDANT") (class "Default")
      (node (ref "C65") (pin "1") (pinfunction "1_1") (pintype "passive"))
      (node (ref "R90") (pin "1") (pinfunction "1_1") (pintype "passive"))
      (node (ref "TP18") (pin "TP") (pinfunction "TP_TP") (pintype "input"))
      (node (ref "U1") (pin "1") (pinfunction "A_1") (pintype "input"))
      (node (ref "U21") (pin "4") (pinfunction "CT_4") (pintype "passive"))
    )
    (net (code "82") (name "INPUT_INRUSH") (class "Default")
      (node (ref "Q1") (pin "3") (pinfunction "D_3") (pintype "passive"))
      (node (ref "R104") (pin "2") (pinfunction "2_2") (pintype "passive"))
      (node (ref "R126") (pin "1") (pinfunction "1_1") (pintype "passive"))
      (node (ref "U41") (pin "4") (pinfunction "IN+_4") (pintype "tri_state"))
    )
    (net (code "83") (name "INPUT_VCC") (class "Default")
      (node (ref "C87") (pin "1") (pinfunction "1_1") (pintype "passive"))
      (node (ref "C88") (pin "1") (pinfunction "1_1") (pintype "passive"))
      (node (ref "C89") (pin "1") (pinfunction "1_1") (pintype "passive"))
      (node (ref "C90") (pin "1") (pinfunction "1_1") (pintype "passive"))
      (node (ref "D36") (pin "C") (pinfunction "C_C") (pintype "passive"))
      (node (ref "D50") (pin "C") (pinfunction "C_C") (pintype "passive"))
      (node (ref "L7") (pin "1") (pinfunction "1_1") (pintype "passive"))
      (node (ref "P10") (pin "1") (pinfunction "1_1") (pintype "passive"))
      (node (ref "Q1") (pin "2") (pinfunction "S_2") (pintype "passive"))
      (node (ref "R127") (pin "1") (pinfunction "1_1") (pintype "passive"))
      (node (ref "R159") (pin "1") (pinfunction "1_1") (pintype "passive"))
      (node (ref "R197") (pin "1") (pinfunction "1_1") (pintype "passive"))
    )
    (net (code "84") (name "KPSTR") (class "Default")
      (node (ref "C66") (pin "1") (pinfunction "1_1") (pintype "passive"))
      (node (ref "P8") (pin "4") (pinfunction "4_4") (pintype "passive"))
      (node (ref "R92") (pin "1") (pinfunction "1_1") (pintype "passive"))
      (node (ref "U22") (pin "4") (pinfunction "CT_4") (pintype "passive"))
    )
    (net (code "85") (name "KPSTR_PEN") (class "Default")
      (node (ref "J14") (pin "5") (pinfunction "5_5") (pintype "passive"))
      (node (ref "U22") (pin "2") (pinfunction "C_2") (pintype "passive"))
    )
    (net (code "86") (name "LASER_EN") (class "Default")
      (node (ref "Q12") (pin "P1") (pinfunction "G_P1") (pintype "passive"))
      (node (ref "R166") (pin "1") (pinfunction "1_1") (pintype "passive"))
      (node (ref "R37") (pin "2") (pinfunction "2_2") (pintype "passive"))
      (node (ref "TP57") (pin "TP") (pinfunction "TP_TP") (pintype "input"))
      (node (ref "U17") (pin "80") (pinfunction "PC12/SPI3_MOSI/UART5_TX_80") (pintype "bidirectional"))
    )
    (net (code "87") (name "LASER_EN_EXT") (class "Default")
      (node (ref "J11") (pin "03") (pinfunction "03_03") (pintype "passive"))
      (node (ref "R168") (pin "1") (pinfunction "1_1") (pintype "passive"))
      (node (ref "U8") (pin "3") (pinfunction "ET_3") (pintype "passive"))
    )
    (net (code "88") (name "LASER_PWM") (class "Default")
      (node (ref "Q5") (pin "P1") (pinfunction "G_P1") (pintype "passive"))
      (node (ref "R154") (pin "2") (pinfunction "2_2") (pintype "passive"))
      (node (ref "R41") (pin "2") (pinfunction "2_2") (pintype "passive"))
      (node (ref "TP59") (pin "TP") (pinfunction "TP_TP") (pintype "input"))
      (node (ref "U17") (pin "63") (pinfunction "PC6/TIM3_CH1/USART6_TX_63") (pintype "bidirectional"))
    )
    (net (code "89") (name "LASER_PWM_EXT") (class "Default")
      (node (ref "J11") (pin "02") (pinfunction "02_02") (pintype "passive"))
      (node (ref "U3") (pin "6") (pinfunction "1Y_6") (pintype "output"))
    )
    (net (code "90") (name "LASER_PWM_ISO") (class "Default")
      (node (ref "R169") (pin "1") (pinfunction "1_1") (pintype "passive"))
      (node (ref "U10") (pin "3") (pinfunction "ET_3") (pintype "passive"))
      (node (ref "U3") (pin "1") (pinfunction "1A_1") (pintype "input"))
    )
    (net (code "91") (name "LED_CONTROL_OUT") (class "Default")
      (node (ref "J21") (pin "2") (pinfunction "2_2") (pintype "passive"))
      (node (ref "U28") (pin "2") (pinfunction "DO_2") (pintype "bidirectional"))
    )
    (net (code "92") (name "LED_POWER_OUT") (class "Default")
      (node (ref "J21") (pin "1") (pinfunction "1_1") (pintype "passive"))
      (node (ref "P19") (pin "2") (pinfunction "2_2") (pintype "passive"))
      (node (ref "P5") (pin "2") (pinfunction "2_2") (pintype "passive"))
    )
    (net (code "93") (name "LIMIT_VCC_SEL") (class "Default")
      (node (ref "J15") (pin "4") (pinfunction "4_4") (pintype "passive"))
      (node (ref "J2") (pin "3") (pinfunction "3_3") (pintype "bidirectional"))
      (node (ref "J4") (pin "4") (pinfunction "4_4") (pintype "passive"))
      (node (ref "J5") (pin "4") (pinfunction "4_4") (pintype "passive"))
      (node (ref "J6") (pin "4") (pinfunction "4_4") (pintype "passive"))
      (node (ref "J7") (pin "4") (pinfunction "4_4") (pintype "passive"))
      (node (ref "J8") (pin "4") (pinfunction "4_4") (pintype "passive"))
      (node (ref "P17") (pin "07") (pinfunction "07_07") (pintype "passive"))
      (node (ref "R10") (pin "2") (pinfunction "2_2") (pintype "passive"))
      (node (ref "R23_AL") (pin "2") (pinfunction "2_2") (pintype "passive"))
      (node (ref "R23_DR") (pin "2") (pinfunction "2_2") (pintype "passive"))
      (node (ref "R23_PRB") (pin "2") (pinfunction "2_2") (pintype "passive"))
      (node (ref "R23_TLO") (pin "2") (pinfunction "2_2") (pintype "passive"))
      (node (ref "R23_XL") (pin "2") (pinfunction "2_2") (pintype "passive"))
      (node (ref "R23_Y1L") (pin "2") (pinfunction "2_2") (pintype "passive"))
      (node (ref "R23_Y2L") (pin "2") (pinfunction "2_2") (pintype "passive"))
      (node (ref "R23_ZL") (pin "2") (pinfunction "2_2") (pintype "passive"))
      (node (ref "R9") (pin "2") (pinfunction "2_2") (pintype "passive"))
    )
    (net (code "94") (name "MACRO1") (class "Default")
      (node (ref "C3_MC1") (pin "1") (pinfunction "1_1") (pintype "passive"))
      (node (ref "R18") (pin "2") (pinfunction "2_2") (pintype "passive"))
      (node (ref "R22_MC1") (pin "2") (pinfunction "2_2") (pintype "passive"))
      (node (ref "TP16") (pin "TP") (pinfunction "TP_TP") (pintype "input"))
      (node (ref "U17") (pin "98") (pinfunction "PE1_98") (pintype "bidirectional"))
      (node (ref "U2_MC1") (pin "4") (pinfunction "CT_4") (pintype "passive"))
    )
    (net (code "95") (name "MACRO1_EXT") (class "Default")
      (node (ref "P24") (pin "04") (pinfunction "04_04") (pintype "passive"))
      (node (ref "U2_MC1") (pin "2") (pinfunction "C_2") (pintype "passive"))
    )
    (net (code "96") (name "MACRO2") (class "Default")
      (node (ref "C3_MC2") (pin "1") (pinfunction "1_1") (pintype "passive"))
      (node (ref "R19") (pin "2") (pinfunction "2_2") (pintype "passive"))
      (node (ref "R22_MC2") (pin "2") (pinfunction "2_2") (pintype "passive"))
      (node (ref "TP17") (pin "TP") (pinfunction "TP_TP") (pintype "input"))
      (node (ref "U17") (pin "97") (pinfunction "PE0/TIM4_ETR_97") (pintype "bidirectional"))
      (node (ref "U2_MC2") (pin "4") (pinfunction "CT_4") (pintype "passive"))
    )
    (net (code "97") (name "MACRO2_EXT") (class "Default")
      (node (ref "P24") (pin "03") (pinfunction "03_03") (pintype "passive"))
      (node (ref "U2_MC2") (pin "2") (pinfunction "C_2") (pintype "passive"))
    )
    (net (code "98") (name "MACRO3") (class "Default")
      (node (ref "C3_CY") (pin "1") (pinfunction "1_1") (pintype "passive"))
      (node (ref "R20") (pin "2") (pinfunction "2_2") (pintype "passive"))
      (node (ref "R22_CY") (pin "2") (pinfunction "2_2") (pintype "passive"))
      (node (ref "U17") (pin "79") (pinfunction "PC11/SPI3_MISO/UART4_RX_79") (pintype "bidirectional"))
      (node (ref "U2_CY") (pin "4") (pinfunction "CT_4") (pintype "passive"))
    )
    (net (code "99") (name "MCU_GND") (class "Default")
      (node (ref "C1") (pin "2") (pinfunction "2_2") (pintype "passive"))
      (node (ref "C100") (pin "2") (pinfunction "2_2") (pintype "passive"))
      (node (ref "C101") (pin "2") (pinfunction "2_2") (pintype "passive"))
      (node (ref "C102") (pin "2") (pinfunction "2_2") (pintype "passive"))
      (node (ref "C119") (pin "2") (pinfunction "2_2") (pintype "passive"))
      (node (ref "C134") (pin "2") (pinfunction "2_2") (pintype "passive"))
      (node (ref "C136") (pin "2") (pinfunction "2_2") (pintype "passive"))
      (node (ref "C137") (pin "2") (pinfunction "2_2") (pintype "passive"))
      (node (ref "C138") (pin "2") (pinfunction "2_2") (pintype "passive"))
      (node (ref "C2") (pin "2") (pinfunction "2_2") (pintype "passive"))
      (node (ref "C20") (pin "2") (pinfunction "2_2") (pintype "passive"))
      (node (ref "C21") (pin "2") (pinfunction "2_2") (pintype "passive"))
      (node (ref "C22") (pin "2") (pinfunction "2_2") (pintype "passive"))
      (node (ref "C23") (pin "2") (pinfunction "2_2") (pintype "passive"))
      (node (ref "C24") (pin "2") (pinfunction "2_2") (pintype "passive"))
      (node (ref "C27") (pin "2") (pinfunction "2_2") (pintype "passive"))
      (node (ref "C28") (pin "2") (pinfunction "2_2") (pintype "passive"))
      (node (ref "C29") (pin "2") (pinfunction "2_2") (pintype "passive"))
      (node (ref "C30") (pin "2") (pinfunction "2_2") (pintype "passive"))
      (node (ref "C31") (pin "2") (pinfunction "2_2") (pintype "passive"))
      (node (ref "C32") (pin "2") (pinfunction "2_2") (pintype "passive"))
      (node (ref "C33") (pin "2") (pinfunction "2_2") (pintype "passive"))
      (node (ref "C34") (pin "2") (pinfunction "2_2") (pintype "passive"))
      (node (ref "C35") (pin "2") (pinfunction "2_2") (pintype "passive"))
      (node (ref "C36") (pin "2") (pinfunction "2_2") (pintype "passive"))
      (node (ref "C37") (pin "2") (pinfunction "2_2") (pintype "passive"))
      (node (ref "C38") (pin "2") (pinfunction "2_2") (pintype "passive"))
      (node (ref "C39") (pin "2") (pinfunction "2_2") (pintype "passive"))
      (node (ref "C42") (pin "2") (pinfunction "2_2") (pintype "passive"))
      (node (ref "C43") (pin "2") (pinfunction "2_2") (pintype "passive"))
      (node (ref "C48") (pin "2") (pinfunction "2_2") (pintype "passive"))
      (node (ref "C50") (pin "2") (pinfunction "2_2") (pintype "passive"))
      (node (ref "C51") (pin "2") (pinfunction "2_2") (pintype "passive"))
      (node (ref "C55") (pin "2") (pinfunction "2_2") (pintype "passive"))
      (node (ref "C56") (pin "2") (pinfunction "2_2") (pintype "passive"))
      (node (ref "C57") (pin "-") (pinfunction "-_-") (pintype "passive"))
      (node (ref "C62") (pin "2") (pinfunction "2_2") (pintype "passive"))
      (node (ref "C65") (pin "2") (pinfunction "2_2") (pintype "passive"))
      (node (ref "C66") (pin "2") (pinfunction "2_2") (pintype "passive"))
      (node (ref "C68") (pin "2") (pinfunction "2_2") (pintype "passive"))
      (node (ref "C70") (pin "2") (pinfunction "2_2") (pintype "passive"))
      (node (ref "C72") (pin "2") (pinfunction "2_2") (pintype "passive"))
      (node (ref "C73") (pin "2") (pinfunction "2_2") (pintype "passive"))
      (node (ref "C97") (pin "2") (pinfunction "2_2") (pintype "passive"))
      (node (ref "C98") (pin "2") (pinfunction "2_2") (pintype "passive"))
      (node (ref "D1") (pin "A") (pinfunction "+_A") (pintype "passive"))
      (node (ref "D23") (pin "A") (pinfunction "A_A") (pintype "passive"))
      (node (ref "D27") (pin "2") (pinfunction "GND_2") (pintype "power_in"))
      (node (ref "D42") (pin "A") (pinfunction "+_A") (pintype "passive"))
      (node (ref "J13") (pin "1") (pinfunction "1_1") (pintype "passive"))
      (node (ref "J20") (pin "GND") (pinfunction "GND_GND") (pintype "bidirectional"))
      (node (ref "J20") (pin "GND2") (pinfunction "GND_GND2") (pintype "bidirectional"))
      (node (ref "J20") (pin "SHLD1") (pinfunction "SHLD_SHLD1") (pintype "bidirectional"))
      (node (ref "J20") (pin "SHLD2") (pinfunction "SHLD_SHLD2") (pintype "bidirectional"))
      (node (ref "J20") (pin "SHLD3") (pinfunction "SHLD_SHLD3") (pintype "bidirectional"))
      (node (ref "J20") (pin "SHLD4") (pinfunction "SHLD_SHLD4") (pintype "bidirectional"))
      (node (ref "J20") (pin "SHLD5") (pinfunction "SHLD_SHLD5") (pintype "bidirectional"))
      (node (ref "J20") (pin "SHLD6") (pinfunction "SHLD_SHLD6") (pintype "bidirectional"))
      (node (ref "J20") (pin "SHLD7") (pinfunction "SHLD_SHLD7") (pintype "bidirectional"))
      (node (ref "J20") (pin "SHLD8") (pinfunction "SHLD_SHLD8") (pintype "bidirectional"))
      (node (ref "L9") (pin "2") (pinfunction "2_2") (pintype "passive"))
      (node (ref "P15") (pin "3") (pinfunction "2_3") (pintype "passive"))
      (node (ref "P15") (pin "5") (pinfunction "3_5") (pintype "passive"))
      (node (ref "P26") (pin "1") (pinfunction "1_1") (pintype "passive"))
      (node (ref "P8") (pin "5") (pinfunction "5_5") (pintype "passive"))
      (node (ref "P9") (pin "4") (pinfunction "4_4") (pintype "passive"))
      (node (ref "Q11") (pin "P2") (pinfunction "S_P2") (pintype "passive"))
      (node (ref "Q12") (pin "P2") (pinfunction "S_P2") (pintype "passive"))
      (node (ref "Q3") (pin "P2") (pinfunction "S_P2") (pintype "passive"))
      (node (ref "Q4") (pin "P2") (pinfunction "S_P2") (pintype "passive"))
      (node (ref "Q5") (pin "P2") (pinfunction "S_P2") (pintype "passive"))
      (node (ref "R102") (pin "1") (pinfunction "1_1") (pintype "passive"))
      (node (ref "R107") (pin "1") (pinfunction "1_1") (pintype "passive"))
      (node (ref "R108") (pin "1") (pinfunction "1_1") (pintype "passive"))
      (node (ref "R153") (pin "1") (pinfunction "1_1") (pintype "passive"))
      (node (ref "R154") (pin "1") (pinfunction "1_1") (pintype "passive"))
      (node (ref "R166") (pin "2") (pinfunction "2_2") (pintype "passive"))
      (node (ref "R168") (pin "2") (pinfunction "2_2") (pintype "passive"))
      (node (ref "R169") (pin "2") (pinfunction "2_2") (pintype "passive"))
      (node (ref "R58") (pin "1") (pinfunction "1_1") (pintype "passive"))
      (node (ref "R61") (pin "1") (pinfunction "1_1") (pintype "passive"))
      (node (ref "R69") (pin "1") (pinfunction "1_1") (pintype "passive"))
      (node (ref "R7") (pin "1") (pinfunction "1_1") (pintype "passive"))
      (node (ref "R84") (pin "2") (pinfunction "2_2") (pintype "passive"))
      (node (ref "R99") (pin "2") (pinfunction "2_2") (pintype "passive"))
      (node (ref "SD3") (pin "6") (pinfunction "VSS_6") (pintype "power_in"))
      (node (ref "SD3") (pin "S1") (pinfunction "S1_S1") (pintype "passive"))
      (node (ref "SD3") (pin "S2") (pinfunction "S2_S2") (pintype "passive"))
      (node (ref "SD3") (pin "S3") (pinfunction "S3_S3") (pintype "passive"))
      (node (ref "SD3") (pin "S4") (pinfunction "S4_S4") (pintype "passive"))
      (node (ref "U1") (pin "3") (pinfunction "GND_3") (pintype "power_in"))
      (node (ref "U12") (pin "4") (pinfunction "GND1_4") (pintype "bidirectional"))
      (node (ref "U14") (pin "4") (pinfunction "GND1_4") (pintype "passive"))
      (node (ref "U15") (pin "2") (pinfunction "C_2") (pintype "passive"))
      (node (ref "U17") (pin "10") (pinfunction "VSS_10\\_10") (pintype "power_in"))
      (node (ref "U17") (pin "20") (pinfunction "VSSA_20") (pintype "power_in"))
      (node (ref "U17") (pin "27") (pinfunction "VSS_27_27") (pintype "power_in"))
      (node (ref "U17") (pin "74") (pinfunction "VSS_74_74") (pintype "power_in"))
      (node (ref "U17") (pin "99") (pinfunction "VSS_99_99") (pintype "power_in"))
      (node (ref "U18") (pin "4") (pinfunction "GND1_4") (pintype "bidirectional"))
      (node (ref "U20") (pin "4") (pinfunction "GND1_4") (pintype "bidirectional"))
      (node (ref "U21") (pin "3") (pinfunction "ET_3") (pintype "passive"))
      (node (ref "U22") (pin "3") (pinfunction "ET_3") (pintype "passive"))
      (node (ref "U23") (pin "3") (pinfunction "ET_3") (pintype "passive"))
      (node (ref "U26") (pin "4") (pinfunction "GND1_4") (pintype "passive"))
      (node (ref "U27") (pin "4") (pinfunction "GND1_4") (pintype "passive"))
      (node (ref "U29") (pin "2") (pinfunction "C_2") (pintype "passive"))
      (node (ref "U30") (pin "2") (pinfunction "C_2") (pintype "passive"))
      (node (ref "U31") (pin "2") (pinfunction "C_2") (pintype "passive"))
      (node (ref "U33_AO0") (pin "2") (pinfunction "C_2") (pintype "passive"))
      (node (ref "U33_AO1") (pin "2") (pinfunction "C_2") (pintype "passive"))
      (node (ref "U33_AO2") (pin "2") (pinfunction "C_2") (pintype "passive"))
      (node (ref "U33_AO3") (pin "2") (pinfunction "C_2") (pintype "passive"))
      (node (ref "U33_COO") (pin "2") (pinfunction "C_2") (pintype "passive"))
      (node (ref "U33_MIS") (pin "2") (pinfunction "C_2") (pintype "passive"))
      (node (ref "U34_N0") (pin "2") (pinfunction "C_2") (pintype "passive"))
      (node (ref "U34_N1") (pin "2") (pinfunction "C_2") (pintype "passive"))
      (node (ref "U34_N2") (pin "2") (pinfunction "C_2") (pintype "passive"))
      (node (ref "U34_N3") (pin "2") (pinfunction "C_2") (pintype "passive"))
      (node (ref "U35") (pin "1") (pinfunction "A0_1") (pintype "input"))
      (node (ref "U35") (pin "2") (pinfunction "A1_2") (pintype "input"))
      (node (ref "U35") (pin "3") (pinfunction "A2_3") (pintype "input"))
      (node (ref "U35") (pin "4") (pinfunction "GND_4") (pintype "power_in"))
      (node (ref "U35") (pin "7") (pinfunction "WP_7") (pintype "input"))
      (node (ref "U37") (pin "4") (pinfunction "GND1_4") (pintype "passive"))
      (node (ref "U38") (pin "4") (pinfunction "GND1_4") (pintype "passive"))
      (node (ref "U39") (pin "3") (pinfunction "ET_3") (pintype "passive"))
      (node (ref "U4") (pin "2") (pinfunction "C_2") (pintype "passive"))
      (node (ref "U45") (pin "4") (pinfunction "GND1_4") (pintype "passive"))
      (node (ref "U46") (pin "4") (pinfunction "GND1_4") (pintype "passive"))
      (node (ref "U47") (pin "3") (pinfunction "ET_3") (pintype "passive"))
      (node (ref "U48") (pin "3") (pinfunction "ET_3") (pintype "passive"))
      (node (ref "U49") (pin "3") (pinfunction "ET_3") (pintype "passive"))
      (node (ref "U5") (pin "2") (pinfunction "C_2") (pintype "passive"))
      (node (ref "U8") (pin "2") (pinfunction "C_2") (pintype "passive"))
      (node (ref "Y1") (pin "2") (pinfunction "GND_2") (pintype "power_in"))
      (node (ref "Y1") (pin "4") (pinfunction "GND_4") (pintype "power_in"))
    )
    (net (code "100") (name "MIST") (class "Default")
      (node (ref "Q7") (pin "P1") (pinfunction "G_P1") (pintype "passive"))
      (node (ref "R122_MIS") (pin "2") (pinfunction "2_2") (pintype "passive"))
      (node (ref "R158") (pin "2") (pinfunction "2_2") (pintype "passive"))
      (node (ref "U17") (pin "90") (pinfunction "PB4/NJTRST_90") (pintype "bidirectional"))
    )
    (net (code "101") (name "MIST_5V") (class "Default")
      (node (ref "P11") (pin "33") (pinfunction "33_33") (pintype "passive"))
      (node (ref "R77_MIS") (pin "1") (pinfunction "1_1") (pintype "passive"))
      (node (ref "U33_MIS") (pin "3") (pinfunction "ET_3") (pintype "passive"))
    )
    (net (code "102") (name "MOD_GND") (class "Default")
      (node (ref "C8") (pin "2") (pinfunction "2_2") (pintype "passive"))
      (node (ref "C9") (pin "1") (pinfunction "1_1") (pintype "passive"))
      (node (ref "D16") (pin "3") (pinfunction "COM_3") (pintype "bidirectional"))
      (node (ref "D40") (pin "A") (pinfunction "+_A") (pintype "passive"))
      (node (ref "J10") (pin "01") (pinfunction "01_01") (pintype "passive"))
      (node (ref "J12") (pin "1") (pinfunction "1_1") (pintype "passive"))
      (node (ref "J12") (pin "6") (pinfunction "6_6") (pintype "passive"))
      (node (ref "L2") (pin "2") (pinfunction "2_2") (pintype "passive"))
      (node (ref "R46") (pin "1") (pinfunction "1_1") (pintype "passive"))
      (node (ref "R52") (pin "2") (pinfunction "2_2") (pintype "passive"))
      (node (ref "U12") (pin "5") (pinfunction "GND2_5") (pintype "bidirectional"))
      (node (ref "U13") (pin "5") (pinfunction "GND_5") (pintype "power_in"))
    )
    (net (code "103") (name "MOTOR_NPGD") (class "Default")
      (node (ref "Q3") (pin "P1") (pinfunction "G_P1") (pintype "passive"))
      (node (ref "U44") (pin "4") (pinfunction "Y_4") (pintype "output"))
    )
    (net (code "104") (name "MOTOR_VCC_80V") (class "Default")
      (node (ref "C91") (pin "2") (pinfunction "2_2") (pintype "passive"))
      (node (ref "D46") (pin "C") (pinfunction "C_C") (pintype "passive"))
      (node (ref "D48") (pin "1") (pinfunction "C_1") (pintype "passive"))
      (node (ref "K2") (pin "87") (pinfunction "87_87") (pintype "passive"))
      (node (ref "P1") (pin "2") (pinfunction "2_2") (pintype "passive"))
      (node (ref "P2") (pin "2") (pinfunction "2_2") (pintype "passive"))
      (node (ref "P28") (pin "2") (pinfunction "2_2") (pintype "passive"))
      (node (ref "P3") (pin "2") (pinfunction "2_2") (pintype "passive"))
      (node (ref "P4") (pin "2") (pinfunction "2_2") (pintype "passive"))
      (node (ref "R184") (pin "2") (pinfunction "2_2") (pintype "passive"))
    )
    (net (code "105") (name "NEO_LED") (class "Default")
      (node (ref "TP36") (pin "TP") (pinfunction "TP_TP") (pintype "input"))
      (node (ref "U14") (pin "2") (pinfunction "VIA_2") (pintype "input"))
      (node (ref "U17") (pin "66") (pinfunction "PC9/TIM3_CH4/I2C3_SDA_66") (pintype "bidirectional"))
    )
    (net (code "106") (name "NTC_BYP_GATE") (class "Default")
      (node (ref "D36") (pin "A") (pinfunction "A_A") (pintype "passive"))
      (node (ref "Q1") (pin "1") (pinfunction "G_1") (pintype "passive"))
      (node (ref "R103") (pin "1") (pinfunction "1_1") (pintype "passive"))
      (node (ref "R197") (pin "2") (pinfunction "2_2") (pintype "passive"))
    )
    (net (code "107") (name "Net-(C19-Pad2)") (class "Default")
      (node (ref "C19") (pin "2") (pinfunction "2_2") (pintype "passive"))
      (node (ref "R56") (pin "2") (pinfunction "2_2") (pintype "passive"))
    )
    (net (code "108") (name "Net-(C20-Pad1)") (class "Default")
      (node (ref "C20") (pin "1") (pinfunction "1_1") (pintype "passive"))
      (node (ref "R59") (pin "2") (pinfunction "2_2") (pintype "passive"))
      (node (ref "R60") (pin "1") (pinfunction "1_1") (pintype "passive"))
    )
    (net (code "109") (name "Net-(C81-Pad1)") (class "Default")
      (node (ref "C81") (pin "1") (pinfunction "1_1") (pintype "passive"))
      (node (ref "R134") (pin "2") (pinfunction "2_2") (pintype "passive"))
    )
    (net (code "110") (name "Net-(C83-Pad1)") (class "Default")
      (node (ref "C83") (pin "1") (pinfunction "1_1") (pintype "passive"))
      (node (ref "R175") (pin "1") (pinfunction "1_1") (pintype "passive"))
    )
    (net (code "111") (name "Net-(C85-Pad2)") (class "Default")
      (node (ref "C85") (pin "2") (pinfunction "2_2") (pintype "passive"))
      (node (ref "R177") (pin "2") (pinfunction "2_2") (pintype "passive"))
    )
    (net (code "112") (name "Net-(D2-PadA)") (class "Default")
      (node (ref "D2") (pin "A") (pinfunction "A_A") (pintype "passive"))
      (node (ref "R151") (pin "1") (pinfunction "1_1") (pintype "passive"))
    )
    (net (code "113") (name "Net-(D3-PadC)") (class "Default")
      (node (ref "D3") (pin "C") (pinfunction "C_C") (pintype "passive"))
      (node (ref "R11") (pin "1") (pinfunction "1_1") (pintype "passive"))
    )
    (net (code "114") (name "Net-(D4-PadC)") (class "Default")
      (node (ref "D4") (pin "C") (pinfunction "C_C") (pintype "passive"))
      (node (ref "R12") (pin "1") (pinfunction "1_1") (pintype "passive"))
    )
    (net (code "115") (name "Net-(D5-PadC)") (class "Default")
      (node (ref "D5") (pin "C") (pinfunction "C_C") (pintype "passive"))
      (node (ref "R13") (pin "1") (pinfunction "1_1") (pintype "passive"))
    )
    (net (code "116") (name "Net-(D6-PadC)") (class "Default")
      (node (ref "D6") (pin "C") (pinfunction "C_C") (pintype "passive"))
      (node (ref "R14") (pin "1") (pinfunction "1_1") (pintype "passive"))
    )
    (net (code "117") (name "Net-(D7-PadC)") (class "Default")
      (node (ref "D7") (pin "C") (pinfunction "C_C") (pintype "passive"))
      (node (ref "R15") (pin "1") (pinfunction "1_1") (pintype "passive"))
    )
    (net (code "118") (name "Net-(D8-PadC)") (class "Default")
      (node (ref "D8") (pin "C") (pinfunction "C_C") (pintype "passive"))
      (node (ref "R16") (pin "1") (pinfunction "1_1") (pintype "passive"))
    )
    (net (code "119") (name "Net-(D9-PadC)") (class "Default")
      (node (ref "D9") (pin "C") (pinfunction "C_C") (pintype "passive"))
      (node (ref "R17") (pin "1") (pinfunction "1_1") (pintype "passive"))
    )
    (net (code "120") (name "Net-(D10-PadC)") (class "Default")
      (node (ref "D10") (pin "C") (pinfunction "C_C") (pintype "passive"))
      (node (ref "R18") (pin "1") (pinfunction "1_1") (pintype "passive"))
    )
    (net (code "121") (name "Net-(D11-PadC)") (class "Default")
      (node (ref "D11") (pin "C") (pinfunction "C_C") (pintype "passive"))
      (node (ref "R19") (pin "1") (pinfunction "1_1") (pintype "passive"))
    )
    (net (code "122") (name "Net-(D12-PadC)") (class "Default")
      (node (ref "D12") (pin "C") (pinfunction "C_C") (pintype "passive"))
      (node (ref "R20") (pin "1") (pinfunction "1_1") (pintype "passive"))
    )
    (net (code "123") (name "Net-(D13-PadC)") (class "Default")
      (node (ref "D13") (pin "C") (pinfunction "C_C") (pintype "passive"))
      (node (ref "R21") (pin "1") (pinfunction "1_1") (pintype "passive"))
    )
    (net (code "124") (name "Net-(D14-A)") (class "Default")
      (node (ref "D14") (pin "2") (pinfunction "A_2") (pintype "passive"))
      (node (ref "L7") (pin "2") (pinfunction "2_2") (pintype "passive"))
    )
    (net (code "125") (name "Net-(D15_TR1-PadA)") (class "Default")
      (node (ref "D15_TR1") (pin "A") (pinfunction "A_A") (pintype "passive"))
      (node (ref "R33_TR1") (pin "1") (pinfunction "1_1") (pintype "passive"))
    )
    (net (code "126") (name "Net-(D15_TR2-PadA)") (class "Default")
      (node (ref "D15_TR2") (pin "A") (pinfunction "A_A") (pintype "passive"))
      (node (ref "R33_TR2") (pin "1") (pinfunction "1_1") (pintype "passive"))
    )
    (net (code "127") (name "Net-(D17-PadC)") (class "Default")
      (node (ref "D17") (pin "C") (pinfunction "C_C") (pintype "passive"))
      (node (ref "R53") (pin "2") (pinfunction "2_2") (pintype "passive"))
    )
    (net (code "128") (name "Net-(D18-PadC)") (class "Default")
      (node (ref "D18") (pin "C") (pinfunction "C_C") (pintype "passive"))
      (node (ref "R54") (pin "2") (pinfunction "2_2") (pintype "passive"))
    )
    (net (code "129") (name "Net-(D19-C)") (class "Default")
      (node (ref "C10") (pin "2") (pinfunction "2_2") (pintype "passive"))
      (node (ref "D19") (pin "1") (pinfunction "C_1") (pintype "passive"))
      (node (ref "L3") (pin "1") (pinfunction "1_1") (pintype "passive"))
      (node (ref "U16") (pin "8") (pinfunction "PH_8") (pintype "input"))
    )
    (net (code "130") (name "Net-(D20-PadC)") (class "Default")
      (node (ref "D20") (pin "C") (pinfunction "C_C") (pintype "passive"))
      (node (ref "R82") (pin "1") (pinfunction "1_1") (pintype "passive"))
    )
    (net (code "131") (name "Net-(D24-PadC)") (class "Default")
      (node (ref "D24") (pin "C") (pinfunction "C_C") (pintype "passive"))
      (node (ref "R83") (pin "1") (pinfunction "1_1") (pintype "passive"))
    )
    (net (code "132") (name "Net-(D25-PadC)") (class "Default")
      (node (ref "D25") (pin "C") (pinfunction "C_C") (pintype "passive"))
      (node (ref "R94") (pin "2") (pinfunction "2_2") (pintype "passive"))
    )
    (net (code "133") (name "Net-(D26-PadC)") (class "Default")
      (node (ref "D26") (pin "C") (pinfunction "C_C") (pintype "passive"))
      (node (ref "R95") (pin "2") (pinfunction "2_2") (pintype "passive"))
    )
    (net (code "134") (name "Net-(D28-PadA)") (class "Default")
      (node (ref "D28") (pin "A") (pinfunction "A_A") (pintype "passive"))
      (node (ref "R152") (pin "1") (pinfunction "1_1") (pintype "passive"))
    )
    (net (code "135") (name "Net-(D29-PadC)") (class "Default")
      (node (ref "D29") (pin "C") (pinfunction "C_C") (pintype "passive"))
      (node (ref "R69") (pin "2") (pinfunction "2_2") (pintype "passive"))
    )
    (net (code "136") (name "Net-(D31_TR1-PadA)") (class "Default")
      (node (ref "D31_TR1") (pin "A") (pinfunction "A_A") (pintype "passive"))
      (node (ref "F2_TR1") (pin "2") (pinfunction "2_2") (pintype "passive"))
      (node (ref "K1_TR1") (pin "4") (pinfunction "4_4") (pintype "bidirectional"))
    )
    (net (code "137") (name "Net-(D31_TR1-PadC)") (class "Default")
      (node (ref "D31_TR1") (pin "C") (pinfunction "C_C") (pintype "passive"))
      (node (ref "K1_TR1") (pin "6") (pinfunction "6_6") (pintype "bidirectional"))
      (node (ref "P21_TR1") (pin "2") (pinfunction "2_2") (pintype "passive"))
    )
    (net (code "138") (name "Net-(D31_TR2-PadA)") (class "Default")
      (node (ref "D31_TR2") (pin "A") (pinfunction "A_A") (pintype "passive"))
      (node (ref "F2_TR2") (pin "2") (pinfunction "2_2") (pintype "passive"))
      (node (ref "K1_TR2") (pin "4") (pinfunction "4_4") (pintype "bidirectional"))
    )
    (net (code "139") (name "Net-(D31_TR2-PadC)") (class "Default")
      (node (ref "D31_TR2") (pin "C") (pinfunction "C_C") (pintype "passive"))
      (node (ref "K1_TR2") (pin "6") (pinfunction "6_6") (pintype "bidirectional"))
      (node (ref "P21_TR2") (pin "2") (pinfunction "2_2") (pintype "passive"))
    )
    (net (code "140") (name "Net-(D32-PadA)") (class "Default")
      (node (ref "D32") (pin "A") (pinfunction "A_A") (pintype "passive"))
      (node (ref "R111") (pin "2") (pinfunction "2_2") (pintype "passive"))
    )
    (net (code "141") (name "Net-(D33-PadA)") (class "Default")
      (node (ref "D33") (pin "A") (pinfunction "A_A") (pintype "passive"))
      (node (ref "R155") (pin "1") (pinfunction "1_1") (pintype "passive"))
    )
    (net (code "142") (name "Net-(D34-PadA)") (class "Default")
      (node (ref "D34") (pin "A") (pinfunction "A_A") (pintype "passive"))
      (node (ref "R156") (pin "1") (pinfunction "1_1") (pintype "passive"))
    )
    (net (code "143") (name "Net-(D37-PadC)") (class "Default")
      (node (ref "D37") (pin "C") (pinfunction "C_C") (pintype "passive"))
      (node (ref "R160") (pin "1") (pinfunction "1_1") (pintype "passive"))
    )
    (net (code "144") (name "Net-(D38-PadC)") (class "Default")
      (node (ref "D38") (pin "C") (pinfunction "C_C") (pintype "passive"))
      (node (ref "R161") (pin "1") (pinfunction "1_1") (pintype "passive"))
    )
    (net (code "145") (name "Net-(D39-PadC)") (class "Default")
      (node (ref "D39") (pin "C") (pinfunction "C_C") (pintype "passive"))
      (node (ref "R63") (pin "1") (pinfunction "1_1") (pintype "passive"))
    )
    (net (code "146") (name "Net-(D43_RL1-PadA)") (class "Default")
      (node (ref "D43_RL1") (pin "A") (pinfunction "A_A") (pintype "passive"))
      (node (ref "R105_RL1") (pin "1") (pinfunction "1_1") (pintype "passive"))
    )
    (net (code "147") (name "Net-(D43_RL2-PadA)") (class "Default")
      (node (ref "D43_RL2") (pin "A") (pinfunction "A_A") (pintype "passive"))
      (node (ref "R105_RL2") (pin "1") (pinfunction "1_1") (pintype "passive"))
    )
    (net (code "148") (name "Net-(D47-A)") (class "Default")
      (node (ref "D47") (pin "2") (pinfunction "A_2") (pintype "passive"))
      (node (ref "K2") (pin "30") (pinfunction "30_30") (pintype "passive"))
      (node (ref "R126") (pin "2") (pinfunction "2_2") (pintype "passive"))
      (node (ref "R129") (pin "1") (pinfunction "1_1") (pintype "passive"))
      (node (ref "U41") (pin "5") (pinfunction "IN-_5") (pintype "tri_state"))
    )
    (net (code "149") (name "Net-(D47-C)") (class "Default")
      (node (ref "C91") (pin "1") (pinfunction "1_1") (pintype "passive"))
      (node (ref "D47") (pin "1") (pinfunction "C_1") (pintype "passive"))
      (node (ref "R129") (pin "2") (pinfunction "2_2") (pintype "passive"))
    )
    (net (code "150") (name "Net-(D51-PadC)") (class "Default")
      (node (ref "D51") (pin "C") (pinfunction "C_C") (pintype "passive"))
      (node (ref "R185") (pin "2") (pinfunction "2_2") (pintype "passive"))
    )
    (net (code "151") (name "Net-(D52-PadC)") (class "Default")
      (node (ref "D52") (pin "C") (pinfunction "C_C") (pintype "passive"))
      (node (ref "R186") (pin "2") (pinfunction "2_2") (pintype "passive"))
    )
    (net (code "152") (name "Net-(D57-PadC)") (class "Default")
      (node (ref "D57") (pin "C") (pinfunction "C_C") (pintype "passive"))
      (node (ref "R203") (pin "1") (pinfunction "1_1") (pintype "passive"))
    )
    (net (code "153") (name "Net-(D58-PadC)") (class "Default")
      (node (ref "D58") (pin "C") (pinfunction "C_C") (pintype "passive"))
      (node (ref "R204") (pin "1") (pinfunction "1_1") (pintype "passive"))
    )
    (net (code "154") (name "Net-(D59-PadC)") (class "Default")
      (node (ref "D59") (pin "C") (pinfunction "C_C") (pintype "passive"))
      (node (ref "R187") (pin "2") (pinfunction "2_2") (pintype "passive"))
    )
    (net (code "155") (name "Net-(D60-PadC)") (class "Default")
      (node (ref "D60") (pin "C") (pinfunction "C_C") (pintype "passive"))
      (node (ref "R188") (pin "2") (pinfunction "2_2") (pintype "passive"))
    )
    (net (code "156") (name "Net-(D61-PadC)") (class "Default")
      (node (ref "D61") (pin "C") (pinfunction "C_C") (pintype "passive"))
      (node (ref "R205") (pin "2") (pinfunction "2_2") (pintype "passive"))
    )
    (net (code "157") (name "Net-(D62-PadC)") (class "Default")
      (node (ref "D62") (pin "C") (pinfunction "C_C") (pintype "passive"))
      (node (ref "R206") (pin "2") (pinfunction "2_2") (pintype "passive"))
    )
    (net (code "158") (name "Net-(D63-PadC)") (class "Default")
      (node (ref "D63") (pin "C") (pinfunction "C_C") (pintype "passive"))
      (node (ref "R207") (pin "2") (pinfunction "2_2") (pintype "passive"))
    )
    (net (code "159") (name "Net-(D64-PadC)") (class "Default")
      (node (ref "D64") (pin "C") (pinfunction "C_C") (pintype "passive"))
      (node (ref "R208") (pin "2") (pinfunction "2_2") (pintype "passive"))
    )
    (net (code "160") (name "Net-(F2_TR1-Pad1)") (class "Default")
      (node (ref "F2_TR1") (pin "1") (pinfunction "1_1") (pintype "passive"))
      (node (ref "P21_TR1") (pin "1") (pinfunction "1_1") (pintype "passive"))
    )
    (net (code "161") (name "Net-(F2_TR2-Pad1)") (class "Default")
      (node (ref "F2_TR2") (pin "1") (pinfunction "1_1") (pintype "passive"))
      (node (ref "P21_TR2") (pin "1") (pinfunction "1_1") (pintype "passive"))
    )
    (net (code "162") (name "Net-(J1-Pad6)") (class "Default")
      (node (ref "J1") (pin "6") (pinfunction "6_6") (pintype "bidirectional"))
      (node (ref "R3") (pin "1") (pinfunction "1_1") (pintype "passive"))
    )
    (net (code "163") (name "Net-(J1-Pad8)") (class "Default")
      (node (ref "J1") (pin "8") (pinfunction "8_8") (pintype "bidirectional"))
      (node (ref "R4") (pin "1") (pinfunction "1_1") (pintype "passive"))
    )
    (net (code "164") (name "Net-(J1-Pad12)") (class "Default")
      (node (ref "J1") (pin "12") (pinfunction "12_12") (pintype "bidirectional"))
      (node (ref "R2") (pin "1") (pinfunction "1_1") (pintype "passive"))
    )
    (net (code "165") (name "Net-(J18-Pad1)") (class "Default")
      (node (ref "J18") (pin "1") (pinfunction "1_1") (pintype "passive"))
      (node (ref "R100") (pin "1") (pinfunction "1_1") (pintype "passive"))
      (node (ref "R101") (pin "1") (pinfunction "1_1") (pintype "passive"))
    )
    (net (code "166") (name "Net-(K1_TR1-Pad1)") (class "Default")
      (node (ref "K1_TR1") (pin "1") (pinfunction "1_1") (pintype "bidirectional"))
      (node (ref "R39_TR1") (pin "1") (pinfunction "1_1") (pintype "passive"))
    )
    (net (code "167") (name "Net-(K1_TR2-Pad1)") (class "Default")
      (node (ref "K1_TR2") (pin "1") (pinfunction "1_1") (pintype "bidirectional"))
      (node (ref "R39_TR2") (pin "1") (pinfunction "1_1") (pintype "passive"))
    )
    (net (code "168") (name "Net-(L12-Pad1)") (class "Default")
      (node (ref "L12") (pin "1") (pinfunction "1_1") (pintype "passive"))
      (node (ref "P24") (pin "07") (pinfunction "07_07") (pintype "passive"))
    )
    (net (code "169") (name "Net-(P12-GC)") (class "Default")
      (node (ref "P12") (pin "10") (pinfunction "GC_10") (pintype "passive"))
      (node (ref "R148") (pin "1") (pinfunction "1_1") (pintype "passive"))
    )
    (net (code "170") (name "Net-(P12-GND)") (class "Default")
      (node (ref "C114") (pin "2") (pinfunction "2_2") (pintype "passive"))
      (node (ref "P12") (pin "15") (pinfunction "SHIELD_15") (pintype "passive"))
      (node (ref "P12") (pin "16") (pinfunction "SHIELD_16") (pintype "passive"))
      (node (ref "P12") (pin "8") (pinfunction "GND_8") (pintype "power_in"))
    )
    (net (code "171") (name "Net-(P12-P4)") (class "Default")
      (node (ref "C112") (pin "2") (pinfunction "2_2") (pintype "passive"))
      (node (ref "P12") (pin "4") (pinfunction "P4_4") (pintype "passive"))
      (node (ref "R146") (pin "2") (pinfunction "2_2") (pintype "passive"))
    )
    (net (code "172") (name "Net-(P12-P5)") (class "Default")
      (node (ref "C109") (pin "1") (pinfunction "1_1") (pintype "passive"))
      (node (ref "P12") (pin "5") (pinfunction "P5_5") (pintype "passive"))
      (node (ref "R136") (pin "1") (pinfunction "1_1") (pintype "passive"))
      (node (ref "R137") (pin "1") (pinfunction "1_1") (pintype "passive"))
    )
    (net (code "173") (name "Net-(P12-YC)") (class "Default")
      (node (ref "P12") (pin "11") (pinfunction "YC_11") (pintype "passive"))
      (node (ref "R150") (pin "1") (pinfunction "1_1") (pintype "passive"))
    )
    (net (code "174") (name "Net-(Q4-D)") (class "Default")
      (node (ref "D2") (pin "C") (pinfunction "C_C") (pintype "passive"))
      (node (ref "Q4") (pin "P3") (pinfunction "D_P3") (pintype "passive"))
    )
    (net (code "175") (name "Net-(Q5-D)") (class "Default")
      (node (ref "D28") (pin "C") (pinfunction "C_C") (pintype "passive"))
      (node (ref "Q5") (pin "P3") (pinfunction "D_P3") (pintype "passive"))
    )
    (net (code "176") (name "Net-(Q6-D)") (class "Default")
      (node (ref "D33") (pin "C") (pinfunction "C_C") (pintype "passive"))
      (node (ref "Q6") (pin "P3") (pinfunction "D_P3") (pintype "passive"))
    )
    (net (code "177") (name "Net-(Q7-D)") (class "Default")
      (node (ref "D34") (pin "C") (pinfunction "C_C") (pintype "passive"))
      (node (ref "Q7") (pin "P3") (pinfunction "D_P3") (pintype "passive"))
    )
    (net (code "178") (name "Net-(Q8-D)") (class "Default")
      (node (ref "Q8") (pin "P3") (pinfunction "D_P3") (pintype "passive"))
      (node (ref "R160") (pin "2") (pinfunction "2_2") (pintype "passive"))
    )
    (net (code "179") (name "Net-(Q8-G)") (class "Default")
      (node (ref "Q8") (pin "P1") (pinfunction "G_P1") (pintype "passive"))
      (node (ref "R98") (pin "1") (pinfunction "1_1") (pintype "passive"))
    )
    (net (code "180") (name "Net-(Q9_TR1-D)") (class "Default")
      (node (ref "D15_TR1") (pin "C") (pinfunction "C_C") (pintype "passive"))
      (node (ref "Q9_TR1") (pin "P3") (pinfunction "D_P3") (pintype "passive"))
    )
    (net (code "181") (name "Net-(Q9_TR2-D)") (class "Default")
      (node (ref "D15_TR2") (pin "C") (pinfunction "C_C") (pintype "passive"))
      (node (ref "Q9_TR2") (pin "P3") (pinfunction "D_P3") (pintype "passive"))
    )
    (net (code "182") (name "Net-(Q10_RL1-D)") (class "Default")
      (node (ref "D43_RL1") (pin "C") (pinfunction "C_C") (pintype "passive"))
      (node (ref "Q10_RL1") (pin "P3") (pinfunction "D_P3") (pintype "passive"))
    )
    (net (code "183") (name "Net-(Q10_RL2-D)") (class "Default")
      (node (ref "D43_RL2") (pin "C") (pinfunction "C_C") (pintype "passive"))
      (node (ref "Q10_RL2") (pin "P3") (pinfunction "D_P3") (pintype "passive"))
    )
    (net (code "184") (name "Net-(Q12-D)") (class "Default")
      (node (ref "Q12") (pin "P3") (pinfunction "D_P3") (pintype "passive"))
      (node (ref "R99") (pin "1") (pinfunction "1_1") (pintype "passive"))
      (node (ref "U10") (pin "2") (pinfunction "C_2") (pintype "passive"))
    )
    (net (code "185") (name "Net-(Q13-D)") (class "Default")
      (node (ref "F3") (pin "2") (pinfunction "2_2") (pintype "passive"))
      (node (ref "Q13") (pin "P3") (pinfunction "D_P3") (pintype "passive"))
    )
    (net (code "186") (name "Net-(Q13-G)") (class "Default")
      (node (ref "Q13") (pin "P1") (pinfunction "G_P1") (pintype "passive"))
      (node (ref "R128") (pin "2") (pinfunction "2_2") (pintype "passive"))
    )
    (net (code "187") (name "Net-(Q14-GATE)") (class "Default")
      (node (ref "Q14") (pin "4") (pinfunction "GATE_4") (pintype "passive"))
      (node (ref "U24") (pin "18") (pinfunction "HO_18") (pintype "output"))
    )
    (net (code "188") (name "Net-(Q15-GATE)") (class "Default")
      (node (ref "Q15") (pin "4") (pinfunction "GATE_4") (pintype "passive"))
      (node (ref "U24") (pin "13") (pinfunction "LO_13") (pintype "output"))
    )
    (net (code "189") (name "Net-(Q16-PadD)") (class "Default")
      (node (ref "Q16") (pin "D") (pinfunction "D_D") (pintype "passive"))
      (node (ref "R103") (pin "2") (pinfunction "2_2") (pintype "passive"))
    )
    (net (code "190") (name "Net-(Q16-PadG)") (class "Default")
      (node (ref "Q16") (pin "G") (pinfunction "G_G") (pintype "passive"))
      (node (ref "R213") (pin "2") (pinfunction "2_2") (pintype "passive"))
    )
    (net (code "191") (name "Net-(Q16-PadS)") (class "Default")
      (node (ref "Q16") (pin "S") (pinfunction "S_S") (pintype "passive"))
      (node (ref "R209") (pin "1") (pinfunction "1_1") (pintype "passive"))
    )
    (net (code "192") (name "Net-(R104-Pad1)") (class "Default")
      (node (ref "R104") (pin "1") (pinfunction "1_1") (pintype "passive"))
      (node (ref "R159") (pin "2") (pinfunction "2_2") (pintype "passive"))
    )
    (net (code "193") (name "Net-(U2_AL-A)") (class "Default")
      (node (ref "R23_AL") (pin "1") (pinfunction "1_1") (pintype "passive"))
      (node (ref "U2_AL") (pin "1") (pinfunction "A_1") (pintype "passive"))
    )
    (net (code "194") (name "Net-(U2_CY-A)") (class "Default")
      (node (ref "R23_CY") (pin "1") (pinfunction "1_1") (pintype "passive"))
      (node (ref "U2_CY") (pin "1") (pinfunction "A_1") (pintype "passive"))
    )
    (net (code "195") (name "Net-(U2_DR-A)") (class "Default")
      (node (ref "R23_DR") (pin "1") (pinfunction "1_1") (pintype "passive"))
      (node (ref "U2_DR") (pin "1") (pinfunction "A_1") (pintype "passive"))
    )
    (net (code "196") (name "Net-(U2_HL-A)") (class "Default")
      (node (ref "R23_HL") (pin "1") (pinfunction "1_1") (pintype "passive"))
      (node (ref "U2_HL") (pin "1") (pinfunction "A_1") (pintype "passive"))
    )
    (net (code "197") (name "Net-(U2_MC1-A)") (class "Default")
      (node (ref "R23_MC1") (pin "1") (pinfunction "1_1") (pintype "passive"))
      (node (ref "U2_MC1") (pin "1") (pinfunction "A_1") (pintype "passive"))
    )
    (net (code "198") (name "Net-(U2_MC2-A)") (class "Default")
      (node (ref "R23_MC2") (pin "1") (pinfunction "1_1") (pintype "passive"))
      (node (ref "U2_MC2") (pin "1") (pinfunction "A_1") (pintype "passive"))
    )
    (net (code "199") (name "Net-(U2_PRB-A)") (class "Default")
      (node (ref "R23_PRB") (pin "1") (pinfunction "1_1") (pintype "passive"))
      (node (ref "U2_PRB") (pin "1") (pinfunction "A_1") (pintype "passive"))
    )
    (net (code "200") (name "Net-(U2_TLO-A)") (class "Default")
      (node (ref "R23_TLO") (pin "1") (pinfunction "1_1") (pintype "passive"))
      (node (ref "U2_TLO") (pin "1") (pinfunction "A_1") (pintype "passive"))
    )
    (net (code "201") (name "Net-(U2_XL-A)") (class "Default")
      (node (ref "R23_XL") (pin "1") (pinfunction "1_1") (pintype "passive"))
      (node (ref "U2_XL") (pin "1") (pinfunction "A_1") (pintype "passive"))
    )
    (net (code "202") (name "Net-(U2_Y1L-A)") (class "Default")
      (node (ref "R23_Y1L") (pin "1") (pinfunction "1_1") (pintype "passive"))
      (node (ref "U2_Y1L") (pin "1") (pinfunction "A_1") (pintype "passive"))
    )
    (net (code "203") (name "Net-(U2_Y2L-A)") (class "Default")
      (node (ref "R23_Y2L") (pin "1") (pinfunction "1_1") (pintype "passive"))
      (node (ref "U2_Y2L") (pin "1") (pinfunction "A_1") (pintype "passive"))
    )
    (net (code "204") (name "Net-(U2_ZL-A)") (class "Default")
      (node (ref "R23_ZL") (pin "1") (pinfunction "1_1") (pintype "passive"))
      (node (ref "U2_ZL") (pin "1") (pinfunction "A_1") (pintype "passive"))
    )
    (net (code "205") (name "Net-(U4-A)") (class "Default")
      (node (ref "R25") (pin "1") (pinfunction "1_1") (pintype "passive"))
      (node (ref "U4") (pin "1") (pinfunction "A_1") (pintype "passive"))
    )
    (net (code "206") (name "Net-(U4-CT)") (class "Default")
      (node (ref "R24") (pin "2") (pinfunction "2_2") (pintype "passive"))
      (node (ref "U4") (pin "4") (pinfunction "CT_4") (pintype "passive"))
    )
    (net (code "207") (name "Net-(U5-A)") (class "Default")
      (node (ref "R31") (pin "1") (pinfunction "1_1") (pintype "passive"))
      (node (ref "U5") (pin "1") (pinfunction "A_1") (pintype "passive"))
    )
    (net (code "208") (name "Net-(U6-A)") (class "Default")
      (node (ref "R32") (pin "1") (pinfunction "1_1") (pintype "passive"))
      (node (ref "U6") (pin "1") (pinfunction "A_1") (pintype "passive"))
    )
    (net (code "209") (name "Net-(U7-A)") (class "Default")
      (node (ref "R35") (pin "1") (pinfunction "1_1") (pintype "passive"))
      (node (ref "U7") (pin "1") (pinfunction "A_1") (pintype "passive"))
    )
    (net (code "210") (name "Net-(U7-CT)") (class "Default")
      (node (ref "R34") (pin "2") (pinfunction "2_2") (pintype "passive"))
      (node (ref "U7") (pin "4") (pinfunction "CT_4") (pintype "passive"))
    )
    (net (code "211") (name "Net-(U8-A)") (class "Default")
      (node (ref "R37") (pin "1") (pinfunction "1_1") (pintype "passive"))
      (node (ref "U8") (pin "1") (pinfunction "A_1") (pintype "passive"))
    )
    (net (code "212") (name "Net-(U8-CT)") (class "Default")
      (node (ref "R36") (pin "2") (pinfunction "2_2") (pintype "passive"))
      (node (ref "U8") (pin "4") (pinfunction "CT_4") (pintype "passive"))
    )
    (net (code "213") (name "Net-(U10-A)") (class "Default")
      (node (ref "R41") (pin "1") (pinfunction "1_1") (pintype "passive"))
      (node (ref "U10") (pin "1") (pinfunction "A_1") (pintype "passive"))
    )
    (net (code "214") (name "Net-(U10-CT)") (class "Default")
      (node (ref "R40") (pin "2") (pinfunction "2_2") (pintype "passive"))
      (node (ref "U10") (pin "4") (pinfunction "CT_4") (pintype "passive"))
    )
    (net (code "215") (name "Net-(U11-1V2O)") (class "Default")
      (node (ref "C118") (pin "2") (pinfunction "2_2") (pintype "passive"))
      (node (ref "U11") (pin "22") (pinfunction "1V2O_22") (pintype "output"))
    )
    (net (code "216") (name "Net-(U11-EXRES1)") (class "Default")
      (node (ref "R143") (pin "2") (pinfunction "2_2") (pintype "passive"))
      (node (ref "U11") (pin "10") (pinfunction "EXRES1_10") (pintype "bidirectional"))
    )
    (net (code "217") (name "Net-(U11-PMODE0)") (class "Default")
      (node (ref "R1") (pin "2") (pinfunction "2_2") (pintype "passive"))
      (node (ref "U11") (pin "45") (pinfunction "PMODE0_45") (pintype "input"))
    )
    (net (code "218") (name "Net-(U11-PMODE1)") (class "Default")
      (node (ref "R5") (pin "2") (pinfunction "2_2") (pintype "passive"))
      (node (ref "U11") (pin "44") (pinfunction "PMODE1_44") (pintype "input"))
    )
    (net (code "219") (name "Net-(U11-PMODE2)") (class "Default")
      (node (ref "R6") (pin "2") (pinfunction "2_2") (pintype "passive"))
      (node (ref "U11") (pin "43") (pinfunction "PMODE2_43") (pintype "input"))
    )
    (net (code "220") (name "Net-(U11-RXN)") (class "Default")
      (node (ref "R141") (pin "1") (pinfunction "1_1") (pintype "passive"))
      (node (ref "U11") (pin "5") (pinfunction "RXN_5") (pintype "input"))
    )
    (net (code "221") (name "Net-(U11-RXP)") (class "Default")
      (node (ref "R142") (pin "1") (pinfunction "1_1") (pintype "passive"))
      (node (ref "U11") (pin "6") (pinfunction "RXP_6") (pintype "input"))
    )
    (net (code "222") (name "Net-(U11-TOCAP)") (class "Default")
      (node (ref "C117") (pin "2") (pinfunction "2_2") (pintype "passive"))
      (node (ref "U11") (pin "20") (pinfunction "TOCAP_20") (pintype "output"))
    )
    (net (code "223") (name "Net-(U11-TXN)") (class "Default")
      (node (ref "R139") (pin "1") (pinfunction "1_1") (pintype "passive"))
      (node (ref "U11") (pin "1") (pinfunction "TXN_1") (pintype "output"))
    )
    (net (code "224") (name "Net-(U11-TXP)") (class "Default")
      (node (ref "R140") (pin "1") (pinfunction "1_1") (pintype "passive"))
      (node (ref "U11") (pin "2") (pinfunction "TXP_2") (pintype "output"))
    )
    (net (code "225") (name "Net-(U12-VDD1)") (class "Default")
      (node (ref "C134") (pin "1") (pinfunction "1_1") (pintype "passive"))
      (node (ref "R44") (pin "1") (pinfunction "1_1") (pintype "passive"))
      (node (ref "U12") (pin "1") (pinfunction "VDD1_1") (pintype "bidirectional"))
    )
    (net (code "226") (name "Net-(U12-VDD2)") (class "Default")
      (node (ref "C135") (pin "2") (pinfunction "2_2") (pintype "passive"))
      (node (ref "R45") (pin "1") (pinfunction "1_1") (pintype "passive"))
      (node (ref "U12") (pin "8") (pinfunction "VDD2_8") (pintype "bidirectional"))
    )
    (net (code "227") (name "Net-(U13-D)") (class "Default")
      (node (ref "R50") (pin "1") (pinfunction "1_1") (pintype "passive"))
      (node (ref "U13") (pin "4") (pinfunction "D_4") (pintype "input"))
    )
    (net (code "228") (name "Net-(U14-VDD1)") (class "Default")
      (node (ref "C68") (pin "1") (pinfunction "1_1") (pintype "passive"))
      (node (ref "R97") (pin "1") (pinfunction "1_1") (pintype "passive"))
      (node (ref "U14") (pin "1") (pinfunction "VDD1_1") (pintype "power_in"))
    )
    (net (code "229") (name "Net-(U14-VDD2)") (class "Default")
      (node (ref "C5") (pin "1") (pinfunction "1_1") (pintype "passive"))
      (node (ref "C67") (pin "1") (pinfunction "1_1") (pintype "passive"))
      (node (ref "R96") (pin "1") (pinfunction "1_1") (pintype "passive"))
      (node (ref "U14") (pin "8") (pinfunction "VDD2_8") (pintype "power_in"))
    )
    (net (code "230") (name "Net-(U14-VOA)") (class "Default")
      (node (ref "U14") (pin "7") (pinfunction "VOA_7") (pintype "output"))
      (node (ref "U28") (pin "4") (pinfunction "DI_4") (pintype "bidirectional"))
    )
    (net (code "231") (name "Net-(U14-VOB)") (class "Default")
      (node (ref "R28") (pin "2") (pinfunction "2_2") (pintype "passive"))
      (node (ref "U14") (pin "6") (pinfunction "VOB_6") (pintype "output"))
    )
    (net (code "232") (name "Net-(U15-A)") (class "Default")
      (node (ref "R51") (pin "1") (pinfunction "1_1") (pintype "passive"))
      (node (ref "U15") (pin "1") (pinfunction "A_1") (pintype "passive"))
    )
    (net (code "233") (name "Net-(U16-BOOT)") (class "Default")
      (node (ref "C10") (pin "1") (pinfunction "1_1") (pintype "passive"))
      (node (ref "U16") (pin "1") (pinfunction "BOOT_1") (pintype "input"))
    )
    (net (code "234") (name "Net-(U16-COMP)") (class "Default")
      (node (ref "C17") (pin "2") (pinfunction "2_2") (pintype "passive"))
      (node (ref "R56") (pin "1") (pinfunction "1_1") (pintype "passive"))
      (node (ref "U16") (pin "6") (pinfunction "COMP_6") (pintype "output"))
    )
    (net (code "235") (name "Net-(U16-SS)") (class "Default")
      (node (ref "C18") (pin "1") (pinfunction "1_1") (pintype "passive"))
      (node (ref "U16") (pin "4") (pinfunction "SS_4") (pintype "input"))
    )
    (net (code "236") (name "Net-(U18-VDD1)") (class "Default")
      (node (ref "C62") (pin "1") (pinfunction "1_1") (pintype "passive"))
      (node (ref "R85") (pin "1") (pinfunction "1_1") (pintype "passive"))
      (node (ref "U18") (pin "1") (pinfunction "VDD1_1") (pintype "bidirectional"))
    )
    (net (code "237") (name "Net-(U18-VDD2)") (class "Default")
      (node (ref "C63") (pin "2") (pinfunction "2_2") (pintype "passive"))
      (node (ref "R88") (pin "1") (pinfunction "1_1") (pintype "passive"))
      (node (ref "U18") (pin "8") (pinfunction "VDD2_8") (pintype "bidirectional"))
    )
    (net (code "238") (name "Net-(U18-VIA)") (class "Default")
      (node (ref "U18") (pin "7") (pinfunction "VIA_7") (pintype "bidirectional"))
      (node (ref "U19") (pin "4") (pinfunction "RXD_4") (pintype "output"))
    )
    (net (code "239") (name "Net-(U18-VOB)") (class "Default")
      (node (ref "U18") (pin "6") (pinfunction "VOB_6") (pintype "bidirectional"))
      (node (ref "U19") (pin "1") (pinfunction "TXD_1") (pintype "input"))
    )
    (net (code "240") (name "Net-(U19-RS)") (class "Default")
      (node (ref "R86") (pin "2") (pinfunction "2_2") (pintype "passive"))
      (node (ref "U19") (pin "8") (pinfunction "RS_8") (pintype "input"))
    )
    (net (code "241") (name "Net-(U20-VDD1)") (class "Default")
      (node (ref "C70") (pin "1") (pinfunction "1_1") (pintype "passive"))
      (node (ref "R110") (pin "1") (pinfunction "1_1") (pintype "passive"))
      (node (ref "U20") (pin "1") (pinfunction "VDD1_1") (pintype "bidirectional"))
    )
    (net (code "242") (name "Net-(U20-VDD2)") (class "Default")
      (node (ref "C71") (pin "1") (pinfunction "1_1") (pintype "passive"))
      (node (ref "R112") (pin "1") (pinfunction "1_1") (pintype "passive"))
      (node (ref "U20") (pin "8") (pinfunction "VDD2_8") (pintype "bidirectional"))
    )
    (net (code "243") (name "Net-(U21-A)") (class "Default")
      (node (ref "R91") (pin "1") (pinfunction "1_1") (pintype "passive"))
      (node (ref "U21") (pin "1") (pinfunction "A_1") (pintype "passive"))
    )
    (net (code "244") (name "Net-(U22-A)") (class "Default")
      (node (ref "R93") (pin "1") (pinfunction "1_1") (pintype "passive"))
      (node (ref "U22") (pin "1") (pinfunction "A_1") (pintype "passive"))
    )
    (net (code "245") (name "Net-(U23-A)") (class "Default")
      (node (ref "R165") (pin "1") (pinfunction "1_1") (pintype "passive"))
      (node (ref "U23") (pin "1") (pinfunction "A_1") (pintype "passive"))
    )
    (net (code "246") (name "Net-(U24-BST)") (class "Default")
      (node (ref "R134") (pin "1") (pinfunction "1_1") (pintype "passive"))
      (node (ref "U24") (pin "17") (pinfunction "BST_17") (pintype "passive"))
    )
    (net (code "247") (name "Net-(U24-ILIM)") (class "Default")
      (node (ref "C84") (pin "1") (pinfunction "1_1") (pintype "passive"))
      (node (ref "R167") (pin "1") (pinfunction "1_1") (pintype "passive"))
      (node (ref "U24") (pin "11") (pinfunction "ILIM_11") (pintype "input"))
    )
    (net (code "248") (name "Net-(U24-PGOOD)") (class "Default")
      (node (ref "R132") (pin "2") (pinfunction "2_2") (pintype "passive"))
      (node (ref "U24") (pin "10") (pinfunction "PGOOD_10") (pintype "open_collector"))
    )
    (net (code "249") (name "Net-(U24-SS_TRK)") (class "Default")
      (node (ref "C76") (pin "1") (pinfunction "1_1") (pintype "passive"))
      (node (ref "U24") (pin "3") (pinfunction "SS_TRK_3") (pintype "input"))
    )
    (net (code "250") (name "Net-(U24-SW)") (class "Default")
      (node (ref "C81") (pin "2") (pinfunction "2_2") (pintype "passive"))
      (node (ref "L5") (pin "1") (pinfunction "1_1") (pintype "passive"))
      (node (ref "Q14") (pin "1") (pinfunction "SOURCE_1") (pintype "passive"))
      (node (ref "Q14") (pin "2") (pinfunction "SOURCE_2") (pintype "passive"))
      (node (ref "Q14") (pin "3") (pinfunction "SOURCE_3") (pintype "passive"))
      (node (ref "Q15") (pin "10") (pinfunction "DRAIN_10") (pintype "passive"))
      (node (ref "Q15") (pin "11") (pinfunction "DRAIN_11") (pintype "passive"))
      (node (ref "Q15") (pin "12") (pinfunction "DRAIN_12") (pintype "passive"))
      (node (ref "Q15") (pin "5") (pinfunction "DRAIN_5") (pintype "passive"))
      (node (ref "Q15") (pin "6") (pinfunction "DRAIN_6") (pintype "passive"))
      (node (ref "Q15") (pin "7") (pinfunction "DRAIN_7") (pintype "passive"))
      (node (ref "Q15") (pin "8") (pinfunction "DRAIN_8") (pintype "passive"))
      (node (ref "Q15") (pin "9") (pinfunction "DRAIN_9") (pintype "passive"))
      (node (ref "R167") (pin "2") (pinfunction "2_2") (pintype "passive"))
      (node (ref "U24") (pin "19") (pinfunction "SW_19") (pintype "power_in"))
    )
    (net (code "251") (name "Net-(U24-SYNCIN)") (class "Default")
      (node (ref "R125") (pin "2") (pinfunction "2_2") (pintype "passive"))
      (node (ref "U24") (pin "8") (pinfunction "SYNCIN_8") (pintype "input"))
    )
    (net (code "252") (name "Net-(U24-VCC)") (class "Default")
      (node (ref "C75") (pin "1") (pinfunction "1_1") (pintype "passive"))
      (node (ref "R125") (pin "1") (pinfunction "1_1") (pintype "passive"))
      (node (ref "R132") (pin "1") (pinfunction "1_1") (pintype "passive"))
      (node (ref "U24") (pin "14") (pinfunction "VCC_14") (pintype "power_in"))
    )
    (net (code "253") (name "Net-(U24-VIN)") (class "Default")
      (node (ref "R29") (pin "2") (pinfunction "2_2") (pintype "passive"))
      (node (ref "U24") (pin "20") (pinfunction "VIN_20") (pintype "power_in"))
    )
    (net (code "254") (name "Net-(U25-A)") (class "Default")
      (node (ref "C139") (pin "1") (pinfunction "1_1") (pintype "passive"))
      (node (ref "D56") (pin "A") (pinfunction "A_A") (pintype "passive"))
      (node (ref "R199") (pin "1") (pinfunction "1_1") (pintype "passive"))
      (node (ref "U25") (pin "2") (pinfunction "A_2") (pintype "input"))
    )
    (net (code "255") (name "Net-(U25-Y)") (class "Default")
      (node (ref "D57") (pin "A") (pinfunction "A_A") (pintype "passive"))
      (node (ref "R213") (pin "1") (pinfunction "1_1") (pintype "passive"))
      (node (ref "U25") (pin "4") (pinfunction "Y_4") (pintype "output"))
    )
    (net (code "256") (name "Net-(U29-A)") (class "Default")
      (node (ref "R114") (pin "1") (pinfunction "1_1") (pintype "passive"))
      (node (ref "U29") (pin "1") (pinfunction "A_1") (pintype "passive"))
    )
    (net (code "257") (name "Net-(U29-CT)") (class "Default")
      (node (ref "R113") (pin "2") (pinfunction "2_2") (pintype "passive"))
      (node (ref "U29") (pin "4") (pinfunction "CT_4") (pintype "passive"))
    )
    (net (code "258") (name "Net-(U30-A)") (class "Default")
      (node (ref "R116") (pin "1") (pinfunction "1_1") (pintype "passive"))
      (node (ref "U30") (pin "1") (pinfunction "A_1") (pintype "passive"))
    )
    (net (code "259") (name "Net-(U30-CT)") (class "Default")
      (node (ref "R115") (pin "2") (pinfunction "2_2") (pintype "passive"))
      (node (ref "U30") (pin "4") (pinfunction "CT_4") (pintype "passive"))
    )
    (net (code "260") (name "Net-(U31-A)") (class "Default")
      (node (ref "R118") (pin "1") (pinfunction "1_1") (pintype "passive"))
      (node (ref "U31") (pin "1") (pinfunction "A_1") (pintype "passive"))
    )
    (net (code "261") (name "Net-(U31-CT)") (class "Default")
      (node (ref "R117") (pin "2") (pinfunction "2_2") (pintype "passive"))
      (node (ref "U31") (pin "4") (pinfunction "CT_4") (pintype "passive"))
    )
    (net (code "262") (name "Net-(U32-A)") (class "Default")
      (node (ref "R120") (pin "1") (pinfunction "1_1") (pintype "passive"))
      (node (ref "U32") (pin "1") (pinfunction "A_1") (pintype "passive"))
    )
    (net (code "263") (name "Net-(U33_AO0-A)") (class "Default")
      (node (ref "R122_AO0") (pin "1") (pinfunction "1_1") (pintype "passive"))
      (node (ref "U33_AO0") (pin "1") (pinfunction "A_1") (pintype "passive"))
    )
    (net (code "264") (name "Net-(U33_AO0-CT)") (class "Default")
      (node (ref "R121_AO0") (pin "2") (pinfunction "2_2") (pintype "passive"))
      (node (ref "U33_AO0") (pin "4") (pinfunction "CT_4") (pintype "passive"))
    )
    (net (code "265") (name "Net-(U33_AO1-A)") (class "Default")
      (node (ref "R122_AO1") (pin "1") (pinfunction "1_1") (pintype "passive"))
      (node (ref "U33_AO1") (pin "1") (pinfunction "A_1") (pintype "passive"))
    )
    (net (code "266") (name "Net-(U33_AO1-CT)") (class "Default")
      (node (ref "R121_AO1") (pin "2") (pinfunction "2_2") (pintype "passive"))
      (node (ref "U33_AO1") (pin "4") (pinfunction "CT_4") (pintype "passive"))
    )
    (net (code "267") (name "Net-(U33_AO2-A)") (class "Default")
      (node (ref "R122_AO2") (pin "1") (pinfunction "1_1") (pintype "passive"))
      (node (ref "U33_AO2") (pin "1") (pinfunction "A_1") (pintype "passive"))
    )
    (net (code "268") (name "Net-(U33_AO2-CT)") (class "Default")
      (node (ref "R121_AO2") (pin "2") (pinfunction "2_2") (pintype "passive"))
      (node (ref "U33_AO2") (pin "4") (pinfunction "CT_4") (pintype "passive"))
    )
    (net (code "269") (name "Net-(U33_AO3-A)") (class "Default")
      (node (ref "R122_AO3") (pin "1") (pinfunction "1_1") (pintype "passive"))
      (node (ref "U33_AO3") (pin "1") (pinfunction "A_1") (pintype "passive"))
    )
    (net (code "270") (name "Net-(U33_AO3-CT)") (class "Default")
      (node (ref "R121_AO3") (pin "2") (pinfunction "2_2") (pintype "passive"))
      (node (ref "U33_AO3") (pin "4") (pinfunction "CT_4") (pintype "passive"))
    )
    (net (code "271") (name "Net-(U33_COO-A)") (class "Default")
      (node (ref "R122_COO") (pin "1") (pinfunction "1_1") (pintype "passive"))
      (node (ref "U33_COO") (pin "1") (pinfunction "A_1") (pintype "passive"))
    )
    (net (code "272") (name "Net-(U33_COO-CT)") (class "Default")
      (node (ref "R121_COO") (pin "2") (pinfunction "2_2") (pintype "passive"))
      (node (ref "U33_COO") (pin "4") (pinfunction "CT_4") (pintype "passive"))
    )
    (net (code "273") (name "Net-(U33_MIS-A)") (class "Default")
      (node (ref "R122_MIS") (pin "1") (pinfunction "1_1") (pintype "passive"))
      (node (ref "U33_MIS") (pin "1") (pinfunction "A_1") (pintype "passive"))
    )
    (net (code "274") (name "Net-(U33_MIS-CT)") (class "Default")
      (node (ref "R121_MIS") (pin "2") (pinfunction "2_2") (pintype "passive"))
      (node (ref "U33_MIS") (pin "4") (pinfunction "CT_4") (pintype "passive"))
    )
    (net (code "275") (name "Net-(U34_N0-A)") (class "Default")
      (node (ref "R124_N0") (pin "1") (pinfunction "1_1") (pintype "passive"))
      (node (ref "U34_N0") (pin "1") (pinfunction "A_1") (pintype "passive"))
    )
    (net (code "276") (name "Net-(U34_N1-A)") (class "Default")
      (node (ref "R124_N1") (pin "1") (pinfunction "1_1") (pintype "passive"))
      (node (ref "U34_N1") (pin "1") (pinfunction "A_1") (pintype "passive"))
    )
    (net (code "277") (name "Net-(U34_N2-A)") (class "Default")
      (node (ref "R124_N2") (pin "1") (pinfunction "1_1") (pintype "passive"))
      (node (ref "U34_N2") (pin "1") (pinfunction "A_1") (pintype "passive"))
    )
    (net (code "278") (name "Net-(U34_N3-A)") (class "Default")
      (node (ref "R124_N3") (pin "1") (pinfunction "1_1") (pintype "passive"))
      (node (ref "U34_N3") (pin "1") (pinfunction "A_1") (pintype "passive"))
    )
    (net (code "279") (name "Net-(U39-A)") (class "Default")
      (node (ref "R78") (pin "2") (pinfunction "2_2") (pintype "passive"))
      (node (ref "U39") (pin "1") (pinfunction "A_1") (pintype "passive"))
    )
    (net (code "280") (name "Net-(U40-IN_B)") (class "Default")
      (node (ref "R183") (pin "2") (pinfunction "2_2") (pintype "passive"))
      (node (ref "U40") (pin "5") (pinfunction "IN_B_5") (pintype "input"))
    )
    (net (code "281") (name "Net-(U40-IN_B_2)") (class "Default")
      (node (ref "R181") (pin "2") (pinfunction "2_2") (pintype "passive"))
      (node (ref "U40") (pin "6") (pinfunction "IN_B_2_6") (pintype "input"))
    )
    (net (code "282") (name "Net-(U40-OUT_A)") (class "Default")
      (node (ref "R106") (pin "1") (pinfunction "1_1") (pintype "passive"))
      (node (ref "R163") (pin "1") (pinfunction "1_1") (pintype "passive"))
      (node (ref "R42") (pin "2") (pinfunction "2_2") (pintype "passive"))
      (node (ref "U40") (pin "1") (pinfunction "OUT_A_1") (pintype "output"))
    )
    (net (code "283") (name "Net-(U41-OUT)") (class "Default")
      (node (ref "R70") (pin "1") (pinfunction "1_1") (pintype "passive"))
      (node (ref "U41") (pin "1") (pinfunction "OUT_1") (pintype "passive"))
    )
    (net (code "284") (name "Net-(U42-1B)") (class "Default")
      (node (ref "U42") (pin "10") (pinfunction "3B_10") (pintype "input"))
      (node (ref "U42") (pin "11") (pinfunction "4Y_11") (pintype "output"))
      (node (ref "U42") (pin "2") (pinfunction "1B_2") (pintype "input"))
    )
    (net (code "285") (name "Net-(U42-3Y)") (class "Default")
      (node (ref "U42") (pin "13") (pinfunction "4B_13") (pintype "input"))
      (node (ref "U42") (pin "8") (pinfunction "3Y_8") (pintype "output"))
    )
    (net (code "286") (name "Net-(U43-A)") (class "Default")
      (node (ref "R184") (pin "1") (pinfunction "1_1") (pintype "passive"))
      (node (ref "U43") (pin "1") (pinfunction "A_1") (pintype "passive"))
    )
    (net (code "287") (name "Net-(U43-CT)") (class "Default")
      (node (ref "R196") (pin "2") (pinfunction "2_2") (pintype "passive"))
      (node (ref "U43") (pin "4") (pinfunction "CT_4") (pintype "passive"))
    )
    (net (code "288") (name "Net-(U45-VOA)") (class "Default")
      (node (ref "R189") (pin "2") (pinfunction "2_2") (pintype "passive"))
      (node (ref "U45") (pin "7") (pinfunction "VOA_7") (pintype "output"))
    )
    (net (code "289") (name "Net-(U45-VOB)") (class "Default")
      (node (ref "R190") (pin "2") (pinfunction "2_2") (pintype "passive"))
      (node (ref "U45") (pin "6") (pinfunction "VOB_6") (pintype "output"))
    )
    (net (code "290") (name "Net-(U46-VOA)") (class "Default")
      (node (ref "R191") (pin "2") (pinfunction "2_2") (pintype "passive"))
      (node (ref "U46") (pin "7") (pinfunction "VOA_7") (pintype "output"))
    )
    (net (code "291") (name "Net-(U46-VOB)") (class "Default")
      (node (ref "R192") (pin "2") (pinfunction "2_2") (pintype "passive"))
      (node (ref "U46") (pin "6") (pinfunction "VOB_6") (pintype "output"))
    )
    (net (code "292") (name "Net-(U47-A)") (class "Default")
      (node (ref "R80") (pin "2") (pinfunction "2_2") (pintype "passive"))
      (node (ref "U47") (pin "1") (pinfunction "A_1") (pintype "passive"))
    )
    (net (code "293") (name "Net-(U48-A)") (class "Default")
      (node (ref "R193") (pin "2") (pinfunction "2_2") (pintype "passive"))
      (node (ref "U48") (pin "1") (pinfunction "A_1") (pintype "passive"))
    )
    (net (code "294") (name "Net-(U49-A)") (class "Default")
      (node (ref "R195") (pin "2") (pinfunction "2_2") (pintype "passive"))
      (node (ref "U49") (pin "1") (pinfunction "A_1") (pintype "passive"))
    )
    (net (code "295") (name "Net-(U50-CTRL)") (class "Default")
      (node (ref "C142") (pin "1") (pinfunction "1_1") (pintype "passive"))
      (node (ref "U50") (pin "5") (pinfunction "CTRL_5") (pintype "power_in"))
    )
    (net (code "296") (name "Net-(Y1-2)") (class "Default")
      (node (ref "C38") (pin "1") (pinfunction "1_1") (pintype "passive"))
      (node (ref "R131") (pin "1") (pinfunction "1_1") (pintype "passive"))
      (node (ref "Y1") (pin "3") (pinfunction "2_3") (pintype "passive"))
    )
    (net (code "297") (name "Net-(Y3-2)") (class "Default")
      (node (ref "C120") (pin "1") (pinfunction "1_1") (pintype "passive"))
      (node (ref "R147") (pin "2") (pinfunction "2_2") (pintype "passive"))
      (node (ref "R149") (pin "1") (pinfunction "1_1") (pintype "passive"))
      (node (ref "Y3") (pin "3") (pinfunction "2_3") (pintype "passive"))
    )
    (net (code "298") (name "OCP1_THRS") (class "Default")
      (node (ref "R130") (pin "2") (pinfunction "2_2") (pintype "passive"))
      (node (ref "R133") (pin "1") (pinfunction "1_1") (pintype "passive"))
      (node (ref "R211") (pin "1") (pinfunction "1_1") (pintype "passive"))
      (node (ref "R215") (pin "1") (pinfunction "1_1") (pintype "passive"))
    )
    (net (code "299") (name "OVERCURRENT_L") (class "Default")
      (node (ref "C106") (pin "1") (pinfunction "1_1") (pintype "passive"))
      (node (ref "R42") (pin "1") (pinfunction "1_1") (pintype "passive"))
      (node (ref "U42") (pin "9") (pinfunction "3A_9") (pintype "input"))
    )
    (net (code "300") (name "PB2{slash}BOOT1") (class "Default")
      (node (ref "D29") (pin "A") (pinfunction "A_A") (pintype "passive"))
      (node (ref "R7") (pin "2") (pinfunction "2_2") (pintype "passive"))
      (node (ref "U17") (pin "37") (pinfunction "PB2/BOOT1_37") (pintype "bidirectional"))
    )
    (net (code "301") (name "PENDANT_VCC_5V0") (class "Default")
      (node (ref "C61") (pin "1") (pinfunction "1_1") (pintype "passive"))
      (node (ref "C64") (pin "1") (pinfunction "1_1") (pintype "passive"))
      (node (ref "D41") (pin "C") (pinfunction "-_C") (pintype "passive"))
      (node (ref "J14") (pin "1") (pinfunction "1_1") (pintype "passive"))
      (node (ref "L10") (pin "2") (pinfunction "2_2") (pintype "passive"))
      (node (ref "R88") (pin "2") (pinfunction "2_2") (pintype "passive"))
      (node (ref "R91") (pin "2") (pinfunction "2_2") (pintype "passive"))
      (node (ref "R93") (pin "2") (pinfunction "2_2") (pintype "passive"))
      (node (ref "U19") (pin "3") (pinfunction "VCC_3") (pintype "power_in"))
    )
    (net (code "302") (name "PEND_GND") (class "Default")
      (node (ref "C135") (pin "1") (pinfunction "1_1") (pintype "passive"))
      (node (ref "C61") (pin "2") (pinfunction "2_2") (pintype "passive"))
      (node (ref "C63") (pin "1") (pinfunction "1_1") (pintype "passive"))
      (node (ref "C64") (pin "2") (pinfunction "2_2") (pintype "passive"))
      (node (ref "D41") (pin "A") (pinfunction "+_A") (pintype "passive"))
      (node (ref "J14") (pin "6") (pinfunction "6_6") (pintype "passive"))
      (node (ref "L11") (pin "2") (pinfunction "2_2") (pintype "passive"))
      (node (ref "R86") (pin "1") (pinfunction "1_1") (pintype "passive"))
      (node (ref "U18") (pin "5") (pinfunction "GND2_5") (pintype "bidirectional"))
      (node (ref "U19") (pin "2") (pinfunction "GND_2") (pintype "power_in"))
    )
    (net (code "303") (name "PH_OSC_IN") (class "Default")
      (node (ref "C39") (pin "1") (pinfunction "1_1") (pintype "passive"))
      (node (ref "U17") (pin "12") (pinfunction "PH0/OSC_IN_12") (pintype "bidirectional"))
      (node (ref "Y1") (pin "1") (pinfunction "1_1") (pintype "passive"))
    )
    (net (code "304") (name "PH_OSC_OUT") (class "Default")
      (node (ref "R131") (pin "2") (pinfunction "2_2") (pintype "passive"))
      (node (ref "U17") (pin "13") (pinfunction "PH1/OSC_OUT_13") (pintype "bidirectional"))
    )
    (net (code "305") (name "POWER_IND") (class "Default")
      (node (ref "P24") (pin "05") (pinfunction "05_05") (pintype "passive"))
      (node (ref "U43") (pin "3") (pinfunction "ET_3") (pintype "passive"))
    )
    (net (code "306") (name "PROBE") (class "Default")
      (node (ref "C3_PRB") (pin "1") (pinfunction "1_1") (pintype "passive"))
      (node (ref "R12") (pin "2") (pinfunction "2_2") (pintype "passive"))
      (node (ref "R22_PRB") (pin "2") (pinfunction "2_2") (pintype "passive"))
      (node (ref "U17") (pin "33") (pinfunction "PC4_33") (pintype "bidirectional"))
      (node (ref "U2_PRB") (pin "4") (pinfunction "CT_4") (pintype "passive"))
    )
    (net (code "307") (name "PROBE2") (class "Default")
      (node (ref "C3_TLO") (pin "1") (pinfunction "1_1") (pintype "passive"))
      (node (ref "R11") (pin "2") (pinfunction "2_2") (pintype "passive"))
      (node (ref "R22_TLO") (pin "2") (pinfunction "2_2") (pintype "passive"))
      (node (ref "U17") (pin "9") (pinfunction "PC15_9") (pintype "bidirectional"))
      (node (ref "U2_TLO") (pin "4") (pinfunction "CT_4") (pintype "passive"))
    )
    (net (code "308") (name "PROBE_EXT") (class "Default")
      (node (ref "J3") (pin "2") (pinfunction "1_2") (pintype "passive"))
      (node (ref "U2_PRB") (pin "2") (pinfunction "C_2") (pintype "passive"))
    )
    (net (code "309") (name "PROBE_TLO_EXT") (class "Default")
      (node (ref "J2") (pin "2") (pinfunction "2_2") (pintype "bidirectional"))
      (node (ref "U2_TLO") (pin "2") (pinfunction "C_2") (pintype "passive"))
    )
    (net (code "310") (name "PRU_RESET") (class "Default")
      (node (ref "J1") (pin "16") (pinfunction "16_16") (pintype "bidirectional"))
      (node (ref "TP21") (pin "TP") (pinfunction "TP_TP") (pintype "input"))
      (node (ref "U17") (pin "57") (pinfunction "PD10/USART3_CK_57") (pintype "bidirectional"))
    )
    (net (code "311") (name "PWR_EN") (class "Default")
      (node (ref "C113") (pin "1") (pinfunction "1_1") (pintype "passive"))
      (node (ref "R30") (pin "2") (pinfunction "2_2") (pintype "passive"))
      (node (ref "R43") (pin "1") (pinfunction "1_1") (pintype "passive"))
      (node (ref "S1") (pin "CENTER") (pinfunction "CENTER_CENTER") (pintype "bidirectional"))
      (node (ref "U24") (pin "1") (pinfunction "EN_UVLO_1") (pintype "input"))
    )
    (net (code "312") (name "PWR_IN_36-80V") (class "Default")
      (node (ref "C115") (pin "1") (pinfunction "1_1") (pintype "passive"))
      (node (ref "C144") (pin "1") (pinfunction "1_1") (pintype "passive"))
      (node (ref "C145") (pin "1") (pinfunction "1_1") (pintype "passive"))
      (node (ref "C69") (pin "1") (pinfunction "1_1") (pintype "passive"))
      (node (ref "C74") (pin "1") (pinfunction "1_1") (pintype "passive"))
      (node (ref "D14") (pin "1") (pinfunction "C_1") (pintype "passive"))
      (node (ref "Q14") (pin "10") (pinfunction "DRAIN_10") (pintype "passive"))
      (node (ref "Q14") (pin "11") (pinfunction "DRAIN_11") (pintype "passive"))
      (node (ref "Q14") (pin "12") (pinfunction "DRAIN_12") (pintype "passive"))
      (node (ref "Q14") (pin "5") (pinfunction "DRAIN_5") (pintype "passive"))
      (node (ref "Q14") (pin "6") (pinfunction "DRAIN_6") (pintype "passive"))
      (node (ref "Q14") (pin "7") (pinfunction "DRAIN_7") (pintype "passive"))
      (node (ref "Q14") (pin "8") (pinfunction "DRAIN_8") (pintype "passive"))
      (node (ref "Q14") (pin "9") (pinfunction "DRAIN_9") (pintype "passive"))
      (node (ref "R29") (pin "1") (pinfunction "1_1") (pintype "passive"))
      (node (ref "R30") (pin "1") (pinfunction "1_1") (pintype "passive"))
    )
    (net (code "313") (name "RE") (class "Default")
      (node (ref "R52") (pin "1") (pinfunction "1_1") (pintype "passive"))
      (node (ref "U13") (pin "2") (pinfunction "~{RE}_2") (pintype "input"))
      (node (ref "U13") (pin "3") (pinfunction "DE_3") (pintype "input"))
      (node (ref "U15") (pin "3") (pinfunction "ET_3") (pintype "passive"))
    )
    (net (code "314") (name "RELAY_ACT") (class "Default")
      (node (ref "C141") (pin "1") (pinfunction "1_1") (pintype "passive"))
      (node (ref "D56") (pin "C") (pinfunction "C_C") (pintype "passive"))
      (node (ref "R198") (pin "2") (pinfunction "2_2") (pintype "passive"))
      (node (ref "R199") (pin "2") (pinfunction "2_2") (pintype "passive"))
      (node (ref "U25") (pin "1") (pinfunction "B_1") (pintype "input"))
      (node (ref "U42") (pin "6") (pinfunction "2Y_6") (pintype "output"))
    )
    (net (code "315") (name "RELAY_GATE") (class "Default")
      (node (ref "Q17") (pin "D") (pinfunction "D_D") (pintype "passive"))
      (node (ref "R128") (pin "1") (pinfunction "1_1") (pintype "passive"))
      (node (ref "R182") (pin "2") (pinfunction "2_2") (pintype "passive"))
      (node (ref "R198") (pin "1") (pinfunction "1_1") (pintype "passive"))
    )
    (net (code "316") (name "RELAY_GATE_N") (class "Default")
      (node (ref "U42") (pin "3") (pinfunction "1Y_3") (pintype "output"))
      (node (ref "U42") (pin "4") (pinfunction "2A_4") (pintype "input"))
      (node (ref "U42") (pin "5") (pinfunction "2B_5") (pintype "input"))
      (node (ref "U44") (pin "2") (pinfunction "B_2") (pintype "input"))
    )
    (net (code "317") (name "RING_LED_OUT") (class "Default")
      (node (ref "J18") (pin "2") (pinfunction "2_2") (pintype "passive"))
      (node (ref "R28") (pin "1") (pinfunction "1_1") (pintype "passive"))
    )
    (net (code "318") (name "RO") (class "Default")
      (node (ref "R47") (pin "1") (pinfunction "1_1") (pintype "passive"))
      (node (ref "U12") (pin "7") (pinfunction "VIA_7") (pintype "bidirectional"))
      (node (ref "U13") (pin "1") (pinfunction "R_1") (pintype "input"))
    )
    (net (code "319") (name "RS485_DIR") (class "Default")
      (node (ref "R51") (pin "2") (pinfunction "2_2") (pintype "passive"))
      (node (ref "U17") (pin "35") (pinfunction "PB0_35") (pintype "bidirectional"))
    )
    (net (code "320") (name "RT") (class "Default")
      (node (ref "R179") (pin "1") (pinfunction "1_1") (pintype "passive"))
      (node (ref "U24") (pin "2") (pinfunction "RT_2") (pintype "input"))
    )
    (net (code "321") (name "RXD_AUX") (class "Default")
      (node (ref "TP9") (pin "TP") (pinfunction "TP_TP") (pintype "input"))
      (node (ref "U17") (pin "34") (pinfunction "PC5_34") (pintype "bidirectional"))
      (node (ref "U20") (pin "2") (pinfunction "VOA_2") (pintype "bidirectional"))
    )
    (net (code "322") (name "RXD_INT") (class "Default")
      (node (ref "R72") (pin "1") (pinfunction "1_1") (pintype "passive"))
      (node (ref "TP15") (pin "TP") (pinfunction "TP_TP") (pintype "input"))
      (node (ref "U17") (pin "69") (pinfunction "PA10/OTG_FS_ID_69") (pintype "bidirectional"))
    )
    (net (code "323") (name "RXD_RS485") (class "Default")
      (node (ref "R53") (pin "1") (pinfunction "1_1") (pintype "passive"))
      (node (ref "U12") (pin "2") (pinfunction "VOA_2") (pintype "bidirectional"))
      (node (ref "U17") (pin "87") (pinfunction "PD6/USART2_RX_87") (pintype "bidirectional"))
    )
    (net (code "324") (name "RX_C_N") (class "Default")
      (node (ref "C110") (pin "1") (pinfunction "1_1") (pintype "passive"))
      (node (ref "P12") (pin "6") (pinfunction "RD-_6") (pintype "passive"))
    )
    (net (code "325") (name "RX_C_P") (class "Default")
      (node (ref "C111") (pin "1") (pinfunction "1_1") (pintype "passive"))
      (node (ref "P12") (pin "3") (pinfunction "RD+_3") (pintype "passive"))
    )
    (net (code "326") (name "RX_N") (class "Default")
      (node (ref "C110") (pin "2") (pinfunction "2_2") (pintype "passive"))
      (node (ref "R137") (pin "2") (pinfunction "2_2") (pintype "passive"))
      (node (ref "R141") (pin "2") (pinfunction "2_2") (pintype "passive"))
    )
    (net (code "327") (name "RX_P") (class "Default")
      (node (ref "C111") (pin "2") (pinfunction "2_2") (pintype "passive"))
      (node (ref "R136") (pin "2") (pinfunction "2_2") (pintype "passive"))
      (node (ref "R142") (pin "2") (pinfunction "2_2") (pintype "passive"))
    )
    (net (code "328") (name "SCL") (class "Default")
      (node (ref "P9") (pin "2") (pinfunction "2_2") (pintype "passive"))
      (node (ref "R66") (pin "1") (pinfunction "1_1") (pintype "passive"))
      (node (ref "TP11") (pin "TP") (pinfunction "TP_TP") (pintype "input"))
      (node (ref "U17") (pin "93") (pinfunction "PB7/TIM4_CH2_93") (pintype "bidirectional"))
      (node (ref "U35") (pin "6") (pinfunction "SCL_6") (pintype "input"))
    )
    (net (code "329") (name "SDA") (class "Default")
      (node (ref "P9") (pin "3") (pinfunction "3_3") (pintype "passive"))
      (node (ref "R65") (pin "1") (pinfunction "1_1") (pintype "passive"))
      (node (ref "TP13") (pin "TP") (pinfunction "TP_TP") (pintype "input"))
      (node (ref "U17") (pin "92") (pinfunction "PB6/CAN2_TX/TIM4_CH1_92") (pintype "bidirectional"))
      (node (ref "U35") (pin "5") (pinfunction "SDA_5") (pintype "bidirectional"))
    )
    (net (code "330") (name "SD_CSN") (class "Default")
      (node (ref "SD3") (pin "2") (pinfunction "CD/DAT3(~{CS})_2") (pintype "bidirectional"))
      (node (ref "U17") (pin "54") (pinfunction "PB15/SPI2_MOSI_54") (pintype "bidirectional"))
    )
    (net (code "331") (name "SG_X") (class "Default")
      (node (ref "C51") (pin "1") (pinfunction "1_1") (pintype "passive"))
      (node (ref "R205") (pin "1") (pinfunction "1_1") (pintype "passive"))
      (node (ref "R27") (pin "1") (pinfunction "1_1") (pintype "passive"))
      (node (ref "TP22") (pin "TP") (pinfunction "TP_TP") (pintype "input"))
      (node (ref "U17") (pin "77") (pinfunction "PA15/JTDI_77") (pintype "bidirectional"))
      (node (ref "U39") (pin "4") (pinfunction "CT_4") (pintype "passive"))
    )
    (net (code "332") (name "SG_Y1") (class "Default")
      (node (ref "C72") (pin "1") (pinfunction "1_1") (pintype "passive"))
      (node (ref "R206") (pin "1") (pinfunction "1_1") (pintype "passive"))
      (node (ref "R79") (pin "1") (pinfunction "1_1") (pintype "passive"))
      (node (ref "TP23") (pin "TP") (pinfunction "TP_TP") (pintype "input"))
      (node (ref "U17") (pin "24") (pinfunction "PA1/UART4_RX_24") (pintype "bidirectional"))
      (node (ref "U47") (pin "4") (pinfunction "CT_4") (pintype "passive"))
    )
    (net (code "333") (name "SG_Y2") (class "Default")
      (node (ref "C138") (pin "1") (pinfunction "1_1") (pintype "passive"))
      (node (ref "R194") (pin "1") (pinfunction "1_1") (pintype "passive"))
      (node (ref "R207") (pin "1") (pinfunction "1_1") (pintype "passive"))
      (node (ref "TP26") (pin "TP") (pinfunction "TP_TP") (pintype "input"))
      (node (ref "U17") (pin "26") (pinfunction "PA3/USART2_RX_26") (pintype "bidirectional"))
      (node (ref "U49") (pin "4") (pinfunction "CT_4") (pintype "passive"))
    )
    (net (code "334") (name "SG_Z") (class "Default")
      (node (ref "C137") (pin "1") (pinfunction "1_1") (pintype "passive"))
      (node (ref "R208") (pin "1") (pinfunction "1_1") (pintype "passive"))
      (node (ref "R81") (pin "1") (pinfunction "1_1") (pintype "passive"))
      (node (ref "TP24") (pin "TP") (pinfunction "TP_TP") (pintype "input"))
      (node (ref "U17") (pin "25") (pinfunction "PA2/USART2_TX_25") (pintype "bidirectional"))
      (node (ref "U48") (pin "4") (pinfunction "CT_4") (pintype "passive"))
    )
    (net (code "335") (name "SPI1_CS_JOG_SW") (class "Default")
      (node (ref "J1") (pin "1") (pinfunction "1_1") (pintype "bidirectional"))
      (node (ref "TP3") (pin "TP") (pinfunction "TP_TP") (pintype "input"))
      (node (ref "U11") (pin "32") (pinfunction "~{SCSN}_32") (pintype "input"))
      (node (ref "U17") (pin "29") (pinfunction "PA4_29") (pintype "bidirectional"))
    )
    (net (code "336") (name "SPI1_SCK") (class "Default")
      (node (ref "R74") (pin "2") (pinfunction "2_2") (pintype "passive"))
      (node (ref "TP4") (pin "TP") (pinfunction "TP_TP") (pintype "input"))
      (node (ref "U17") (pin "30") (pinfunction "PA5/SPI1_SCK_30") (pintype "bidirectional"))
    )
    (net (code "337") (name "SPINDLE_CONN") (class "Default")
      (node (ref "J9") (pin "04") (pinfunction "04_04") (pintype "passive"))
      (node (ref "U3") (pin "4") (pinfunction "2Y_4") (pintype "output"))
    )
    (net (code "338") (name "SPINDLE_DIR") (class "Default")
      (node (ref "R31") (pin "2") (pinfunction "2_2") (pintype "passive"))
      (node (ref "U17") (pin "36") (pinfunction "PB1_36") (pintype "bidirectional"))
    )
    (net (code "339") (name "SPINDLE_EN") (class "Default")
      (node (ref "Q11") (pin "P1") (pinfunction "G_P1") (pintype "passive"))
      (node (ref "R84") (pin "1") (pinfunction "1_1") (pintype "passive"))
      (node (ref "U17") (pin "44") (pinfunction "PE13/TIM1_CH3_44") (pintype "bidirectional"))
    )
    (net (code "340") (name "SPINDLE_EN_5V") (class "Default")
      (node (ref "P11") (pin "37") (pinfunction "37_37") (pintype "passive"))
      (node (ref "U7") (pin "3") (pinfunction "ET_3") (pintype "passive"))
    )
    (net (code "341") (name "SPINDLE_PWM") (class "Default")
      (node (ref "Q4") (pin "P1") (pinfunction "G_P1") (pintype "passive"))
      (node (ref "R153") (pin "2") (pinfunction "2_2") (pintype "passive"))
      (node (ref "R25") (pin "2") (pinfunction "2_2") (pintype "passive"))
      (node (ref "U17") (pin "67") (pinfunction "PA8_67") (pintype "bidirectional"))
    )
    (net (code "342") (name "SPINDLE_PWM_ISO") (class "Default")
      (node (ref "R26") (pin "1") (pinfunction "1_1") (pintype "passive"))
      (node (ref "U3") (pin "3") (pinfunction "2A_3") (pintype "input"))
      (node (ref "U4") (pin "3") (pinfunction "ET_3") (pintype "passive"))
    )
    (net (code "343") (name "SPIN_AT_SPEED") (class "Default")
      (node (ref "J9") (pin "01") (pinfunction "01_01") (pintype "passive"))
      (node (ref "R165") (pin "2") (pinfunction "2_2") (pintype "passive"))
    )
    (net (code "344") (name "SPIN_DIR_12V") (class "Default")
      (node (ref "J9") (pin "03") (pinfunction "03_03") (pintype "passive"))
      (node (ref "U5") (pin "4") (pinfunction "CT_4") (pintype "passive"))
    )
    (net (code "345") (name "SPIN_EN") (class "Default")
      (node (ref "Q11") (pin "P3") (pinfunction "D_P3") (pintype "passive"))
      (node (ref "U6") (pin "2") (pinfunction "C_2") (pintype "passive"))
      (node (ref "U7") (pin "2") (pinfunction "C_2") (pintype "passive"))
    )
    (net (code "346") (name "SPIN_EN_12V") (class "Default")
      (node (ref "J9") (pin "02") (pinfunction "02_02") (pintype "passive"))
      (node (ref "U6") (pin "4") (pinfunction "CT_4") (pintype "passive"))
    )
    (net (code "347") (name "SPIN_SPEED") (class "Default")
      (node (ref "C73") (pin "1") (pinfunction "1_1") (pintype "passive"))
      (node (ref "R164") (pin "1") (pinfunction "1_1") (pintype "passive"))
      (node (ref "U17") (pin "95") (pinfunction "PB8/TIM4_CH3_95") (pintype "bidirectional"))
      (node (ref "U23") (pin "4") (pinfunction "CT_4") (pintype "passive"))
    )
    (net (code "348") (name "SPI_CLK") (class "Default")
      (node (ref "J1") (pin "13") (pinfunction "13_13") (pintype "bidirectional"))
      (node (ref "R74") (pin "1") (pinfunction "1_1") (pintype "passive"))
      (node (ref "SD3") (pin "5") (pinfunction "CLK(SCLK)_5") (pintype "input"))
      (node (ref "U11") (pin "33") (pinfunction "SCLK_33") (pintype "input"))
    )
    (net (code "349") (name "SPI_MISO") (class "Default")
      (node (ref "R75") (pin "2") (pinfunction "2_2") (pintype "passive"))
      (node (ref "TP6") (pin "TP") (pinfunction "TP_TP") (pintype "input"))
      (node (ref "U17") (pin "31") (pinfunction "PA6/SPI1_MISO_31") (pintype "bidirectional"))
    )
    (net (code "350") (name "SPI_MOSI") (class "Default")
      (node (ref "R76") (pin "2") (pinfunction "2_2") (pintype "passive"))
      (node (ref "TP5") (pin "TP") (pinfunction "TP_TP") (pintype "input"))
      (node (ref "U17") (pin "32") (pinfunction "PA7/SPI1_MOSI_32") (pintype "bidirectional"))
    )
    (net (code "351") (name "SPI_PICO") (class "Default")
      (node (ref "J1") (pin "5") (pinfunction "5_5") (pintype "bidirectional"))
      (node (ref "R76") (pin "1") (pinfunction "1_1") (pintype "passive"))
      (node (ref "SD3") (pin "3") (pinfunction "CMD(DI)_3") (pintype "bidirectional"))
      (node (ref "U11") (pin "35") (pinfunction "MOSI_35") (pintype "input"))
    )
    (net (code "352") (name "SPI_POCI") (class "Default")
      (node (ref "J1") (pin "9") (pinfunction "9_9") (pintype "bidirectional"))
      (node (ref "R75") (pin "1") (pinfunction "1_1") (pintype "passive"))
      (node (ref "SD3") (pin "7") (pinfunction "DAT0(DO)_7") (pintype "bidirectional"))
      (node (ref "U11") (pin "34") (pinfunction "MISO_34") (pintype "output"))
    )
    (net (code "353") (name "START_EXT") (class "Default")
      (node (ref "P24") (pin "02") (pinfunction "02_02") (pintype "passive"))
      (node (ref "U2_CY") (pin "2") (pinfunction "C_2") (pintype "passive"))
    )
    (net (code "354") (name "STEP_A") (class "Default")
      (node (ref "R114") (pin "2") (pinfunction "2_2") (pintype "passive"))
      (node (ref "TP47") (pin "TP") (pinfunction "TP_TP") (pintype "input"))
      (node (ref "U17") (pin "47") (pinfunction "PB10/USART3_TX_47") (pintype "bidirectional"))
    )
    (net (code "355") (name "STEP_A_EXT") (class "Default")
      (node (ref "P11") (pin "2") (pinfunction "2_2") (pintype "passive"))
      (node (ref "P20") (pin "1") (pinfunction "1_1") (pintype "passive"))
      (node (ref "R170") (pin "1") (pinfunction "1_1") (pintype "passive"))
      (node (ref "U29") (pin "3") (pinfunction "ET_3") (pintype "passive"))
    )
    (net (code "356") (name "STEP_EN_A") (class "Default")
      (node (ref "R118") (pin "2") (pinfunction "2_2") (pintype "passive"))
      (node (ref "R98") (pin "2") (pinfunction "2_2") (pintype "passive"))
      (node (ref "TP42") (pin "TP") (pinfunction "TP_TP") (pintype "input"))
      (node (ref "U17") (pin "78") (pinfunction "PC10/SPI3_SCK/UART4_TX_78") (pintype "bidirectional"))
    )
    (net (code "357") (name "STEP_EN_X") (class "Default")
      (node (ref "R185") (pin "1") (pinfunction "1_1") (pintype "passive"))
      (node (ref "TP35") (pin "TP") (pinfunction "TP_TP") (pintype "input"))
      (node (ref "U17") (pin "85") (pinfunction "PD4/USART2_RTS_85") (pintype "bidirectional"))
      (node (ref "U45") (pin "2") (pinfunction "VIA_2") (pintype "input"))
    )
    (net (code "358") (name "STEP_EN_YY") (class "Default")
      (node (ref "R186") (pin "1") (pinfunction "1_1") (pintype "passive"))
      (node (ref "R187") (pin "1") (pinfunction "1_1") (pintype "passive"))
      (node (ref "TP39") (pin "TP") (pinfunction "TP_TP") (pintype "input"))
      (node (ref "TP41") (pin "TP") (pinfunction "TP_TP") (pintype "input"))
      (node (ref "U17") (pin "64") (pinfunction "PC7/TIM3_CH2/USART6_RX_64") (pintype "bidirectional"))
      (node (ref "U45") (pin "3") (pinfunction "VIB_3") (pintype "input"))
      (node (ref "U46") (pin "2") (pinfunction "VIA_2") (pintype "input"))
    )
    (net (code "359") (name "STEP_EN_Z") (class "Default")
      (node (ref "R188") (pin "1") (pinfunction "1_1") (pintype "passive"))
      (node (ref "TP40") (pin "TP") (pinfunction "TP_TP") (pintype "input"))
      (node (ref "U17") (pin "84") (pinfunction "PD3/USART2_CTS_84") (pintype "bidirectional"))
      (node (ref "U46") (pin "3") (pinfunction "VIB_3") (pintype "input"))
    )
    (net (code "360") (name "STEP_X") (class "Default")
      (node (ref "TP43") (pin "TP") (pinfunction "TP_TP") (pintype "input"))
      (node (ref "U17") (pin "1") (pinfunction "PE2/TRACECLK_1") (pintype "bidirectional"))
      (node (ref "U26") (pin "2") (pinfunction "VIA_2") (pintype "input"))
    )
    (net (code "361") (name "STEP_X_N") (class "Default")
      (node (ref "P13") (pin "2") (pinfunction "2_2") (pintype "passive"))
      (node (ref "U9") (pin "3") (pinfunction "1Z_3") (pintype "output"))
    )
    (net (code "362") (name "STEP_X_OUT") (class "Default")
      (node (ref "U26") (pin "7") (pinfunction "VOA_7") (pintype "output"))
      (node (ref "U9") (pin "1") (pinfunction "1A_1") (pintype "input"))
    )
    (net (code "363") (name "STEP_X_P") (class "Default")
      (node (ref "P13") (pin "1") (pinfunction "1_1") (pintype "passive"))
      (node (ref "U9") (pin "2") (pinfunction "1Y_2") (pintype "output"))
    )
    (net (code "364") (name "STEP_Y1") (class "Default")
      (node (ref "TP44") (pin "TP") (pinfunction "TP_TP") (pintype "input"))
      (node (ref "U17") (pin "2") (pinfunction "PE3/TRACED0_2") (pintype "bidirectional"))
      (node (ref "U27") (pin "2") (pinfunction "VIA_2") (pintype "input"))
    )
    (net (code "365") (name "STEP_Y1_N") (class "Default")
      (node (ref "P14") (pin "2") (pinfunction "2_2") (pintype "passive"))
      (node (ref "U9") (pin "13") (pinfunction "4Z_13") (pintype "output"))
    )
    (net (code "366") (name "STEP_Y1_OUT") (class "Default")
      (node (ref "U27") (pin "7") (pinfunction "VOA_7") (pintype "output"))
      (node (ref "U9") (pin "15") (pinfunction "4A_15") (pintype "input"))
    )
    (net (code "367") (name "STEP_Y1_P") (class "Default")
      (node (ref "P14") (pin "1") (pinfunction "1_1") (pintype "passive"))
      (node (ref "U9") (pin "14") (pinfunction "4Y_14") (pintype "output"))
    )
    (net (code "368") (name "STEP_Y2") (class "Default")
      (node (ref "TP46") (pin "TP") (pinfunction "TP_TP") (pintype "input"))
      (node (ref "U17") (pin "4") (pinfunction "PE5/TRACED2/TIM9_CH1_4") (pintype "bidirectional"))
      (node (ref "U37") (pin "2") (pinfunction "VIA_2") (pintype "input"))
    )
    (net (code "369") (name "STEP_Y2_N") (class "Default")
      (node (ref "P16") (pin "2") (pinfunction "2_2") (pintype "passive"))
      (node (ref "U36") (pin "3") (pinfunction "1Z_3") (pintype "output"))
    )
    (net (code "370") (name "STEP_Y2_OUT") (class "Default")
      (node (ref "U36") (pin "1") (pinfunction "1A_1") (pintype "input"))
      (node (ref "U37") (pin "7") (pinfunction "VOA_7") (pintype "output"))
    )
    (net (code "371") (name "STEP_Y2_P") (class "Default")
      (node (ref "P16") (pin "1") (pinfunction "1_1") (pintype "passive"))
      (node (ref "U36") (pin "2") (pinfunction "1Y_2") (pintype "output"))
    )
    (net (code "372") (name "STEP_Z") (class "Default")
      (node (ref "TP45") (pin "TP") (pinfunction "TP_TP") (pintype "input"))
      (node (ref "U17") (pin "3") (pinfunction "PE4/TRACED1_3") (pintype "bidirectional"))
      (node (ref "U38") (pin "2") (pinfunction "VIA_2") (pintype "input"))
    )
    (net (code "373") (name "STEP_Z_N") (class "Default")
      (node (ref "P27") (pin "2") (pinfunction "2_2") (pintype "passive"))
      (node (ref "U36") (pin "13") (pinfunction "4Z_13") (pintype "output"))
    )
    (net (code "374") (name "STEP_Z_OUT") (class "Default")
      (node (ref "U36") (pin "15") (pinfunction "4A_15") (pintype "input"))
      (node (ref "U38") (pin "7") (pinfunction "VOA_7") (pintype "output"))
    )
    (net (code "375") (name "STEP_Z_P") (class "Default")
      (node (ref "P27") (pin "1") (pinfunction "1_1") (pintype "passive"))
      (node (ref "U36") (pin "14") (pinfunction "4Y_14") (pintype "output"))
    )
    (net (code "376") (name "STM_BOOT0") (class "Default")
      (node (ref "C21") (pin "1") (pinfunction "1_1") (pintype "passive"))
      (node (ref "J1") (pin "14") (pinfunction "14_14") (pintype "bidirectional"))
      (node (ref "P25") (pin "2") (pinfunction "2_2") (pintype "passive"))
      (node (ref "R2") (pin "2") (pinfunction "2_2") (pintype "passive"))
      (node (ref "R61") (pin "2") (pinfunction "2_2") (pintype "passive"))
      (node (ref "U17") (pin "94") (pinfunction "BOOT0_94") (pintype "bidirectional"))
    )
    (net (code "377") (name "STM_NRST") (class "Default")
      (node (ref "C22") (pin "1") (pinfunction "1_1") (pintype "passive"))
      (node (ref "J1") (pin "10") (pinfunction "10_10") (pintype "bidirectional"))
      (node (ref "P15") (pin "10") (pinfunction "6_10") (pintype "passive"))
      (node (ref "P26") (pin "2") (pinfunction "2_2") (pintype "passive"))
      (node (ref "R62") (pin "1") (pinfunction "1_1") (pintype "passive"))
      (node (ref "U17") (pin "14") (pinfunction "/RST_14") (pintype "bidirectional"))
    )
    (net (code "378") (name "STP_ALARM_5V_N") (class "Default")
      (node (ref "P11") (pin "10") (pinfunction "10_10") (pintype "passive"))
      (node (ref "P20") (pin "8") (pinfunction "8_8") (pintype "passive"))
      (node (ref "U32") (pin "2") (pinfunction "C_2") (pintype "passive"))
    )
    (net (code "379") (name "SWCLK") (class "Default")
      (node (ref "P15") (pin "4") (pinfunction "9_4") (pintype "passive"))
      (node (ref "R4") (pin "2") (pinfunction "2_2") (pintype "passive"))
      (node (ref "TP38") (pin "TP") (pinfunction "TP_TP") (pintype "input"))
      (node (ref "U17") (pin "76") (pinfunction "PA14/JTCK-SWCLK_76") (pintype "bidirectional"))
    )
    (net (code "380") (name "SWDIO{slash}ALT_NEOPIXEL") (class "Default")
      (node (ref "P15") (pin "2") (pinfunction "10_2") (pintype "passive"))
      (node (ref "R3") (pin "2") (pinfunction "2_2") (pintype "passive"))
      (node (ref "TP37") (pin "TP") (pinfunction "TP_TP") (pintype "input"))
      (node (ref "TP61") (pin "TP") (pinfunction "TP_TP") (pintype "input"))
      (node (ref "U14") (pin "3") (pinfunction "VIB_3") (pintype "input"))
      (node (ref "U17") (pin "72") (pinfunction "PA13/JTMS-SWDIO_72") (pintype "bidirectional"))
    )
    (net (code "381") (name "SWO{slash}KPSTR") (class "Default")
      (node (ref "R64") (pin "1") (pinfunction "1_1") (pintype "passive"))
      (node (ref "U17") (pin "89") (pinfunction "PB3/JTDO/TRACESWO_89") (pintype "bidirectional"))
    )
    (net (code "382") (name "TIMER_OUT") (class "Default")
      (node (ref "D58") (pin "A") (pinfunction "A_A") (pintype "passive"))
      (node (ref "Q17") (pin "G") (pinfunction "G_G") (pintype "passive"))
      (node (ref "R202") (pin "1") (pinfunction "1_1") (pintype "passive"))
      (node (ref "U44") (pin "1") (pinfunction "A_1") (pintype "input"))
      (node (ref "U50") (pin "3") (pinfunction "OUT_3") (pintype "output"))
    )
    (net (code "383") (name "TRIG") (class "Default")
      (node (ref "C141") (pin "2") (pinfunction "2_2") (pintype "passive"))
      (node (ref "C143") (pin "1") (pinfunction "1_1") (pintype "passive"))
      (node (ref "R200") (pin "2") (pinfunction "2_2") (pintype "passive"))
      (node (ref "R201") (pin "2") (pinfunction "2_2") (pintype "passive"))
      (node (ref "U50") (pin "2") (pinfunction "TRIG_2") (pintype "input"))
      (node (ref "U50") (pin "7") (pinfunction "DIS_7") (pintype "input"))
    )
    (net (code "384") (name "TXD_AUX") (class "Default")
      (node (ref "TP7") (pin "TP") (pinfunction "TP_TP") (pintype "input"))
      (node (ref "U17") (pin "55") (pinfunction "PD8/USART3_TX_55") (pintype "bidirectional"))
      (node (ref "U20") (pin "3") (pinfunction "VIB_3") (pintype "bidirectional"))
    )
    (net (code "385") (name "TXD_INT") (class "Default")
      (node (ref "TP14") (pin "TP") (pinfunction "TP_TP") (pintype "input"))
      (node (ref "U17") (pin "68") (pinfunction "PA9/OTG_FS_VBUS_68") (pintype "bidirectional"))
    )
    (net (code "386") (name "TXD_RS485") (class "Default")
      (node (ref "R54") (pin "1") (pinfunction "1_1") (pintype "passive"))
      (node (ref "U12") (pin "3") (pinfunction "VIB_3") (pintype "bidirectional"))
      (node (ref "U17") (pin "86") (pinfunction "PD5/USART2_TX_86") (pintype "bidirectional"))
    )
    (net (code "387") (name "TX_N") (class "Default")
      (node (ref "P12") (pin "2") (pinfunction "TD-_2") (pintype "passive"))
      (node (ref "R139") (pin "2") (pinfunction "2_2") (pintype "passive"))
      (node (ref "R144") (pin "2") (pinfunction "2_2") (pintype "passive"))
    )
    (net (code "388") (name "TX_P") (class "Default")
      (node (ref "P12") (pin "1") (pinfunction "TD+_1") (pintype "passive"))
      (node (ref "R140") (pin "2") (pinfunction "2_2") (pintype "passive"))
      (node (ref "R145") (pin "2") (pinfunction "2_2") (pintype "passive"))
    )
    (net (code "389") (name "USBC_CC1") (class "Default")
      (node (ref "J20") (pin "A5") (pinfunction "CC1_A5") (pintype "bidirectional"))
      (node (ref "R108") (pin "2") (pinfunction "2_2") (pintype "passive"))
    )
    (net (code "390") (name "USBC_CC2") (class "Default")
      (node (ref "J20") (pin "B5") (pinfunction "CC2_B5") (pintype "bidirectional"))
      (node (ref "R107") (pin "2") (pinfunction "2_2") (pintype "passive"))
    )
    (net (code "391") (name "USB_D_N") (class "Default")
      (node (ref "L13") (pin "2") (pinfunction "2_2") (pintype "passive"))
      (node (ref "R67") (pin "2") (pinfunction "2_2") (pintype "passive"))
    )
    (net (code "392") (name "USB_D_P") (class "Default")
      (node (ref "L13") (pin "3") (pinfunction "3_3") (pintype "passive"))
      (node (ref "R68") (pin "2") (pinfunction "2_2") (pintype "passive"))
    )
    (net (code "393") (name "USB_D_R_N") (class "Default")
      (node (ref "R67") (pin "1") (pinfunction "1_1") (pintype "passive"))
      (node (ref "U17") (pin "70") (pinfunction "PA11/OTG_FS_DM_70") (pintype "bidirectional"))
    )
    (net (code "394") (name "USB_D_R_P") (class "Default")
      (node (ref "R68") (pin "1") (pinfunction "1_1") (pintype "passive"))
      (node (ref "U17") (pin "71") (pinfunction "PA12/OTG_FS_DP_71") (pintype "bidirectional"))
    )
    (net (code "395") (name "VBUS") (class "Default")
      (node (ref "D27") (pin "5") (pinfunction "VBUS_5") (pintype "power_in"))
      (node (ref "J20") (pin "VBUS1") (pinfunction "VBUS_VBUS1") (pintype "bidirectional"))
      (node (ref "J20") (pin "VBUS2") (pinfunction "VBUS_VBUS2") (pintype "bidirectional"))
    )
    (net (code "396") (name "VCAP1") (class "Default")
      (node (ref "C26") (pin "2") (pinfunction "2_2") (pintype "passive"))
      (node (ref "U17") (pin "48") (pinfunction "VCAP_1_48") (pintype "bidirectional"))
    )
    (net (code "397") (name "VCAP2") (class "Default")
      (node (ref "C25") (pin "2") (pinfunction "2_2") (pintype "passive"))
      (node (ref "U17") (pin "73") (pinfunction "VCAP_2_73") (pintype "power_in"))
    )
    (net (code "398") (name "VCC_MCU_3V3") (class "Default")
      (node (ref "C100") (pin "1") (pinfunction "1_1") (pintype "passive"))
      (node (ref "C101") (pin "1") (pinfunction "1_1") (pintype "passive"))
      (node (ref "C102") (pin "1") (pinfunction "1_1") (pintype "passive"))
      (node (ref "C119") (pin "1") (pinfunction "1_1") (pintype "passive"))
      (node (ref "C131") (pin "1") (pinfunction "1_1") (pintype "passive"))
      (node (ref "C132") (pin "1") (pinfunction "1_1") (pintype "passive"))
      (node (ref "C133") (pin "1") (pinfunction "1_1") (pintype "passive"))
      (node (ref "C136") (pin "1") (pinfunction "1_1") (pintype "passive"))
      (node (ref "C2") (pin "1") (pinfunction "1_1") (pintype "passive"))
      (node (ref "C25") (pin "1") (pinfunction "1_1") (pintype "passive"))
      (node (ref "C26") (pin "1") (pinfunction "1_1") (pintype "passive"))
      (node (ref "C27") (pin "1") (pinfunction "1_1") (pintype "passive"))
      (node (ref "C28") (pin "1") (pinfunction "1_1") (pintype "passive"))
      (node (ref "C29") (pin "1") (pinfunction "1_1") (pintype "passive"))
      (node (ref "C30") (pin "1") (pinfunction "1_1") (pintype "passive"))
      (node (ref "C31") (pin "1") (pinfunction "1_1") (pintype "passive"))
      (node (ref "C32") (pin "1") (pinfunction "1_1") (pintype "passive"))
      (node (ref "C33") (pin "1") (pinfunction "1_1") (pintype "passive"))
      (node (ref "C34") (pin "1") (pinfunction "1_1") (pintype "passive"))
      (node (ref "C35") (pin "1") (pinfunction "1_1") (pintype "passive"))
      (node (ref "C36") (pin "1") (pinfunction "1_1") (pintype "passive"))
      (node (ref "C37") (pin "1") (pinfunction "1_1") (pintype "passive"))
      (node (ref "C42") (pin "1") (pinfunction "1_1") (pintype "passive"))
      (node (ref "C43") (pin "1") (pinfunction "1_1") (pintype "passive"))
      (node (ref "C48") (pin "1") (pinfunction "1_1") (pintype "passive"))
      (node (ref "C50") (pin "1") (pinfunction "1_1") (pintype "passive"))
      (node (ref "C59") (pin "1") (pinfunction "1_1") (pintype "passive"))
      (node (ref "C98") (pin "1") (pinfunction "1_1") (pintype "passive"))
      (node (ref "D1") (pin "C") (pinfunction "-_C") (pintype "passive"))
      (node (ref "D10") (pin "A") (pinfunction "A_A") (pintype "passive"))
      (node (ref "D11") (pin "A") (pinfunction "A_A") (pintype "passive"))
      (node (ref "D12") (pin "A") (pinfunction "A_A") (pintype "passive"))
      (node (ref "D13") (pin "A") (pinfunction "A_A") (pintype "passive"))
      (node (ref "D17") (pin "A") (pinfunction "A_A") (pintype "passive"))
      (node (ref "D18") (pin "A") (pinfunction "A_A") (pintype "passive"))
      (node (ref "D24") (pin "A") (pinfunction "A_A") (pintype "passive"))
      (node (ref "D25") (pin "A") (pinfunction "A_A") (pintype "passive"))
      (node (ref "D26") (pin "A") (pinfunction "A_A") (pintype "passive"))
      (node (ref "D3") (pin "A") (pinfunction "A_A") (pintype "passive"))
      (node (ref "D37") (pin "A") (pinfunction "A_A") (pintype "passive"))
      (node (ref "D38") (pin "A") (pinfunction "A_A") (pintype "passive"))
      (node (ref "D39") (pin "A") (pinfunction "A_A") (pintype "passive"))
      (node (ref "D4") (pin "A") (pinfunction "A_A") (pintype "passive"))
      (node (ref "D42") (pin "C") (pinfunction "-_C") (pintype "passive"))
      (node (ref "D5") (pin "A") (pinfunction "A_A") (pintype "passive"))
      (node (ref "D51") (pin "A") (pinfunction "A_A") (pintype "passive"))
      (node (ref "D52") (pin "A") (pinfunction "A_A") (pintype "passive"))
      (node (ref "D59") (pin "A") (pinfunction "A_A") (pintype "passive"))
      (node (ref "D6") (pin "A") (pinfunction "A_A") (pintype "passive"))
      (node (ref "D60") (pin "A") (pinfunction "A_A") (pintype "passive"))
      (node (ref "D61") (pin "A") (pinfunction "A_A") (pintype "passive"))
      (node (ref "D62") (pin "A") (pinfunction "A_A") (pintype "passive"))
      (node (ref "D63") (pin "A") (pinfunction "A_A") (pintype "passive"))
      (node (ref "D64") (pin "A") (pinfunction "A_A") (pintype "passive"))
      (node (ref "D7") (pin "A") (pinfunction "A_A") (pintype "passive"))
      (node (ref "D8") (pin "A") (pinfunction "A_A") (pintype "passive"))
      (node (ref "D9") (pin "A") (pinfunction "A_A") (pintype "passive"))
      (node (ref "L4") (pin "2") (pinfunction "2_2") (pintype "passive"))
      (node (ref "L6") (pin "2") (pinfunction "2_2") (pintype "passive"))
      (node (ref "P15") (pin "1") (pinfunction "1_1") (pintype "passive"))
      (node (ref "P25") (pin "1") (pinfunction "1_1") (pintype "passive"))
      (node (ref "P9") (pin "1") (pinfunction "1_1") (pintype "passive"))
      (node (ref "R110") (pin "2") (pinfunction "2_2") (pintype "passive"))
      (node (ref "R119") (pin "1") (pinfunction "1_1") (pintype "passive"))
      (node (ref "R123_N0") (pin "1") (pinfunction "1_1") (pintype "passive"))
      (node (ref "R123_N1") (pin "1") (pinfunction "1_1") (pintype "passive"))
      (node (ref "R123_N2") (pin "1") (pinfunction "1_1") (pintype "passive"))
      (node (ref "R123_N3") (pin "1") (pinfunction "1_1") (pintype "passive"))
      (node (ref "R164") (pin "2") (pinfunction "2_2") (pintype "passive"))
      (node (ref "R194") (pin "2") (pinfunction "2_2") (pintype "passive"))
      (node (ref "R22_AL") (pin "1") (pinfunction "1_1") (pintype "passive"))
      (node (ref "R22_CY") (pin "1") (pinfunction "1_1") (pintype "passive"))
      (node (ref "R22_DR") (pin "1") (pinfunction "1_1") (pintype "passive"))
      (node (ref "R22_HL") (pin "1") (pinfunction "1_1") (pintype "passive"))
      (node (ref "R22_MC1") (pin "1") (pinfunction "1_1") (pintype "passive"))
      (node (ref "R22_MC2") (pin "1") (pinfunction "1_1") (pintype "passive"))
      (node (ref "R22_PRB") (pin "1") (pinfunction "1_1") (pintype "passive"))
      (node (ref "R22_TLO") (pin "1") (pinfunction "1_1") (pintype "passive"))
      (node (ref "R22_XL") (pin "1") (pinfunction "1_1") (pintype "passive"))
      (node (ref "R22_Y1L") (pin "1") (pinfunction "1_1") (pintype "passive"))
      (node (ref "R22_Y2L") (pin "1") (pinfunction "1_1") (pintype "passive"))
      (node (ref "R22_ZL") (pin "1") (pinfunction "1_1") (pintype "passive"))
      (node (ref "R27") (pin "2") (pinfunction "2_2") (pintype "passive"))
      (node (ref "R32") (pin "2") (pinfunction "2_2") (pintype "passive"))
      (node (ref "R35") (pin "2") (pinfunction "2_2") (pintype "passive"))
      (node (ref "R44") (pin "2") (pinfunction "2_2") (pintype "passive"))
      (node (ref "R62") (pin "2") (pinfunction "2_2") (pintype "passive"))
      (node (ref "R64") (pin "2") (pinfunction "2_2") (pintype "passive"))
      (node (ref "R65") (pin "2") (pinfunction "2_2") (pintype "passive"))
      (node (ref "R66") (pin "2") (pinfunction "2_2") (pintype "passive"))
      (node (ref "R72") (pin "2") (pinfunction "2_2") (pintype "passive"))
      (node (ref "R79") (pin "2") (pinfunction "2_2") (pintype "passive"))
      (node (ref "R8") (pin "2") (pinfunction "2_2") (pintype "passive"))
      (node (ref "R81") (pin "2") (pinfunction "2_2") (pintype "passive"))
      (node (ref "R85") (pin "2") (pinfunction "2_2") (pintype "passive"))
      (node (ref "R90") (pin "2") (pinfunction "2_2") (pintype "passive"))
      (node (ref "R92") (pin "2") (pinfunction "2_2") (pintype "passive"))
      (node (ref "R97") (pin "2") (pinfunction "2_2") (pintype "passive"))
      (node (ref "SD3") (pin "4") (pinfunction "VDD_4") (pintype "power_in"))
      (node (ref "U1") (pin "5") (pinfunction "VCC_5") (pintype "power_in"))
      (node (ref "U11") (pin "28") (pinfunction "VDD_28") (pintype "power_in"))
      (node (ref "U17") (pin "100") (pinfunction "VDD_100_100") (pintype "power_in"))
      (node (ref "U17") (pin "11") (pinfunction "VDD_11_11") (pintype "power_in"))
      (node (ref "U17") (pin "19") (pinfunction "VDD_19_19") (pintype "power_in"))
      (node (ref "U17") (pin "28") (pinfunction "VDD_28_28") (pintype "power_in"))
      (node (ref "U17") (pin "50") (pinfunction "VDD_50_50") (pintype "power_in"))
      (node (ref "U17") (pin "6") (pinfunction "VBAT_6") (pintype "power_in"))
      (node (ref "U17") (pin "75") (pinfunction "VDD_75_75") (pintype "power_in"))
      (node (ref "U26") (pin "1") (pinfunction "VDD1_1") (pintype "power_in"))
      (node (ref "U27") (pin "1") (pinfunction "VDD1_1") (pintype "power_in"))
      (node (ref "U35") (pin "8") (pinfunction "VCC_8") (pintype "power_in"))
      (node (ref "U37") (pin "1") (pinfunction "VDD1_1") (pintype "power_in"))
      (node (ref "U38") (pin "1") (pinfunction "VDD1_1") (pintype "power_in"))
      (node (ref "U45") (pin "1") (pinfunction "VDD1_1") (pintype "power_in"))
      (node (ref "U46") (pin "1") (pinfunction "VDD1_1") (pintype "power_in"))
      (node (ref "VR1") (pin "2") (pinfunction "OUT_2") (pintype "output"))
      (node (ref "VR1") (pin "4") (pinfunction "OUT_4") (pintype "output"))
    )
    (net (code "399") (name "VCC_MCU_5V0") (class "Default")
      (node (ref "C54") (pin "1") (pinfunction "1_1") (pintype "passive"))
      (node (ref "C55") (pin "1") (pinfunction "1_1") (pintype "passive"))
      (node (ref "C56") (pin "1") (pinfunction "1_1") (pintype "passive"))
      (node (ref "C57") (pin "+") (pinfunction "+_+") (pintype "passive"))
      (node (ref "C58") (pin "1") (pinfunction "1_1") (pintype "passive"))
      (node (ref "C60") (pin "1") (pinfunction "1_1") (pintype "passive"))
      (node (ref "D23") (pin "C") (pinfunction "C_C") (pintype "passive"))
      (node (ref "L10") (pin "1") (pinfunction "1_1") (pintype "passive"))
      (node (ref "L8") (pin "1") (pinfunction "1_1") (pintype "passive"))
      (node (ref "L8") (pin "2") (pinfunction "2_2") (pintype "passive"))
      (node (ref "P8") (pin "1") (pinfunction "1_1") (pintype "passive"))
      (node (ref "R151") (pin "2") (pinfunction "2_2") (pintype "passive"))
      (node (ref "R152") (pin "2") (pinfunction "2_2") (pintype "passive"))
      (node (ref "R155") (pin "2") (pinfunction "2_2") (pintype "passive"))
      (node (ref "R156") (pin "2") (pinfunction "2_2") (pintype "passive"))
      (node (ref "R34") (pin "1") (pinfunction "1_1") (pintype "passive"))
      (node (ref "VR1") (pin "3") (pinfunction "IN_3") (pintype "input"))
    )
    (net (code "400") (name "VCC_SYS_5V0") (class "Default")
      (node (ref "C11") (pin "1") (pinfunction "1_1") (pintype "passive"))
      (node (ref "C116") (pin "1") (pinfunction "1_1") (pintype "passive"))
      (node (ref "C12") (pin "1") (pinfunction "1_1") (pintype "passive"))
      (node (ref "C122") (pin "1") (pinfunction "1_1") (pintype "passive"))
      (node (ref "C13") (pin "1") (pinfunction "1_1") (pintype "passive"))
      (node (ref "C14") (pin "1") (pinfunction "1_1") (pintype "passive"))
      (node (ref "C4") (pin "1") (pinfunction "1_1") (pintype "passive"))
      (node (ref "C40") (pin "1") (pinfunction "1_1") (pintype "passive"))
      (node (ref "C41") (pin "1") (pinfunction "1_1") (pintype "passive"))
      (node (ref "C44") (pin "1") (pinfunction "1_1") (pintype "passive"))
      (node (ref "C45") (pin "1") (pinfunction "1_1") (pintype "passive"))
      (node (ref "C46") (pin "1") (pinfunction "1_1") (pintype "passive"))
      (node (ref "C47") (pin "1") (pinfunction "1_1") (pintype "passive"))
      (node (ref "C49") (pin "1") (pinfunction "1_1") (pintype "passive"))
      (node (ref "C52") (pin "1") (pinfunction "1_1") (pintype "passive"))
      (node (ref "C53") (pin "1") (pinfunction "1_1") (pintype "passive"))
      (node (ref "C6") (pin "1") (pinfunction "1_1") (pintype "passive"))
      (node (ref "C7") (pin "1") (pinfunction "1_1") (pintype "passive"))
      (node (ref "C92") (pin "1") (pinfunction "1_1") (pintype "passive"))
      (node (ref "C93") (pin "1") (pinfunction "1_1") (pintype "passive"))
      (node (ref "C95") (pin "1") (pinfunction "1_1") (pintype "passive"))
      (node (ref "D20") (pin "A") (pinfunction "A_A") (pintype "passive"))
      (node (ref "D21") (pin "C") (pinfunction "C_C") (pintype "passive"))
      (node (ref "D22") (pin "C") (pinfunction "C_C") (pintype "passive"))
      (node (ref "D35") (pin "2") (pinfunction "2_2") (pintype "passive"))
      (node (ref "D53") (pin "2") (pinfunction "2_2") (pintype "passive"))
      (node (ref "D54") (pin "2") (pinfunction "2_2") (pintype "passive"))
      (node (ref "D55") (pin "2") (pinfunction "2_2") (pintype "passive"))
      (node (ref "J19") (pin "1") (pinfunction "1_1") (pintype "passive"))
      (node (ref "L1") (pin "1") (pinfunction "1_1") (pintype "passive"))
      (node (ref "L12") (pin "2") (pinfunction "2_2") (pintype "passive"))
      (node (ref "L3") (pin "2") (pinfunction "2_2") (pintype "passive"))
      (node (ref "P11") (pin "15") (pinfunction "15_15") (pintype "passive"))
      (node (ref "P11") (pin "7") (pinfunction "7_7") (pintype "passive"))
      (node (ref "P13") (pin "5") (pinfunction "5_5") (pintype "passive"))
      (node (ref "P14") (pin "5") (pinfunction "5_5") (pintype "passive"))
      (node (ref "P16") (pin "5") (pinfunction "5_5") (pintype "passive"))
      (node (ref "P23") (pin "2") (pinfunction "2_2") (pintype "passive"))
      (node (ref "P27") (pin "5") (pinfunction "5_5") (pintype "passive"))
      (node (ref "R101") (pin "2") (pinfunction "2_2") (pintype "passive"))
      (node (ref "R105_RL1") (pin "2") (pinfunction "2_2") (pintype "passive"))
      (node (ref "R105_RL2") (pin "2") (pinfunction "2_2") (pintype "passive"))
      (node (ref "R111") (pin "1") (pinfunction "1_1") (pintype "passive"))
      (node (ref "R112") (pin "2") (pinfunction "2_2") (pintype "passive"))
      (node (ref "R113") (pin "1") (pinfunction "1_1") (pintype "passive"))
      (node (ref "R115") (pin "1") (pinfunction "1_1") (pintype "passive"))
      (node (ref "R117") (pin "1") (pinfunction "1_1") (pintype "passive"))
      (node (ref "R120") (pin "2") (pinfunction "2_2") (pintype "passive"))
      (node (ref "R121_AO0") (pin "1") (pinfunction "1_1") (pintype "passive"))
      (node (ref "R121_AO1") (pin "1") (pinfunction "1_1") (pintype "passive"))
      (node (ref "R121_AO2") (pin "1") (pinfunction "1_1") (pintype "passive"))
      (node (ref "R121_AO3") (pin "1") (pinfunction "1_1") (pintype "passive"))
      (node (ref "R121_COO") (pin "1") (pinfunction "1_1") (pintype "passive"))
      (node (ref "R121_MIS") (pin "1") (pinfunction "1_1") (pintype "passive"))
      (node (ref "R193") (pin "1") (pinfunction "1_1") (pintype "passive"))
      (node (ref "R195") (pin "1") (pinfunction "1_1") (pintype "passive"))
      (node (ref "R23_CY") (pin "2") (pinfunction "2_2") (pintype "passive"))
      (node (ref "R23_HL") (pin "2") (pinfunction "2_2") (pintype "passive"))
      (node (ref "R23_MC1") (pin "2") (pinfunction "2_2") (pintype "passive"))
      (node (ref "R23_MC2") (pin "2") (pinfunction "2_2") (pintype "passive"))
      (node (ref "R24") (pin "1") (pinfunction "1_1") (pintype "passive"))
      (node (ref "R33_TR1") (pin "2") (pinfunction "2_2") (pintype "passive"))
      (node (ref "R33_TR2") (pin "2") (pinfunction "2_2") (pintype "passive"))
      (node (ref "R36") (pin "1") (pinfunction "1_1") (pintype "passive"))
      (node (ref "R38") (pin "1") (pinfunction "1_1") (pintype "passive"))
      (node (ref "R40") (pin "1") (pinfunction "1_1") (pintype "passive"))
      (node (ref "R55") (pin "1") (pinfunction "1_1") (pintype "passive"))
      (node (ref "R78") (pin "1") (pinfunction "1_1") (pintype "passive"))
      (node (ref "R80") (pin "1") (pinfunction "1_1") (pintype "passive"))
      (node (ref "R9") (pin "1") (pinfunction "1_1") (pintype "passive"))
      (node (ref "R96") (pin "2") (pinfunction "2_2") (pintype "passive"))
      (node (ref "U26") (pin "8") (pinfunction "VDD2_8") (pintype "power_in"))
      (node (ref "U27") (pin "8") (pinfunction "VDD2_8") (pintype "power_in"))
      (node (ref "U28") (pin "1") (pinfunction "VDD_1") (pintype "bidirectional"))
      (node (ref "U3") (pin "5") (pinfunction "VCC_5") (pintype "power_in"))
      (node (ref "U36") (pin "16") (pinfunction "VCC_16") (pintype "power_in"))
      (node (ref "U37") (pin "8") (pinfunction "VDD2_8") (pintype "power_in"))
      (node (ref "U38") (pin "8") (pinfunction "VDD2_8") (pintype "power_in"))
      (node (ref "U41") (pin "3") (pinfunction "VS_3") (pintype "power_in"))
      (node (ref "U45") (pin "8") (pinfunction "VDD2_8") (pintype "power_in"))
      (node (ref "U46") (pin "8") (pinfunction "VDD2_8") (pintype "power_in"))
      (node (ref "U9") (pin "16") (pinfunction "VCC_16") (pintype "power_in"))
    )
    (net (code "401") (name "VCC_SYS_5V0_RS485") (class "Default")
      (node (ref "C8") (pin "1") (pinfunction "1_1") (pintype "passive"))
      (node (ref "C9") (pin "2") (pinfunction "2_2") (pintype "passive"))
      (node (ref "D40") (pin "C") (pinfunction "-_C") (pintype "passive"))
      (node (ref "J10") (pin "02") (pinfunction "02_02") (pintype "passive"))
      (node (ref "L1") (pin "2") (pinfunction "2_2") (pintype "passive"))
      (node (ref "R45") (pin "2") (pinfunction "2_2") (pintype "passive"))
      (node (ref "R47") (pin "2") (pinfunction "2_2") (pintype "passive"))
      (node (ref "R48") (pin "2") (pinfunction "2_2") (pintype "passive"))
      (node (ref "U13") (pin "8") (pinfunction "VCC_8") (pintype "power_in"))
      (node (ref "U15") (pin "4") (pinfunction "CT_4") (pintype "passive"))
    )
    (net (code "402") (name "VCC_SYS_24V0") (class "Default")
      (node (ref "C15") (pin "1") (pinfunction "1_1") (pintype "passive"))
      (node (ref "C16") (pin "1") (pinfunction "1_1") (pintype "passive"))
      (node (ref "C77") (pin "1") (pinfunction "1_1") (pintype "passive"))
      (node (ref "C78") (pin "1") (pinfunction "1_1") (pintype "passive"))
      (node (ref "C79") (pin "1") (pinfunction "1_1") (pintype "passive"))
      (node (ref "C80") (pin "1") (pinfunction "1_1") (pintype "passive"))
      (node (ref "D30_RL1") (pin "C") (pinfunction "C_C") (pintype "passive"))
      (node (ref "D30_RL2") (pin "C") (pinfunction "C_C") (pintype "passive"))
      (node (ref "D45") (pin "1") (pinfunction "C_1") (pintype "passive"))
      (node (ref "K2") (pin "85") (pinfunction "85_85") (pintype "passive"))
      (node (ref "L5") (pin "2") (pinfunction "2_2") (pintype "passive"))
      (node (ref "P11") (pin "18") (pinfunction "18_18") (pintype "passive"))
      (node (ref "P18_RL1") (pin "2") (pinfunction "2_2") (pintype "passive"))
      (node (ref "P18_RL2") (pin "2") (pinfunction "2_2") (pintype "passive"))
      (node (ref "P5") (pin "1") (pinfunction "1_1") (pintype "passive"))
      (node (ref "P6") (pin "2") (pinfunction "2_2") (pintype "passive"))
      (node (ref "R10") (pin "1") (pinfunction "1_1") (pintype "passive"))
      (node (ref "R100") (pin "2") (pinfunction "2_2") (pintype "passive"))
      (node (ref "R109_RL1") (pin "2") (pinfunction "2_2") (pintype "passive"))
      (node (ref "R109_RL2") (pin "2") (pinfunction "2_2") (pintype "passive"))
      (node (ref "R175") (pin "2") (pinfunction "2_2") (pintype "passive"))
      (node (ref "R176") (pin "2") (pinfunction "2_2") (pintype "passive"))
      (node (ref "R196") (pin "1") (pinfunction "1_1") (pintype "passive"))
      (node (ref "U16") (pin "2") (pinfunction "VIN_2") (pintype "input"))
    )
    (net (code "403") (name "VDDA_3V3") (class "Default")
      (node (ref "C23") (pin "1") (pinfunction "1_1") (pintype "passive"))
      (node (ref "C24") (pin "1") (pinfunction "1_1") (pintype "passive"))
      (node (ref "C97") (pin "1") (pinfunction "1_1") (pintype "passive"))
      (node (ref "L4") (pin "1") (pinfunction "1_1") (pintype "passive"))
      (node (ref "U17") (pin "21") (pinfunction "VREF+_21") (pintype "power_in"))
      (node (ref "U17") (pin "22") (pinfunction "VDDA_22") (pintype "power_in"))
    )
    (net (code "404") (name "VSENSE") (class "Default")
      (node (ref "R55") (pin "2") (pinfunction "2_2") (pintype "passive"))
      (node (ref "R57") (pin "1") (pinfunction "1_1") (pintype "passive"))
      (node (ref "U16") (pin "5") (pinfunction "VSENSE_5") (pintype "input"))
    )
    (net (code "405") (name "VSS") (class "Default")
      (node (ref "R102") (pin "2") (pinfunction "2_2") (pintype "passive"))
      (node (ref "U17") (pin "49") (pinfunction "VSS_49") (pintype "power_in"))
    )
    (net (code "406") (name "W5500_INT_N") (class "Default")
      (node (ref "J1") (pin "2") (pinfunction "2_2") (pintype "bidirectional"))
      (node (ref "U11") (pin "36") (pinfunction "~{INTN}_36") (pintype "input"))
    )
    (net (code "407") (name "W5500_RST_N") (class "Default")
      (node (ref "C82") (pin "2") (pinfunction "2_2") (pintype "passive"))
      (node (ref "J1") (pin "4") (pinfunction "4_4") (pintype "bidirectional"))
      (node (ref "R135") (pin "2") (pinfunction "2_2") (pintype "passive"))
      (node (ref "U11") (pin "37") (pinfunction "~{RSTN}_37") (pintype "input"))
    )
    (net (code "408") (name "XI") (class "Default")
      (node (ref "R149") (pin "2") (pinfunction "2_2") (pintype "passive"))
      (node (ref "U11") (pin "30") (pinfunction "XI_30") (pintype "input"))
    )
    (net (code "409") (name "XO") (class "Default")
      (node (ref "C121") (pin "1") (pinfunction "1_1") (pintype "passive"))
      (node (ref "R147") (pin "1") (pinfunction "1_1") (pintype "passive"))
      (node (ref "U11") (pin "31") (pinfunction "XO_31") (pintype "output"))
      (node (ref "Y3") (pin "1") (pinfunction "1_1") (pintype "passive"))
    )
    (net (code "410") (name "X_ALARM_5V_N") (class "Default")
      (node (ref "P13") (pin "8") (pinfunction "8_8") (pintype "passive"))
      (node (ref "U39") (pin "2") (pinfunction "C_2") (pintype "passive"))
    )
    (net (code "411") (name "X_LIM") (class "Default")
      (node (ref "C3_XL") (pin "1") (pinfunction "1_1") (pintype "passive"))
      (node (ref "R13") (pin "2") (pinfunction "2_2") (pintype "passive"))
      (node (ref "R22_XL") (pin "2") (pinfunction "2_2") (pintype "passive"))
      (node (ref "U17") (pin "91") (pinfunction "PB5/CAN2_RX/SPI3_MOSI_91") (pintype "bidirectional"))
      (node (ref "U2_XL") (pin "4") (pinfunction "CT_4") (pintype "passive"))
    )
    (net (code "412") (name "X_LIM_EXT") (class "Default")
      (node (ref "J4") (pin "1") (pinfunction "1_1") (pintype "passive"))
      (node (ref "P17") (pin "06") (pinfunction "06_06") (pintype "passive"))
      (node (ref "U2_XL") (pin "2") (pinfunction "C_2") (pintype "passive"))
    )
    (net (code "413") (name "Y1_ALARM_5V_N") (class "Default")
      (node (ref "P14") (pin "8") (pinfunction "8_8") (pintype "passive"))
      (node (ref "U47") (pin "2") (pinfunction "C_2") (pintype "passive"))
    )
    (net (code "414") (name "Y1_LIM") (class "Default")
      (node (ref "C3_Y1L") (pin "1") (pinfunction "1_1") (pintype "passive"))
      (node (ref "R14") (pin "2") (pinfunction "2_2") (pintype "passive"))
      (node (ref "R22_Y1L") (pin "2") (pinfunction "2_2") (pintype "passive"))
      (node (ref "U17") (pin "96") (pinfunction "PB9/TIM4_CH4_96") (pintype "bidirectional"))
      (node (ref "U2_Y1L") (pin "4") (pinfunction "CT_4") (pintype "passive"))
    )
    (net (code "415") (name "Y1_LIM_EXT") (class "Default")
      (node (ref "J5") (pin "1") (pinfunction "1_1") (pintype "passive"))
      (node (ref "P17") (pin "05") (pinfunction "05_05") (pintype "passive"))
      (node (ref "U2_Y1L") (pin "2") (pinfunction "C_2") (pintype "passive"))
    )
    (net (code "416") (name "Y2_ALARM_5V_N") (class "Default")
      (node (ref "P16") (pin "8") (pinfunction "8_8") (pintype "passive"))
      (node (ref "U49") (pin "2") (pinfunction "C_2") (pintype "passive"))
    )
    (net (code "417") (name "Y2_LIM") (class "Default")
      (node (ref "C3_Y2L") (pin "1") (pinfunction "1_1") (pintype "passive"))
      (node (ref "R15") (pin "2") (pinfunction "2_2") (pintype "passive"))
      (node (ref "R22_Y2L") (pin "2") (pinfunction "2_2") (pintype "passive"))
      (node (ref "U17") (pin "5") (pinfunction "PE6/TRACED3/TIM9_CH2_5") (pintype "bidirectional"))
      (node (ref "U2_Y2L") (pin "4") (pinfunction "CT_4") (pintype "passive"))
    )
    (net (code "418") (name "Y2_LIM_EXT") (class "Default")
      (node (ref "J6") (pin "1") (pinfunction "1_1") (pintype "passive"))
      (node (ref "P17") (pin "04") (pinfunction "04_04") (pintype "passive"))
      (node (ref "U2_Y2L") (pin "2") (pinfunction "C_2") (pintype "passive"))
    )
    (net (code "419") (name "YEL_LED") (class "Default")
      (node (ref "R150") (pin "2") (pinfunction "2_2") (pintype "passive"))
      (node (ref "U11") (pin "27") (pinfunction "ACTLED_27") (pintype "output"))
    )
    (net (code "420") (name "Z_ALARM_5V_N") (class "Default")
      (node (ref "P27") (pin "8") (pinfunction "8_8") (pintype "passive"))
      (node (ref "U48") (pin "2") (pinfunction "C_2") (pintype "passive"))
    )
    (net (code "421") (name "Z_LIM") (class "Default")
      (node (ref "C3_ZL") (pin "1") (pinfunction "1_1") (pintype "passive"))
      (node (ref "R16") (pin "2") (pinfunction "2_2") (pintype "passive"))
      (node (ref "R22_ZL") (pin "2") (pinfunction "2_2") (pintype "passive"))
      (node (ref "U17") (pin "7") (pinfunction "PC13_7") (pintype "bidirectional"))
      (node (ref "U2_ZL") (pin "4") (pinfunction "CT_4") (pintype "passive"))
    )
    (net (code "422") (name "Z_LIM_EXT") (class "Default")
      (node (ref "J7") (pin "1") (pinfunction "1_1") (pintype "passive"))
      (node (ref "P17") (pin "03") (pinfunction "03_03") (pintype "passive"))
      (node (ref "U2_ZL") (pin "2") (pinfunction "C_2") (pintype "passive"))
    )
    (net (code "423") (name "unconnected-(J4-Pad2)") (class "Default")
      (node (ref "J4") (pin "2") (pinfunction "2_2") (pintype "passive"))
    )
    (net (code "424") (name "unconnected-(J5-Pad2)") (class "Default")
      (node (ref "J5") (pin "2") (pinfunction "2_2") (pintype "passive"))
    )
    (net (code "425") (name "unconnected-(J6-Pad2)") (class "Default")
      (node (ref "J6") (pin "2") (pinfunction "2_2") (pintype "passive"))
    )
    (net (code "426") (name "unconnected-(J7-Pad2)") (class "Default")
      (node (ref "J7") (pin "2") (pinfunction "2_2") (pintype "passive"))
    )
    (net (code "427") (name "unconnected-(J8-Pad2)") (class "Default")
      (node (ref "J8") (pin "2") (pinfunction "2_2") (pintype "passive"))
    )
    (net (code "428") (name "unconnected-(J12-Pad2)") (class "Default")
      (node (ref "J12") (pin "2") (pinfunction "2_2") (pintype "passive"))
    )
    (net (code "429") (name "unconnected-(J12-Pad5)") (class "Default")
      (node (ref "J12") (pin "5") (pinfunction "5_5") (pintype "passive"))
    )
    (net (code "430") (name "unconnected-(J15-Pad2)") (class "Default")
      (node (ref "J15") (pin "2") (pinfunction "2_2") (pintype "passive"))
    )
    (net (code "431") (name "unconnected-(K1_TR1-Pad3)") (class "Default")
      (node (ref "K1_TR1") (pin "3") (pinfunction "3_3") (pintype "bidirectional"))
    )
    (net (code "432") (name "unconnected-(K1_TR1-Pad5)") (class "Default")
      (node (ref "K1_TR1") (pin "5") (pinfunction "5_5") (pintype "bidirectional"))
    )
    (net (code "433") (name "unconnected-(K1_TR2-Pad3)") (class "Default")
      (node (ref "K1_TR2") (pin "3") (pinfunction "3_3") (pintype "bidirectional"))
    )
    (net (code "434") (name "unconnected-(K1_TR2-Pad5)") (class "Default")
      (node (ref "K1_TR2") (pin "5") (pinfunction "5_5") (pintype "bidirectional"))
    )
    (net (code "435") (name "unconnected-(K2-Pad87A)") (class "Default")
      (node (ref "K2") (pin "87A") (pinfunction "87A_87A") (pintype "passive"))
    )
    (net (code "436") (name "unconnected-(P8-Pad2)") (class "Default")
      (node (ref "P8") (pin "2") (pinfunction "2_2") (pintype "passive"))
    )
    (net (code "437") (name "unconnected-(P11-Pad1)") (class "Default")
      (node (ref "P11") (pin "1") (pinfunction "1_1") (pintype "passive"))
    )
    (net (code "438") (name "unconnected-(P11-Pad5)") (class "Default")
      (node (ref "P11") (pin "5") (pinfunction "5_5") (pintype "passive"))
    )
    (net (code "439") (name "unconnected-(P11-Pad9)") (class "Default")
      (node (ref "P11") (pin "9") (pinfunction "9_9") (pintype "passive"))
    )
    (net (code "440") (name "unconnected-(P11-Pad11)") (class "Default")
      (node (ref "P11") (pin "11") (pinfunction "11_11") (pintype "passive"))
    )
    (net (code "441") (name "unconnected-(P11-Pad12)") (class "Default")
      (node (ref "P11") (pin "12") (pinfunction "12_12") (pintype "passive"))
    )
    (net (code "442") (name "unconnected-(P11-Pad39)") (class "Default")
      (node (ref "P11") (pin "39") (pinfunction "39_39") (pintype "passive"))
    )
    (net (code "443") (name "unconnected-(P15-4-Pad7)") (class "Default")
      (node (ref "P15") (pin "7") (pinfunction "4_7") (pintype "passive"))
    )
    (net (code "444") (name "unconnected-(P15-5-Pad9)") (class "Default")
      (node (ref "P15") (pin "9") (pinfunction "5_9") (pintype "passive"))
    )
    (net (code "445") (name "unconnected-(P15-7-Pad8)") (class "Default")
      (node (ref "P15") (pin "8") (pinfunction "7_8") (pintype "passive"))
    )
    (net (code "446") (name "unconnected-(P15-8-Pad6)") (class "Default")
      (node (ref "P15") (pin "6") (pinfunction "8_6") (pintype "passive"))
    )
    (net (code "447") (name "unconnected-(S1-PadRIGHT)") (class "Default")
      (node (ref "S1") (pin "RIGHT") (pinfunction "RIGHT_RIGHT") (pintype "bidirectional"))
    )
    (net (code "448") (name "unconnected-(SD3-DAT1-Pad8)") (class "Default")
      (node (ref "SD3") (pin "8") (pinfunction "DAT1_8") (pintype "bidirectional"))
    )
    (net (code "449") (name "unconnected-(SD3-DAT2-Pad1)") (class "Default")
      (node (ref "SD3") (pin "1") (pinfunction "DAT2_1") (pintype "bidirectional"))
    )
    (net (code "450") (name "unconnected-(SD3-~{CARD}-Pad9)") (class "Default")
      (node (ref "SD3") (pin "9") (pinfunction "~{CARD}_9") (pintype "passive"))
    )
    (net (code "451") (name "unconnected-(U9-G-Pad4)") (class "Default")
      (node (ref "U9") (pin "4") (pinfunction "G_4") (pintype "input"))
    )
    (net (code "452") (name "unconnected-(U11-DNC-Pad7)") (class "Default")
      (node (ref "U11") (pin "7") (pinfunction "DNC_7") (pintype "bidirectional"))
    )
    (net (code "453") (name "unconnected-(U11-DUPLED-Pad26)") (class "Default")
      (node (ref "U11") (pin "26") (pinfunction "DUPLED_26") (pintype "output"))
    )
    (net (code "454") (name "unconnected-(U11-RSVD1-Pad23)") (class "Default")
      (node (ref "U11") (pin "23") (pinfunction "RSVD1_23") (pintype "input"))
    )
    (net (code "455") (name "unconnected-(U11-RSVD2-Pad38)") (class "Default")
      (node (ref "U11") (pin "38") (pinfunction "RSVD2_38") (pintype "input"))
    )
    (net (code "456") (name "unconnected-(U11-RSVD3-Pad39)") (class "Default")
      (node (ref "U11") (pin "39") (pinfunction "RSVD3_39") (pintype "input"))
    )
    (net (code "457") (name "unconnected-(U11-RSVD4-Pad40)") (class "Default")
      (node (ref "U11") (pin "40") (pinfunction "RSVD4_40") (pintype "input"))
    )
    (net (code "458") (name "unconnected-(U11-RSVD5-Pad41)") (class "Default")
      (node (ref "U11") (pin "41") (pinfunction "RSVD5_41") (pintype "input"))
    )
    (net (code "459") (name "unconnected-(U11-RSVD6-Pad42)") (class "Default")
      (node (ref "U11") (pin "42") (pinfunction "RSVD6_42") (pintype "input"))
    )
    (net (code "460") (name "unconnected-(U11-SPDLED-Pad24)") (class "Default")
      (node (ref "U11") (pin "24") (pinfunction "SPDLED_24") (pintype "output"))
    )
    (net (code "461") (name "unconnected-(U11-VBG-Pad18)") (class "Default")
      (node (ref "U11") (pin "18") (pinfunction "VBG_18") (pintype "output"))
    )
    (net (code "462") (name "unconnected-(U16-EN-Pad3)") (class "Default")
      (node (ref "U16") (pin "3") (pinfunction "EN_3") (pintype "input"))
    )
    (net (code "463") (name "unconnected-(U17-PB13{slash}SPI2_SCK-Pad52)") (class "Default")
      (node (ref "U17") (pin "52") (pinfunction "PB13/SPI2_SCK_52") (pintype "bidirectional"))
    )
    (net (code "464") (name "unconnected-(U17-PC2{slash}SPI2_MISO-Pad17)") (class "Default")
      (node (ref "U17") (pin "17") (pinfunction "PC2/SPI2_MISO_17") (pintype "bidirectional"))
    )
    (net (code "465") (name "unconnected-(U17-PC3{slash}SPI2_MOSI-Pad18)") (class "Default")
      (node (ref "U17") (pin "18") (pinfunction "PC3/SPI2_MOSI_18") (pintype "bidirectional"))
    )
    (net (code "466") (name "unconnected-(U17-PD9{slash}USART3_RX-Pad56)") (class "Default")
      (node (ref "U17") (pin "56") (pinfunction "PD9/USART3_RX_56") (pintype "bidirectional"))
    )
    (net (code "467") (name "unconnected-(U17-PD11{slash}USART3_CTS-Pad58)") (class "Default")
      (node (ref "U17") (pin "58") (pinfunction "PD11/USART3_CTS_58") (pintype "bidirectional"))
    )
    (net (code "468") (name "unconnected-(U17-PE12{slash}TIM1_CH3N-Pad43)") (class "Default")
      (node (ref "U17") (pin "43") (pinfunction "PE12/TIM1_CH3N_43") (pintype "bidirectional"))
    )
    (net (code "469") (name "unconnected-(U17-PE15{slash}TIM1_BKIN-Pad46)") (class "Default")
      (node (ref "U17") (pin "46") (pinfunction "PE15/TIM1_BKIN_46") (pintype "bidirectional"))
    )
    (net (code "470") (name "unconnected-(U19-VREF-Pad5)") (class "Default")
      (node (ref "U19") (pin "5") (pinfunction "VREF_5") (pintype "output"))
    )
    (net (code "471") (name "unconnected-(U24-SYNCOUT-Pad7)") (class "Default")
      (node (ref "U24") (pin "7") (pinfunction "SYNCOUT_7") (pintype "output"))
    )
    (net (code "472") (name "unconnected-(U36-G-Pad4)") (class "Default")
      (node (ref "U36") (pin "4") (pinfunction "G_4") (pintype "input"))
    )
    (net (code "473") (name "unconnected-(U50-THR-Pad6)") (class "Default")
      (node (ref "U50") (pin "6") (pinfunction "THR_6") (pintype "input"))
    )
  )
)
